# DRI-flexpcb-12s4p.net
KiCad netlist of a schematic drawn in EAGLE
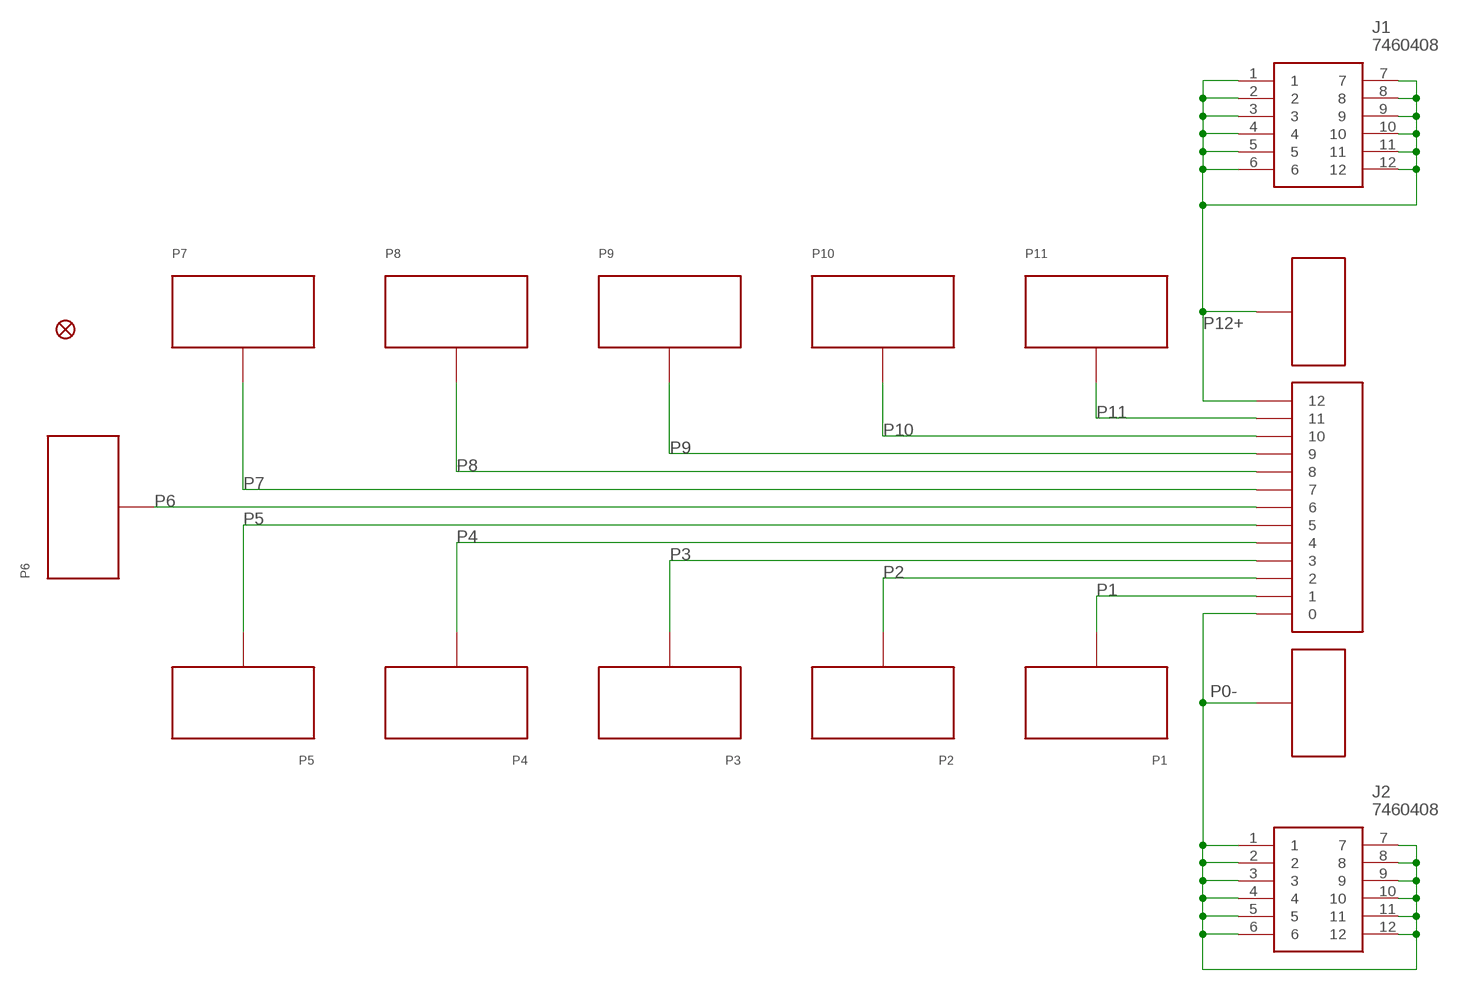
[diagram p0: schematic, sheet 1]

(export (version "E")
  (design (tool "Eeschema 10.0.6"))
  (components
    (comp (ref "FD2")
      (value "FIDUCIAL1X2")
      (footprint "eagle-import:FIDUCIAL-1X2")
      (libsource (lib "eagle-import") (part "FIDUCIAL1X2"))
    )
    (comp (ref "J1")
      (value "7460408")
      (footprint "eagle-import:7460408")
      (fields (field (name "MOUSER_PART_NUMBER") "710-7460408"))
      (libsource (lib "eagle-import") (part "7460408"))
    )
    (comp (ref "J2")
      (value "7460408")
      (footprint "eagle-import:7460408")
      (fields (field (name "MOUSER_PART_NUMBER") "710-7460408"))
      (libsource (lib "eagle-import") (part "7460408"))
    )
    (comp (ref "JP1")
      (value "13P-JST-2MM")
      (footprint "eagle-import:13P-JST-2MM")
      (libsource (lib "eagle-import") (part "13P-JST-2MM"))
    )
    (comp (ref "P0")
      (value "BUS-TERM-PAD-")
      (footprint "eagle-import:TERM-PAD-")
      (libsource (lib "eagle-import") (part "BUS-TERM-PAD-"))
    )
    (comp (ref "P1")
      (value "BAT-TERM-L")
      (footprint "eagle-import:BAT-TERM-L")
      (libsource (lib "eagle-import") (part "BAT-TERM-L"))
    )
    (comp (ref "P2")
      (value "BAT-TERM-M")
      (footprint "eagle-import:BAT-TERM-M")
      (libsource (lib "eagle-import") (part "BAT-TERM-M"))
    )
    (comp (ref "P3")
      (value "BAT-TERM-L")
      (footprint "eagle-import:BAT-TERM-L")
      (libsource (lib "eagle-import") (part "BAT-TERM-L"))
    )
    (comp (ref "P4")
      (value "BAT-TERM-M")
      (footprint "eagle-import:BAT-TERM-M")
      (libsource (lib "eagle-import") (part "BAT-TERM-M"))
    )
    (comp (ref "P5")
      (value "BAT-TERM-L")
      (footprint "eagle-import:BAT-TERM-L")
      (libsource (lib "eagle-import") (part "BAT-TERM-L"))
    )
    (comp (ref "P6")
      (value "BAT-TERM-END")
      (footprint "eagle-import:BAT-TERM-END")
      (libsource (lib "eagle-import") (part "BAT-TERM-END"))
    )
    (comp (ref "P7")
      (value "BAT-TERM-L")
      (footprint "eagle-import:BAT-TERM-L")
      (libsource (lib "eagle-import") (part "BAT-TERM-L"))
    )
    (comp (ref "P8")
      (value "BAT-TERM-M")
      (footprint "eagle-import:BAT-TERM-M")
      (libsource (lib "eagle-import") (part "BAT-TERM-M"))
    )
    (comp (ref "P9")
      (value "BAT-TERM-L")
      (footprint "eagle-import:BAT-TERM-L")
      (libsource (lib "eagle-import") (part "BAT-TERM-L"))
    )
    (comp (ref "P10")
      (value "BAT-TERM-M")
      (footprint "eagle-import:BAT-TERM-M")
      (libsource (lib "eagle-import") (part "BAT-TERM-M"))
    )
    (comp (ref "P11")
      (value "BAT-TERM-L")
      (footprint "eagle-import:BAT-TERM-L")
      (libsource (lib "eagle-import") (part "BAT-TERM-L"))
    )
    (comp (ref "P12")
      (value "BUS-TERM-PAD+")
      (footprint "eagle-import:TERM-PAD-")
      (libsource (lib "eagle-import") (part "BUS-TERM-PAD+"))
    )
  )
  (nets
    (net (code "1") (name "/P0-") (class "Default")
      (node (ref "J2") (pin "1") (pinfunction "1_1") (pintype "bidirectional"))
      (node (ref "J2") (pin "10") (pinfunction "10_10") (pintype "bidirectional"))
      (node (ref "J2") (pin "11") (pinfunction "11_11") (pintype "bidirectional"))
      (node (ref "J2") (pin "12") (pinfunction "12_12") (pintype "bidirectional"))
      (node (ref "J2") (pin "2") (pinfunction "2_2") (pintype "bidirectional"))
      (node (ref "J2") (pin "3") (pinfunction "3_3") (pintype "bidirectional"))
      (node (ref "J2") (pin "4") (pinfunction "4_4") (pintype "bidirectional"))
      (node (ref "J2") (pin "5") (pinfunction "5_5") (pintype "bidirectional"))
      (node (ref "J2") (pin "6") (pinfunction "6_6") (pintype "bidirectional"))
      (node (ref "J2") (pin "7") (pinfunction "7_7") (pintype "bidirectional"))
      (node (ref "J2") (pin "8") (pinfunction "8_8") (pintype "bidirectional"))
      (node (ref "J2") (pin "9") (pinfunction "9_9") (pintype "bidirectional"))
      (node (ref "JP1") (pin "P$1") (pinfunction "0_P$1") (pintype "bidirectional"))
      (node (ref "P0") (pin "P$10") (pinfunction "P$0_P$10") (pintype "power_in"))
      (node (ref "P0") (pin "P$100") (pinfunction "P$0_P$100") (pintype "power_in"))
      (node (ref "P0") (pin "P$101") (pinfunction "P$0_P$101") (pintype "power_in"))
      (node (ref "P0") (pin "P$102") (pinfunction "P$0_P$102") (pintype "power_in"))
      (node (ref "P0") (pin "P$103") (pinfunction "P$0_P$103") (pintype "power_in"))
      (node (ref "P0") (pin "P$104") (pinfunction "P$0_P$104") (pintype "power_in"))
      (node (ref "P0") (pin "P$105") (pinfunction "P$0_P$105") (pintype "power_in"))
      (node (ref "P0") (pin "P$106") (pinfunction "P$0_P$106") (pintype "power_in"))
      (node (ref "P0") (pin "P$107") (pinfunction "P$0_P$107") (pintype "power_in"))
      (node (ref "P0") (pin "P$108") (pinfunction "P$0_P$108") (pintype "power_in"))
      (node (ref "P0") (pin "P$109") (pinfunction "P$0_P$109") (pintype "power_in"))
      (node (ref "P0") (pin "P$11") (pinfunction "P$0_P$11") (pintype "power_in"))
      (node (ref "P0") (pin "P$110") (pinfunction "P$0_P$110") (pintype "power_in"))
      (node (ref "P0") (pin "P$12") (pinfunction "P$0_P$12") (pintype "power_in"))
      (node (ref "P0") (pin "P$13") (pinfunction "P$0_P$13") (pintype "power_in"))
      (node (ref "P0") (pin "P$14") (pinfunction "P$0_P$14") (pintype "power_in"))
      (node (ref "P0") (pin "P$15") (pinfunction "P$0_P$15") (pintype "power_in"))
      (node (ref "P0") (pin "P$16") (pinfunction "P$0_P$16") (pintype "power_in"))
      (node (ref "P0") (pin "P$17") (pinfunction "P$0_P$17") (pintype "power_in"))
      (node (ref "P0") (pin "P$18") (pinfunction "P$0_P$18") (pintype "power_in"))
      (node (ref "P0") (pin "P$181") (pinfunction "P$0_P$181") (pintype "power_in"))
      (node (ref "P0") (pin "P$182") (pinfunction "P$0_P$182") (pintype "power_in"))
      (node (ref "P0") (pin "P$183") (pinfunction "P$0_P$183") (pintype "power_in"))
      (node (ref "P0") (pin "P$184") (pinfunction "P$0_P$184") (pintype "power_in"))
      (node (ref "P0") (pin "P$185") (pinfunction "P$0_P$185") (pintype "power_in"))
      (node (ref "P0") (pin "P$186") (pinfunction "P$0_P$186") (pintype "power_in"))
      (node (ref "P0") (pin "P$187") (pinfunction "P$0_P$187") (pintype "power_in"))
      (node (ref "P0") (pin "P$188") (pinfunction "P$0_P$188") (pintype "power_in"))
      (node (ref "P0") (pin "P$189") (pinfunction "P$0_P$189") (pintype "power_in"))
      (node (ref "P0") (pin "P$19") (pinfunction "P$0_P$19") (pintype "power_in"))
      (node (ref "P0") (pin "P$190") (pinfunction "P$0_P$190") (pintype "power_in"))
      (node (ref "P0") (pin "P$191") (pinfunction "P$0_P$191") (pintype "power_in"))
      (node (ref "P0") (pin "P$192") (pinfunction "P$0_P$192") (pintype "power_in"))
      (node (ref "P0") (pin "P$193") (pinfunction "P$0_P$193") (pintype "power_in"))
      (node (ref "P0") (pin "P$194") (pinfunction "P$0_P$194") (pintype "power_in"))
      (node (ref "P0") (pin "P$195") (pinfunction "P$0_P$195") (pintype "power_in"))
      (node (ref "P0") (pin "P$196") (pinfunction "P$0_P$196") (pintype "power_in"))
      (node (ref "P0") (pin "P$197") (pinfunction "P$0_P$197") (pintype "power_in"))
      (node (ref "P0") (pin "P$198") (pinfunction "P$0_P$198") (pintype "power_in"))
      (node (ref "P0") (pin "P$199") (pinfunction "P$0_P$199") (pintype "power_in"))
      (node (ref "P0") (pin "P$20") (pinfunction "P$0_P$20") (pintype "power_in"))
      (node (ref "P0") (pin "P$200") (pinfunction "P$0_P$200") (pintype "power_in"))
      (node (ref "P0") (pin "P$201") (pinfunction "P$0_P$201") (pintype "power_in"))
      (node (ref "P0") (pin "P$202") (pinfunction "P$0_P$202") (pintype "power_in"))
      (node (ref "P0") (pin "P$203") (pinfunction "P$0_P$203") (pintype "power_in"))
      (node (ref "P0") (pin "P$204") (pinfunction "P$0_P$204") (pintype "power_in"))
      (node (ref "P0") (pin "P$205") (pinfunction "P$0_P$205") (pintype "power_in"))
      (node (ref "P0") (pin "P$206") (pinfunction "P$0_P$206") (pintype "power_in"))
      (node (ref "P0") (pin "P$207") (pinfunction "P$0_P$207") (pintype "power_in"))
      (node (ref "P0") (pin "P$208") (pinfunction "P$0_P$208") (pintype "power_in"))
      (node (ref "P0") (pin "P$209") (pinfunction "P$0_P$209") (pintype "power_in"))
      (node (ref "P0") (pin "P$21") (pinfunction "P$0_P$21") (pintype "power_in"))
      (node (ref "P0") (pin "P$210") (pinfunction "P$0_P$210") (pintype "power_in"))
      (node (ref "P0") (pin "P$211") (pinfunction "P$0_P$211") (pintype "power_in"))
      (node (ref "P0") (pin "P$212") (pinfunction "P$0_P$212") (pintype "power_in"))
      (node (ref "P0") (pin "P$213") (pinfunction "P$0_P$213") (pintype "power_in"))
      (node (ref "P0") (pin "P$214") (pinfunction "P$0_P$214") (pintype "power_in"))
      (node (ref "P0") (pin "P$215") (pinfunction "P$0_P$215") (pintype "power_in"))
      (node (ref "P0") (pin "P$216") (pinfunction "P$0_P$216") (pintype "power_in"))
      (node (ref "P0") (pin "P$217") (pinfunction "P$0_P$217") (pintype "power_in"))
      (node (ref "P0") (pin "P$218") (pinfunction "P$0_P$218") (pintype "power_in"))
      (node (ref "P0") (pin "P$219") (pinfunction "P$0_P$219") (pintype "power_in"))
      (node (ref "P0") (pin "P$22") (pinfunction "P$0_P$22") (pintype "power_in"))
      (node (ref "P0") (pin "P$220") (pinfunction "P$0_P$220") (pintype "power_in"))
      (node (ref "P0") (pin "P$221") (pinfunction "P$0_P$221") (pintype "power_in"))
      (node (ref "P0") (pin "P$222") (pinfunction "P$0_P$222") (pintype "power_in"))
      (node (ref "P0") (pin "P$223") (pinfunction "P$0_P$223") (pintype "power_in"))
      (node (ref "P0") (pin "P$224") (pinfunction "P$0_P$224") (pintype "power_in"))
      (node (ref "P0") (pin "P$225") (pinfunction "P$0_P$225") (pintype "power_in"))
      (node (ref "P0") (pin "P$226") (pinfunction "P$0_P$226") (pintype "power_in"))
      (node (ref "P0") (pin "P$227") (pinfunction "P$0_P$227") (pintype "power_in"))
      (node (ref "P0") (pin "P$228") (pinfunction "P$0_P$228") (pintype "power_in"))
      (node (ref "P0") (pin "P$229") (pinfunction "P$0_P$229") (pintype "power_in"))
      (node (ref "P0") (pin "P$23") (pinfunction "P$0_P$23") (pintype "power_in"))
      (node (ref "P0") (pin "P$230") (pinfunction "P$0_P$230") (pintype "power_in"))
      (node (ref "P0") (pin "P$231") (pinfunction "P$0_P$231") (pintype "power_in"))
      (node (ref "P0") (pin "P$232") (pinfunction "P$0_P$232") (pintype "power_in"))
      (node (ref "P0") (pin "P$233") (pinfunction "P$0_P$233") (pintype "power_in"))
      (node (ref "P0") (pin "P$234") (pinfunction "P$0_P$234") (pintype "power_in"))
      (node (ref "P0") (pin "P$235") (pinfunction "P$0_P$235") (pintype "power_in"))
      (node (ref "P0") (pin "P$236") (pinfunction "P$0_P$236") (pintype "power_in"))
      (node (ref "P0") (pin "P$237") (pinfunction "P$0_P$237") (pintype "power_in"))
      (node (ref "P0") (pin "P$238") (pinfunction "P$0_P$238") (pintype "power_in"))
      (node (ref "P0") (pin "P$239") (pinfunction "P$0_P$239") (pintype "power_in"))
      (node (ref "P0") (pin "P$24") (pinfunction "P$0_P$24") (pintype "power_in"))
      (node (ref "P0") (pin "P$240") (pinfunction "P$0_P$240") (pintype "power_in"))
      (node (ref "P0") (pin "P$241") (pinfunction "P$0_P$241") (pintype "power_in"))
      (node (ref "P0") (pin "P$242") (pinfunction "P$0_P$242") (pintype "power_in"))
      (node (ref "P0") (pin "P$243") (pinfunction "P$0_P$243") (pintype "power_in"))
      (node (ref "P0") (pin "P$244") (pinfunction "P$0_P$244") (pintype "power_in"))
      (node (ref "P0") (pin "P$245") (pinfunction "P$0_P$245") (pintype "power_in"))
      (node (ref "P0") (pin "P$246") (pinfunction "P$0_P$246") (pintype "power_in"))
      (node (ref "P0") (pin "P$247") (pinfunction "P$0_P$247") (pintype "power_in"))
      (node (ref "P0") (pin "P$248") (pinfunction "P$0_P$248") (pintype "power_in"))
      (node (ref "P0") (pin "P$249") (pinfunction "P$0_P$249") (pintype "power_in"))
      (node (ref "P0") (pin "P$25") (pinfunction "P$0_P$25") (pintype "power_in"))
      (node (ref "P0") (pin "P$250") (pinfunction "P$0_P$250") (pintype "power_in"))
      (node (ref "P0") (pin "P$251") (pinfunction "P$0_P$251") (pintype "power_in"))
      (node (ref "P0") (pin "P$252") (pinfunction "P$0_P$252") (pintype "power_in"))
      (node (ref "P0") (pin "P$253") (pinfunction "P$0_P$253") (pintype "power_in"))
      (node (ref "P0") (pin "P$254") (pinfunction "P$0_P$254") (pintype "power_in"))
      (node (ref "P0") (pin "P$255") (pinfunction "P$0_P$255") (pintype "power_in"))
      (node (ref "P0") (pin "P$256") (pinfunction "P$0_P$256") (pintype "power_in"))
      (node (ref "P0") (pin "P$257") (pinfunction "P$0_P$257") (pintype "power_in"))
      (node (ref "P0") (pin "P$258") (pinfunction "P$0_P$258") (pintype "power_in"))
      (node (ref "P0") (pin "P$259") (pinfunction "P$0_P$259") (pintype "power_in"))
      (node (ref "P0") (pin "P$26") (pinfunction "P$0_P$26") (pintype "power_in"))
      (node (ref "P0") (pin "P$260") (pinfunction "P$0_P$260") (pintype "power_in"))
      (node (ref "P0") (pin "P$261") (pinfunction "P$0_P$261") (pintype "power_in"))
      (node (ref "P0") (pin "P$262") (pinfunction "P$0_P$262") (pintype "power_in"))
      (node (ref "P0") (pin "P$263") (pinfunction "P$0_P$263") (pintype "power_in"))
      (node (ref "P0") (pin "P$264") (pinfunction "P$0_P$264") (pintype "power_in"))
      (node (ref "P0") (pin "P$265") (pinfunction "P$0_P$265") (pintype "power_in"))
      (node (ref "P0") (pin "P$266") (pinfunction "P$0_P$266") (pintype "power_in"))
      (node (ref "P0") (pin "P$267") (pinfunction "P$0_P$267") (pintype "power_in"))
      (node (ref "P0") (pin "P$268") (pinfunction "P$0_P$268") (pintype "power_in"))
      (node (ref "P0") (pin "P$269") (pinfunction "P$0_P$269") (pintype "power_in"))
      (node (ref "P0") (pin "P$27") (pinfunction "P$0_P$27") (pintype "power_in"))
      (node (ref "P0") (pin "P$270") (pinfunction "P$0_P$270") (pintype "power_in"))
      (node (ref "P0") (pin "P$271") (pinfunction "P$0_P$271") (pintype "power_in"))
      (node (ref "P0") (pin "P$272") (pinfunction "P$0_P$272") (pintype "power_in"))
      (node (ref "P0") (pin "P$273") (pinfunction "P$0_P$273") (pintype "power_in"))
      (node (ref "P0") (pin "P$274") (pinfunction "P$0_P$274") (pintype "power_in"))
      (node (ref "P0") (pin "P$275") (pinfunction "P$0_P$275") (pintype "power_in"))
      (node (ref "P0") (pin "P$276") (pinfunction "P$0_P$276") (pintype "power_in"))
      (node (ref "P0") (pin "P$277") (pinfunction "P$0_P$277") (pintype "power_in"))
      (node (ref "P0") (pin "P$278") (pinfunction "P$0_P$278") (pintype "power_in"))
      (node (ref "P0") (pin "P$279") (pinfunction "P$0_P$279") (pintype "power_in"))
      (node (ref "P0") (pin "P$28") (pinfunction "P$0_P$28") (pintype "power_in"))
      (node (ref "P0") (pin "P$280") (pinfunction "P$0_P$280") (pintype "power_in"))
      (node (ref "P0") (pin "P$281") (pinfunction "P$0_P$281") (pintype "power_in"))
      (node (ref "P0") (pin "P$282") (pinfunction "P$0_P$282") (pintype "power_in"))
      (node (ref "P0") (pin "P$283") (pinfunction "P$0_P$283") (pintype "power_in"))
      (node (ref "P0") (pin "P$284") (pinfunction "P$0_P$284") (pintype "power_in"))
      (node (ref "P0") (pin "P$285") (pinfunction "P$0_P$285") (pintype "power_in"))
      (node (ref "P0") (pin "P$286") (pinfunction "P$0_P$286") (pintype "power_in"))
      (node (ref "P0") (pin "P$287") (pinfunction "P$0_P$287") (pintype "power_in"))
      (node (ref "P0") (pin "P$288") (pinfunction "P$0_P$288") (pintype "power_in"))
      (node (ref "P0") (pin "P$289") (pinfunction "P$0_P$289") (pintype "power_in"))
      (node (ref "P0") (pin "P$29") (pinfunction "P$0_P$29") (pintype "power_in"))
      (node (ref "P0") (pin "P$290") (pinfunction "P$0_P$290") (pintype "power_in"))
      (node (ref "P0") (pin "P$291") (pinfunction "P$0_P$291") (pintype "power_in"))
      (node (ref "P0") (pin "P$292") (pinfunction "P$0_P$292") (pintype "power_in"))
      (node (ref "P0") (pin "P$293") (pinfunction "P$0_P$293") (pintype "power_in"))
      (node (ref "P0") (pin "P$294") (pinfunction "P$0_P$294") (pintype "power_in"))
      (node (ref "P0") (pin "P$295") (pinfunction "P$0_P$295") (pintype "power_in"))
      (node (ref "P0") (pin "P$296") (pinfunction "P$0_P$296") (pintype "power_in"))
      (node (ref "P0") (pin "P$297") (pinfunction "P$0_P$297") (pintype "power_in"))
      (node (ref "P0") (pin "P$298") (pinfunction "P$0_P$298") (pintype "power_in"))
      (node (ref "P0") (pin "P$299") (pinfunction "P$0_P$299") (pintype "power_in"))
      (node (ref "P0") (pin "P$3") (pinfunction "P$0_P$3") (pintype "power_in"))
      (node (ref "P0") (pin "P$30") (pinfunction "P$0_P$30") (pintype "power_in"))
      (node (ref "P0") (pin "P$300") (pinfunction "P$0_P$300") (pintype "power_in"))
      (node (ref "P0") (pin "P$301") (pinfunction "P$0_P$301") (pintype "power_in"))
      (node (ref "P0") (pin "P$302") (pinfunction "P$0_P$302") (pintype "power_in"))
      (node (ref "P0") (pin "P$303") (pinfunction "P$0_P$303") (pintype "power_in"))
      (node (ref "P0") (pin "P$304") (pinfunction "P$0_P$304") (pintype "power_in"))
      (node (ref "P0") (pin "P$305") (pinfunction "P$0_P$305") (pintype "power_in"))
      (node (ref "P0") (pin "P$306") (pinfunction "P$0_P$306") (pintype "power_in"))
      (node (ref "P0") (pin "P$307") (pinfunction "P$0_P$307") (pintype "power_in"))
      (node (ref "P0") (pin "P$308") (pinfunction "P$0_P$308") (pintype "power_in"))
      (node (ref "P0") (pin "P$309") (pinfunction "P$0_P$309") (pintype "power_in"))
      (node (ref "P0") (pin "P$31") (pinfunction "P$0_P$31") (pintype "power_in"))
      (node (ref "P0") (pin "P$310") (pinfunction "P$0_P$310") (pintype "power_in"))
      (node (ref "P0") (pin "P$311") (pinfunction "P$0_P$311") (pintype "power_in"))
      (node (ref "P0") (pin "P$312") (pinfunction "P$0_P$312") (pintype "power_in"))
      (node (ref "P0") (pin "P$313") (pinfunction "P$0_P$313") (pintype "power_in"))
      (node (ref "P0") (pin "P$314") (pinfunction "P$0_P$314") (pintype "power_in"))
      (node (ref "P0") (pin "P$315") (pinfunction "P$0_P$315") (pintype "power_in"))
      (node (ref "P0") (pin "P$316") (pinfunction "P$0_P$316") (pintype "power_in"))
      (node (ref "P0") (pin "P$317") (pinfunction "P$0_P$317") (pintype "power_in"))
      (node (ref "P0") (pin "P$318") (pinfunction "P$0_P$318") (pintype "power_in"))
      (node (ref "P0") (pin "P$319") (pinfunction "P$0_P$319") (pintype "power_in"))
      (node (ref "P0") (pin "P$32") (pinfunction "P$0_P$32") (pintype "power_in"))
      (node (ref "P0") (pin "P$320") (pinfunction "P$0_P$320") (pintype "power_in"))
      (node (ref "P0") (pin "P$321") (pinfunction "P$0_P$321") (pintype "power_in"))
      (node (ref "P0") (pin "P$322") (pinfunction "P$0_P$322") (pintype "power_in"))
      (node (ref "P0") (pin "P$323") (pinfunction "P$0_P$323") (pintype "power_in"))
      (node (ref "P0") (pin "P$324") (pinfunction "P$0_P$324") (pintype "power_in"))
      (node (ref "P0") (pin "P$325") (pinfunction "P$0_P$325") (pintype "power_in"))
      (node (ref "P0") (pin "P$326") (pinfunction "P$0_P$326") (pintype "power_in"))
      (node (ref "P0") (pin "P$327") (pinfunction "P$0_P$327") (pintype "power_in"))
      (node (ref "P0") (pin "P$328") (pinfunction "P$0_P$328") (pintype "power_in"))
      (node (ref "P0") (pin "P$329") (pinfunction "P$0_P$329") (pintype "power_in"))
      (node (ref "P0") (pin "P$33") (pinfunction "P$0_P$33") (pintype "power_in"))
      (node (ref "P0") (pin "P$330") (pinfunction "P$0_P$330") (pintype "power_in"))
      (node (ref "P0") (pin "P$331") (pinfunction "P$0_P$331") (pintype "power_in"))
      (node (ref "P0") (pin "P$332") (pinfunction "P$0_P$332") (pintype "power_in"))
      (node (ref "P0") (pin "P$333") (pinfunction "P$0_P$333") (pintype "power_in"))
      (node (ref "P0") (pin "P$334") (pinfunction "P$0_P$334") (pintype "power_in"))
      (node (ref "P0") (pin "P$335") (pinfunction "P$0_P$335") (pintype "power_in"))
      (node (ref "P0") (pin "P$336") (pinfunction "P$0_P$336") (pintype "power_in"))
      (node (ref "P0") (pin "P$337") (pinfunction "P$0_P$337") (pintype "power_in"))
      (node (ref "P0") (pin "P$338") (pinfunction "P$0_P$338") (pintype "power_in"))
      (node (ref "P0") (pin "P$339") (pinfunction "P$0_P$339") (pintype "power_in"))
      (node (ref "P0") (pin "P$34") (pinfunction "P$0_P$34") (pintype "power_in"))
      (node (ref "P0") (pin "P$340") (pinfunction "P$0_P$340") (pintype "power_in"))
      (node (ref "P0") (pin "P$341") (pinfunction "P$0_P$341") (pintype "power_in"))
      (node (ref "P0") (pin "P$342") (pinfunction "P$0_P$342") (pintype "power_in"))
      (node (ref "P0") (pin "P$343") (pinfunction "P$0_P$343") (pintype "power_in"))
      (node (ref "P0") (pin "P$344") (pinfunction "P$0_P$344") (pintype "power_in"))
      (node (ref "P0") (pin "P$345") (pinfunction "P$0_P$345") (pintype "power_in"))
      (node (ref "P0") (pin "P$346") (pinfunction "P$0_P$346") (pintype "power_in"))
      (node (ref "P0") (pin "P$347") (pinfunction "P$0_P$347") (pintype "power_in"))
      (node (ref "P0") (pin "P$348") (pinfunction "P$0_P$348") (pintype "power_in"))
      (node (ref "P0") (pin "P$349") (pinfunction "P$0_P$349") (pintype "power_in"))
      (node (ref "P0") (pin "P$35") (pinfunction "P$0_P$35") (pintype "power_in"))
      (node (ref "P0") (pin "P$350") (pinfunction "P$0_P$350") (pintype "power_in"))
      (node (ref "P0") (pin "P$351") (pinfunction "P$0_P$351") (pintype "power_in"))
      (node (ref "P0") (pin "P$352") (pinfunction "P$0_P$352") (pintype "power_in"))
      (node (ref "P0") (pin "P$353") (pinfunction "P$0_P$353") (pintype "power_in"))
      (node (ref "P0") (pin "P$354") (pinfunction "P$0_P$354") (pintype "power_in"))
      (node (ref "P0") (pin "P$355") (pinfunction "P$0_P$355") (pintype "power_in"))
      (node (ref "P0") (pin "P$356") (pinfunction "P$0_P$356") (pintype "power_in"))
      (node (ref "P0") (pin "P$357") (pinfunction "P$0_P$357") (pintype "power_in"))
      (node (ref "P0") (pin "P$358") (pinfunction "P$0_P$358") (pintype "power_in"))
      (node (ref "P0") (pin "P$359") (pinfunction "P$0_P$359") (pintype "power_in"))
      (node (ref "P0") (pin "P$36") (pinfunction "P$0_P$36") (pintype "power_in"))
      (node (ref "P0") (pin "P$360") (pinfunction "P$0_P$360") (pintype "power_in"))
      (node (ref "P0") (pin "P$37") (pinfunction "P$0_P$37") (pintype "power_in"))
      (node (ref "P0") (pin "P$38") (pinfunction "P$0_P$38") (pintype "power_in"))
      (node (ref "P0") (pin "P$39") (pinfunction "P$0_P$39") (pintype "power_in"))
      (node (ref "P0") (pin "P$4") (pinfunction "P$0_P$4") (pintype "power_in"))
      (node (ref "P0") (pin "P$40") (pinfunction "P$0_P$40") (pintype "power_in"))
      (node (ref "P0") (pin "P$41") (pinfunction "P$0_P$41") (pintype "power_in"))
      (node (ref "P0") (pin "P$42") (pinfunction "P$0_P$42") (pintype "power_in"))
      (node (ref "P0") (pin "P$43") (pinfunction "P$0_P$43") (pintype "power_in"))
      (node (ref "P0") (pin "P$44") (pinfunction "P$0_P$44") (pintype "power_in"))
      (node (ref "P0") (pin "P$45") (pinfunction "P$0_P$45") (pintype "power_in"))
      (node (ref "P0") (pin "P$46") (pinfunction "P$0_P$46") (pintype "power_in"))
      (node (ref "P0") (pin "P$47") (pinfunction "P$0_P$47") (pintype "power_in"))
      (node (ref "P0") (pin "P$48") (pinfunction "P$0_P$48") (pintype "power_in"))
      (node (ref "P0") (pin "P$49") (pinfunction "P$0_P$49") (pintype "power_in"))
      (node (ref "P0") (pin "P$5") (pinfunction "P$0_P$5") (pintype "power_in"))
      (node (ref "P0") (pin "P$50") (pinfunction "P$0_P$50") (pintype "power_in"))
      (node (ref "P0") (pin "P$51") (pinfunction "P$0_P$51") (pintype "power_in"))
      (node (ref "P0") (pin "P$52") (pinfunction "P$0_P$52") (pintype "power_in"))
      (node (ref "P0") (pin "P$53") (pinfunction "P$0_P$53") (pintype "power_in"))
      (node (ref "P0") (pin "P$54") (pinfunction "P$0_P$54") (pintype "power_in"))
      (node (ref "P0") (pin "P$55") (pinfunction "P$0_P$55") (pintype "power_in"))
      (node (ref "P0") (pin "P$56") (pinfunction "P$0_P$56") (pintype "power_in"))
      (node (ref "P0") (pin "P$57") (pinfunction "P$0_P$57") (pintype "power_in"))
      (node (ref "P0") (pin "P$58") (pinfunction "P$0_P$58") (pintype "power_in"))
      (node (ref "P0") (pin "P$59") (pinfunction "P$0_P$59") (pintype "power_in"))
      (node (ref "P0") (pin "P$6") (pinfunction "P$0_P$6") (pintype "power_in"))
      (node (ref "P0") (pin "P$60") (pinfunction "P$0_P$60") (pintype "power_in"))
      (node (ref "P0") (pin "P$61") (pinfunction "P$0_P$61") (pintype "power_in"))
      (node (ref "P0") (pin "P$62") (pinfunction "P$0_P$62") (pintype "power_in"))
      (node (ref "P0") (pin "P$63") (pinfunction "P$0_P$63") (pintype "power_in"))
      (node (ref "P0") (pin "P$64") (pinfunction "P$0_P$64") (pintype "power_in"))
      (node (ref "P0") (pin "P$65") (pinfunction "P$0_P$65") (pintype "power_in"))
      (node (ref "P0") (pin "P$66") (pinfunction "P$0_P$66") (pintype "power_in"))
      (node (ref "P0") (pin "P$67") (pinfunction "P$0_P$67") (pintype "power_in"))
      (node (ref "P0") (pin "P$68") (pinfunction "P$0_P$68") (pintype "power_in"))
      (node (ref "P0") (pin "P$69") (pinfunction "P$0_P$69") (pintype "power_in"))
      (node (ref "P0") (pin "P$7") (pinfunction "P$0_P$7") (pintype "power_in"))
      (node (ref "P0") (pin "P$70") (pinfunction "P$0_P$70") (pintype "power_in"))
      (node (ref "P0") (pin "P$71") (pinfunction "P$0_P$71") (pintype "power_in"))
      (node (ref "P0") (pin "P$72") (pinfunction "P$0_P$72") (pintype "power_in"))
      (node (ref "P0") (pin "P$73") (pinfunction "P$0_P$73") (pintype "power_in"))
      (node (ref "P0") (pin "P$74") (pinfunction "P$0_P$74") (pintype "power_in"))
      (node (ref "P0") (pin "P$75") (pinfunction "P$0_P$75") (pintype "power_in"))
      (node (ref "P0") (pin "P$76") (pinfunction "P$0_P$76") (pintype "power_in"))
      (node (ref "P0") (pin "P$77") (pinfunction "P$0_P$77") (pintype "power_in"))
      (node (ref "P0") (pin "P$78") (pinfunction "P$0_P$78") (pintype "power_in"))
      (node (ref "P0") (pin "P$79") (pinfunction "P$0_P$79") (pintype "power_in"))
      (node (ref "P0") (pin "P$8") (pinfunction "P$0_P$8") (pintype "power_in"))
      (node (ref "P0") (pin "P$80") (pinfunction "P$0_P$80") (pintype "power_in"))
      (node (ref "P0") (pin "P$81") (pinfunction "P$0_P$81") (pintype "power_in"))
      (node (ref "P0") (pin "P$82") (pinfunction "P$0_P$82") (pintype "power_in"))
      (node (ref "P0") (pin "P$83") (pinfunction "P$0_P$83") (pintype "power_in"))
      (node (ref "P0") (pin "P$84") (pinfunction "P$0_P$84") (pintype "power_in"))
      (node (ref "P0") (pin "P$85") (pinfunction "P$0_P$85") (pintype "power_in"))
      (node (ref "P0") (pin "P$86") (pinfunction "P$0_P$86") (pintype "power_in"))
      (node (ref "P0") (pin "P$87") (pinfunction "P$0_P$87") (pintype "power_in"))
      (node (ref "P0") (pin "P$88") (pinfunction "P$0_P$88") (pintype "power_in"))
      (node (ref "P0") (pin "P$89") (pinfunction "P$0_P$89") (pintype "power_in"))
      (node (ref "P0") (pin "P$9") (pinfunction "P$0_P$9") (pintype "power_in"))
      (node (ref "P0") (pin "P$90") (pinfunction "P$0_P$90") (pintype "power_in"))
      (node (ref "P0") (pin "P$91") (pinfunction "P$0_P$91") (pintype "power_in"))
      (node (ref "P0") (pin "P$92") (pinfunction "P$0_P$92") (pintype "power_in"))
      (node (ref "P0") (pin "P$93") (pinfunction "P$0_P$93") (pintype "power_in"))
      (node (ref "P0") (pin "P$94") (pinfunction "P$0_P$94") (pintype "power_in"))
      (node (ref "P0") (pin "P$95") (pinfunction "P$0_P$95") (pintype "power_in"))
      (node (ref "P0") (pin "P$96") (pinfunction "P$0_P$96") (pintype "power_in"))
      (node (ref "P0") (pin "P$97") (pinfunction "P$0_P$97") (pintype "power_in"))
      (node (ref "P0") (pin "P$98") (pinfunction "P$0_P$98") (pintype "power_in"))
      (node (ref "P0") (pin "P$99") (pinfunction "P$0_P$99") (pintype "power_in"))
    )
    (net (code "2") (name "/P1") (class "Default")
      (node (ref "JP1") (pin "P$2") (pinfunction "1_P$2") (pintype "bidirectional"))
      (node (ref "P1") (pin "P$1") (pinfunction "P$1_P$1") (pintype "power_in"))
      (node (ref "P1") (pin "P$10") (pinfunction "P$1_P$10") (pintype "power_in"))
      (node (ref "P1") (pin "P$100") (pinfunction "P$1_P$100") (pintype "power_in"))
      (node (ref "P1") (pin "P$101") (pinfunction "P$1_P$101") (pintype "power_in"))
      (node (ref "P1") (pin "P$102") (pinfunction "P$1_P$102") (pintype "power_in"))
      (node (ref "P1") (pin "P$103") (pinfunction "P$1_P$103") (pintype "power_in"))
      (node (ref "P1") (pin "P$104") (pinfunction "P$1_P$104") (pintype "power_in"))
      (node (ref "P1") (pin "P$105") (pinfunction "P$1_P$105") (pintype "power_in"))
      (node (ref "P1") (pin "P$106") (pinfunction "P$1_P$106") (pintype "power_in"))
      (node (ref "P1") (pin "P$107") (pinfunction "P$1_P$107") (pintype "power_in"))
      (node (ref "P1") (pin "P$108") (pinfunction "P$1_P$108") (pintype "power_in"))
      (node (ref "P1") (pin "P$109") (pinfunction "P$1_P$109") (pintype "power_in"))
      (node (ref "P1") (pin "P$11") (pinfunction "P$1_P$11") (pintype "power_in"))
      (node (ref "P1") (pin "P$110") (pinfunction "P$1_P$110") (pintype "power_in"))
      (node (ref "P1") (pin "P$111") (pinfunction "P$1_P$111") (pintype "power_in"))
      (node (ref "P1") (pin "P$112") (pinfunction "P$1_P$112") (pintype "power_in"))
      (node (ref "P1") (pin "P$113") (pinfunction "P$1_P$113") (pintype "power_in"))
      (node (ref "P1") (pin "P$114") (pinfunction "P$1_P$114") (pintype "power_in"))
      (node (ref "P1") (pin "P$115") (pinfunction "P$1_P$115") (pintype "power_in"))
      (node (ref "P1") (pin "P$116") (pinfunction "P$1_P$116") (pintype "power_in"))
      (node (ref "P1") (pin "P$117") (pinfunction "P$1_P$117") (pintype "power_in"))
      (node (ref "P1") (pin "P$118") (pinfunction "P$1_P$118") (pintype "power_in"))
      (node (ref "P1") (pin "P$119") (pinfunction "P$1_P$119") (pintype "power_in"))
      (node (ref "P1") (pin "P$12") (pinfunction "P$1_P$12") (pintype "power_in"))
      (node (ref "P1") (pin "P$120") (pinfunction "P$1_P$120") (pintype "power_in"))
      (node (ref "P1") (pin "P$121") (pinfunction "P$1_P$121") (pintype "power_in"))
      (node (ref "P1") (pin "P$122") (pinfunction "P$1_P$122") (pintype "power_in"))
      (node (ref "P1") (pin "P$123") (pinfunction "P$1_P$123") (pintype "power_in"))
      (node (ref "P1") (pin "P$124") (pinfunction "P$1_P$124") (pintype "power_in"))
      (node (ref "P1") (pin "P$125") (pinfunction "P$1_P$125") (pintype "power_in"))
      (node (ref "P1") (pin "P$126") (pinfunction "P$1_P$126") (pintype "power_in"))
      (node (ref "P1") (pin "P$127") (pinfunction "P$1_P$127") (pintype "power_in"))
      (node (ref "P1") (pin "P$128") (pinfunction "P$1_P$128") (pintype "power_in"))
      (node (ref "P1") (pin "P$129") (pinfunction "P$1_P$129") (pintype "power_in"))
      (node (ref "P1") (pin "P$13") (pinfunction "P$1_P$13") (pintype "power_in"))
      (node (ref "P1") (pin "P$130") (pinfunction "P$1_P$130") (pintype "power_in"))
      (node (ref "P1") (pin "P$131") (pinfunction "P$1_P$131") (pintype "power_in"))
      (node (ref "P1") (pin "P$132") (pinfunction "P$1_P$132") (pintype "power_in"))
      (node (ref "P1") (pin "P$133") (pinfunction "P$1_P$133") (pintype "power_in"))
      (node (ref "P1") (pin "P$134") (pinfunction "P$1_P$134") (pintype "power_in"))
      (node (ref "P1") (pin "P$135") (pinfunction "P$1_P$135") (pintype "power_in"))
      (node (ref "P1") (pin "P$136") (pinfunction "P$1_P$136") (pintype "power_in"))
      (node (ref "P1") (pin "P$137") (pinfunction "P$1_P$137") (pintype "power_in"))
      (node (ref "P1") (pin "P$138") (pinfunction "P$1_P$138") (pintype "power_in"))
      (node (ref "P1") (pin "P$139") (pinfunction "P$1_P$139") (pintype "power_in"))
      (node (ref "P1") (pin "P$14") (pinfunction "P$1_P$14") (pintype "power_in"))
      (node (ref "P1") (pin "P$140") (pinfunction "P$1_P$140") (pintype "power_in"))
      (node (ref "P1") (pin "P$141") (pinfunction "P$1_P$141") (pintype "power_in"))
      (node (ref "P1") (pin "P$142") (pinfunction "P$1_P$142") (pintype "power_in"))
      (node (ref "P1") (pin "P$143") (pinfunction "P$1_P$143") (pintype "power_in"))
      (node (ref "P1") (pin "P$144") (pinfunction "P$1_P$144") (pintype "power_in"))
      (node (ref "P1") (pin "P$145") (pinfunction "P$1_P$145") (pintype "power_in"))
      (node (ref "P1") (pin "P$146") (pinfunction "P$1_P$146") (pintype "power_in"))
      (node (ref "P1") (pin "P$147") (pinfunction "P$1_P$147") (pintype "power_in"))
      (node (ref "P1") (pin "P$148") (pinfunction "P$1_P$148") (pintype "power_in"))
      (node (ref "P1") (pin "P$149") (pinfunction "P$1_P$149") (pintype "power_in"))
      (node (ref "P1") (pin "P$15") (pinfunction "P$1_P$15") (pintype "power_in"))
      (node (ref "P1") (pin "P$150") (pinfunction "P$1_P$150") (pintype "power_in"))
      (node (ref "P1") (pin "P$151") (pinfunction "P$1_P$151") (pintype "power_in"))
      (node (ref "P1") (pin "P$152") (pinfunction "P$1_P$152") (pintype "power_in"))
      (node (ref "P1") (pin "P$153") (pinfunction "P$1_P$153") (pintype "power_in"))
      (node (ref "P1") (pin "P$154") (pinfunction "P$1_P$154") (pintype "power_in"))
      (node (ref "P1") (pin "P$155") (pinfunction "P$1_P$155") (pintype "power_in"))
      (node (ref "P1") (pin "P$156") (pinfunction "P$1_P$156") (pintype "power_in"))
      (node (ref "P1") (pin "P$157") (pinfunction "P$1_P$157") (pintype "power_in"))
      (node (ref "P1") (pin "P$158") (pinfunction "P$1_P$158") (pintype "power_in"))
      (node (ref "P1") (pin "P$159") (pinfunction "P$1_P$159") (pintype "power_in"))
      (node (ref "P1") (pin "P$16") (pinfunction "P$1_P$16") (pintype "power_in"))
      (node (ref "P1") (pin "P$160") (pinfunction "P$1_P$160") (pintype "power_in"))
      (node (ref "P1") (pin "P$161") (pinfunction "P$1_P$161") (pintype "power_in"))
      (node (ref "P1") (pin "P$162") (pinfunction "P$1_P$162") (pintype "power_in"))
      (node (ref "P1") (pin "P$163") (pinfunction "P$1_P$163") (pintype "power_in"))
      (node (ref "P1") (pin "P$164") (pinfunction "P$1_P$164") (pintype "power_in"))
      (node (ref "P1") (pin "P$165") (pinfunction "P$1_P$165") (pintype "power_in"))
      (node (ref "P1") (pin "P$166") (pinfunction "P$1_P$166") (pintype "power_in"))
      (node (ref "P1") (pin "P$167") (pinfunction "P$1_P$167") (pintype "power_in"))
      (node (ref "P1") (pin "P$168") (pinfunction "P$1_P$168") (pintype "power_in"))
      (node (ref "P1") (pin "P$169") (pinfunction "P$1_P$169") (pintype "power_in"))
      (node (ref "P1") (pin "P$17") (pinfunction "P$1_P$17") (pintype "power_in"))
      (node (ref "P1") (pin "P$170") (pinfunction "P$1_P$170") (pintype "power_in"))
      (node (ref "P1") (pin "P$171") (pinfunction "P$1_P$171") (pintype "power_in"))
      (node (ref "P1") (pin "P$172") (pinfunction "P$1_P$172") (pintype "power_in"))
      (node (ref "P1") (pin "P$173") (pinfunction "P$1_P$173") (pintype "power_in"))
      (node (ref "P1") (pin "P$174") (pinfunction "P$1_P$174") (pintype "power_in"))
      (node (ref "P1") (pin "P$175") (pinfunction "P$1_P$175") (pintype "power_in"))
      (node (ref "P1") (pin "P$176") (pinfunction "P$1_P$176") (pintype "power_in"))
      (node (ref "P1") (pin "P$177") (pinfunction "P$1_P$177") (pintype "power_in"))
      (node (ref "P1") (pin "P$178") (pinfunction "P$1_P$178") (pintype "power_in"))
      (node (ref "P1") (pin "P$179") (pinfunction "P$1_P$179") (pintype "power_in"))
      (node (ref "P1") (pin "P$18") (pinfunction "P$1_P$18") (pintype "power_in"))
      (node (ref "P1") (pin "P$180") (pinfunction "P$1_P$180") (pintype "power_in"))
      (node (ref "P1") (pin "P$181") (pinfunction "P$1_P$181") (pintype "power_in"))
      (node (ref "P1") (pin "P$182") (pinfunction "P$1_P$182") (pintype "power_in"))
      (node (ref "P1") (pin "P$183") (pinfunction "P$1_P$183") (pintype "power_in"))
      (node (ref "P1") (pin "P$184") (pinfunction "P$1_P$184") (pintype "power_in"))
      (node (ref "P1") (pin "P$185") (pinfunction "P$1_P$185") (pintype "power_in"))
      (node (ref "P1") (pin "P$186") (pinfunction "P$1_P$186") (pintype "power_in"))
      (node (ref "P1") (pin "P$187") (pinfunction "P$1_P$187") (pintype "power_in"))
      (node (ref "P1") (pin "P$188") (pinfunction "P$1_P$188") (pintype "power_in"))
      (node (ref "P1") (pin "P$189") (pinfunction "P$1_P$189") (pintype "power_in"))
      (node (ref "P1") (pin "P$19") (pinfunction "P$1_P$19") (pintype "power_in"))
      (node (ref "P1") (pin "P$190") (pinfunction "P$1_P$190") (pintype "power_in"))
      (node (ref "P1") (pin "P$191") (pinfunction "P$1_P$191") (pintype "power_in"))
      (node (ref "P1") (pin "P$192") (pinfunction "P$1_P$192") (pintype "power_in"))
      (node (ref "P1") (pin "P$193") (pinfunction "P$1_P$193") (pintype "power_in"))
      (node (ref "P1") (pin "P$194") (pinfunction "P$1_P$194") (pintype "power_in"))
      (node (ref "P1") (pin "P$195") (pinfunction "P$1_P$195") (pintype "power_in"))
      (node (ref "P1") (pin "P$196") (pinfunction "P$1_P$196") (pintype "power_in"))
      (node (ref "P1") (pin "P$197") (pinfunction "P$1_P$197") (pintype "power_in"))
      (node (ref "P1") (pin "P$198") (pinfunction "P$1_P$198") (pintype "power_in"))
      (node (ref "P1") (pin "P$199") (pinfunction "P$1_P$199") (pintype "power_in"))
      (node (ref "P1") (pin "P$2") (pinfunction "P$1_P$2") (pintype "power_in"))
      (node (ref "P1") (pin "P$20") (pinfunction "P$1_P$20") (pintype "power_in"))
      (node (ref "P1") (pin "P$200") (pinfunction "P$1_P$200") (pintype "power_in"))
      (node (ref "P1") (pin "P$201") (pinfunction "P$1_P$201") (pintype "power_in"))
      (node (ref "P1") (pin "P$202") (pinfunction "P$1_P$202") (pintype "power_in"))
      (node (ref "P1") (pin "P$203") (pinfunction "P$1_P$203") (pintype "power_in"))
      (node (ref "P1") (pin "P$204") (pinfunction "P$1_P$204") (pintype "power_in"))
      (node (ref "P1") (pin "P$205") (pinfunction "P$1_P$205") (pintype "power_in"))
      (node (ref "P1") (pin "P$206") (pinfunction "P$1_P$206") (pintype "power_in"))
      (node (ref "P1") (pin "P$207") (pinfunction "P$1_P$207") (pintype "power_in"))
      (node (ref "P1") (pin "P$208") (pinfunction "P$1_P$208") (pintype "power_in"))
      (node (ref "P1") (pin "P$209") (pinfunction "P$1_P$209") (pintype "power_in"))
      (node (ref "P1") (pin "P$21") (pinfunction "P$1_P$21") (pintype "power_in"))
      (node (ref "P1") (pin "P$210") (pinfunction "P$1_P$210") (pintype "power_in"))
      (node (ref "P1") (pin "P$211") (pinfunction "P$1_P$211") (pintype "power_in"))
      (node (ref "P1") (pin "P$212") (pinfunction "P$1_P$212") (pintype "power_in"))
      (node (ref "P1") (pin "P$213") (pinfunction "P$1_P$213") (pintype "power_in"))
      (node (ref "P1") (pin "P$214") (pinfunction "P$1_P$214") (pintype "power_in"))
      (node (ref "P1") (pin "P$215") (pinfunction "P$1_P$215") (pintype "power_in"))
      (node (ref "P1") (pin "P$216") (pinfunction "P$1_P$216") (pintype "power_in"))
      (node (ref "P1") (pin "P$217") (pinfunction "P$1_P$217") (pintype "power_in"))
      (node (ref "P1") (pin "P$218") (pinfunction "P$1_P$218") (pintype "power_in"))
      (node (ref "P1") (pin "P$219") (pinfunction "P$1_P$219") (pintype "power_in"))
      (node (ref "P1") (pin "P$22") (pinfunction "P$1_P$22") (pintype "power_in"))
      (node (ref "P1") (pin "P$220") (pinfunction "P$1_P$220") (pintype "power_in"))
      (node (ref "P1") (pin "P$221") (pinfunction "P$1_P$221") (pintype "power_in"))
      (node (ref "P1") (pin "P$222") (pinfunction "P$1_P$222") (pintype "power_in"))
      (node (ref "P1") (pin "P$223") (pinfunction "P$1_P$223") (pintype "power_in"))
      (node (ref "P1") (pin "P$224") (pinfunction "P$1_P$224") (pintype "power_in"))
      (node (ref "P1") (pin "P$225") (pinfunction "P$1_P$225") (pintype "power_in"))
      (node (ref "P1") (pin "P$226") (pinfunction "P$1_P$226") (pintype "power_in"))
      (node (ref "P1") (pin "P$227") (pinfunction "P$1_P$227") (pintype "power_in"))
      (node (ref "P1") (pin "P$228") (pinfunction "P$1_P$228") (pintype "power_in"))
      (node (ref "P1") (pin "P$229") (pinfunction "P$1_P$229") (pintype "power_in"))
      (node (ref "P1") (pin "P$23") (pinfunction "P$1_P$23") (pintype "power_in"))
      (node (ref "P1") (pin "P$230") (pinfunction "P$1_P$230") (pintype "power_in"))
      (node (ref "P1") (pin "P$231") (pinfunction "P$1_P$231") (pintype "power_in"))
      (node (ref "P1") (pin "P$232") (pinfunction "P$1_P$232") (pintype "power_in"))
      (node (ref "P1") (pin "P$233") (pinfunction "P$1_P$233") (pintype "power_in"))
      (node (ref "P1") (pin "P$234") (pinfunction "P$1_P$234") (pintype "power_in"))
      (node (ref "P1") (pin "P$235") (pinfunction "P$1_P$235") (pintype "power_in"))
      (node (ref "P1") (pin "P$236") (pinfunction "P$1_P$236") (pintype "power_in"))
      (node (ref "P1") (pin "P$237") (pinfunction "P$1_P$237") (pintype "power_in"))
      (node (ref "P1") (pin "P$238") (pinfunction "P$1_P$238") (pintype "power_in"))
      (node (ref "P1") (pin "P$239") (pinfunction "P$1_P$239") (pintype "power_in"))
      (node (ref "P1") (pin "P$24") (pinfunction "P$1_P$24") (pintype "power_in"))
      (node (ref "P1") (pin "P$240") (pinfunction "P$1_P$240") (pintype "power_in"))
      (node (ref "P1") (pin "P$241") (pinfunction "P$1_P$241") (pintype "power_in"))
      (node (ref "P1") (pin "P$242") (pinfunction "P$1_P$242") (pintype "power_in"))
      (node (ref "P1") (pin "P$243") (pinfunction "P$1_P$243") (pintype "power_in"))
      (node (ref "P1") (pin "P$244") (pinfunction "P$1_P$244") (pintype "power_in"))
      (node (ref "P1") (pin "P$245") (pinfunction "P$1_P$245") (pintype "power_in"))
      (node (ref "P1") (pin "P$246") (pinfunction "P$1_P$246") (pintype "power_in"))
      (node (ref "P1") (pin "P$247") (pinfunction "P$1_P$247") (pintype "power_in"))
      (node (ref "P1") (pin "P$248") (pinfunction "P$1_P$248") (pintype "power_in"))
      (node (ref "P1") (pin "P$249") (pinfunction "P$1_P$249") (pintype "power_in"))
      (node (ref "P1") (pin "P$25") (pinfunction "P$1_P$25") (pintype "power_in"))
      (node (ref "P1") (pin "P$250") (pinfunction "P$1_P$250") (pintype "power_in"))
      (node (ref "P1") (pin "P$251") (pinfunction "P$1_P$251") (pintype "power_in"))
      (node (ref "P1") (pin "P$252") (pinfunction "P$1_P$252") (pintype "power_in"))
      (node (ref "P1") (pin "P$253") (pinfunction "P$1_P$253") (pintype "power_in"))
      (node (ref "P1") (pin "P$254") (pinfunction "P$1_P$254") (pintype "power_in"))
      (node (ref "P1") (pin "P$255") (pinfunction "P$1_P$255") (pintype "power_in"))
      (node (ref "P1") (pin "P$256") (pinfunction "P$1_P$256") (pintype "power_in"))
      (node (ref "P1") (pin "P$257") (pinfunction "P$1_P$257") (pintype "power_in"))
      (node (ref "P1") (pin "P$258") (pinfunction "P$1_P$258") (pintype "power_in"))
      (node (ref "P1") (pin "P$259") (pinfunction "P$1_P$259") (pintype "power_in"))
      (node (ref "P1") (pin "P$26") (pinfunction "P$1_P$26") (pintype "power_in"))
      (node (ref "P1") (pin "P$260") (pinfunction "P$1_P$260") (pintype "power_in"))
      (node (ref "P1") (pin "P$261") (pinfunction "P$1_P$261") (pintype "power_in"))
      (node (ref "P1") (pin "P$262") (pinfunction "P$1_P$262") (pintype "power_in"))
      (node (ref "P1") (pin "P$263") (pinfunction "P$1_P$263") (pintype "power_in"))
      (node (ref "P1") (pin "P$264") (pinfunction "P$1_P$264") (pintype "power_in"))
      (node (ref "P1") (pin "P$265") (pinfunction "P$1_P$265") (pintype "power_in"))
      (node (ref "P1") (pin "P$266") (pinfunction "P$1_P$266") (pintype "power_in"))
      (node (ref "P1") (pin "P$267") (pinfunction "P$1_P$267") (pintype "power_in"))
      (node (ref "P1") (pin "P$268") (pinfunction "P$1_P$268") (pintype "power_in"))
      (node (ref "P1") (pin "P$269") (pinfunction "P$1_P$269") (pintype "power_in"))
      (node (ref "P1") (pin "P$27") (pinfunction "P$1_P$27") (pintype "power_in"))
      (node (ref "P1") (pin "P$270") (pinfunction "P$1_P$270") (pintype "power_in"))
      (node (ref "P1") (pin "P$271") (pinfunction "P$1_P$271") (pintype "power_in"))
      (node (ref "P1") (pin "P$272") (pinfunction "P$1_P$272") (pintype "power_in"))
      (node (ref "P1") (pin "P$273") (pinfunction "P$1_P$273") (pintype "power_in"))
      (node (ref "P1") (pin "P$274") (pinfunction "P$1_P$274") (pintype "power_in"))
      (node (ref "P1") (pin "P$275") (pinfunction "P$1_P$275") (pintype "power_in"))
      (node (ref "P1") (pin "P$276") (pinfunction "P$1_P$276") (pintype "power_in"))
      (node (ref "P1") (pin "P$277") (pinfunction "P$1_P$277") (pintype "power_in"))
      (node (ref "P1") (pin "P$278") (pinfunction "P$1_P$278") (pintype "power_in"))
      (node (ref "P1") (pin "P$279") (pinfunction "P$1_P$279") (pintype "power_in"))
      (node (ref "P1") (pin "P$28") (pinfunction "P$1_P$28") (pintype "power_in"))
      (node (ref "P1") (pin "P$280") (pinfunction "P$1_P$280") (pintype "power_in"))
      (node (ref "P1") (pin "P$281") (pinfunction "P$1_P$281") (pintype "power_in"))
      (node (ref "P1") (pin "P$282") (pinfunction "P$1_P$282") (pintype "power_in"))
      (node (ref "P1") (pin "P$283") (pinfunction "P$1_P$283") (pintype "power_in"))
      (node (ref "P1") (pin "P$284") (pinfunction "P$1_P$284") (pintype "power_in"))
      (node (ref "P1") (pin "P$285") (pinfunction "P$1_P$285") (pintype "power_in"))
      (node (ref "P1") (pin "P$286") (pinfunction "P$1_P$286") (pintype "power_in"))
      (node (ref "P1") (pin "P$287") (pinfunction "P$1_P$287") (pintype "power_in"))
      (node (ref "P1") (pin "P$288") (pinfunction "P$1_P$288") (pintype "power_in"))
      (node (ref "P1") (pin "P$29") (pinfunction "P$1_P$29") (pintype "power_in"))
      (node (ref "P1") (pin "P$3") (pinfunction "P$1_P$3") (pintype "power_in"))
      (node (ref "P1") (pin "P$30") (pinfunction "P$1_P$30") (pintype "power_in"))
      (node (ref "P1") (pin "P$31") (pinfunction "P$1_P$31") (pintype "power_in"))
      (node (ref "P1") (pin "P$32") (pinfunction "P$1_P$32") (pintype "power_in"))
      (node (ref "P1") (pin "P$33") (pinfunction "P$1_P$33") (pintype "power_in"))
      (node (ref "P1") (pin "P$34") (pinfunction "P$1_P$34") (pintype "power_in"))
      (node (ref "P1") (pin "P$35") (pinfunction "P$1_P$35") (pintype "power_in"))
      (node (ref "P1") (pin "P$36") (pinfunction "P$1_P$36") (pintype "power_in"))
      (node (ref "P1") (pin "P$37") (pinfunction "P$1_P$37") (pintype "power_in"))
      (node (ref "P1") (pin "P$38") (pinfunction "P$1_P$38") (pintype "power_in"))
      (node (ref "P1") (pin "P$39") (pinfunction "P$1_P$39") (pintype "power_in"))
      (node (ref "P1") (pin "P$4") (pinfunction "P$1_P$4") (pintype "power_in"))
      (node (ref "P1") (pin "P$40") (pinfunction "P$1_P$40") (pintype "power_in"))
      (node (ref "P1") (pin "P$41") (pinfunction "P$1_P$41") (pintype "power_in"))
      (node (ref "P1") (pin "P$42") (pinfunction "P$1_P$42") (pintype "power_in"))
      (node (ref "P1") (pin "P$43") (pinfunction "P$1_P$43") (pintype "power_in"))
      (node (ref "P1") (pin "P$44") (pinfunction "P$1_P$44") (pintype "power_in"))
      (node (ref "P1") (pin "P$45") (pinfunction "P$1_P$45") (pintype "power_in"))
      (node (ref "P1") (pin "P$46") (pinfunction "P$1_P$46") (pintype "power_in"))
      (node (ref "P1") (pin "P$47") (pinfunction "P$1_P$47") (pintype "power_in"))
      (node (ref "P1") (pin "P$48") (pinfunction "P$1_P$48") (pintype "power_in"))
      (node (ref "P1") (pin "P$49") (pinfunction "P$1_P$49") (pintype "power_in"))
      (node (ref "P1") (pin "P$5") (pinfunction "P$1_P$5") (pintype "power_in"))
      (node (ref "P1") (pin "P$50") (pinfunction "P$1_P$50") (pintype "power_in"))
      (node (ref "P1") (pin "P$51") (pinfunction "P$1_P$51") (pintype "power_in"))
      (node (ref "P1") (pin "P$52") (pinfunction "P$1_P$52") (pintype "power_in"))
      (node (ref "P1") (pin "P$53") (pinfunction "P$1_P$53") (pintype "power_in"))
      (node (ref "P1") (pin "P$54") (pinfunction "P$1_P$54") (pintype "power_in"))
      (node (ref "P1") (pin "P$55") (pinfunction "P$1_P$55") (pintype "power_in"))
      (node (ref "P1") (pin "P$56") (pinfunction "P$1_P$56") (pintype "power_in"))
      (node (ref "P1") (pin "P$57") (pinfunction "P$1_P$57") (pintype "power_in"))
      (node (ref "P1") (pin "P$58") (pinfunction "P$1_P$58") (pintype "power_in"))
      (node (ref "P1") (pin "P$59") (pinfunction "P$1_P$59") (pintype "power_in"))
      (node (ref "P1") (pin "P$6") (pinfunction "P$1_P$6") (pintype "power_in"))
      (node (ref "P1") (pin "P$60") (pinfunction "P$1_P$60") (pintype "power_in"))
      (node (ref "P1") (pin "P$61") (pinfunction "P$1_P$61") (pintype "power_in"))
      (node (ref "P1") (pin "P$62") (pinfunction "P$1_P$62") (pintype "power_in"))
      (node (ref "P1") (pin "P$63") (pinfunction "P$1_P$63") (pintype "power_in"))
      (node (ref "P1") (pin "P$64") (pinfunction "P$1_P$64") (pintype "power_in"))
      (node (ref "P1") (pin "P$65") (pinfunction "P$1_P$65") (pintype "power_in"))
      (node (ref "P1") (pin "P$66") (pinfunction "P$1_P$66") (pintype "power_in"))
      (node (ref "P1") (pin "P$67") (pinfunction "P$1_P$67") (pintype "power_in"))
      (node (ref "P1") (pin "P$68") (pinfunction "P$1_P$68") (pintype "power_in"))
      (node (ref "P1") (pin "P$69") (pinfunction "P$1_P$69") (pintype "power_in"))
      (node (ref "P1") (pin "P$7") (pinfunction "P$1_P$7") (pintype "power_in"))
      (node (ref "P1") (pin "P$70") (pinfunction "P$1_P$70") (pintype "power_in"))
      (node (ref "P1") (pin "P$71") (pinfunction "P$1_P$71") (pintype "power_in"))
      (node (ref "P1") (pin "P$72") (pinfunction "P$1_P$72") (pintype "power_in"))
      (node (ref "P1") (pin "P$73") (pinfunction "P$1_P$73") (pintype "power_in"))
      (node (ref "P1") (pin "P$74") (pinfunction "P$1_P$74") (pintype "power_in"))
      (node (ref "P1") (pin "P$75") (pinfunction "P$1_P$75") (pintype "power_in"))
      (node (ref "P1") (pin "P$76") (pinfunction "P$1_P$76") (pintype "power_in"))
      (node (ref "P1") (pin "P$77") (pinfunction "P$1_P$77") (pintype "power_in"))
      (node (ref "P1") (pin "P$78") (pinfunction "P$1_P$78") (pintype "power_in"))
      (node (ref "P1") (pin "P$79") (pinfunction "P$1_P$79") (pintype "power_in"))
      (node (ref "P1") (pin "P$8") (pinfunction "P$1_P$8") (pintype "power_in"))
      (node (ref "P1") (pin "P$80") (pinfunction "P$1_P$80") (pintype "power_in"))
      (node (ref "P1") (pin "P$81") (pinfunction "P$1_P$81") (pintype "power_in"))
      (node (ref "P1") (pin "P$82") (pinfunction "P$1_P$82") (pintype "power_in"))
      (node (ref "P1") (pin "P$83") (pinfunction "P$1_P$83") (pintype "power_in"))
      (node (ref "P1") (pin "P$84") (pinfunction "P$1_P$84") (pintype "power_in"))
      (node (ref "P1") (pin "P$85") (pinfunction "P$1_P$85") (pintype "power_in"))
      (node (ref "P1") (pin "P$86") (pinfunction "P$1_P$86") (pintype "power_in"))
      (node (ref "P1") (pin "P$87") (pinfunction "P$1_P$87") (pintype "power_in"))
      (node (ref "P1") (pin "P$88") (pinfunction "P$1_P$88") (pintype "power_in"))
      (node (ref "P1") (pin "P$89") (pinfunction "P$1_P$89") (pintype "power_in"))
      (node (ref "P1") (pin "P$9") (pinfunction "P$1_P$9") (pintype "power_in"))
      (node (ref "P1") (pin "P$90") (pinfunction "P$1_P$90") (pintype "power_in"))
      (node (ref "P1") (pin "P$91") (pinfunction "P$1_P$91") (pintype "power_in"))
      (node (ref "P1") (pin "P$92") (pinfunction "P$1_P$92") (pintype "power_in"))
      (node (ref "P1") (pin "P$93") (pinfunction "P$1_P$93") (pintype "power_in"))
      (node (ref "P1") (pin "P$94") (pinfunction "P$1_P$94") (pintype "power_in"))
      (node (ref "P1") (pin "P$95") (pinfunction "P$1_P$95") (pintype "power_in"))
      (node (ref "P1") (pin "P$96") (pinfunction "P$1_P$96") (pintype "power_in"))
      (node (ref "P1") (pin "P$97") (pinfunction "P$1_P$97") (pintype "power_in"))
      (node (ref "P1") (pin "P$98") (pinfunction "P$1_P$98") (pintype "power_in"))
      (node (ref "P1") (pin "P$99") (pinfunction "P$1_P$99") (pintype "power_in"))
    )
    (net (code "3") (name "/P2") (class "Default")
      (node (ref "JP1") (pin "P$3") (pinfunction "2_P$3") (pintype "bidirectional"))
      (node (ref "P2") (pin "P$1") (pinfunction "P$1_P$1") (pintype "power_in"))
      (node (ref "P2") (pin "P$10") (pinfunction "P$1_P$10") (pintype "power_in"))
      (node (ref "P2") (pin "P$100") (pinfunction "P$1_P$100") (pintype "power_in"))
      (node (ref "P2") (pin "P$101") (pinfunction "P$1_P$101") (pintype "power_in"))
      (node (ref "P2") (pin "P$102") (pinfunction "P$1_P$102") (pintype "power_in"))
      (node (ref "P2") (pin "P$103") (pinfunction "P$1_P$103") (pintype "power_in"))
      (node (ref "P2") (pin "P$104") (pinfunction "P$1_P$104") (pintype "power_in"))
      (node (ref "P2") (pin "P$105") (pinfunction "P$1_P$105") (pintype "power_in"))
      (node (ref "P2") (pin "P$106") (pinfunction "P$1_P$106") (pintype "power_in"))
      (node (ref "P2") (pin "P$107") (pinfunction "P$1_P$107") (pintype "power_in"))
      (node (ref "P2") (pin "P$108") (pinfunction "P$1_P$108") (pintype "power_in"))
      (node (ref "P2") (pin "P$109") (pinfunction "P$1_P$109") (pintype "power_in"))
      (node (ref "P2") (pin "P$11") (pinfunction "P$1_P$11") (pintype "power_in"))
      (node (ref "P2") (pin "P$110") (pinfunction "P$1_P$110") (pintype "power_in"))
      (node (ref "P2") (pin "P$111") (pinfunction "P$1_P$111") (pintype "power_in"))
      (node (ref "P2") (pin "P$112") (pinfunction "P$1_P$112") (pintype "power_in"))
      (node (ref "P2") (pin "P$113") (pinfunction "P$1_P$113") (pintype "power_in"))
      (node (ref "P2") (pin "P$114") (pinfunction "P$1_P$114") (pintype "power_in"))
      (node (ref "P2") (pin "P$115") (pinfunction "P$1_P$115") (pintype "power_in"))
      (node (ref "P2") (pin "P$116") (pinfunction "P$1_P$116") (pintype "power_in"))
      (node (ref "P2") (pin "P$117") (pinfunction "P$1_P$117") (pintype "power_in"))
      (node (ref "P2") (pin "P$118") (pinfunction "P$1_P$118") (pintype "power_in"))
      (node (ref "P2") (pin "P$119") (pinfunction "P$1_P$119") (pintype "power_in"))
      (node (ref "P2") (pin "P$12") (pinfunction "P$1_P$12") (pintype "power_in"))
      (node (ref "P2") (pin "P$120") (pinfunction "P$1_P$120") (pintype "power_in"))
      (node (ref "P2") (pin "P$121") (pinfunction "P$1_P$121") (pintype "power_in"))
      (node (ref "P2") (pin "P$122") (pinfunction "P$1_P$122") (pintype "power_in"))
      (node (ref "P2") (pin "P$123") (pinfunction "P$1_P$123") (pintype "power_in"))
      (node (ref "P2") (pin "P$124") (pinfunction "P$1_P$124") (pintype "power_in"))
      (node (ref "P2") (pin "P$125") (pinfunction "P$1_P$125") (pintype "power_in"))
      (node (ref "P2") (pin "P$126") (pinfunction "P$1_P$126") (pintype "power_in"))
      (node (ref "P2") (pin "P$127") (pinfunction "P$1_P$127") (pintype "power_in"))
      (node (ref "P2") (pin "P$128") (pinfunction "P$1_P$128") (pintype "power_in"))
      (node (ref "P2") (pin "P$129") (pinfunction "P$1_P$129") (pintype "power_in"))
      (node (ref "P2") (pin "P$13") (pinfunction "P$1_P$13") (pintype "power_in"))
      (node (ref "P2") (pin "P$130") (pinfunction "P$1_P$130") (pintype "power_in"))
      (node (ref "P2") (pin "P$131") (pinfunction "P$1_P$131") (pintype "power_in"))
      (node (ref "P2") (pin "P$132") (pinfunction "P$1_P$132") (pintype "power_in"))
      (node (ref "P2") (pin "P$133") (pinfunction "P$1_P$133") (pintype "power_in"))
      (node (ref "P2") (pin "P$134") (pinfunction "P$1_P$134") (pintype "power_in"))
      (node (ref "P2") (pin "P$135") (pinfunction "P$1_P$135") (pintype "power_in"))
      (node (ref "P2") (pin "P$136") (pinfunction "P$1_P$136") (pintype "power_in"))
      (node (ref "P2") (pin "P$137") (pinfunction "P$1_P$137") (pintype "power_in"))
      (node (ref "P2") (pin "P$138") (pinfunction "P$1_P$138") (pintype "power_in"))
      (node (ref "P2") (pin "P$139") (pinfunction "P$1_P$139") (pintype "power_in"))
      (node (ref "P2") (pin "P$14") (pinfunction "P$1_P$14") (pintype "power_in"))
      (node (ref "P2") (pin "P$140") (pinfunction "P$1_P$140") (pintype "power_in"))
      (node (ref "P2") (pin "P$141") (pinfunction "P$1_P$141") (pintype "power_in"))
      (node (ref "P2") (pin "P$142") (pinfunction "P$1_P$142") (pintype "power_in"))
      (node (ref "P2") (pin "P$143") (pinfunction "P$1_P$143") (pintype "power_in"))
      (node (ref "P2") (pin "P$144") (pinfunction "P$1_P$144") (pintype "power_in"))
      (node (ref "P2") (pin "P$145") (pinfunction "P$1_P$145") (pintype "power_in"))
      (node (ref "P2") (pin "P$146") (pinfunction "P$1_P$146") (pintype "power_in"))
      (node (ref "P2") (pin "P$147") (pinfunction "P$1_P$147") (pintype "power_in"))
      (node (ref "P2") (pin "P$148") (pinfunction "P$1_P$148") (pintype "power_in"))
      (node (ref "P2") (pin "P$149") (pinfunction "P$1_P$149") (pintype "power_in"))
      (node (ref "P2") (pin "P$15") (pinfunction "P$1_P$15") (pintype "power_in"))
      (node (ref "P2") (pin "P$150") (pinfunction "P$1_P$150") (pintype "power_in"))
      (node (ref "P2") (pin "P$151") (pinfunction "P$1_P$151") (pintype "power_in"))
      (node (ref "P2") (pin "P$152") (pinfunction "P$1_P$152") (pintype "power_in"))
      (node (ref "P2") (pin "P$153") (pinfunction "P$1_P$153") (pintype "power_in"))
      (node (ref "P2") (pin "P$154") (pinfunction "P$1_P$154") (pintype "power_in"))
      (node (ref "P2") (pin "P$155") (pinfunction "P$1_P$155") (pintype "power_in"))
      (node (ref "P2") (pin "P$156") (pinfunction "P$1_P$156") (pintype "power_in"))
      (node (ref "P2") (pin "P$157") (pinfunction "P$1_P$157") (pintype "power_in"))
      (node (ref "P2") (pin "P$158") (pinfunction "P$1_P$158") (pintype "power_in"))
      (node (ref "P2") (pin "P$159") (pinfunction "P$1_P$159") (pintype "power_in"))
      (node (ref "P2") (pin "P$16") (pinfunction "P$1_P$16") (pintype "power_in"))
      (node (ref "P2") (pin "P$160") (pinfunction "P$1_P$160") (pintype "power_in"))
      (node (ref "P2") (pin "P$161") (pinfunction "P$1_P$161") (pintype "power_in"))
      (node (ref "P2") (pin "P$162") (pinfunction "P$1_P$162") (pintype "power_in"))
      (node (ref "P2") (pin "P$163") (pinfunction "P$1_P$163") (pintype "power_in"))
      (node (ref "P2") (pin "P$164") (pinfunction "P$1_P$164") (pintype "power_in"))
      (node (ref "P2") (pin "P$165") (pinfunction "P$1_P$165") (pintype "power_in"))
      (node (ref "P2") (pin "P$166") (pinfunction "P$1_P$166") (pintype "power_in"))
      (node (ref "P2") (pin "P$167") (pinfunction "P$1_P$167") (pintype "power_in"))
      (node (ref "P2") (pin "P$168") (pinfunction "P$1_P$168") (pintype "power_in"))
      (node (ref "P2") (pin "P$169") (pinfunction "P$1_P$169") (pintype "power_in"))
      (node (ref "P2") (pin "P$17") (pinfunction "P$1_P$17") (pintype "power_in"))
      (node (ref "P2") (pin "P$170") (pinfunction "P$1_P$170") (pintype "power_in"))
      (node (ref "P2") (pin "P$171") (pinfunction "P$1_P$171") (pintype "power_in"))
      (node (ref "P2") (pin "P$172") (pinfunction "P$1_P$172") (pintype "power_in"))
      (node (ref "P2") (pin "P$173") (pinfunction "P$1_P$173") (pintype "power_in"))
      (node (ref "P2") (pin "P$174") (pinfunction "P$1_P$174") (pintype "power_in"))
      (node (ref "P2") (pin "P$175") (pinfunction "P$1_P$175") (pintype "power_in"))
      (node (ref "P2") (pin "P$176") (pinfunction "P$1_P$176") (pintype "power_in"))
      (node (ref "P2") (pin "P$177") (pinfunction "P$1_P$177") (pintype "power_in"))
      (node (ref "P2") (pin "P$178") (pinfunction "P$1_P$178") (pintype "power_in"))
      (node (ref "P2") (pin "P$179") (pinfunction "P$1_P$179") (pintype "power_in"))
      (node (ref "P2") (pin "P$18") (pinfunction "P$1_P$18") (pintype "power_in"))
      (node (ref "P2") (pin "P$180") (pinfunction "P$1_P$180") (pintype "power_in"))
      (node (ref "P2") (pin "P$181") (pinfunction "P$1_P$181") (pintype "power_in"))
      (node (ref "P2") (pin "P$182") (pinfunction "P$1_P$182") (pintype "power_in"))
      (node (ref "P2") (pin "P$183") (pinfunction "P$1_P$183") (pintype "power_in"))
      (node (ref "P2") (pin "P$184") (pinfunction "P$1_P$184") (pintype "power_in"))
      (node (ref "P2") (pin "P$185") (pinfunction "P$1_P$185") (pintype "power_in"))
      (node (ref "P2") (pin "P$186") (pinfunction "P$1_P$186") (pintype "power_in"))
      (node (ref "P2") (pin "P$187") (pinfunction "P$1_P$187") (pintype "power_in"))
      (node (ref "P2") (pin "P$188") (pinfunction "P$1_P$188") (pintype "power_in"))
      (node (ref "P2") (pin "P$189") (pinfunction "P$1_P$189") (pintype "power_in"))
      (node (ref "P2") (pin "P$19") (pinfunction "P$1_P$19") (pintype "power_in"))
      (node (ref "P2") (pin "P$190") (pinfunction "P$1_P$190") (pintype "power_in"))
      (node (ref "P2") (pin "P$191") (pinfunction "P$1_P$191") (pintype "power_in"))
      (node (ref "P2") (pin "P$192") (pinfunction "P$1_P$192") (pintype "power_in"))
      (node (ref "P2") (pin "P$193") (pinfunction "P$1_P$193") (pintype "power_in"))
      (node (ref "P2") (pin "P$194") (pinfunction "P$1_P$194") (pintype "power_in"))
      (node (ref "P2") (pin "P$195") (pinfunction "P$1_P$195") (pintype "power_in"))
      (node (ref "P2") (pin "P$196") (pinfunction "P$1_P$196") (pintype "power_in"))
      (node (ref "P2") (pin "P$197") (pinfunction "P$1_P$197") (pintype "power_in"))
      (node (ref "P2") (pin "P$198") (pinfunction "P$1_P$198") (pintype "power_in"))
      (node (ref "P2") (pin "P$199") (pinfunction "P$1_P$199") (pintype "power_in"))
      (node (ref "P2") (pin "P$2") (pinfunction "P$1_P$2") (pintype "power_in"))
      (node (ref "P2") (pin "P$20") (pinfunction "P$1_P$20") (pintype "power_in"))
      (node (ref "P2") (pin "P$200") (pinfunction "P$1_P$200") (pintype "power_in"))
      (node (ref "P2") (pin "P$201") (pinfunction "P$1_P$201") (pintype "power_in"))
      (node (ref "P2") (pin "P$202") (pinfunction "P$1_P$202") (pintype "power_in"))
      (node (ref "P2") (pin "P$203") (pinfunction "P$1_P$203") (pintype "power_in"))
      (node (ref "P2") (pin "P$204") (pinfunction "P$1_P$204") (pintype "power_in"))
      (node (ref "P2") (pin "P$205") (pinfunction "P$1_P$205") (pintype "power_in"))
      (node (ref "P2") (pin "P$206") (pinfunction "P$1_P$206") (pintype "power_in"))
      (node (ref "P2") (pin "P$207") (pinfunction "P$1_P$207") (pintype "power_in"))
      (node (ref "P2") (pin "P$208") (pinfunction "P$1_P$208") (pintype "power_in"))
      (node (ref "P2") (pin "P$209") (pinfunction "P$1_P$209") (pintype "power_in"))
      (node (ref "P2") (pin "P$21") (pinfunction "P$1_P$21") (pintype "power_in"))
      (node (ref "P2") (pin "P$210") (pinfunction "P$1_P$210") (pintype "power_in"))
      (node (ref "P2") (pin "P$211") (pinfunction "P$1_P$211") (pintype "power_in"))
      (node (ref "P2") (pin "P$212") (pinfunction "P$1_P$212") (pintype "power_in"))
      (node (ref "P2") (pin "P$213") (pinfunction "P$1_P$213") (pintype "power_in"))
      (node (ref "P2") (pin "P$214") (pinfunction "P$1_P$214") (pintype "power_in"))
      (node (ref "P2") (pin "P$215") (pinfunction "P$1_P$215") (pintype "power_in"))
      (node (ref "P2") (pin "P$216") (pinfunction "P$1_P$216") (pintype "power_in"))
      (node (ref "P2") (pin "P$217") (pinfunction "P$1_P$217") (pintype "power_in"))
      (node (ref "P2") (pin "P$218") (pinfunction "P$1_P$218") (pintype "power_in"))
      (node (ref "P2") (pin "P$219") (pinfunction "P$1_P$219") (pintype "power_in"))
      (node (ref "P2") (pin "P$22") (pinfunction "P$1_P$22") (pintype "power_in"))
      (node (ref "P2") (pin "P$220") (pinfunction "P$1_P$220") (pintype "power_in"))
      (node (ref "P2") (pin "P$221") (pinfunction "P$1_P$221") (pintype "power_in"))
      (node (ref "P2") (pin "P$222") (pinfunction "P$1_P$222") (pintype "power_in"))
      (node (ref "P2") (pin "P$223") (pinfunction "P$1_P$223") (pintype "power_in"))
      (node (ref "P2") (pin "P$224") (pinfunction "P$1_P$224") (pintype "power_in"))
      (node (ref "P2") (pin "P$225") (pinfunction "P$1_P$225") (pintype "power_in"))
      (node (ref "P2") (pin "P$226") (pinfunction "P$1_P$226") (pintype "power_in"))
      (node (ref "P2") (pin "P$227") (pinfunction "P$1_P$227") (pintype "power_in"))
      (node (ref "P2") (pin "P$228") (pinfunction "P$1_P$228") (pintype "power_in"))
      (node (ref "P2") (pin "P$229") (pinfunction "P$1_P$229") (pintype "power_in"))
      (node (ref "P2") (pin "P$23") (pinfunction "P$1_P$23") (pintype "power_in"))
      (node (ref "P2") (pin "P$230") (pinfunction "P$1_P$230") (pintype "power_in"))
      (node (ref "P2") (pin "P$231") (pinfunction "P$1_P$231") (pintype "power_in"))
      (node (ref "P2") (pin "P$232") (pinfunction "P$1_P$232") (pintype "power_in"))
      (node (ref "P2") (pin "P$233") (pinfunction "P$1_P$233") (pintype "power_in"))
      (node (ref "P2") (pin "P$234") (pinfunction "P$1_P$234") (pintype "power_in"))
      (node (ref "P2") (pin "P$235") (pinfunction "P$1_P$235") (pintype "power_in"))
      (node (ref "P2") (pin "P$236") (pinfunction "P$1_P$236") (pintype "power_in"))
      (node (ref "P2") (pin "P$237") (pinfunction "P$1_P$237") (pintype "power_in"))
      (node (ref "P2") (pin "P$238") (pinfunction "P$1_P$238") (pintype "power_in"))
      (node (ref "P2") (pin "P$239") (pinfunction "P$1_P$239") (pintype "power_in"))
      (node (ref "P2") (pin "P$24") (pinfunction "P$1_P$24") (pintype "power_in"))
      (node (ref "P2") (pin "P$240") (pinfunction "P$1_P$240") (pintype "power_in"))
      (node (ref "P2") (pin "P$241") (pinfunction "P$1_P$241") (pintype "power_in"))
      (node (ref "P2") (pin "P$242") (pinfunction "P$1_P$242") (pintype "power_in"))
      (node (ref "P2") (pin "P$243") (pinfunction "P$1_P$243") (pintype "power_in"))
      (node (ref "P2") (pin "P$244") (pinfunction "P$1_P$244") (pintype "power_in"))
      (node (ref "P2") (pin "P$245") (pinfunction "P$1_P$245") (pintype "power_in"))
      (node (ref "P2") (pin "P$246") (pinfunction "P$1_P$246") (pintype "power_in"))
      (node (ref "P2") (pin "P$247") (pinfunction "P$1_P$247") (pintype "power_in"))
      (node (ref "P2") (pin "P$248") (pinfunction "P$1_P$248") (pintype "power_in"))
      (node (ref "P2") (pin "P$249") (pinfunction "P$1_P$249") (pintype "power_in"))
      (node (ref "P2") (pin "P$25") (pinfunction "P$1_P$25") (pintype "power_in"))
      (node (ref "P2") (pin "P$250") (pinfunction "P$1_P$250") (pintype "power_in"))
      (node (ref "P2") (pin "P$251") (pinfunction "P$1_P$251") (pintype "power_in"))
      (node (ref "P2") (pin "P$252") (pinfunction "P$1_P$252") (pintype "power_in"))
      (node (ref "P2") (pin "P$253") (pinfunction "P$1_P$253") (pintype "power_in"))
      (node (ref "P2") (pin "P$254") (pinfunction "P$1_P$254") (pintype "power_in"))
      (node (ref "P2") (pin "P$255") (pinfunction "P$1_P$255") (pintype "power_in"))
      (node (ref "P2") (pin "P$256") (pinfunction "P$1_P$256") (pintype "power_in"))
      (node (ref "P2") (pin "P$257") (pinfunction "P$1_P$257") (pintype "power_in"))
      (node (ref "P2") (pin "P$258") (pinfunction "P$1_P$258") (pintype "power_in"))
      (node (ref "P2") (pin "P$259") (pinfunction "P$1_P$259") (pintype "power_in"))
      (node (ref "P2") (pin "P$26") (pinfunction "P$1_P$26") (pintype "power_in"))
      (node (ref "P2") (pin "P$260") (pinfunction "P$1_P$260") (pintype "power_in"))
      (node (ref "P2") (pin "P$261") (pinfunction "P$1_P$261") (pintype "power_in"))
      (node (ref "P2") (pin "P$262") (pinfunction "P$1_P$262") (pintype "power_in"))
      (node (ref "P2") (pin "P$263") (pinfunction "P$1_P$263") (pintype "power_in"))
      (node (ref "P2") (pin "P$264") (pinfunction "P$1_P$264") (pintype "power_in"))
      (node (ref "P2") (pin "P$265") (pinfunction "P$1_P$265") (pintype "power_in"))
      (node (ref "P2") (pin "P$266") (pinfunction "P$1_P$266") (pintype "power_in"))
      (node (ref "P2") (pin "P$267") (pinfunction "P$1_P$267") (pintype "power_in"))
      (node (ref "P2") (pin "P$268") (pinfunction "P$1_P$268") (pintype "power_in"))
      (node (ref "P2") (pin "P$269") (pinfunction "P$1_P$269") (pintype "power_in"))
      (node (ref "P2") (pin "P$27") (pinfunction "P$1_P$27") (pintype "power_in"))
      (node (ref "P2") (pin "P$270") (pinfunction "P$1_P$270") (pintype "power_in"))
      (node (ref "P2") (pin "P$271") (pinfunction "P$1_P$271") (pintype "power_in"))
      (node (ref "P2") (pin "P$272") (pinfunction "P$1_P$272") (pintype "power_in"))
      (node (ref "P2") (pin "P$273") (pinfunction "P$1_P$273") (pintype "power_in"))
      (node (ref "P2") (pin "P$274") (pinfunction "P$1_P$274") (pintype "power_in"))
      (node (ref "P2") (pin "P$275") (pinfunction "P$1_P$275") (pintype "power_in"))
      (node (ref "P2") (pin "P$276") (pinfunction "P$1_P$276") (pintype "power_in"))
      (node (ref "P2") (pin "P$277") (pinfunction "P$1_P$277") (pintype "power_in"))
      (node (ref "P2") (pin "P$278") (pinfunction "P$1_P$278") (pintype "power_in"))
      (node (ref "P2") (pin "P$279") (pinfunction "P$1_P$279") (pintype "power_in"))
      (node (ref "P2") (pin "P$28") (pinfunction "P$1_P$28") (pintype "power_in"))
      (node (ref "P2") (pin "P$280") (pinfunction "P$1_P$280") (pintype "power_in"))
      (node (ref "P2") (pin "P$281") (pinfunction "P$1_P$281") (pintype "power_in"))
      (node (ref "P2") (pin "P$282") (pinfunction "P$1_P$282") (pintype "power_in"))
      (node (ref "P2") (pin "P$283") (pinfunction "P$1_P$283") (pintype "power_in"))
      (node (ref "P2") (pin "P$284") (pinfunction "P$1_P$284") (pintype "power_in"))
      (node (ref "P2") (pin "P$285") (pinfunction "P$1_P$285") (pintype "power_in"))
      (node (ref "P2") (pin "P$286") (pinfunction "P$1_P$286") (pintype "power_in"))
      (node (ref "P2") (pin "P$287") (pinfunction "P$1_P$287") (pintype "power_in"))
      (node (ref "P2") (pin "P$288") (pinfunction "P$1_P$288") (pintype "power_in"))
      (node (ref "P2") (pin "P$289") (pinfunction "P$1_P$289") (pintype "power_in"))
      (node (ref "P2") (pin "P$29") (pinfunction "P$1_P$29") (pintype "power_in"))
      (node (ref "P2") (pin "P$290") (pinfunction "P$1_P$290") (pintype "power_in"))
      (node (ref "P2") (pin "P$291") (pinfunction "P$1_P$291") (pintype "power_in"))
      (node (ref "P2") (pin "P$292") (pinfunction "P$1_P$292") (pintype "power_in"))
      (node (ref "P2") (pin "P$293") (pinfunction "P$1_P$293") (pintype "power_in"))
      (node (ref "P2") (pin "P$294") (pinfunction "P$1_P$294") (pintype "power_in"))
      (node (ref "P2") (pin "P$295") (pinfunction "P$1_P$295") (pintype "power_in"))
      (node (ref "P2") (pin "P$296") (pinfunction "P$1_P$296") (pintype "power_in"))
      (node (ref "P2") (pin "P$297") (pinfunction "P$1_P$297") (pintype "power_in"))
      (node (ref "P2") (pin "P$298") (pinfunction "P$1_P$298") (pintype "power_in"))
      (node (ref "P2") (pin "P$299") (pinfunction "P$1_P$299") (pintype "power_in"))
      (node (ref "P2") (pin "P$3") (pinfunction "P$1_P$3") (pintype "power_in"))
      (node (ref "P2") (pin "P$30") (pinfunction "P$1_P$30") (pintype "power_in"))
      (node (ref "P2") (pin "P$300") (pinfunction "P$1_P$300") (pintype "power_in"))
      (node (ref "P2") (pin "P$301") (pinfunction "P$1_P$301") (pintype "power_in"))
      (node (ref "P2") (pin "P$302") (pinfunction "P$1_P$302") (pintype "power_in"))
      (node (ref "P2") (pin "P$303") (pinfunction "P$1_P$303") (pintype "power_in"))
      (node (ref "P2") (pin "P$304") (pinfunction "P$1_P$304") (pintype "power_in"))
      (node (ref "P2") (pin "P$305") (pinfunction "P$1_P$305") (pintype "power_in"))
      (node (ref "P2") (pin "P$306") (pinfunction "P$1_P$306") (pintype "power_in"))
      (node (ref "P2") (pin "P$307") (pinfunction "P$1_P$307") (pintype "power_in"))
      (node (ref "P2") (pin "P$308") (pinfunction "P$1_P$308") (pintype "power_in"))
      (node (ref "P2") (pin "P$309") (pinfunction "P$1_P$309") (pintype "power_in"))
      (node (ref "P2") (pin "P$31") (pinfunction "P$1_P$31") (pintype "power_in"))
      (node (ref "P2") (pin "P$310") (pinfunction "P$1_P$310") (pintype "power_in"))
      (node (ref "P2") (pin "P$311") (pinfunction "P$1_P$311") (pintype "power_in"))
      (node (ref "P2") (pin "P$312") (pinfunction "P$1_P$312") (pintype "power_in"))
      (node (ref "P2") (pin "P$313") (pinfunction "P$1_P$313") (pintype "power_in"))
      (node (ref "P2") (pin "P$314") (pinfunction "P$1_P$314") (pintype "power_in"))
      (node (ref "P2") (pin "P$315") (pinfunction "P$1_P$315") (pintype "power_in"))
      (node (ref "P2") (pin "P$316") (pinfunction "P$1_P$316") (pintype "power_in"))
      (node (ref "P2") (pin "P$317") (pinfunction "P$1_P$317") (pintype "power_in"))
      (node (ref "P2") (pin "P$318") (pinfunction "P$1_P$318") (pintype "power_in"))
      (node (ref "P2") (pin "P$319") (pinfunction "P$1_P$319") (pintype "power_in"))
      (node (ref "P2") (pin "P$32") (pinfunction "P$1_P$32") (pintype "power_in"))
      (node (ref "P2") (pin "P$320") (pinfunction "P$1_P$320") (pintype "power_in"))
      (node (ref "P2") (pin "P$321") (pinfunction "P$1_P$321") (pintype "power_in"))
      (node (ref "P2") (pin "P$322") (pinfunction "P$1_P$322") (pintype "power_in"))
      (node (ref "P2") (pin "P$323") (pinfunction "P$1_P$323") (pintype "power_in"))
      (node (ref "P2") (pin "P$324") (pinfunction "P$1_P$324") (pintype "power_in"))
      (node (ref "P2") (pin "P$325") (pinfunction "P$1_P$325") (pintype "power_in"))
      (node (ref "P2") (pin "P$326") (pinfunction "P$1_P$326") (pintype "power_in"))
      (node (ref "P2") (pin "P$327") (pinfunction "P$1_P$327") (pintype "power_in"))
      (node (ref "P2") (pin "P$328") (pinfunction "P$1_P$328") (pintype "power_in"))
      (node (ref "P2") (pin "P$329") (pinfunction "P$1_P$329") (pintype "power_in"))
      (node (ref "P2") (pin "P$33") (pinfunction "P$1_P$33") (pintype "power_in"))
      (node (ref "P2") (pin "P$330") (pinfunction "P$1_P$330") (pintype "power_in"))
      (node (ref "P2") (pin "P$331") (pinfunction "P$1_P$331") (pintype "power_in"))
      (node (ref "P2") (pin "P$332") (pinfunction "P$1_P$332") (pintype "power_in"))
      (node (ref "P2") (pin "P$333") (pinfunction "P$1_P$333") (pintype "power_in"))
      (node (ref "P2") (pin "P$334") (pinfunction "P$1_P$334") (pintype "power_in"))
      (node (ref "P2") (pin "P$335") (pinfunction "P$1_P$335") (pintype "power_in"))
      (node (ref "P2") (pin "P$336") (pinfunction "P$1_P$336") (pintype "power_in"))
      (node (ref "P2") (pin "P$337") (pinfunction "P$1_P$337") (pintype "power_in"))
      (node (ref "P2") (pin "P$338") (pinfunction "P$1_P$338") (pintype "power_in"))
      (node (ref "P2") (pin "P$339") (pinfunction "P$1_P$339") (pintype "power_in"))
      (node (ref "P2") (pin "P$34") (pinfunction "P$1_P$34") (pintype "power_in"))
      (node (ref "P2") (pin "P$340") (pinfunction "P$1_P$340") (pintype "power_in"))
      (node (ref "P2") (pin "P$341") (pinfunction "P$1_P$341") (pintype "power_in"))
      (node (ref "P2") (pin "P$342") (pinfunction "P$1_P$342") (pintype "power_in"))
      (node (ref "P2") (pin "P$343") (pinfunction "P$1_P$343") (pintype "power_in"))
      (node (ref "P2") (pin "P$344") (pinfunction "P$1_P$344") (pintype "power_in"))
      (node (ref "P2") (pin "P$345") (pinfunction "P$1_P$345") (pintype "power_in"))
      (node (ref "P2") (pin "P$346") (pinfunction "P$1_P$346") (pintype "power_in"))
      (node (ref "P2") (pin "P$347") (pinfunction "P$1_P$347") (pintype "power_in"))
      (node (ref "P2") (pin "P$348") (pinfunction "P$1_P$348") (pintype "power_in"))
      (node (ref "P2") (pin "P$349") (pinfunction "P$1_P$349") (pintype "power_in"))
      (node (ref "P2") (pin "P$35") (pinfunction "P$1_P$35") (pintype "power_in"))
      (node (ref "P2") (pin "P$350") (pinfunction "P$1_P$350") (pintype "power_in"))
      (node (ref "P2") (pin "P$351") (pinfunction "P$1_P$351") (pintype "power_in"))
      (node (ref "P2") (pin "P$352") (pinfunction "P$1_P$352") (pintype "power_in"))
      (node (ref "P2") (pin "P$353") (pinfunction "P$1_P$353") (pintype "power_in"))
      (node (ref "P2") (pin "P$354") (pinfunction "P$1_P$354") (pintype "power_in"))
      (node (ref "P2") (pin "P$355") (pinfunction "P$1_P$355") (pintype "power_in"))
      (node (ref "P2") (pin "P$356") (pinfunction "P$1_P$356") (pintype "power_in"))
      (node (ref "P2") (pin "P$357") (pinfunction "P$1_P$357") (pintype "power_in"))
      (node (ref "P2") (pin "P$358") (pinfunction "P$1_P$358") (pintype "power_in"))
      (node (ref "P2") (pin "P$359") (pinfunction "P$1_P$359") (pintype "power_in"))
      (node (ref "P2") (pin "P$36") (pinfunction "P$1_P$36") (pintype "power_in"))
      (node (ref "P2") (pin "P$360") (pinfunction "P$1_P$360") (pintype "power_in"))
      (node (ref "P2") (pin "P$361") (pinfunction "P$1_P$361") (pintype "power_in"))
      (node (ref "P2") (pin "P$362") (pinfunction "P$1_P$362") (pintype "power_in"))
      (node (ref "P2") (pin "P$363") (pinfunction "P$1_P$363") (pintype "power_in"))
      (node (ref "P2") (pin "P$364") (pinfunction "P$1_P$364") (pintype "power_in"))
      (node (ref "P2") (pin "P$365") (pinfunction "P$1_P$365") (pintype "power_in"))
      (node (ref "P2") (pin "P$366") (pinfunction "P$1_P$366") (pintype "power_in"))
      (node (ref "P2") (pin "P$367") (pinfunction "P$1_P$367") (pintype "power_in"))
      (node (ref "P2") (pin "P$368") (pinfunction "P$1_P$368") (pintype "power_in"))
      (node (ref "P2") (pin "P$369") (pinfunction "P$1_P$369") (pintype "power_in"))
      (node (ref "P2") (pin "P$37") (pinfunction "P$1_P$37") (pintype "power_in"))
      (node (ref "P2") (pin "P$370") (pinfunction "P$1_P$370") (pintype "power_in"))
      (node (ref "P2") (pin "P$371") (pinfunction "P$1_P$371") (pintype "power_in"))
      (node (ref "P2") (pin "P$372") (pinfunction "P$1_P$372") (pintype "power_in"))
      (node (ref "P2") (pin "P$373") (pinfunction "P$1_P$373") (pintype "power_in"))
      (node (ref "P2") (pin "P$374") (pinfunction "P$1_P$374") (pintype "power_in"))
      (node (ref "P2") (pin "P$375") (pinfunction "P$1_P$375") (pintype "power_in"))
      (node (ref "P2") (pin "P$376") (pinfunction "P$1_P$376") (pintype "power_in"))
      (node (ref "P2") (pin "P$377") (pinfunction "P$1_P$377") (pintype "power_in"))
      (node (ref "P2") (pin "P$378") (pinfunction "P$1_P$378") (pintype "power_in"))
      (node (ref "P2") (pin "P$379") (pinfunction "P$1_P$379") (pintype "power_in"))
      (node (ref "P2") (pin "P$38") (pinfunction "P$1_P$38") (pintype "power_in"))
      (node (ref "P2") (pin "P$380") (pinfunction "P$1_P$380") (pintype "power_in"))
      (node (ref "P2") (pin "P$381") (pinfunction "P$1_P$381") (pintype "power_in"))
      (node (ref "P2") (pin "P$382") (pinfunction "P$1_P$382") (pintype "power_in"))
      (node (ref "P2") (pin "P$383") (pinfunction "P$1_P$383") (pintype "power_in"))
      (node (ref "P2") (pin "P$384") (pinfunction "P$1_P$384") (pintype "power_in"))
      (node (ref "P2") (pin "P$385") (pinfunction "P$1_P$385") (pintype "power_in"))
      (node (ref "P2") (pin "P$386") (pinfunction "P$1_P$386") (pintype "power_in"))
      (node (ref "P2") (pin "P$387") (pinfunction "P$1_P$387") (pintype "power_in"))
      (node (ref "P2") (pin "P$388") (pinfunction "P$1_P$388") (pintype "power_in"))
      (node (ref "P2") (pin "P$389") (pinfunction "P$1_P$389") (pintype "power_in"))
      (node (ref "P2") (pin "P$39") (pinfunction "P$1_P$39") (pintype "power_in"))
      (node (ref "P2") (pin "P$390") (pinfunction "P$1_P$390") (pintype "power_in"))
      (node (ref "P2") (pin "P$391") (pinfunction "P$1_P$391") (pintype "power_in"))
      (node (ref "P2") (pin "P$392") (pinfunction "P$1_P$392") (pintype "power_in"))
      (node (ref "P2") (pin "P$393") (pinfunction "P$1_P$393") (pintype "power_in"))
      (node (ref "P2") (pin "P$394") (pinfunction "P$1_P$394") (pintype "power_in"))
      (node (ref "P2") (pin "P$395") (pinfunction "P$1_P$395") (pintype "power_in"))
      (node (ref "P2") (pin "P$396") (pinfunction "P$1_P$396") (pintype "power_in"))
      (node (ref "P2") (pin "P$397") (pinfunction "P$1_P$397") (pintype "power_in"))
      (node (ref "P2") (pin "P$398") (pinfunction "P$1_P$398") (pintype "power_in"))
      (node (ref "P2") (pin "P$399") (pinfunction "P$1_P$399") (pintype "power_in"))
      (node (ref "P2") (pin "P$4") (pinfunction "P$1_P$4") (pintype "power_in"))
      (node (ref "P2") (pin "P$40") (pinfunction "P$1_P$40") (pintype "power_in"))
      (node (ref "P2") (pin "P$400") (pinfunction "P$1_P$400") (pintype "power_in"))
      (node (ref "P2") (pin "P$401") (pinfunction "P$1_P$401") (pintype "power_in"))
      (node (ref "P2") (pin "P$402") (pinfunction "P$1_P$402") (pintype "power_in"))
      (node (ref "P2") (pin "P$403") (pinfunction "P$1_P$403") (pintype "power_in"))
      (node (ref "P2") (pin "P$404") (pinfunction "P$1_P$404") (pintype "power_in"))
      (node (ref "P2") (pin "P$405") (pinfunction "P$1_P$405") (pintype "power_in"))
      (node (ref "P2") (pin "P$406") (pinfunction "P$1_P$406") (pintype "power_in"))
      (node (ref "P2") (pin "P$407") (pinfunction "P$1_P$407") (pintype "power_in"))
      (node (ref "P2") (pin "P$408") (pinfunction "P$1_P$408") (pintype "power_in"))
      (node (ref "P2") (pin "P$409") (pinfunction "P$1_P$409") (pintype "power_in"))
      (node (ref "P2") (pin "P$41") (pinfunction "P$1_P$41") (pintype "power_in"))
      (node (ref "P2") (pin "P$410") (pinfunction "P$1_P$410") (pintype "power_in"))
      (node (ref "P2") (pin "P$411") (pinfunction "P$1_P$411") (pintype "power_in"))
      (node (ref "P2") (pin "P$412") (pinfunction "P$1_P$412") (pintype "power_in"))
      (node (ref "P2") (pin "P$413") (pinfunction "P$1_P$413") (pintype "power_in"))
      (node (ref "P2") (pin "P$414") (pinfunction "P$1_P$414") (pintype "power_in"))
      (node (ref "P2") (pin "P$415") (pinfunction "P$1_P$415") (pintype "power_in"))
      (node (ref "P2") (pin "P$416") (pinfunction "P$1_P$416") (pintype "power_in"))
      (node (ref "P2") (pin "P$417") (pinfunction "P$1_P$417") (pintype "power_in"))
      (node (ref "P2") (pin "P$418") (pinfunction "P$1_P$418") (pintype "power_in"))
      (node (ref "P2") (pin "P$419") (pinfunction "P$1_P$419") (pintype "power_in"))
      (node (ref "P2") (pin "P$42") (pinfunction "P$1_P$42") (pintype "power_in"))
      (node (ref "P2") (pin "P$420") (pinfunction "P$1_P$420") (pintype "power_in"))
      (node (ref "P2") (pin "P$421") (pinfunction "P$1_P$421") (pintype "power_in"))
      (node (ref "P2") (pin "P$422") (pinfunction "P$1_P$422") (pintype "power_in"))
      (node (ref "P2") (pin "P$423") (pinfunction "P$1_P$423") (pintype "power_in"))
      (node (ref "P2") (pin "P$424") (pinfunction "P$1_P$424") (pintype "power_in"))
      (node (ref "P2") (pin "P$425") (pinfunction "P$1_P$425") (pintype "power_in"))
      (node (ref "P2") (pin "P$426") (pinfunction "P$1_P$426") (pintype "power_in"))
      (node (ref "P2") (pin "P$427") (pinfunction "P$1_P$427") (pintype "power_in"))
      (node (ref "P2") (pin "P$428") (pinfunction "P$1_P$428") (pintype "power_in"))
      (node (ref "P2") (pin "P$429") (pinfunction "P$1_P$429") (pintype "power_in"))
      (node (ref "P2") (pin "P$43") (pinfunction "P$1_P$43") (pintype "power_in"))
      (node (ref "P2") (pin "P$430") (pinfunction "P$1_P$430") (pintype "power_in"))
      (node (ref "P2") (pin "P$431") (pinfunction "P$1_P$431") (pintype "power_in"))
      (node (ref "P2") (pin "P$432") (pinfunction "P$1_P$432") (pintype "power_in"))
      (node (ref "P2") (pin "P$433") (pinfunction "P$1_P$433") (pintype "power_in"))
      (node (ref "P2") (pin "P$434") (pinfunction "P$1_P$434") (pintype "power_in"))
      (node (ref "P2") (pin "P$435") (pinfunction "P$1_P$435") (pintype "power_in"))
      (node (ref "P2") (pin "P$436") (pinfunction "P$1_P$436") (pintype "power_in"))
      (node (ref "P2") (pin "P$437") (pinfunction "P$1_P$437") (pintype "power_in"))
      (node (ref "P2") (pin "P$438") (pinfunction "P$1_P$438") (pintype "power_in"))
      (node (ref "P2") (pin "P$439") (pinfunction "P$1_P$439") (pintype "power_in"))
      (node (ref "P2") (pin "P$44") (pinfunction "P$1_P$44") (pintype "power_in"))
      (node (ref "P2") (pin "P$440") (pinfunction "P$1_P$440") (pintype "power_in"))
      (node (ref "P2") (pin "P$441") (pinfunction "P$1_P$441") (pintype "power_in"))
      (node (ref "P2") (pin "P$442") (pinfunction "P$1_P$442") (pintype "power_in"))
      (node (ref "P2") (pin "P$443") (pinfunction "P$1_P$443") (pintype "power_in"))
      (node (ref "P2") (pin "P$444") (pinfunction "P$1_P$444") (pintype "power_in"))
      (node (ref "P2") (pin "P$445") (pinfunction "P$1_P$445") (pintype "power_in"))
      (node (ref "P2") (pin "P$446") (pinfunction "P$1_P$446") (pintype "power_in"))
      (node (ref "P2") (pin "P$447") (pinfunction "P$1_P$447") (pintype "power_in"))
      (node (ref "P2") (pin "P$448") (pinfunction "P$1_P$448") (pintype "power_in"))
      (node (ref "P2") (pin "P$449") (pinfunction "P$1_P$449") (pintype "power_in"))
      (node (ref "P2") (pin "P$45") (pinfunction "P$1_P$45") (pintype "power_in"))
      (node (ref "P2") (pin "P$450") (pinfunction "P$1_P$450") (pintype "power_in"))
      (node (ref "P2") (pin "P$451") (pinfunction "P$1_P$451") (pintype "power_in"))
      (node (ref "P2") (pin "P$452") (pinfunction "P$1_P$452") (pintype "power_in"))
      (node (ref "P2") (pin "P$453") (pinfunction "P$1_P$453") (pintype "power_in"))
      (node (ref "P2") (pin "P$454") (pinfunction "P$1_P$454") (pintype "power_in"))
      (node (ref "P2") (pin "P$455") (pinfunction "P$1_P$455") (pintype "power_in"))
      (node (ref "P2") (pin "P$456") (pinfunction "P$1_P$456") (pintype "power_in"))
      (node (ref "P2") (pin "P$457") (pinfunction "P$1_P$457") (pintype "power_in"))
      (node (ref "P2") (pin "P$458") (pinfunction "P$1_P$458") (pintype "power_in"))
      (node (ref "P2") (pin "P$459") (pinfunction "P$1_P$459") (pintype "power_in"))
      (node (ref "P2") (pin "P$46") (pinfunction "P$1_P$46") (pintype "power_in"))
      (node (ref "P2") (pin "P$460") (pinfunction "P$1_P$460") (pintype "power_in"))
      (node (ref "P2") (pin "P$461") (pinfunction "P$1_P$461") (pintype "power_in"))
      (node (ref "P2") (pin "P$462") (pinfunction "P$1_P$462") (pintype "power_in"))
      (node (ref "P2") (pin "P$463") (pinfunction "P$1_P$463") (pintype "power_in"))
      (node (ref "P2") (pin "P$464") (pinfunction "P$1_P$464") (pintype "power_in"))
      (node (ref "P2") (pin "P$465") (pinfunction "P$1_P$465") (pintype "power_in"))
      (node (ref "P2") (pin "P$466") (pinfunction "P$1_P$466") (pintype "power_in"))
      (node (ref "P2") (pin "P$467") (pinfunction "P$1_P$467") (pintype "power_in"))
      (node (ref "P2") (pin "P$468") (pinfunction "P$1_P$468") (pintype "power_in"))
      (node (ref "P2") (pin "P$469") (pinfunction "P$1_P$469") (pintype "power_in"))
      (node (ref "P2") (pin "P$47") (pinfunction "P$1_P$47") (pintype "power_in"))
      (node (ref "P2") (pin "P$470") (pinfunction "P$1_P$470") (pintype "power_in"))
      (node (ref "P2") (pin "P$471") (pinfunction "P$1_P$471") (pintype "power_in"))
      (node (ref "P2") (pin "P$472") (pinfunction "P$1_P$472") (pintype "power_in"))
      (node (ref "P2") (pin "P$473") (pinfunction "P$1_P$473") (pintype "power_in"))
      (node (ref "P2") (pin "P$474") (pinfunction "P$1_P$474") (pintype "power_in"))
      (node (ref "P2") (pin "P$475") (pinfunction "P$1_P$475") (pintype "power_in"))
      (node (ref "P2") (pin "P$476") (pinfunction "P$1_P$476") (pintype "power_in"))
      (node (ref "P2") (pin "P$477") (pinfunction "P$1_P$477") (pintype "power_in"))
      (node (ref "P2") (pin "P$478") (pinfunction "P$1_P$478") (pintype "power_in"))
      (node (ref "P2") (pin "P$479") (pinfunction "P$1_P$479") (pintype "power_in"))
      (node (ref "P2") (pin "P$48") (pinfunction "P$1_P$48") (pintype "power_in"))
      (node (ref "P2") (pin "P$480") (pinfunction "P$1_P$480") (pintype "power_in"))
      (node (ref "P2") (pin "P$481") (pinfunction "P$1_P$481") (pintype "power_in"))
      (node (ref "P2") (pin "P$482") (pinfunction "P$1_P$482") (pintype "power_in"))
      (node (ref "P2") (pin "P$483") (pinfunction "P$1_P$483") (pintype "power_in"))
      (node (ref "P2") (pin "P$484") (pinfunction "P$1_P$484") (pintype "power_in"))
      (node (ref "P2") (pin "P$485") (pinfunction "P$1_P$485") (pintype "power_in"))
      (node (ref "P2") (pin "P$486") (pinfunction "P$1_P$486") (pintype "power_in"))
      (node (ref "P2") (pin "P$487") (pinfunction "P$1_P$487") (pintype "power_in"))
      (node (ref "P2") (pin "P$488") (pinfunction "P$1_P$488") (pintype "power_in"))
      (node (ref "P2") (pin "P$489") (pinfunction "P$1_P$489") (pintype "power_in"))
      (node (ref "P2") (pin "P$49") (pinfunction "P$1_P$49") (pintype "power_in"))
      (node (ref "P2") (pin "P$490") (pinfunction "P$1_P$490") (pintype "power_in"))
      (node (ref "P2") (pin "P$491") (pinfunction "P$1_P$491") (pintype "power_in"))
      (node (ref "P2") (pin "P$492") (pinfunction "P$1_P$492") (pintype "power_in"))
      (node (ref "P2") (pin "P$493") (pinfunction "P$1_P$493") (pintype "power_in"))
      (node (ref "P2") (pin "P$494") (pinfunction "P$1_P$494") (pintype "power_in"))
      (node (ref "P2") (pin "P$495") (pinfunction "P$1_P$495") (pintype "power_in"))
      (node (ref "P2") (pin "P$496") (pinfunction "P$1_P$496") (pintype "power_in"))
      (node (ref "P2") (pin "P$497") (pinfunction "P$1_P$497") (pintype "power_in"))
      (node (ref "P2") (pin "P$498") (pinfunction "P$1_P$498") (pintype "power_in"))
      (node (ref "P2") (pin "P$499") (pinfunction "P$1_P$499") (pintype "power_in"))
      (node (ref "P2") (pin "P$5") (pinfunction "P$1_P$5") (pintype "power_in"))
      (node (ref "P2") (pin "P$50") (pinfunction "P$1_P$50") (pintype "power_in"))
      (node (ref "P2") (pin "P$500") (pinfunction "P$1_P$500") (pintype "power_in"))
      (node (ref "P2") (pin "P$501") (pinfunction "P$1_P$501") (pintype "power_in"))
      (node (ref "P2") (pin "P$502") (pinfunction "P$1_P$502") (pintype "power_in"))
      (node (ref "P2") (pin "P$503") (pinfunction "P$1_P$503") (pintype "power_in"))
      (node (ref "P2") (pin "P$504") (pinfunction "P$1_P$504") (pintype "power_in"))
      (node (ref "P2") (pin "P$505") (pinfunction "P$1_P$505") (pintype "power_in"))
      (node (ref "P2") (pin "P$506") (pinfunction "P$1_P$506") (pintype "power_in"))
      (node (ref "P2") (pin "P$507") (pinfunction "P$1_P$507") (pintype "power_in"))
      (node (ref "P2") (pin "P$508") (pinfunction "P$1_P$508") (pintype "power_in"))
      (node (ref "P2") (pin "P$509") (pinfunction "P$1_P$509") (pintype "power_in"))
      (node (ref "P2") (pin "P$51") (pinfunction "P$1_P$51") (pintype "power_in"))
      (node (ref "P2") (pin "P$510") (pinfunction "P$1_P$510") (pintype "power_in"))
      (node (ref "P2") (pin "P$511") (pinfunction "P$1_P$511") (pintype "power_in"))
      (node (ref "P2") (pin "P$512") (pinfunction "P$1_P$512") (pintype "power_in"))
      (node (ref "P2") (pin "P$513") (pinfunction "P$1_P$513") (pintype "power_in"))
      (node (ref "P2") (pin "P$514") (pinfunction "P$1_P$514") (pintype "power_in"))
      (node (ref "P2") (pin "P$515") (pinfunction "P$1_P$515") (pintype "power_in"))
      (node (ref "P2") (pin "P$516") (pinfunction "P$1_P$516") (pintype "power_in"))
      (node (ref "P2") (pin "P$517") (pinfunction "P$1_P$517") (pintype "power_in"))
      (node (ref "P2") (pin "P$518") (pinfunction "P$1_P$518") (pintype "power_in"))
      (node (ref "P2") (pin "P$519") (pinfunction "P$1_P$519") (pintype "power_in"))
      (node (ref "P2") (pin "P$52") (pinfunction "P$1_P$52") (pintype "power_in"))
      (node (ref "P2") (pin "P$520") (pinfunction "P$1_P$520") (pintype "power_in"))
      (node (ref "P2") (pin "P$521") (pinfunction "P$1_P$521") (pintype "power_in"))
      (node (ref "P2") (pin "P$522") (pinfunction "P$1_P$522") (pintype "power_in"))
      (node (ref "P2") (pin "P$523") (pinfunction "P$1_P$523") (pintype "power_in"))
      (node (ref "P2") (pin "P$524") (pinfunction "P$1_P$524") (pintype "power_in"))
      (node (ref "P2") (pin "P$525") (pinfunction "P$1_P$525") (pintype "power_in"))
      (node (ref "P2") (pin "P$526") (pinfunction "P$1_P$526") (pintype "power_in"))
      (node (ref "P2") (pin "P$527") (pinfunction "P$1_P$527") (pintype "power_in"))
      (node (ref "P2") (pin "P$528") (pinfunction "P$1_P$528") (pintype "power_in"))
      (node (ref "P2") (pin "P$529") (pinfunction "P$1_P$529") (pintype "power_in"))
      (node (ref "P2") (pin "P$53") (pinfunction "P$1_P$53") (pintype "power_in"))
      (node (ref "P2") (pin "P$530") (pinfunction "P$1_P$530") (pintype "power_in"))
      (node (ref "P2") (pin "P$531") (pinfunction "P$1_P$531") (pintype "power_in"))
      (node (ref "P2") (pin "P$532") (pinfunction "P$1_P$532") (pintype "power_in"))
      (node (ref "P2") (pin "P$533") (pinfunction "P$1_P$533") (pintype "power_in"))
      (node (ref "P2") (pin "P$534") (pinfunction "P$1_P$534") (pintype "power_in"))
      (node (ref "P2") (pin "P$535") (pinfunction "P$1_P$535") (pintype "power_in"))
      (node (ref "P2") (pin "P$536") (pinfunction "P$1_P$536") (pintype "power_in"))
      (node (ref "P2") (pin "P$537") (pinfunction "P$1_P$537") (pintype "power_in"))
      (node (ref "P2") (pin "P$538") (pinfunction "P$1_P$538") (pintype "power_in"))
      (node (ref "P2") (pin "P$539") (pinfunction "P$1_P$539") (pintype "power_in"))
      (node (ref "P2") (pin "P$54") (pinfunction "P$1_P$54") (pintype "power_in"))
      (node (ref "P2") (pin "P$540") (pinfunction "P$1_P$540") (pintype "power_in"))
      (node (ref "P2") (pin "P$55") (pinfunction "P$1_P$55") (pintype "power_in"))
      (node (ref "P2") (pin "P$56") (pinfunction "P$1_P$56") (pintype "power_in"))
      (node (ref "P2") (pin "P$57") (pinfunction "P$1_P$57") (pintype "power_in"))
      (node (ref "P2") (pin "P$58") (pinfunction "P$1_P$58") (pintype "power_in"))
      (node (ref "P2") (pin "P$59") (pinfunction "P$1_P$59") (pintype "power_in"))
      (node (ref "P2") (pin "P$6") (pinfunction "P$1_P$6") (pintype "power_in"))
      (node (ref "P2") (pin "P$60") (pinfunction "P$1_P$60") (pintype "power_in"))
      (node (ref "P2") (pin "P$61") (pinfunction "P$1_P$61") (pintype "power_in"))
      (node (ref "P2") (pin "P$62") (pinfunction "P$1_P$62") (pintype "power_in"))
      (node (ref "P2") (pin "P$63") (pinfunction "P$1_P$63") (pintype "power_in"))
      (node (ref "P2") (pin "P$64") (pinfunction "P$1_P$64") (pintype "power_in"))
      (node (ref "P2") (pin "P$65") (pinfunction "P$1_P$65") (pintype "power_in"))
      (node (ref "P2") (pin "P$66") (pinfunction "P$1_P$66") (pintype "power_in"))
      (node (ref "P2") (pin "P$67") (pinfunction "P$1_P$67") (pintype "power_in"))
      (node (ref "P2") (pin "P$68") (pinfunction "P$1_P$68") (pintype "power_in"))
      (node (ref "P2") (pin "P$69") (pinfunction "P$1_P$69") (pintype "power_in"))
      (node (ref "P2") (pin "P$7") (pinfunction "P$1_P$7") (pintype "power_in"))
      (node (ref "P2") (pin "P$70") (pinfunction "P$1_P$70") (pintype "power_in"))
      (node (ref "P2") (pin "P$71") (pinfunction "P$1_P$71") (pintype "power_in"))
      (node (ref "P2") (pin "P$72") (pinfunction "P$1_P$72") (pintype "power_in"))
      (node (ref "P2") (pin "P$73") (pinfunction "P$1_P$73") (pintype "power_in"))
      (node (ref "P2") (pin "P$74") (pinfunction "P$1_P$74") (pintype "power_in"))
      (node (ref "P2") (pin "P$75") (pinfunction "P$1_P$75") (pintype "power_in"))
      (node (ref "P2") (pin "P$76") (pinfunction "P$1_P$76") (pintype "power_in"))
      (node (ref "P2") (pin "P$77") (pinfunction "P$1_P$77") (pintype "power_in"))
      (node (ref "P2") (pin "P$78") (pinfunction "P$1_P$78") (pintype "power_in"))
      (node (ref "P2") (pin "P$79") (pinfunction "P$1_P$79") (pintype "power_in"))
      (node (ref "P2") (pin "P$8") (pinfunction "P$1_P$8") (pintype "power_in"))
      (node (ref "P2") (pin "P$80") (pinfunction "P$1_P$80") (pintype "power_in"))
      (node (ref "P2") (pin "P$81") (pinfunction "P$1_P$81") (pintype "power_in"))
      (node (ref "P2") (pin "P$82") (pinfunction "P$1_P$82") (pintype "power_in"))
      (node (ref "P2") (pin "P$83") (pinfunction "P$1_P$83") (pintype "power_in"))
      (node (ref "P2") (pin "P$84") (pinfunction "P$1_P$84") (pintype "power_in"))
      (node (ref "P2") (pin "P$85") (pinfunction "P$1_P$85") (pintype "power_in"))
      (node (ref "P2") (pin "P$86") (pinfunction "P$1_P$86") (pintype "power_in"))
      (node (ref "P2") (pin "P$87") (pinfunction "P$1_P$87") (pintype "power_in"))
      (node (ref "P2") (pin "P$88") (pinfunction "P$1_P$88") (pintype "power_in"))
      (node (ref "P2") (pin "P$89") (pinfunction "P$1_P$89") (pintype "power_in"))
      (node (ref "P2") (pin "P$9") (pinfunction "P$1_P$9") (pintype "power_in"))
      (node (ref "P2") (pin "P$90") (pinfunction "P$1_P$90") (pintype "power_in"))
      (node (ref "P2") (pin "P$91") (pinfunction "P$1_P$91") (pintype "power_in"))
      (node (ref "P2") (pin "P$92") (pinfunction "P$1_P$92") (pintype "power_in"))
      (node (ref "P2") (pin "P$93") (pinfunction "P$1_P$93") (pintype "power_in"))
      (node (ref "P2") (pin "P$94") (pinfunction "P$1_P$94") (pintype "power_in"))
      (node (ref "P2") (pin "P$95") (pinfunction "P$1_P$95") (pintype "power_in"))
      (node (ref "P2") (pin "P$96") (pinfunction "P$1_P$96") (pintype "power_in"))
      (node (ref "P2") (pin "P$97") (pinfunction "P$1_P$97") (pintype "power_in"))
      (node (ref "P2") (pin "P$98") (pinfunction "P$1_P$98") (pintype "power_in"))
      (node (ref "P2") (pin "P$99") (pinfunction "P$1_P$99") (pintype "power_in"))
    )
    (net (code "4") (name "/P3") (class "Default")
      (node (ref "JP1") (pin "P$4") (pinfunction "3_P$4") (pintype "bidirectional"))
      (node (ref "P3") (pin "P$1") (pinfunction "P$1_P$1") (pintype "power_in"))
      (node (ref "P3") (pin "P$10") (pinfunction "P$1_P$10") (pintype "power_in"))
      (node (ref "P3") (pin "P$100") (pinfunction "P$1_P$100") (pintype "power_in"))
      (node (ref "P3") (pin "P$101") (pinfunction "P$1_P$101") (pintype "power_in"))
      (node (ref "P3") (pin "P$102") (pinfunction "P$1_P$102") (pintype "power_in"))
      (node (ref "P3") (pin "P$103") (pinfunction "P$1_P$103") (pintype "power_in"))
      (node (ref "P3") (pin "P$104") (pinfunction "P$1_P$104") (pintype "power_in"))
      (node (ref "P3") (pin "P$105") (pinfunction "P$1_P$105") (pintype "power_in"))
      (node (ref "P3") (pin "P$106") (pinfunction "P$1_P$106") (pintype "power_in"))
      (node (ref "P3") (pin "P$107") (pinfunction "P$1_P$107") (pintype "power_in"))
      (node (ref "P3") (pin "P$108") (pinfunction "P$1_P$108") (pintype "power_in"))
      (node (ref "P3") (pin "P$109") (pinfunction "P$1_P$109") (pintype "power_in"))
      (node (ref "P3") (pin "P$11") (pinfunction "P$1_P$11") (pintype "power_in"))
      (node (ref "P3") (pin "P$110") (pinfunction "P$1_P$110") (pintype "power_in"))
      (node (ref "P3") (pin "P$111") (pinfunction "P$1_P$111") (pintype "power_in"))
      (node (ref "P3") (pin "P$112") (pinfunction "P$1_P$112") (pintype "power_in"))
      (node (ref "P3") (pin "P$113") (pinfunction "P$1_P$113") (pintype "power_in"))
      (node (ref "P3") (pin "P$114") (pinfunction "P$1_P$114") (pintype "power_in"))
      (node (ref "P3") (pin "P$115") (pinfunction "P$1_P$115") (pintype "power_in"))
      (node (ref "P3") (pin "P$116") (pinfunction "P$1_P$116") (pintype "power_in"))
      (node (ref "P3") (pin "P$117") (pinfunction "P$1_P$117") (pintype "power_in"))
      (node (ref "P3") (pin "P$118") (pinfunction "P$1_P$118") (pintype "power_in"))
      (node (ref "P3") (pin "P$119") (pinfunction "P$1_P$119") (pintype "power_in"))
      (node (ref "P3") (pin "P$12") (pinfunction "P$1_P$12") (pintype "power_in"))
      (node (ref "P3") (pin "P$120") (pinfunction "P$1_P$120") (pintype "power_in"))
      (node (ref "P3") (pin "P$121") (pinfunction "P$1_P$121") (pintype "power_in"))
      (node (ref "P3") (pin "P$122") (pinfunction "P$1_P$122") (pintype "power_in"))
      (node (ref "P3") (pin "P$123") (pinfunction "P$1_P$123") (pintype "power_in"))
      (node (ref "P3") (pin "P$124") (pinfunction "P$1_P$124") (pintype "power_in"))
      (node (ref "P3") (pin "P$125") (pinfunction "P$1_P$125") (pintype "power_in"))
      (node (ref "P3") (pin "P$126") (pinfunction "P$1_P$126") (pintype "power_in"))
      (node (ref "P3") (pin "P$127") (pinfunction "P$1_P$127") (pintype "power_in"))
      (node (ref "P3") (pin "P$128") (pinfunction "P$1_P$128") (pintype "power_in"))
      (node (ref "P3") (pin "P$129") (pinfunction "P$1_P$129") (pintype "power_in"))
      (node (ref "P3") (pin "P$13") (pinfunction "P$1_P$13") (pintype "power_in"))
      (node (ref "P3") (pin "P$130") (pinfunction "P$1_P$130") (pintype "power_in"))
      (node (ref "P3") (pin "P$131") (pinfunction "P$1_P$131") (pintype "power_in"))
      (node (ref "P3") (pin "P$132") (pinfunction "P$1_P$132") (pintype "power_in"))
      (node (ref "P3") (pin "P$133") (pinfunction "P$1_P$133") (pintype "power_in"))
      (node (ref "P3") (pin "P$134") (pinfunction "P$1_P$134") (pintype "power_in"))
      (node (ref "P3") (pin "P$135") (pinfunction "P$1_P$135") (pintype "power_in"))
      (node (ref "P3") (pin "P$136") (pinfunction "P$1_P$136") (pintype "power_in"))
      (node (ref "P3") (pin "P$137") (pinfunction "P$1_P$137") (pintype "power_in"))
      (node (ref "P3") (pin "P$138") (pinfunction "P$1_P$138") (pintype "power_in"))
      (node (ref "P3") (pin "P$139") (pinfunction "P$1_P$139") (pintype "power_in"))
      (node (ref "P3") (pin "P$14") (pinfunction "P$1_P$14") (pintype "power_in"))
      (node (ref "P3") (pin "P$140") (pinfunction "P$1_P$140") (pintype "power_in"))
      (node (ref "P3") (pin "P$141") (pinfunction "P$1_P$141") (pintype "power_in"))
      (node (ref "P3") (pin "P$142") (pinfunction "P$1_P$142") (pintype "power_in"))
      (node (ref "P3") (pin "P$143") (pinfunction "P$1_P$143") (pintype "power_in"))
      (node (ref "P3") (pin "P$144") (pinfunction "P$1_P$144") (pintype "power_in"))
      (node (ref "P3") (pin "P$145") (pinfunction "P$1_P$145") (pintype "power_in"))
      (node (ref "P3") (pin "P$146") (pinfunction "P$1_P$146") (pintype "power_in"))
      (node (ref "P3") (pin "P$147") (pinfunction "P$1_P$147") (pintype "power_in"))
      (node (ref "P3") (pin "P$148") (pinfunction "P$1_P$148") (pintype "power_in"))
      (node (ref "P3") (pin "P$149") (pinfunction "P$1_P$149") (pintype "power_in"))
      (node (ref "P3") (pin "P$15") (pinfunction "P$1_P$15") (pintype "power_in"))
      (node (ref "P3") (pin "P$150") (pinfunction "P$1_P$150") (pintype "power_in"))
      (node (ref "P3") (pin "P$151") (pinfunction "P$1_P$151") (pintype "power_in"))
      (node (ref "P3") (pin "P$152") (pinfunction "P$1_P$152") (pintype "power_in"))
      (node (ref "P3") (pin "P$153") (pinfunction "P$1_P$153") (pintype "power_in"))
      (node (ref "P3") (pin "P$154") (pinfunction "P$1_P$154") (pintype "power_in"))
      (node (ref "P3") (pin "P$155") (pinfunction "P$1_P$155") (pintype "power_in"))
      (node (ref "P3") (pin "P$156") (pinfunction "P$1_P$156") (pintype "power_in"))
      (node (ref "P3") (pin "P$157") (pinfunction "P$1_P$157") (pintype "power_in"))
      (node (ref "P3") (pin "P$158") (pinfunction "P$1_P$158") (pintype "power_in"))
      (node (ref "P3") (pin "P$159") (pinfunction "P$1_P$159") (pintype "power_in"))
      (node (ref "P3") (pin "P$16") (pinfunction "P$1_P$16") (pintype "power_in"))
      (node (ref "P3") (pin "P$160") (pinfunction "P$1_P$160") (pintype "power_in"))
      (node (ref "P3") (pin "P$161") (pinfunction "P$1_P$161") (pintype "power_in"))
      (node (ref "P3") (pin "P$162") (pinfunction "P$1_P$162") (pintype "power_in"))
      (node (ref "P3") (pin "P$163") (pinfunction "P$1_P$163") (pintype "power_in"))
      (node (ref "P3") (pin "P$164") (pinfunction "P$1_P$164") (pintype "power_in"))
      (node (ref "P3") (pin "P$165") (pinfunction "P$1_P$165") (pintype "power_in"))
      (node (ref "P3") (pin "P$166") (pinfunction "P$1_P$166") (pintype "power_in"))
      (node (ref "P3") (pin "P$167") (pinfunction "P$1_P$167") (pintype "power_in"))
      (node (ref "P3") (pin "P$168") (pinfunction "P$1_P$168") (pintype "power_in"))
      (node (ref "P3") (pin "P$169") (pinfunction "P$1_P$169") (pintype "power_in"))
      (node (ref "P3") (pin "P$17") (pinfunction "P$1_P$17") (pintype "power_in"))
      (node (ref "P3") (pin "P$170") (pinfunction "P$1_P$170") (pintype "power_in"))
      (node (ref "P3") (pin "P$171") (pinfunction "P$1_P$171") (pintype "power_in"))
      (node (ref "P3") (pin "P$172") (pinfunction "P$1_P$172") (pintype "power_in"))
      (node (ref "P3") (pin "P$173") (pinfunction "P$1_P$173") (pintype "power_in"))
      (node (ref "P3") (pin "P$174") (pinfunction "P$1_P$174") (pintype "power_in"))
      (node (ref "P3") (pin "P$175") (pinfunction "P$1_P$175") (pintype "power_in"))
      (node (ref "P3") (pin "P$176") (pinfunction "P$1_P$176") (pintype "power_in"))
      (node (ref "P3") (pin "P$177") (pinfunction "P$1_P$177") (pintype "power_in"))
      (node (ref "P3") (pin "P$178") (pinfunction "P$1_P$178") (pintype "power_in"))
      (node (ref "P3") (pin "P$179") (pinfunction "P$1_P$179") (pintype "power_in"))
      (node (ref "P3") (pin "P$18") (pinfunction "P$1_P$18") (pintype "power_in"))
      (node (ref "P3") (pin "P$180") (pinfunction "P$1_P$180") (pintype "power_in"))
      (node (ref "P3") (pin "P$181") (pinfunction "P$1_P$181") (pintype "power_in"))
      (node (ref "P3") (pin "P$182") (pinfunction "P$1_P$182") (pintype "power_in"))
      (node (ref "P3") (pin "P$183") (pinfunction "P$1_P$183") (pintype "power_in"))
      (node (ref "P3") (pin "P$184") (pinfunction "P$1_P$184") (pintype "power_in"))
      (node (ref "P3") (pin "P$185") (pinfunction "P$1_P$185") (pintype "power_in"))
      (node (ref "P3") (pin "P$186") (pinfunction "P$1_P$186") (pintype "power_in"))
      (node (ref "P3") (pin "P$187") (pinfunction "P$1_P$187") (pintype "power_in"))
      (node (ref "P3") (pin "P$188") (pinfunction "P$1_P$188") (pintype "power_in"))
      (node (ref "P3") (pin "P$189") (pinfunction "P$1_P$189") (pintype "power_in"))
      (node (ref "P3") (pin "P$19") (pinfunction "P$1_P$19") (pintype "power_in"))
      (node (ref "P3") (pin "P$190") (pinfunction "P$1_P$190") (pintype "power_in"))
      (node (ref "P3") (pin "P$191") (pinfunction "P$1_P$191") (pintype "power_in"))
      (node (ref "P3") (pin "P$192") (pinfunction "P$1_P$192") (pintype "power_in"))
      (node (ref "P3") (pin "P$193") (pinfunction "P$1_P$193") (pintype "power_in"))
      (node (ref "P3") (pin "P$194") (pinfunction "P$1_P$194") (pintype "power_in"))
      (node (ref "P3") (pin "P$195") (pinfunction "P$1_P$195") (pintype "power_in"))
      (node (ref "P3") (pin "P$196") (pinfunction "P$1_P$196") (pintype "power_in"))
      (node (ref "P3") (pin "P$197") (pinfunction "P$1_P$197") (pintype "power_in"))
      (node (ref "P3") (pin "P$198") (pinfunction "P$1_P$198") (pintype "power_in"))
      (node (ref "P3") (pin "P$199") (pinfunction "P$1_P$199") (pintype "power_in"))
      (node (ref "P3") (pin "P$2") (pinfunction "P$1_P$2") (pintype "power_in"))
      (node (ref "P3") (pin "P$20") (pinfunction "P$1_P$20") (pintype "power_in"))
      (node (ref "P3") (pin "P$200") (pinfunction "P$1_P$200") (pintype "power_in"))
      (node (ref "P3") (pin "P$201") (pinfunction "P$1_P$201") (pintype "power_in"))
      (node (ref "P3") (pin "P$202") (pinfunction "P$1_P$202") (pintype "power_in"))
      (node (ref "P3") (pin "P$203") (pinfunction "P$1_P$203") (pintype "power_in"))
      (node (ref "P3") (pin "P$204") (pinfunction "P$1_P$204") (pintype "power_in"))
      (node (ref "P3") (pin "P$205") (pinfunction "P$1_P$205") (pintype "power_in"))
      (node (ref "P3") (pin "P$206") (pinfunction "P$1_P$206") (pintype "power_in"))
      (node (ref "P3") (pin "P$207") (pinfunction "P$1_P$207") (pintype "power_in"))
      (node (ref "P3") (pin "P$208") (pinfunction "P$1_P$208") (pintype "power_in"))
      (node (ref "P3") (pin "P$209") (pinfunction "P$1_P$209") (pintype "power_in"))
      (node (ref "P3") (pin "P$21") (pinfunction "P$1_P$21") (pintype "power_in"))
      (node (ref "P3") (pin "P$210") (pinfunction "P$1_P$210") (pintype "power_in"))
      (node (ref "P3") (pin "P$211") (pinfunction "P$1_P$211") (pintype "power_in"))
      (node (ref "P3") (pin "P$212") (pinfunction "P$1_P$212") (pintype "power_in"))
      (node (ref "P3") (pin "P$213") (pinfunction "P$1_P$213") (pintype "power_in"))
      (node (ref "P3") (pin "P$214") (pinfunction "P$1_P$214") (pintype "power_in"))
      (node (ref "P3") (pin "P$215") (pinfunction "P$1_P$215") (pintype "power_in"))
      (node (ref "P3") (pin "P$216") (pinfunction "P$1_P$216") (pintype "power_in"))
      (node (ref "P3") (pin "P$217") (pinfunction "P$1_P$217") (pintype "power_in"))
      (node (ref "P3") (pin "P$218") (pinfunction "P$1_P$218") (pintype "power_in"))
      (node (ref "P3") (pin "P$219") (pinfunction "P$1_P$219") (pintype "power_in"))
      (node (ref "P3") (pin "P$22") (pinfunction "P$1_P$22") (pintype "power_in"))
      (node (ref "P3") (pin "P$220") (pinfunction "P$1_P$220") (pintype "power_in"))
      (node (ref "P3") (pin "P$221") (pinfunction "P$1_P$221") (pintype "power_in"))
      (node (ref "P3") (pin "P$222") (pinfunction "P$1_P$222") (pintype "power_in"))
      (node (ref "P3") (pin "P$223") (pinfunction "P$1_P$223") (pintype "power_in"))
      (node (ref "P3") (pin "P$224") (pinfunction "P$1_P$224") (pintype "power_in"))
      (node (ref "P3") (pin "P$225") (pinfunction "P$1_P$225") (pintype "power_in"))
      (node (ref "P3") (pin "P$226") (pinfunction "P$1_P$226") (pintype "power_in"))
      (node (ref "P3") (pin "P$227") (pinfunction "P$1_P$227") (pintype "power_in"))
      (node (ref "P3") (pin "P$228") (pinfunction "P$1_P$228") (pintype "power_in"))
      (node (ref "P3") (pin "P$229") (pinfunction "P$1_P$229") (pintype "power_in"))
      (node (ref "P3") (pin "P$23") (pinfunction "P$1_P$23") (pintype "power_in"))
      (node (ref "P3") (pin "P$230") (pinfunction "P$1_P$230") (pintype "power_in"))
      (node (ref "P3") (pin "P$231") (pinfunction "P$1_P$231") (pintype "power_in"))
      (node (ref "P3") (pin "P$232") (pinfunction "P$1_P$232") (pintype "power_in"))
      (node (ref "P3") (pin "P$233") (pinfunction "P$1_P$233") (pintype "power_in"))
      (node (ref "P3") (pin "P$234") (pinfunction "P$1_P$234") (pintype "power_in"))
      (node (ref "P3") (pin "P$235") (pinfunction "P$1_P$235") (pintype "power_in"))
      (node (ref "P3") (pin "P$236") (pinfunction "P$1_P$236") (pintype "power_in"))
      (node (ref "P3") (pin "P$237") (pinfunction "P$1_P$237") (pintype "power_in"))
      (node (ref "P3") (pin "P$238") (pinfunction "P$1_P$238") (pintype "power_in"))
      (node (ref "P3") (pin "P$239") (pinfunction "P$1_P$239") (pintype "power_in"))
      (node (ref "P3") (pin "P$24") (pinfunction "P$1_P$24") (pintype "power_in"))
      (node (ref "P3") (pin "P$240") (pinfunction "P$1_P$240") (pintype "power_in"))
      (node (ref "P3") (pin "P$241") (pinfunction "P$1_P$241") (pintype "power_in"))
      (node (ref "P3") (pin "P$242") (pinfunction "P$1_P$242") (pintype "power_in"))
      (node (ref "P3") (pin "P$243") (pinfunction "P$1_P$243") (pintype "power_in"))
      (node (ref "P3") (pin "P$244") (pinfunction "P$1_P$244") (pintype "power_in"))
      (node (ref "P3") (pin "P$245") (pinfunction "P$1_P$245") (pintype "power_in"))
      (node (ref "P3") (pin "P$246") (pinfunction "P$1_P$246") (pintype "power_in"))
      (node (ref "P3") (pin "P$247") (pinfunction "P$1_P$247") (pintype "power_in"))
      (node (ref "P3") (pin "P$248") (pinfunction "P$1_P$248") (pintype "power_in"))
      (node (ref "P3") (pin "P$249") (pinfunction "P$1_P$249") (pintype "power_in"))
      (node (ref "P3") (pin "P$25") (pinfunction "P$1_P$25") (pintype "power_in"))
      (node (ref "P3") (pin "P$250") (pinfunction "P$1_P$250") (pintype "power_in"))
      (node (ref "P3") (pin "P$251") (pinfunction "P$1_P$251") (pintype "power_in"))
      (node (ref "P3") (pin "P$252") (pinfunction "P$1_P$252") (pintype "power_in"))
      (node (ref "P3") (pin "P$253") (pinfunction "P$1_P$253") (pintype "power_in"))
      (node (ref "P3") (pin "P$254") (pinfunction "P$1_P$254") (pintype "power_in"))
      (node (ref "P3") (pin "P$255") (pinfunction "P$1_P$255") (pintype "power_in"))
      (node (ref "P3") (pin "P$256") (pinfunction "P$1_P$256") (pintype "power_in"))
      (node (ref "P3") (pin "P$257") (pinfunction "P$1_P$257") (pintype "power_in"))
      (node (ref "P3") (pin "P$258") (pinfunction "P$1_P$258") (pintype "power_in"))
      (node (ref "P3") (pin "P$259") (pinfunction "P$1_P$259") (pintype "power_in"))
      (node (ref "P3") (pin "P$26") (pinfunction "P$1_P$26") (pintype "power_in"))
      (node (ref "P3") (pin "P$260") (pinfunction "P$1_P$260") (pintype "power_in"))
      (node (ref "P3") (pin "P$261") (pinfunction "P$1_P$261") (pintype "power_in"))
      (node (ref "P3") (pin "P$262") (pinfunction "P$1_P$262") (pintype "power_in"))
      (node (ref "P3") (pin "P$263") (pinfunction "P$1_P$263") (pintype "power_in"))
      (node (ref "P3") (pin "P$264") (pinfunction "P$1_P$264") (pintype "power_in"))
      (node (ref "P3") (pin "P$265") (pinfunction "P$1_P$265") (pintype "power_in"))
      (node (ref "P3") (pin "P$266") (pinfunction "P$1_P$266") (pintype "power_in"))
      (node (ref "P3") (pin "P$267") (pinfunction "P$1_P$267") (pintype "power_in"))
      (node (ref "P3") (pin "P$268") (pinfunction "P$1_P$268") (pintype "power_in"))
      (node (ref "P3") (pin "P$269") (pinfunction "P$1_P$269") (pintype "power_in"))
      (node (ref "P3") (pin "P$27") (pinfunction "P$1_P$27") (pintype "power_in"))
      (node (ref "P3") (pin "P$270") (pinfunction "P$1_P$270") (pintype "power_in"))
      (node (ref "P3") (pin "P$271") (pinfunction "P$1_P$271") (pintype "power_in"))
      (node (ref "P3") (pin "P$272") (pinfunction "P$1_P$272") (pintype "power_in"))
      (node (ref "P3") (pin "P$273") (pinfunction "P$1_P$273") (pintype "power_in"))
      (node (ref "P3") (pin "P$274") (pinfunction "P$1_P$274") (pintype "power_in"))
      (node (ref "P3") (pin "P$275") (pinfunction "P$1_P$275") (pintype "power_in"))
      (node (ref "P3") (pin "P$276") (pinfunction "P$1_P$276") (pintype "power_in"))
      (node (ref "P3") (pin "P$277") (pinfunction "P$1_P$277") (pintype "power_in"))
      (node (ref "P3") (pin "P$278") (pinfunction "P$1_P$278") (pintype "power_in"))
      (node (ref "P3") (pin "P$279") (pinfunction "P$1_P$279") (pintype "power_in"))
      (node (ref "P3") (pin "P$28") (pinfunction "P$1_P$28") (pintype "power_in"))
      (node (ref "P3") (pin "P$280") (pinfunction "P$1_P$280") (pintype "power_in"))
      (node (ref "P3") (pin "P$281") (pinfunction "P$1_P$281") (pintype "power_in"))
      (node (ref "P3") (pin "P$282") (pinfunction "P$1_P$282") (pintype "power_in"))
      (node (ref "P3") (pin "P$283") (pinfunction "P$1_P$283") (pintype "power_in"))
      (node (ref "P3") (pin "P$284") (pinfunction "P$1_P$284") (pintype "power_in"))
      (node (ref "P3") (pin "P$285") (pinfunction "P$1_P$285") (pintype "power_in"))
      (node (ref "P3") (pin "P$286") (pinfunction "P$1_P$286") (pintype "power_in"))
      (node (ref "P3") (pin "P$287") (pinfunction "P$1_P$287") (pintype "power_in"))
      (node (ref "P3") (pin "P$288") (pinfunction "P$1_P$288") (pintype "power_in"))
      (node (ref "P3") (pin "P$29") (pinfunction "P$1_P$29") (pintype "power_in"))
      (node (ref "P3") (pin "P$3") (pinfunction "P$1_P$3") (pintype "power_in"))
      (node (ref "P3") (pin "P$30") (pinfunction "P$1_P$30") (pintype "power_in"))
      (node (ref "P3") (pin "P$31") (pinfunction "P$1_P$31") (pintype "power_in"))
      (node (ref "P3") (pin "P$32") (pinfunction "P$1_P$32") (pintype "power_in"))
      (node (ref "P3") (pin "P$33") (pinfunction "P$1_P$33") (pintype "power_in"))
      (node (ref "P3") (pin "P$34") (pinfunction "P$1_P$34") (pintype "power_in"))
      (node (ref "P3") (pin "P$35") (pinfunction "P$1_P$35") (pintype "power_in"))
      (node (ref "P3") (pin "P$36") (pinfunction "P$1_P$36") (pintype "power_in"))
      (node (ref "P3") (pin "P$37") (pinfunction "P$1_P$37") (pintype "power_in"))
      (node (ref "P3") (pin "P$38") (pinfunction "P$1_P$38") (pintype "power_in"))
      (node (ref "P3") (pin "P$39") (pinfunction "P$1_P$39") (pintype "power_in"))
      (node (ref "P3") (pin "P$4") (pinfunction "P$1_P$4") (pintype "power_in"))
      (node (ref "P3") (pin "P$40") (pinfunction "P$1_P$40") (pintype "power_in"))
      (node (ref "P3") (pin "P$41") (pinfunction "P$1_P$41") (pintype "power_in"))
      (node (ref "P3") (pin "P$42") (pinfunction "P$1_P$42") (pintype "power_in"))
      (node (ref "P3") (pin "P$43") (pinfunction "P$1_P$43") (pintype "power_in"))
      (node (ref "P3") (pin "P$44") (pinfunction "P$1_P$44") (pintype "power_in"))
      (node (ref "P3") (pin "P$45") (pinfunction "P$1_P$45") (pintype "power_in"))
      (node (ref "P3") (pin "P$46") (pinfunction "P$1_P$46") (pintype "power_in"))
      (node (ref "P3") (pin "P$47") (pinfunction "P$1_P$47") (pintype "power_in"))
      (node (ref "P3") (pin "P$48") (pinfunction "P$1_P$48") (pintype "power_in"))
      (node (ref "P3") (pin "P$49") (pinfunction "P$1_P$49") (pintype "power_in"))
      (node (ref "P3") (pin "P$5") (pinfunction "P$1_P$5") (pintype "power_in"))
      (node (ref "P3") (pin "P$50") (pinfunction "P$1_P$50") (pintype "power_in"))
      (node (ref "P3") (pin "P$51") (pinfunction "P$1_P$51") (pintype "power_in"))
      (node (ref "P3") (pin "P$52") (pinfunction "P$1_P$52") (pintype "power_in"))
      (node (ref "P3") (pin "P$53") (pinfunction "P$1_P$53") (pintype "power_in"))
      (node (ref "P3") (pin "P$54") (pinfunction "P$1_P$54") (pintype "power_in"))
      (node (ref "P3") (pin "P$55") (pinfunction "P$1_P$55") (pintype "power_in"))
      (node (ref "P3") (pin "P$56") (pinfunction "P$1_P$56") (pintype "power_in"))
      (node (ref "P3") (pin "P$57") (pinfunction "P$1_P$57") (pintype "power_in"))
      (node (ref "P3") (pin "P$58") (pinfunction "P$1_P$58") (pintype "power_in"))
      (node (ref "P3") (pin "P$59") (pinfunction "P$1_P$59") (pintype "power_in"))
      (node (ref "P3") (pin "P$6") (pinfunction "P$1_P$6") (pintype "power_in"))
      (node (ref "P3") (pin "P$60") (pinfunction "P$1_P$60") (pintype "power_in"))
      (node (ref "P3") (pin "P$61") (pinfunction "P$1_P$61") (pintype "power_in"))
      (node (ref "P3") (pin "P$62") (pinfunction "P$1_P$62") (pintype "power_in"))
      (node (ref "P3") (pin "P$63") (pinfunction "P$1_P$63") (pintype "power_in"))
      (node (ref "P3") (pin "P$64") (pinfunction "P$1_P$64") (pintype "power_in"))
      (node (ref "P3") (pin "P$65") (pinfunction "P$1_P$65") (pintype "power_in"))
      (node (ref "P3") (pin "P$66") (pinfunction "P$1_P$66") (pintype "power_in"))
      (node (ref "P3") (pin "P$67") (pinfunction "P$1_P$67") (pintype "power_in"))
      (node (ref "P3") (pin "P$68") (pinfunction "P$1_P$68") (pintype "power_in"))
      (node (ref "P3") (pin "P$69") (pinfunction "P$1_P$69") (pintype "power_in"))
      (node (ref "P3") (pin "P$7") (pinfunction "P$1_P$7") (pintype "power_in"))
      (node (ref "P3") (pin "P$70") (pinfunction "P$1_P$70") (pintype "power_in"))
      (node (ref "P3") (pin "P$71") (pinfunction "P$1_P$71") (pintype "power_in"))
      (node (ref "P3") (pin "P$72") (pinfunction "P$1_P$72") (pintype "power_in"))
      (node (ref "P3") (pin "P$73") (pinfunction "P$1_P$73") (pintype "power_in"))
      (node (ref "P3") (pin "P$74") (pinfunction "P$1_P$74") (pintype "power_in"))
      (node (ref "P3") (pin "P$75") (pinfunction "P$1_P$75") (pintype "power_in"))
      (node (ref "P3") (pin "P$76") (pinfunction "P$1_P$76") (pintype "power_in"))
      (node (ref "P3") (pin "P$77") (pinfunction "P$1_P$77") (pintype "power_in"))
      (node (ref "P3") (pin "P$78") (pinfunction "P$1_P$78") (pintype "power_in"))
      (node (ref "P3") (pin "P$79") (pinfunction "P$1_P$79") (pintype "power_in"))
      (node (ref "P3") (pin "P$8") (pinfunction "P$1_P$8") (pintype "power_in"))
      (node (ref "P3") (pin "P$80") (pinfunction "P$1_P$80") (pintype "power_in"))
      (node (ref "P3") (pin "P$81") (pinfunction "P$1_P$81") (pintype "power_in"))
      (node (ref "P3") (pin "P$82") (pinfunction "P$1_P$82") (pintype "power_in"))
      (node (ref "P3") (pin "P$83") (pinfunction "P$1_P$83") (pintype "power_in"))
      (node (ref "P3") (pin "P$84") (pinfunction "P$1_P$84") (pintype "power_in"))
      (node (ref "P3") (pin "P$85") (pinfunction "P$1_P$85") (pintype "power_in"))
      (node (ref "P3") (pin "P$86") (pinfunction "P$1_P$86") (pintype "power_in"))
      (node (ref "P3") (pin "P$87") (pinfunction "P$1_P$87") (pintype "power_in"))
      (node (ref "P3") (pin "P$88") (pinfunction "P$1_P$88") (pintype "power_in"))
      (node (ref "P3") (pin "P$89") (pinfunction "P$1_P$89") (pintype "power_in"))
      (node (ref "P3") (pin "P$9") (pinfunction "P$1_P$9") (pintype "power_in"))
      (node (ref "P3") (pin "P$90") (pinfunction "P$1_P$90") (pintype "power_in"))
      (node (ref "P3") (pin "P$91") (pinfunction "P$1_P$91") (pintype "power_in"))
      (node (ref "P3") (pin "P$92") (pinfunction "P$1_P$92") (pintype "power_in"))
      (node (ref "P3") (pin "P$93") (pinfunction "P$1_P$93") (pintype "power_in"))
      (node (ref "P3") (pin "P$94") (pinfunction "P$1_P$94") (pintype "power_in"))
      (node (ref "P3") (pin "P$95") (pinfunction "P$1_P$95") (pintype "power_in"))
      (node (ref "P3") (pin "P$96") (pinfunction "P$1_P$96") (pintype "power_in"))
      (node (ref "P3") (pin "P$97") (pinfunction "P$1_P$97") (pintype "power_in"))
      (node (ref "P3") (pin "P$98") (pinfunction "P$1_P$98") (pintype "power_in"))
      (node (ref "P3") (pin "P$99") (pinfunction "P$1_P$99") (pintype "power_in"))
    )
    (net (code "5") (name "/P4") (class "Default")
      (node (ref "JP1") (pin "P$5") (pinfunction "4_P$5") (pintype "bidirectional"))
      (node (ref "P4") (pin "P$1") (pinfunction "P$1_P$1") (pintype "power_in"))
      (node (ref "P4") (pin "P$10") (pinfunction "P$1_P$10") (pintype "power_in"))
      (node (ref "P4") (pin "P$100") (pinfunction "P$1_P$100") (pintype "power_in"))
      (node (ref "P4") (pin "P$101") (pinfunction "P$1_P$101") (pintype "power_in"))
      (node (ref "P4") (pin "P$102") (pinfunction "P$1_P$102") (pintype "power_in"))
      (node (ref "P4") (pin "P$103") (pinfunction "P$1_P$103") (pintype "power_in"))
      (node (ref "P4") (pin "P$104") (pinfunction "P$1_P$104") (pintype "power_in"))
      (node (ref "P4") (pin "P$105") (pinfunction "P$1_P$105") (pintype "power_in"))
      (node (ref "P4") (pin "P$106") (pinfunction "P$1_P$106") (pintype "power_in"))
      (node (ref "P4") (pin "P$107") (pinfunction "P$1_P$107") (pintype "power_in"))
      (node (ref "P4") (pin "P$108") (pinfunction "P$1_P$108") (pintype "power_in"))
      (node (ref "P4") (pin "P$109") (pinfunction "P$1_P$109") (pintype "power_in"))
      (node (ref "P4") (pin "P$11") (pinfunction "P$1_P$11") (pintype "power_in"))
      (node (ref "P4") (pin "P$110") (pinfunction "P$1_P$110") (pintype "power_in"))
      (node (ref "P4") (pin "P$111") (pinfunction "P$1_P$111") (pintype "power_in"))
      (node (ref "P4") (pin "P$112") (pinfunction "P$1_P$112") (pintype "power_in"))
      (node (ref "P4") (pin "P$113") (pinfunction "P$1_P$113") (pintype "power_in"))
      (node (ref "P4") (pin "P$114") (pinfunction "P$1_P$114") (pintype "power_in"))
      (node (ref "P4") (pin "P$115") (pinfunction "P$1_P$115") (pintype "power_in"))
      (node (ref "P4") (pin "P$116") (pinfunction "P$1_P$116") (pintype "power_in"))
      (node (ref "P4") (pin "P$117") (pinfunction "P$1_P$117") (pintype "power_in"))
      (node (ref "P4") (pin "P$118") (pinfunction "P$1_P$118") (pintype "power_in"))
      (node (ref "P4") (pin "P$119") (pinfunction "P$1_P$119") (pintype "power_in"))
      (node (ref "P4") (pin "P$12") (pinfunction "P$1_P$12") (pintype "power_in"))
      (node (ref "P4") (pin "P$120") (pinfunction "P$1_P$120") (pintype "power_in"))
      (node (ref "P4") (pin "P$121") (pinfunction "P$1_P$121") (pintype "power_in"))
      (node (ref "P4") (pin "P$122") (pinfunction "P$1_P$122") (pintype "power_in"))
      (node (ref "P4") (pin "P$123") (pinfunction "P$1_P$123") (pintype "power_in"))
      (node (ref "P4") (pin "P$124") (pinfunction "P$1_P$124") (pintype "power_in"))
      (node (ref "P4") (pin "P$125") (pinfunction "P$1_P$125") (pintype "power_in"))
      (node (ref "P4") (pin "P$126") (pinfunction "P$1_P$126") (pintype "power_in"))
      (node (ref "P4") (pin "P$127") (pinfunction "P$1_P$127") (pintype "power_in"))
      (node (ref "P4") (pin "P$128") (pinfunction "P$1_P$128") (pintype "power_in"))
      (node (ref "P4") (pin "P$129") (pinfunction "P$1_P$129") (pintype "power_in"))
      (node (ref "P4") (pin "P$13") (pinfunction "P$1_P$13") (pintype "power_in"))
      (node (ref "P4") (pin "P$130") (pinfunction "P$1_P$130") (pintype "power_in"))
      (node (ref "P4") (pin "P$131") (pinfunction "P$1_P$131") (pintype "power_in"))
      (node (ref "P4") (pin "P$132") (pinfunction "P$1_P$132") (pintype "power_in"))
      (node (ref "P4") (pin "P$133") (pinfunction "P$1_P$133") (pintype "power_in"))
      (node (ref "P4") (pin "P$134") (pinfunction "P$1_P$134") (pintype "power_in"))
      (node (ref "P4") (pin "P$135") (pinfunction "P$1_P$135") (pintype "power_in"))
      (node (ref "P4") (pin "P$136") (pinfunction "P$1_P$136") (pintype "power_in"))
      (node (ref "P4") (pin "P$137") (pinfunction "P$1_P$137") (pintype "power_in"))
      (node (ref "P4") (pin "P$138") (pinfunction "P$1_P$138") (pintype "power_in"))
      (node (ref "P4") (pin "P$139") (pinfunction "P$1_P$139") (pintype "power_in"))
      (node (ref "P4") (pin "P$14") (pinfunction "P$1_P$14") (pintype "power_in"))
      (node (ref "P4") (pin "P$140") (pinfunction "P$1_P$140") (pintype "power_in"))
      (node (ref "P4") (pin "P$141") (pinfunction "P$1_P$141") (pintype "power_in"))
      (node (ref "P4") (pin "P$142") (pinfunction "P$1_P$142") (pintype "power_in"))
      (node (ref "P4") (pin "P$143") (pinfunction "P$1_P$143") (pintype "power_in"))
      (node (ref "P4") (pin "P$144") (pinfunction "P$1_P$144") (pintype "power_in"))
      (node (ref "P4") (pin "P$145") (pinfunction "P$1_P$145") (pintype "power_in"))
      (node (ref "P4") (pin "P$146") (pinfunction "P$1_P$146") (pintype "power_in"))
      (node (ref "P4") (pin "P$147") (pinfunction "P$1_P$147") (pintype "power_in"))
      (node (ref "P4") (pin "P$148") (pinfunction "P$1_P$148") (pintype "power_in"))
      (node (ref "P4") (pin "P$149") (pinfunction "P$1_P$149") (pintype "power_in"))
      (node (ref "P4") (pin "P$15") (pinfunction "P$1_P$15") (pintype "power_in"))
      (node (ref "P4") (pin "P$150") (pinfunction "P$1_P$150") (pintype "power_in"))
      (node (ref "P4") (pin "P$151") (pinfunction "P$1_P$151") (pintype "power_in"))
      (node (ref "P4") (pin "P$152") (pinfunction "P$1_P$152") (pintype "power_in"))
      (node (ref "P4") (pin "P$153") (pinfunction "P$1_P$153") (pintype "power_in"))
      (node (ref "P4") (pin "P$154") (pinfunction "P$1_P$154") (pintype "power_in"))
      (node (ref "P4") (pin "P$155") (pinfunction "P$1_P$155") (pintype "power_in"))
      (node (ref "P4") (pin "P$156") (pinfunction "P$1_P$156") (pintype "power_in"))
      (node (ref "P4") (pin "P$157") (pinfunction "P$1_P$157") (pintype "power_in"))
      (node (ref "P4") (pin "P$158") (pinfunction "P$1_P$158") (pintype "power_in"))
      (node (ref "P4") (pin "P$159") (pinfunction "P$1_P$159") (pintype "power_in"))
      (node (ref "P4") (pin "P$16") (pinfunction "P$1_P$16") (pintype "power_in"))
      (node (ref "P4") (pin "P$160") (pinfunction "P$1_P$160") (pintype "power_in"))
      (node (ref "P4") (pin "P$161") (pinfunction "P$1_P$161") (pintype "power_in"))
      (node (ref "P4") (pin "P$162") (pinfunction "P$1_P$162") (pintype "power_in"))
      (node (ref "P4") (pin "P$163") (pinfunction "P$1_P$163") (pintype "power_in"))
      (node (ref "P4") (pin "P$164") (pinfunction "P$1_P$164") (pintype "power_in"))
      (node (ref "P4") (pin "P$165") (pinfunction "P$1_P$165") (pintype "power_in"))
      (node (ref "P4") (pin "P$166") (pinfunction "P$1_P$166") (pintype "power_in"))
      (node (ref "P4") (pin "P$167") (pinfunction "P$1_P$167") (pintype "power_in"))
      (node (ref "P4") (pin "P$168") (pinfunction "P$1_P$168") (pintype "power_in"))
      (node (ref "P4") (pin "P$169") (pinfunction "P$1_P$169") (pintype "power_in"))
      (node (ref "P4") (pin "P$17") (pinfunction "P$1_P$17") (pintype "power_in"))
      (node (ref "P4") (pin "P$170") (pinfunction "P$1_P$170") (pintype "power_in"))
      (node (ref "P4") (pin "P$171") (pinfunction "P$1_P$171") (pintype "power_in"))
      (node (ref "P4") (pin "P$172") (pinfunction "P$1_P$172") (pintype "power_in"))
      (node (ref "P4") (pin "P$173") (pinfunction "P$1_P$173") (pintype "power_in"))
      (node (ref "P4") (pin "P$174") (pinfunction "P$1_P$174") (pintype "power_in"))
      (node (ref "P4") (pin "P$175") (pinfunction "P$1_P$175") (pintype "power_in"))
      (node (ref "P4") (pin "P$176") (pinfunction "P$1_P$176") (pintype "power_in"))
      (node (ref "P4") (pin "P$177") (pinfunction "P$1_P$177") (pintype "power_in"))
      (node (ref "P4") (pin "P$178") (pinfunction "P$1_P$178") (pintype "power_in"))
      (node (ref "P4") (pin "P$179") (pinfunction "P$1_P$179") (pintype "power_in"))
      (node (ref "P4") (pin "P$18") (pinfunction "P$1_P$18") (pintype "power_in"))
      (node (ref "P4") (pin "P$180") (pinfunction "P$1_P$180") (pintype "power_in"))
      (node (ref "P4") (pin "P$181") (pinfunction "P$1_P$181") (pintype "power_in"))
      (node (ref "P4") (pin "P$182") (pinfunction "P$1_P$182") (pintype "power_in"))
      (node (ref "P4") (pin "P$183") (pinfunction "P$1_P$183") (pintype "power_in"))
      (node (ref "P4") (pin "P$184") (pinfunction "P$1_P$184") (pintype "power_in"))
      (node (ref "P4") (pin "P$185") (pinfunction "P$1_P$185") (pintype "power_in"))
      (node (ref "P4") (pin "P$186") (pinfunction "P$1_P$186") (pintype "power_in"))
      (node (ref "P4") (pin "P$187") (pinfunction "P$1_P$187") (pintype "power_in"))
      (node (ref "P4") (pin "P$188") (pinfunction "P$1_P$188") (pintype "power_in"))
      (node (ref "P4") (pin "P$189") (pinfunction "P$1_P$189") (pintype "power_in"))
      (node (ref "P4") (pin "P$19") (pinfunction "P$1_P$19") (pintype "power_in"))
      (node (ref "P4") (pin "P$190") (pinfunction "P$1_P$190") (pintype "power_in"))
      (node (ref "P4") (pin "P$191") (pinfunction "P$1_P$191") (pintype "power_in"))
      (node (ref "P4") (pin "P$192") (pinfunction "P$1_P$192") (pintype "power_in"))
      (node (ref "P4") (pin "P$193") (pinfunction "P$1_P$193") (pintype "power_in"))
      (node (ref "P4") (pin "P$194") (pinfunction "P$1_P$194") (pintype "power_in"))
      (node (ref "P4") (pin "P$195") (pinfunction "P$1_P$195") (pintype "power_in"))
      (node (ref "P4") (pin "P$196") (pinfunction "P$1_P$196") (pintype "power_in"))
      (node (ref "P4") (pin "P$197") (pinfunction "P$1_P$197") (pintype "power_in"))
      (node (ref "P4") (pin "P$198") (pinfunction "P$1_P$198") (pintype "power_in"))
      (node (ref "P4") (pin "P$199") (pinfunction "P$1_P$199") (pintype "power_in"))
      (node (ref "P4") (pin "P$2") (pinfunction "P$1_P$2") (pintype "power_in"))
      (node (ref "P4") (pin "P$20") (pinfunction "P$1_P$20") (pintype "power_in"))
      (node (ref "P4") (pin "P$200") (pinfunction "P$1_P$200") (pintype "power_in"))
      (node (ref "P4") (pin "P$201") (pinfunction "P$1_P$201") (pintype "power_in"))
      (node (ref "P4") (pin "P$202") (pinfunction "P$1_P$202") (pintype "power_in"))
      (node (ref "P4") (pin "P$203") (pinfunction "P$1_P$203") (pintype "power_in"))
      (node (ref "P4") (pin "P$204") (pinfunction "P$1_P$204") (pintype "power_in"))
      (node (ref "P4") (pin "P$205") (pinfunction "P$1_P$205") (pintype "power_in"))
      (node (ref "P4") (pin "P$206") (pinfunction "P$1_P$206") (pintype "power_in"))
      (node (ref "P4") (pin "P$207") (pinfunction "P$1_P$207") (pintype "power_in"))
      (node (ref "P4") (pin "P$208") (pinfunction "P$1_P$208") (pintype "power_in"))
      (node (ref "P4") (pin "P$209") (pinfunction "P$1_P$209") (pintype "power_in"))
      (node (ref "P4") (pin "P$21") (pinfunction "P$1_P$21") (pintype "power_in"))
      (node (ref "P4") (pin "P$210") (pinfunction "P$1_P$210") (pintype "power_in"))
      (node (ref "P4") (pin "P$211") (pinfunction "P$1_P$211") (pintype "power_in"))
      (node (ref "P4") (pin "P$212") (pinfunction "P$1_P$212") (pintype "power_in"))
      (node (ref "P4") (pin "P$213") (pinfunction "P$1_P$213") (pintype "power_in"))
      (node (ref "P4") (pin "P$214") (pinfunction "P$1_P$214") (pintype "power_in"))
      (node (ref "P4") (pin "P$215") (pinfunction "P$1_P$215") (pintype "power_in"))
      (node (ref "P4") (pin "P$216") (pinfunction "P$1_P$216") (pintype "power_in"))
      (node (ref "P4") (pin "P$217") (pinfunction "P$1_P$217") (pintype "power_in"))
      (node (ref "P4") (pin "P$218") (pinfunction "P$1_P$218") (pintype "power_in"))
      (node (ref "P4") (pin "P$219") (pinfunction "P$1_P$219") (pintype "power_in"))
      (node (ref "P4") (pin "P$22") (pinfunction "P$1_P$22") (pintype "power_in"))
      (node (ref "P4") (pin "P$220") (pinfunction "P$1_P$220") (pintype "power_in"))
      (node (ref "P4") (pin "P$221") (pinfunction "P$1_P$221") (pintype "power_in"))
      (node (ref "P4") (pin "P$222") (pinfunction "P$1_P$222") (pintype "power_in"))
      (node (ref "P4") (pin "P$223") (pinfunction "P$1_P$223") (pintype "power_in"))
      (node (ref "P4") (pin "P$224") (pinfunction "P$1_P$224") (pintype "power_in"))
      (node (ref "P4") (pin "P$225") (pinfunction "P$1_P$225") (pintype "power_in"))
      (node (ref "P4") (pin "P$226") (pinfunction "P$1_P$226") (pintype "power_in"))
      (node (ref "P4") (pin "P$227") (pinfunction "P$1_P$227") (pintype "power_in"))
      (node (ref "P4") (pin "P$228") (pinfunction "P$1_P$228") (pintype "power_in"))
      (node (ref "P4") (pin "P$229") (pinfunction "P$1_P$229") (pintype "power_in"))
      (node (ref "P4") (pin "P$23") (pinfunction "P$1_P$23") (pintype "power_in"))
      (node (ref "P4") (pin "P$230") (pinfunction "P$1_P$230") (pintype "power_in"))
      (node (ref "P4") (pin "P$231") (pinfunction "P$1_P$231") (pintype "power_in"))
      (node (ref "P4") (pin "P$232") (pinfunction "P$1_P$232") (pintype "power_in"))
      (node (ref "P4") (pin "P$233") (pinfunction "P$1_P$233") (pintype "power_in"))
      (node (ref "P4") (pin "P$234") (pinfunction "P$1_P$234") (pintype "power_in"))
      (node (ref "P4") (pin "P$235") (pinfunction "P$1_P$235") (pintype "power_in"))
      (node (ref "P4") (pin "P$236") (pinfunction "P$1_P$236") (pintype "power_in"))
      (node (ref "P4") (pin "P$237") (pinfunction "P$1_P$237") (pintype "power_in"))
      (node (ref "P4") (pin "P$238") (pinfunction "P$1_P$238") (pintype "power_in"))
      (node (ref "P4") (pin "P$239") (pinfunction "P$1_P$239") (pintype "power_in"))
      (node (ref "P4") (pin "P$24") (pinfunction "P$1_P$24") (pintype "power_in"))
      (node (ref "P4") (pin "P$240") (pinfunction "P$1_P$240") (pintype "power_in"))
      (node (ref "P4") (pin "P$241") (pinfunction "P$1_P$241") (pintype "power_in"))
      (node (ref "P4") (pin "P$242") (pinfunction "P$1_P$242") (pintype "power_in"))
      (node (ref "P4") (pin "P$243") (pinfunction "P$1_P$243") (pintype "power_in"))
      (node (ref "P4") (pin "P$244") (pinfunction "P$1_P$244") (pintype "power_in"))
      (node (ref "P4") (pin "P$245") (pinfunction "P$1_P$245") (pintype "power_in"))
      (node (ref "P4") (pin "P$246") (pinfunction "P$1_P$246") (pintype "power_in"))
      (node (ref "P4") (pin "P$247") (pinfunction "P$1_P$247") (pintype "power_in"))
      (node (ref "P4") (pin "P$248") (pinfunction "P$1_P$248") (pintype "power_in"))
      (node (ref "P4") (pin "P$249") (pinfunction "P$1_P$249") (pintype "power_in"))
      (node (ref "P4") (pin "P$25") (pinfunction "P$1_P$25") (pintype "power_in"))
      (node (ref "P4") (pin "P$250") (pinfunction "P$1_P$250") (pintype "power_in"))
      (node (ref "P4") (pin "P$251") (pinfunction "P$1_P$251") (pintype "power_in"))
      (node (ref "P4") (pin "P$252") (pinfunction "P$1_P$252") (pintype "power_in"))
      (node (ref "P4") (pin "P$253") (pinfunction "P$1_P$253") (pintype "power_in"))
      (node (ref "P4") (pin "P$254") (pinfunction "P$1_P$254") (pintype "power_in"))
      (node (ref "P4") (pin "P$255") (pinfunction "P$1_P$255") (pintype "power_in"))
      (node (ref "P4") (pin "P$256") (pinfunction "P$1_P$256") (pintype "power_in"))
      (node (ref "P4") (pin "P$257") (pinfunction "P$1_P$257") (pintype "power_in"))
      (node (ref "P4") (pin "P$258") (pinfunction "P$1_P$258") (pintype "power_in"))
      (node (ref "P4") (pin "P$259") (pinfunction "P$1_P$259") (pintype "power_in"))
      (node (ref "P4") (pin "P$26") (pinfunction "P$1_P$26") (pintype "power_in"))
      (node (ref "P4") (pin "P$260") (pinfunction "P$1_P$260") (pintype "power_in"))
      (node (ref "P4") (pin "P$261") (pinfunction "P$1_P$261") (pintype "power_in"))
      (node (ref "P4") (pin "P$262") (pinfunction "P$1_P$262") (pintype "power_in"))
      (node (ref "P4") (pin "P$263") (pinfunction "P$1_P$263") (pintype "power_in"))
      (node (ref "P4") (pin "P$264") (pinfunction "P$1_P$264") (pintype "power_in"))
      (node (ref "P4") (pin "P$265") (pinfunction "P$1_P$265") (pintype "power_in"))
      (node (ref "P4") (pin "P$266") (pinfunction "P$1_P$266") (pintype "power_in"))
      (node (ref "P4") (pin "P$267") (pinfunction "P$1_P$267") (pintype "power_in"))
      (node (ref "P4") (pin "P$268") (pinfunction "P$1_P$268") (pintype "power_in"))
      (node (ref "P4") (pin "P$269") (pinfunction "P$1_P$269") (pintype "power_in"))
      (node (ref "P4") (pin "P$27") (pinfunction "P$1_P$27") (pintype "power_in"))
      (node (ref "P4") (pin "P$270") (pinfunction "P$1_P$270") (pintype "power_in"))
      (node (ref "P4") (pin "P$271") (pinfunction "P$1_P$271") (pintype "power_in"))
      (node (ref "P4") (pin "P$272") (pinfunction "P$1_P$272") (pintype "power_in"))
      (node (ref "P4") (pin "P$273") (pinfunction "P$1_P$273") (pintype "power_in"))
      (node (ref "P4") (pin "P$274") (pinfunction "P$1_P$274") (pintype "power_in"))
      (node (ref "P4") (pin "P$275") (pinfunction "P$1_P$275") (pintype "power_in"))
      (node (ref "P4") (pin "P$276") (pinfunction "P$1_P$276") (pintype "power_in"))
      (node (ref "P4") (pin "P$277") (pinfunction "P$1_P$277") (pintype "power_in"))
      (node (ref "P4") (pin "P$278") (pinfunction "P$1_P$278") (pintype "power_in"))
      (node (ref "P4") (pin "P$279") (pinfunction "P$1_P$279") (pintype "power_in"))
      (node (ref "P4") (pin "P$28") (pinfunction "P$1_P$28") (pintype "power_in"))
      (node (ref "P4") (pin "P$280") (pinfunction "P$1_P$280") (pintype "power_in"))
      (node (ref "P4") (pin "P$281") (pinfunction "P$1_P$281") (pintype "power_in"))
      (node (ref "P4") (pin "P$282") (pinfunction "P$1_P$282") (pintype "power_in"))
      (node (ref "P4") (pin "P$283") (pinfunction "P$1_P$283") (pintype "power_in"))
      (node (ref "P4") (pin "P$284") (pinfunction "P$1_P$284") (pintype "power_in"))
      (node (ref "P4") (pin "P$285") (pinfunction "P$1_P$285") (pintype "power_in"))
      (node (ref "P4") (pin "P$286") (pinfunction "P$1_P$286") (pintype "power_in"))
      (node (ref "P4") (pin "P$287") (pinfunction "P$1_P$287") (pintype "power_in"))
      (node (ref "P4") (pin "P$288") (pinfunction "P$1_P$288") (pintype "power_in"))
      (node (ref "P4") (pin "P$289") (pinfunction "P$1_P$289") (pintype "power_in"))
      (node (ref "P4") (pin "P$29") (pinfunction "P$1_P$29") (pintype "power_in"))
      (node (ref "P4") (pin "P$290") (pinfunction "P$1_P$290") (pintype "power_in"))
      (node (ref "P4") (pin "P$291") (pinfunction "P$1_P$291") (pintype "power_in"))
      (node (ref "P4") (pin "P$292") (pinfunction "P$1_P$292") (pintype "power_in"))
      (node (ref "P4") (pin "P$293") (pinfunction "P$1_P$293") (pintype "power_in"))
      (node (ref "P4") (pin "P$294") (pinfunction "P$1_P$294") (pintype "power_in"))
      (node (ref "P4") (pin "P$295") (pinfunction "P$1_P$295") (pintype "power_in"))
      (node (ref "P4") (pin "P$296") (pinfunction "P$1_P$296") (pintype "power_in"))
      (node (ref "P4") (pin "P$297") (pinfunction "P$1_P$297") (pintype "power_in"))
      (node (ref "P4") (pin "P$298") (pinfunction "P$1_P$298") (pintype "power_in"))
      (node (ref "P4") (pin "P$299") (pinfunction "P$1_P$299") (pintype "power_in"))
      (node (ref "P4") (pin "P$3") (pinfunction "P$1_P$3") (pintype "power_in"))
      (node (ref "P4") (pin "P$30") (pinfunction "P$1_P$30") (pintype "power_in"))
      (node (ref "P4") (pin "P$300") (pinfunction "P$1_P$300") (pintype "power_in"))
      (node (ref "P4") (pin "P$301") (pinfunction "P$1_P$301") (pintype "power_in"))
      (node (ref "P4") (pin "P$302") (pinfunction "P$1_P$302") (pintype "power_in"))
      (node (ref "P4") (pin "P$303") (pinfunction "P$1_P$303") (pintype "power_in"))
      (node (ref "P4") (pin "P$304") (pinfunction "P$1_P$304") (pintype "power_in"))
      (node (ref "P4") (pin "P$305") (pinfunction "P$1_P$305") (pintype "power_in"))
      (node (ref "P4") (pin "P$306") (pinfunction "P$1_P$306") (pintype "power_in"))
      (node (ref "P4") (pin "P$307") (pinfunction "P$1_P$307") (pintype "power_in"))
      (node (ref "P4") (pin "P$308") (pinfunction "P$1_P$308") (pintype "power_in"))
      (node (ref "P4") (pin "P$309") (pinfunction "P$1_P$309") (pintype "power_in"))
      (node (ref "P4") (pin "P$31") (pinfunction "P$1_P$31") (pintype "power_in"))
      (node (ref "P4") (pin "P$310") (pinfunction "P$1_P$310") (pintype "power_in"))
      (node (ref "P4") (pin "P$311") (pinfunction "P$1_P$311") (pintype "power_in"))
      (node (ref "P4") (pin "P$312") (pinfunction "P$1_P$312") (pintype "power_in"))
      (node (ref "P4") (pin "P$313") (pinfunction "P$1_P$313") (pintype "power_in"))
      (node (ref "P4") (pin "P$314") (pinfunction "P$1_P$314") (pintype "power_in"))
      (node (ref "P4") (pin "P$315") (pinfunction "P$1_P$315") (pintype "power_in"))
      (node (ref "P4") (pin "P$316") (pinfunction "P$1_P$316") (pintype "power_in"))
      (node (ref "P4") (pin "P$317") (pinfunction "P$1_P$317") (pintype "power_in"))
      (node (ref "P4") (pin "P$318") (pinfunction "P$1_P$318") (pintype "power_in"))
      (node (ref "P4") (pin "P$319") (pinfunction "P$1_P$319") (pintype "power_in"))
      (node (ref "P4") (pin "P$32") (pinfunction "P$1_P$32") (pintype "power_in"))
      (node (ref "P4") (pin "P$320") (pinfunction "P$1_P$320") (pintype "power_in"))
      (node (ref "P4") (pin "P$321") (pinfunction "P$1_P$321") (pintype "power_in"))
      (node (ref "P4") (pin "P$322") (pinfunction "P$1_P$322") (pintype "power_in"))
      (node (ref "P4") (pin "P$323") (pinfunction "P$1_P$323") (pintype "power_in"))
      (node (ref "P4") (pin "P$324") (pinfunction "P$1_P$324") (pintype "power_in"))
      (node (ref "P4") (pin "P$325") (pinfunction "P$1_P$325") (pintype "power_in"))
      (node (ref "P4") (pin "P$326") (pinfunction "P$1_P$326") (pintype "power_in"))
      (node (ref "P4") (pin "P$327") (pinfunction "P$1_P$327") (pintype "power_in"))
      (node (ref "P4") (pin "P$328") (pinfunction "P$1_P$328") (pintype "power_in"))
      (node (ref "P4") (pin "P$329") (pinfunction "P$1_P$329") (pintype "power_in"))
      (node (ref "P4") (pin "P$33") (pinfunction "P$1_P$33") (pintype "power_in"))
      (node (ref "P4") (pin "P$330") (pinfunction "P$1_P$330") (pintype "power_in"))
      (node (ref "P4") (pin "P$331") (pinfunction "P$1_P$331") (pintype "power_in"))
      (node (ref "P4") (pin "P$332") (pinfunction "P$1_P$332") (pintype "power_in"))
      (node (ref "P4") (pin "P$333") (pinfunction "P$1_P$333") (pintype "power_in"))
      (node (ref "P4") (pin "P$334") (pinfunction "P$1_P$334") (pintype "power_in"))
      (node (ref "P4") (pin "P$335") (pinfunction "P$1_P$335") (pintype "power_in"))
      (node (ref "P4") (pin "P$336") (pinfunction "P$1_P$336") (pintype "power_in"))
      (node (ref "P4") (pin "P$337") (pinfunction "P$1_P$337") (pintype "power_in"))
      (node (ref "P4") (pin "P$338") (pinfunction "P$1_P$338") (pintype "power_in"))
      (node (ref "P4") (pin "P$339") (pinfunction "P$1_P$339") (pintype "power_in"))
      (node (ref "P4") (pin "P$34") (pinfunction "P$1_P$34") (pintype "power_in"))
      (node (ref "P4") (pin "P$340") (pinfunction "P$1_P$340") (pintype "power_in"))
      (node (ref "P4") (pin "P$341") (pinfunction "P$1_P$341") (pintype "power_in"))
      (node (ref "P4") (pin "P$342") (pinfunction "P$1_P$342") (pintype "power_in"))
      (node (ref "P4") (pin "P$343") (pinfunction "P$1_P$343") (pintype "power_in"))
      (node (ref "P4") (pin "P$344") (pinfunction "P$1_P$344") (pintype "power_in"))
      (node (ref "P4") (pin "P$345") (pinfunction "P$1_P$345") (pintype "power_in"))
      (node (ref "P4") (pin "P$346") (pinfunction "P$1_P$346") (pintype "power_in"))
      (node (ref "P4") (pin "P$347") (pinfunction "P$1_P$347") (pintype "power_in"))
      (node (ref "P4") (pin "P$348") (pinfunction "P$1_P$348") (pintype "power_in"))
      (node (ref "P4") (pin "P$349") (pinfunction "P$1_P$349") (pintype "power_in"))
      (node (ref "P4") (pin "P$35") (pinfunction "P$1_P$35") (pintype "power_in"))
      (node (ref "P4") (pin "P$350") (pinfunction "P$1_P$350") (pintype "power_in"))
      (node (ref "P4") (pin "P$351") (pinfunction "P$1_P$351") (pintype "power_in"))
      (node (ref "P4") (pin "P$352") (pinfunction "P$1_P$352") (pintype "power_in"))
      (node (ref "P4") (pin "P$353") (pinfunction "P$1_P$353") (pintype "power_in"))
      (node (ref "P4") (pin "P$354") (pinfunction "P$1_P$354") (pintype "power_in"))
      (node (ref "P4") (pin "P$355") (pinfunction "P$1_P$355") (pintype "power_in"))
      (node (ref "P4") (pin "P$356") (pinfunction "P$1_P$356") (pintype "power_in"))
      (node (ref "P4") (pin "P$357") (pinfunction "P$1_P$357") (pintype "power_in"))
      (node (ref "P4") (pin "P$358") (pinfunction "P$1_P$358") (pintype "power_in"))
      (node (ref "P4") (pin "P$359") (pinfunction "P$1_P$359") (pintype "power_in"))
      (node (ref "P4") (pin "P$36") (pinfunction "P$1_P$36") (pintype "power_in"))
      (node (ref "P4") (pin "P$360") (pinfunction "P$1_P$360") (pintype "power_in"))
      (node (ref "P4") (pin "P$361") (pinfunction "P$1_P$361") (pintype "power_in"))
      (node (ref "P4") (pin "P$362") (pinfunction "P$1_P$362") (pintype "power_in"))
      (node (ref "P4") (pin "P$363") (pinfunction "P$1_P$363") (pintype "power_in"))
      (node (ref "P4") (pin "P$364") (pinfunction "P$1_P$364") (pintype "power_in"))
      (node (ref "P4") (pin "P$365") (pinfunction "P$1_P$365") (pintype "power_in"))
      (node (ref "P4") (pin "P$366") (pinfunction "P$1_P$366") (pintype "power_in"))
      (node (ref "P4") (pin "P$367") (pinfunction "P$1_P$367") (pintype "power_in"))
      (node (ref "P4") (pin "P$368") (pinfunction "P$1_P$368") (pintype "power_in"))
      (node (ref "P4") (pin "P$369") (pinfunction "P$1_P$369") (pintype "power_in"))
      (node (ref "P4") (pin "P$37") (pinfunction "P$1_P$37") (pintype "power_in"))
      (node (ref "P4") (pin "P$370") (pinfunction "P$1_P$370") (pintype "power_in"))
      (node (ref "P4") (pin "P$371") (pinfunction "P$1_P$371") (pintype "power_in"))
      (node (ref "P4") (pin "P$372") (pinfunction "P$1_P$372") (pintype "power_in"))
      (node (ref "P4") (pin "P$373") (pinfunction "P$1_P$373") (pintype "power_in"))
      (node (ref "P4") (pin "P$374") (pinfunction "P$1_P$374") (pintype "power_in"))
      (node (ref "P4") (pin "P$375") (pinfunction "P$1_P$375") (pintype "power_in"))
      (node (ref "P4") (pin "P$376") (pinfunction "P$1_P$376") (pintype "power_in"))
      (node (ref "P4") (pin "P$377") (pinfunction "P$1_P$377") (pintype "power_in"))
      (node (ref "P4") (pin "P$378") (pinfunction "P$1_P$378") (pintype "power_in"))
      (node (ref "P4") (pin "P$379") (pinfunction "P$1_P$379") (pintype "power_in"))
      (node (ref "P4") (pin "P$38") (pinfunction "P$1_P$38") (pintype "power_in"))
      (node (ref "P4") (pin "P$380") (pinfunction "P$1_P$380") (pintype "power_in"))
      (node (ref "P4") (pin "P$381") (pinfunction "P$1_P$381") (pintype "power_in"))
      (node (ref "P4") (pin "P$382") (pinfunction "P$1_P$382") (pintype "power_in"))
      (node (ref "P4") (pin "P$383") (pinfunction "P$1_P$383") (pintype "power_in"))
      (node (ref "P4") (pin "P$384") (pinfunction "P$1_P$384") (pintype "power_in"))
      (node (ref "P4") (pin "P$385") (pinfunction "P$1_P$385") (pintype "power_in"))
      (node (ref "P4") (pin "P$386") (pinfunction "P$1_P$386") (pintype "power_in"))
      (node (ref "P4") (pin "P$387") (pinfunction "P$1_P$387") (pintype "power_in"))
      (node (ref "P4") (pin "P$388") (pinfunction "P$1_P$388") (pintype "power_in"))
      (node (ref "P4") (pin "P$389") (pinfunction "P$1_P$389") (pintype "power_in"))
      (node (ref "P4") (pin "P$39") (pinfunction "P$1_P$39") (pintype "power_in"))
      (node (ref "P4") (pin "P$390") (pinfunction "P$1_P$390") (pintype "power_in"))
      (node (ref "P4") (pin "P$391") (pinfunction "P$1_P$391") (pintype "power_in"))
      (node (ref "P4") (pin "P$392") (pinfunction "P$1_P$392") (pintype "power_in"))
      (node (ref "P4") (pin "P$393") (pinfunction "P$1_P$393") (pintype "power_in"))
      (node (ref "P4") (pin "P$394") (pinfunction "P$1_P$394") (pintype "power_in"))
      (node (ref "P4") (pin "P$395") (pinfunction "P$1_P$395") (pintype "power_in"))
      (node (ref "P4") (pin "P$396") (pinfunction "P$1_P$396") (pintype "power_in"))
      (node (ref "P4") (pin "P$397") (pinfunction "P$1_P$397") (pintype "power_in"))
      (node (ref "P4") (pin "P$398") (pinfunction "P$1_P$398") (pintype "power_in"))
      (node (ref "P4") (pin "P$399") (pinfunction "P$1_P$399") (pintype "power_in"))
      (node (ref "P4") (pin "P$4") (pinfunction "P$1_P$4") (pintype "power_in"))
      (node (ref "P4") (pin "P$40") (pinfunction "P$1_P$40") (pintype "power_in"))
      (node (ref "P4") (pin "P$400") (pinfunction "P$1_P$400") (pintype "power_in"))
      (node (ref "P4") (pin "P$401") (pinfunction "P$1_P$401") (pintype "power_in"))
      (node (ref "P4") (pin "P$402") (pinfunction "P$1_P$402") (pintype "power_in"))
      (node (ref "P4") (pin "P$403") (pinfunction "P$1_P$403") (pintype "power_in"))
      (node (ref "P4") (pin "P$404") (pinfunction "P$1_P$404") (pintype "power_in"))
      (node (ref "P4") (pin "P$405") (pinfunction "P$1_P$405") (pintype "power_in"))
      (node (ref "P4") (pin "P$406") (pinfunction "P$1_P$406") (pintype "power_in"))
      (node (ref "P4") (pin "P$407") (pinfunction "P$1_P$407") (pintype "power_in"))
      (node (ref "P4") (pin "P$408") (pinfunction "P$1_P$408") (pintype "power_in"))
      (node (ref "P4") (pin "P$409") (pinfunction "P$1_P$409") (pintype "power_in"))
      (node (ref "P4") (pin "P$41") (pinfunction "P$1_P$41") (pintype "power_in"))
      (node (ref "P4") (pin "P$410") (pinfunction "P$1_P$410") (pintype "power_in"))
      (node (ref "P4") (pin "P$411") (pinfunction "P$1_P$411") (pintype "power_in"))
      (node (ref "P4") (pin "P$412") (pinfunction "P$1_P$412") (pintype "power_in"))
      (node (ref "P4") (pin "P$413") (pinfunction "P$1_P$413") (pintype "power_in"))
      (node (ref "P4") (pin "P$414") (pinfunction "P$1_P$414") (pintype "power_in"))
      (node (ref "P4") (pin "P$415") (pinfunction "P$1_P$415") (pintype "power_in"))
      (node (ref "P4") (pin "P$416") (pinfunction "P$1_P$416") (pintype "power_in"))
      (node (ref "P4") (pin "P$417") (pinfunction "P$1_P$417") (pintype "power_in"))
      (node (ref "P4") (pin "P$418") (pinfunction "P$1_P$418") (pintype "power_in"))
      (node (ref "P4") (pin "P$419") (pinfunction "P$1_P$419") (pintype "power_in"))
      (node (ref "P4") (pin "P$42") (pinfunction "P$1_P$42") (pintype "power_in"))
      (node (ref "P4") (pin "P$420") (pinfunction "P$1_P$420") (pintype "power_in"))
      (node (ref "P4") (pin "P$421") (pinfunction "P$1_P$421") (pintype "power_in"))
      (node (ref "P4") (pin "P$422") (pinfunction "P$1_P$422") (pintype "power_in"))
      (node (ref "P4") (pin "P$423") (pinfunction "P$1_P$423") (pintype "power_in"))
      (node (ref "P4") (pin "P$424") (pinfunction "P$1_P$424") (pintype "power_in"))
      (node (ref "P4") (pin "P$425") (pinfunction "P$1_P$425") (pintype "power_in"))
      (node (ref "P4") (pin "P$426") (pinfunction "P$1_P$426") (pintype "power_in"))
      (node (ref "P4") (pin "P$427") (pinfunction "P$1_P$427") (pintype "power_in"))
      (node (ref "P4") (pin "P$428") (pinfunction "P$1_P$428") (pintype "power_in"))
      (node (ref "P4") (pin "P$429") (pinfunction "P$1_P$429") (pintype "power_in"))
      (node (ref "P4") (pin "P$43") (pinfunction "P$1_P$43") (pintype "power_in"))
      (node (ref "P4") (pin "P$430") (pinfunction "P$1_P$430") (pintype "power_in"))
      (node (ref "P4") (pin "P$431") (pinfunction "P$1_P$431") (pintype "power_in"))
      (node (ref "P4") (pin "P$432") (pinfunction "P$1_P$432") (pintype "power_in"))
      (node (ref "P4") (pin "P$433") (pinfunction "P$1_P$433") (pintype "power_in"))
      (node (ref "P4") (pin "P$434") (pinfunction "P$1_P$434") (pintype "power_in"))
      (node (ref "P4") (pin "P$435") (pinfunction "P$1_P$435") (pintype "power_in"))
      (node (ref "P4") (pin "P$436") (pinfunction "P$1_P$436") (pintype "power_in"))
      (node (ref "P4") (pin "P$437") (pinfunction "P$1_P$437") (pintype "power_in"))
      (node (ref "P4") (pin "P$438") (pinfunction "P$1_P$438") (pintype "power_in"))
      (node (ref "P4") (pin "P$439") (pinfunction "P$1_P$439") (pintype "power_in"))
      (node (ref "P4") (pin "P$44") (pinfunction "P$1_P$44") (pintype "power_in"))
      (node (ref "P4") (pin "P$440") (pinfunction "P$1_P$440") (pintype "power_in"))
      (node (ref "P4") (pin "P$441") (pinfunction "P$1_P$441") (pintype "power_in"))
      (node (ref "P4") (pin "P$442") (pinfunction "P$1_P$442") (pintype "power_in"))
      (node (ref "P4") (pin "P$443") (pinfunction "P$1_P$443") (pintype "power_in"))
      (node (ref "P4") (pin "P$444") (pinfunction "P$1_P$444") (pintype "power_in"))
      (node (ref "P4") (pin "P$445") (pinfunction "P$1_P$445") (pintype "power_in"))
      (node (ref "P4") (pin "P$446") (pinfunction "P$1_P$446") (pintype "power_in"))
      (node (ref "P4") (pin "P$447") (pinfunction "P$1_P$447") (pintype "power_in"))
      (node (ref "P4") (pin "P$448") (pinfunction "P$1_P$448") (pintype "power_in"))
      (node (ref "P4") (pin "P$449") (pinfunction "P$1_P$449") (pintype "power_in"))
      (node (ref "P4") (pin "P$45") (pinfunction "P$1_P$45") (pintype "power_in"))
      (node (ref "P4") (pin "P$450") (pinfunction "P$1_P$450") (pintype "power_in"))
      (node (ref "P4") (pin "P$451") (pinfunction "P$1_P$451") (pintype "power_in"))
      (node (ref "P4") (pin "P$452") (pinfunction "P$1_P$452") (pintype "power_in"))
      (node (ref "P4") (pin "P$453") (pinfunction "P$1_P$453") (pintype "power_in"))
      (node (ref "P4") (pin "P$454") (pinfunction "P$1_P$454") (pintype "power_in"))
      (node (ref "P4") (pin "P$455") (pinfunction "P$1_P$455") (pintype "power_in"))
      (node (ref "P4") (pin "P$456") (pinfunction "P$1_P$456") (pintype "power_in"))
      (node (ref "P4") (pin "P$457") (pinfunction "P$1_P$457") (pintype "power_in"))
      (node (ref "P4") (pin "P$458") (pinfunction "P$1_P$458") (pintype "power_in"))
      (node (ref "P4") (pin "P$459") (pinfunction "P$1_P$459") (pintype "power_in"))
      (node (ref "P4") (pin "P$46") (pinfunction "P$1_P$46") (pintype "power_in"))
      (node (ref "P4") (pin "P$460") (pinfunction "P$1_P$460") (pintype "power_in"))
      (node (ref "P4") (pin "P$461") (pinfunction "P$1_P$461") (pintype "power_in"))
      (node (ref "P4") (pin "P$462") (pinfunction "P$1_P$462") (pintype "power_in"))
      (node (ref "P4") (pin "P$463") (pinfunction "P$1_P$463") (pintype "power_in"))
      (node (ref "P4") (pin "P$464") (pinfunction "P$1_P$464") (pintype "power_in"))
      (node (ref "P4") (pin "P$465") (pinfunction "P$1_P$465") (pintype "power_in"))
      (node (ref "P4") (pin "P$466") (pinfunction "P$1_P$466") (pintype "power_in"))
      (node (ref "P4") (pin "P$467") (pinfunction "P$1_P$467") (pintype "power_in"))
      (node (ref "P4") (pin "P$468") (pinfunction "P$1_P$468") (pintype "power_in"))
      (node (ref "P4") (pin "P$469") (pinfunction "P$1_P$469") (pintype "power_in"))
      (node (ref "P4") (pin "P$47") (pinfunction "P$1_P$47") (pintype "power_in"))
      (node (ref "P4") (pin "P$470") (pinfunction "P$1_P$470") (pintype "power_in"))
      (node (ref "P4") (pin "P$471") (pinfunction "P$1_P$471") (pintype "power_in"))
      (node (ref "P4") (pin "P$472") (pinfunction "P$1_P$472") (pintype "power_in"))
      (node (ref "P4") (pin "P$473") (pinfunction "P$1_P$473") (pintype "power_in"))
      (node (ref "P4") (pin "P$474") (pinfunction "P$1_P$474") (pintype "power_in"))
      (node (ref "P4") (pin "P$475") (pinfunction "P$1_P$475") (pintype "power_in"))
      (node (ref "P4") (pin "P$476") (pinfunction "P$1_P$476") (pintype "power_in"))
      (node (ref "P4") (pin "P$477") (pinfunction "P$1_P$477") (pintype "power_in"))
      (node (ref "P4") (pin "P$478") (pinfunction "P$1_P$478") (pintype "power_in"))
      (node (ref "P4") (pin "P$479") (pinfunction "P$1_P$479") (pintype "power_in"))
      (node (ref "P4") (pin "P$48") (pinfunction "P$1_P$48") (pintype "power_in"))
      (node (ref "P4") (pin "P$480") (pinfunction "P$1_P$480") (pintype "power_in"))
      (node (ref "P4") (pin "P$481") (pinfunction "P$1_P$481") (pintype "power_in"))
      (node (ref "P4") (pin "P$482") (pinfunction "P$1_P$482") (pintype "power_in"))
      (node (ref "P4") (pin "P$483") (pinfunction "P$1_P$483") (pintype "power_in"))
      (node (ref "P4") (pin "P$484") (pinfunction "P$1_P$484") (pintype "power_in"))
      (node (ref "P4") (pin "P$485") (pinfunction "P$1_P$485") (pintype "power_in"))
      (node (ref "P4") (pin "P$486") (pinfunction "P$1_P$486") (pintype "power_in"))
      (node (ref "P4") (pin "P$487") (pinfunction "P$1_P$487") (pintype "power_in"))
      (node (ref "P4") (pin "P$488") (pinfunction "P$1_P$488") (pintype "power_in"))
      (node (ref "P4") (pin "P$489") (pinfunction "P$1_P$489") (pintype "power_in"))
      (node (ref "P4") (pin "P$49") (pinfunction "P$1_P$49") (pintype "power_in"))
      (node (ref "P4") (pin "P$490") (pinfunction "P$1_P$490") (pintype "power_in"))
      (node (ref "P4") (pin "P$491") (pinfunction "P$1_P$491") (pintype "power_in"))
      (node (ref "P4") (pin "P$492") (pinfunction "P$1_P$492") (pintype "power_in"))
      (node (ref "P4") (pin "P$493") (pinfunction "P$1_P$493") (pintype "power_in"))
      (node (ref "P4") (pin "P$494") (pinfunction "P$1_P$494") (pintype "power_in"))
      (node (ref "P4") (pin "P$495") (pinfunction "P$1_P$495") (pintype "power_in"))
      (node (ref "P4") (pin "P$496") (pinfunction "P$1_P$496") (pintype "power_in"))
      (node (ref "P4") (pin "P$497") (pinfunction "P$1_P$497") (pintype "power_in"))
      (node (ref "P4") (pin "P$498") (pinfunction "P$1_P$498") (pintype "power_in"))
      (node (ref "P4") (pin "P$499") (pinfunction "P$1_P$499") (pintype "power_in"))
      (node (ref "P4") (pin "P$5") (pinfunction "P$1_P$5") (pintype "power_in"))
      (node (ref "P4") (pin "P$50") (pinfunction "P$1_P$50") (pintype "power_in"))
      (node (ref "P4") (pin "P$500") (pinfunction "P$1_P$500") (pintype "power_in"))
      (node (ref "P4") (pin "P$501") (pinfunction "P$1_P$501") (pintype "power_in"))
      (node (ref "P4") (pin "P$502") (pinfunction "P$1_P$502") (pintype "power_in"))
      (node (ref "P4") (pin "P$503") (pinfunction "P$1_P$503") (pintype "power_in"))
      (node (ref "P4") (pin "P$504") (pinfunction "P$1_P$504") (pintype "power_in"))
      (node (ref "P4") (pin "P$505") (pinfunction "P$1_P$505") (pintype "power_in"))
      (node (ref "P4") (pin "P$506") (pinfunction "P$1_P$506") (pintype "power_in"))
      (node (ref "P4") (pin "P$507") (pinfunction "P$1_P$507") (pintype "power_in"))
      (node (ref "P4") (pin "P$508") (pinfunction "P$1_P$508") (pintype "power_in"))
      (node (ref "P4") (pin "P$509") (pinfunction "P$1_P$509") (pintype "power_in"))
      (node (ref "P4") (pin "P$51") (pinfunction "P$1_P$51") (pintype "power_in"))
      (node (ref "P4") (pin "P$510") (pinfunction "P$1_P$510") (pintype "power_in"))
      (node (ref "P4") (pin "P$511") (pinfunction "P$1_P$511") (pintype "power_in"))
      (node (ref "P4") (pin "P$512") (pinfunction "P$1_P$512") (pintype "power_in"))
      (node (ref "P4") (pin "P$513") (pinfunction "P$1_P$513") (pintype "power_in"))
      (node (ref "P4") (pin "P$514") (pinfunction "P$1_P$514") (pintype "power_in"))
      (node (ref "P4") (pin "P$515") (pinfunction "P$1_P$515") (pintype "power_in"))
      (node (ref "P4") (pin "P$516") (pinfunction "P$1_P$516") (pintype "power_in"))
      (node (ref "P4") (pin "P$517") (pinfunction "P$1_P$517") (pintype "power_in"))
      (node (ref "P4") (pin "P$518") (pinfunction "P$1_P$518") (pintype "power_in"))
      (node (ref "P4") (pin "P$519") (pinfunction "P$1_P$519") (pintype "power_in"))
      (node (ref "P4") (pin "P$52") (pinfunction "P$1_P$52") (pintype "power_in"))
      (node (ref "P4") (pin "P$520") (pinfunction "P$1_P$520") (pintype "power_in"))
      (node (ref "P4") (pin "P$521") (pinfunction "P$1_P$521") (pintype "power_in"))
      (node (ref "P4") (pin "P$522") (pinfunction "P$1_P$522") (pintype "power_in"))
      (node (ref "P4") (pin "P$523") (pinfunction "P$1_P$523") (pintype "power_in"))
      (node (ref "P4") (pin "P$524") (pinfunction "P$1_P$524") (pintype "power_in"))
      (node (ref "P4") (pin "P$525") (pinfunction "P$1_P$525") (pintype "power_in"))
      (node (ref "P4") (pin "P$526") (pinfunction "P$1_P$526") (pintype "power_in"))
      (node (ref "P4") (pin "P$527") (pinfunction "P$1_P$527") (pintype "power_in"))
      (node (ref "P4") (pin "P$528") (pinfunction "P$1_P$528") (pintype "power_in"))
      (node (ref "P4") (pin "P$529") (pinfunction "P$1_P$529") (pintype "power_in"))
      (node (ref "P4") (pin "P$53") (pinfunction "P$1_P$53") (pintype "power_in"))
      (node (ref "P4") (pin "P$530") (pinfunction "P$1_P$530") (pintype "power_in"))
      (node (ref "P4") (pin "P$531") (pinfunction "P$1_P$531") (pintype "power_in"))
      (node (ref "P4") (pin "P$532") (pinfunction "P$1_P$532") (pintype "power_in"))
      (node (ref "P4") (pin "P$533") (pinfunction "P$1_P$533") (pintype "power_in"))
      (node (ref "P4") (pin "P$534") (pinfunction "P$1_P$534") (pintype "power_in"))
      (node (ref "P4") (pin "P$535") (pinfunction "P$1_P$535") (pintype "power_in"))
      (node (ref "P4") (pin "P$536") (pinfunction "P$1_P$536") (pintype "power_in"))
      (node (ref "P4") (pin "P$537") (pinfunction "P$1_P$537") (pintype "power_in"))
      (node (ref "P4") (pin "P$538") (pinfunction "P$1_P$538") (pintype "power_in"))
      (node (ref "P4") (pin "P$539") (pinfunction "P$1_P$539") (pintype "power_in"))
      (node (ref "P4") (pin "P$54") (pinfunction "P$1_P$54") (pintype "power_in"))
      (node (ref "P4") (pin "P$540") (pinfunction "P$1_P$540") (pintype "power_in"))
      (node (ref "P4") (pin "P$55") (pinfunction "P$1_P$55") (pintype "power_in"))
      (node (ref "P4") (pin "P$56") (pinfunction "P$1_P$56") (pintype "power_in"))
      (node (ref "P4") (pin "P$57") (pinfunction "P$1_P$57") (pintype "power_in"))
      (node (ref "P4") (pin "P$58") (pinfunction "P$1_P$58") (pintype "power_in"))
      (node (ref "P4") (pin "P$59") (pinfunction "P$1_P$59") (pintype "power_in"))
      (node (ref "P4") (pin "P$6") (pinfunction "P$1_P$6") (pintype "power_in"))
      (node (ref "P4") (pin "P$60") (pinfunction "P$1_P$60") (pintype "power_in"))
      (node (ref "P4") (pin "P$61") (pinfunction "P$1_P$61") (pintype "power_in"))
      (node (ref "P4") (pin "P$62") (pinfunction "P$1_P$62") (pintype "power_in"))
      (node (ref "P4") (pin "P$63") (pinfunction "P$1_P$63") (pintype "power_in"))
      (node (ref "P4") (pin "P$64") (pinfunction "P$1_P$64") (pintype "power_in"))
      (node (ref "P4") (pin "P$65") (pinfunction "P$1_P$65") (pintype "power_in"))
      (node (ref "P4") (pin "P$66") (pinfunction "P$1_P$66") (pintype "power_in"))
      (node (ref "P4") (pin "P$67") (pinfunction "P$1_P$67") (pintype "power_in"))
      (node (ref "P4") (pin "P$68") (pinfunction "P$1_P$68") (pintype "power_in"))
      (node (ref "P4") (pin "P$69") (pinfunction "P$1_P$69") (pintype "power_in"))
      (node (ref "P4") (pin "P$7") (pinfunction "P$1_P$7") (pintype "power_in"))
      (node (ref "P4") (pin "P$70") (pinfunction "P$1_P$70") (pintype "power_in"))
      (node (ref "P4") (pin "P$71") (pinfunction "P$1_P$71") (pintype "power_in"))
      (node (ref "P4") (pin "P$72") (pinfunction "P$1_P$72") (pintype "power_in"))
      (node (ref "P4") (pin "P$73") (pinfunction "P$1_P$73") (pintype "power_in"))
      (node (ref "P4") (pin "P$74") (pinfunction "P$1_P$74") (pintype "power_in"))
      (node (ref "P4") (pin "P$75") (pinfunction "P$1_P$75") (pintype "power_in"))
      (node (ref "P4") (pin "P$76") (pinfunction "P$1_P$76") (pintype "power_in"))
      (node (ref "P4") (pin "P$77") (pinfunction "P$1_P$77") (pintype "power_in"))
      (node (ref "P4") (pin "P$78") (pinfunction "P$1_P$78") (pintype "power_in"))
      (node (ref "P4") (pin "P$79") (pinfunction "P$1_P$79") (pintype "power_in"))
      (node (ref "P4") (pin "P$8") (pinfunction "P$1_P$8") (pintype "power_in"))
      (node (ref "P4") (pin "P$80") (pinfunction "P$1_P$80") (pintype "power_in"))
      (node (ref "P4") (pin "P$81") (pinfunction "P$1_P$81") (pintype "power_in"))
      (node (ref "P4") (pin "P$82") (pinfunction "P$1_P$82") (pintype "power_in"))
      (node (ref "P4") (pin "P$83") (pinfunction "P$1_P$83") (pintype "power_in"))
      (node (ref "P4") (pin "P$84") (pinfunction "P$1_P$84") (pintype "power_in"))
      (node (ref "P4") (pin "P$85") (pinfunction "P$1_P$85") (pintype "power_in"))
      (node (ref "P4") (pin "P$86") (pinfunction "P$1_P$86") (pintype "power_in"))
      (node (ref "P4") (pin "P$87") (pinfunction "P$1_P$87") (pintype "power_in"))
      (node (ref "P4") (pin "P$88") (pinfunction "P$1_P$88") (pintype "power_in"))
      (node (ref "P4") (pin "P$89") (pinfunction "P$1_P$89") (pintype "power_in"))
      (node (ref "P4") (pin "P$9") (pinfunction "P$1_P$9") (pintype "power_in"))
      (node (ref "P4") (pin "P$90") (pinfunction "P$1_P$90") (pintype "power_in"))
      (node (ref "P4") (pin "P$91") (pinfunction "P$1_P$91") (pintype "power_in"))
      (node (ref "P4") (pin "P$92") (pinfunction "P$1_P$92") (pintype "power_in"))
      (node (ref "P4") (pin "P$93") (pinfunction "P$1_P$93") (pintype "power_in"))
      (node (ref "P4") (pin "P$94") (pinfunction "P$1_P$94") (pintype "power_in"))
      (node (ref "P4") (pin "P$95") (pinfunction "P$1_P$95") (pintype "power_in"))
      (node (ref "P4") (pin "P$96") (pinfunction "P$1_P$96") (pintype "power_in"))
      (node (ref "P4") (pin "P$97") (pinfunction "P$1_P$97") (pintype "power_in"))
      (node (ref "P4") (pin "P$98") (pinfunction "P$1_P$98") (pintype "power_in"))
      (node (ref "P4") (pin "P$99") (pinfunction "P$1_P$99") (pintype "power_in"))
    )
    (net (code "6") (name "/P5") (class "Default")
      (node (ref "JP1") (pin "P$6") (pinfunction "5_P$6") (pintype "bidirectional"))
      (node (ref "P5") (pin "P$1") (pinfunction "P$1_P$1") (pintype "power_in"))
      (node (ref "P5") (pin "P$10") (pinfunction "P$1_P$10") (pintype "power_in"))
      (node (ref "P5") (pin "P$100") (pinfunction "P$1_P$100") (pintype "power_in"))
      (node (ref "P5") (pin "P$101") (pinfunction "P$1_P$101") (pintype "power_in"))
      (node (ref "P5") (pin "P$102") (pinfunction "P$1_P$102") (pintype "power_in"))
      (node (ref "P5") (pin "P$103") (pinfunction "P$1_P$103") (pintype "power_in"))
      (node (ref "P5") (pin "P$104") (pinfunction "P$1_P$104") (pintype "power_in"))
      (node (ref "P5") (pin "P$105") (pinfunction "P$1_P$105") (pintype "power_in"))
      (node (ref "P5") (pin "P$106") (pinfunction "P$1_P$106") (pintype "power_in"))
      (node (ref "P5") (pin "P$107") (pinfunction "P$1_P$107") (pintype "power_in"))
      (node (ref "P5") (pin "P$108") (pinfunction "P$1_P$108") (pintype "power_in"))
      (node (ref "P5") (pin "P$109") (pinfunction "P$1_P$109") (pintype "power_in"))
      (node (ref "P5") (pin "P$11") (pinfunction "P$1_P$11") (pintype "power_in"))
      (node (ref "P5") (pin "P$110") (pinfunction "P$1_P$110") (pintype "power_in"))
      (node (ref "P5") (pin "P$111") (pinfunction "P$1_P$111") (pintype "power_in"))
      (node (ref "P5") (pin "P$112") (pinfunction "P$1_P$112") (pintype "power_in"))
      (node (ref "P5") (pin "P$113") (pinfunction "P$1_P$113") (pintype "power_in"))
      (node (ref "P5") (pin "P$114") (pinfunction "P$1_P$114") (pintype "power_in"))
      (node (ref "P5") (pin "P$115") (pinfunction "P$1_P$115") (pintype "power_in"))
      (node (ref "P5") (pin "P$116") (pinfunction "P$1_P$116") (pintype "power_in"))
      (node (ref "P5") (pin "P$117") (pinfunction "P$1_P$117") (pintype "power_in"))
      (node (ref "P5") (pin "P$118") (pinfunction "P$1_P$118") (pintype "power_in"))
      (node (ref "P5") (pin "P$119") (pinfunction "P$1_P$119") (pintype "power_in"))
      (node (ref "P5") (pin "P$12") (pinfunction "P$1_P$12") (pintype "power_in"))
      (node (ref "P5") (pin "P$120") (pinfunction "P$1_P$120") (pintype "power_in"))
      (node (ref "P5") (pin "P$121") (pinfunction "P$1_P$121") (pintype "power_in"))
      (node (ref "P5") (pin "P$122") (pinfunction "P$1_P$122") (pintype "power_in"))
      (node (ref "P5") (pin "P$123") (pinfunction "P$1_P$123") (pintype "power_in"))
      (node (ref "P5") (pin "P$124") (pinfunction "P$1_P$124") (pintype "power_in"))
      (node (ref "P5") (pin "P$125") (pinfunction "P$1_P$125") (pintype "power_in"))
      (node (ref "P5") (pin "P$126") (pinfunction "P$1_P$126") (pintype "power_in"))
      (node (ref "P5") (pin "P$127") (pinfunction "P$1_P$127") (pintype "power_in"))
      (node (ref "P5") (pin "P$128") (pinfunction "P$1_P$128") (pintype "power_in"))
      (node (ref "P5") (pin "P$129") (pinfunction "P$1_P$129") (pintype "power_in"))
      (node (ref "P5") (pin "P$13") (pinfunction "P$1_P$13") (pintype "power_in"))
      (node (ref "P5") (pin "P$130") (pinfunction "P$1_P$130") (pintype "power_in"))
      (node (ref "P5") (pin "P$131") (pinfunction "P$1_P$131") (pintype "power_in"))
      (node (ref "P5") (pin "P$132") (pinfunction "P$1_P$132") (pintype "power_in"))
      (node (ref "P5") (pin "P$133") (pinfunction "P$1_P$133") (pintype "power_in"))
      (node (ref "P5") (pin "P$134") (pinfunction "P$1_P$134") (pintype "power_in"))
      (node (ref "P5") (pin "P$135") (pinfunction "P$1_P$135") (pintype "power_in"))
      (node (ref "P5") (pin "P$136") (pinfunction "P$1_P$136") (pintype "power_in"))
      (node (ref "P5") (pin "P$137") (pinfunction "P$1_P$137") (pintype "power_in"))
      (node (ref "P5") (pin "P$138") (pinfunction "P$1_P$138") (pintype "power_in"))
      (node (ref "P5") (pin "P$139") (pinfunction "P$1_P$139") (pintype "power_in"))
      (node (ref "P5") (pin "P$14") (pinfunction "P$1_P$14") (pintype "power_in"))
      (node (ref "P5") (pin "P$140") (pinfunction "P$1_P$140") (pintype "power_in"))
      (node (ref "P5") (pin "P$141") (pinfunction "P$1_P$141") (pintype "power_in"))
      (node (ref "P5") (pin "P$142") (pinfunction "P$1_P$142") (pintype "power_in"))
      (node (ref "P5") (pin "P$143") (pinfunction "P$1_P$143") (pintype "power_in"))
      (node (ref "P5") (pin "P$144") (pinfunction "P$1_P$144") (pintype "power_in"))
      (node (ref "P5") (pin "P$145") (pinfunction "P$1_P$145") (pintype "power_in"))
      (node (ref "P5") (pin "P$146") (pinfunction "P$1_P$146") (pintype "power_in"))
      (node (ref "P5") (pin "P$147") (pinfunction "P$1_P$147") (pintype "power_in"))
      (node (ref "P5") (pin "P$148") (pinfunction "P$1_P$148") (pintype "power_in"))
      (node (ref "P5") (pin "P$149") (pinfunction "P$1_P$149") (pintype "power_in"))
      (node (ref "P5") (pin "P$15") (pinfunction "P$1_P$15") (pintype "power_in"))
      (node (ref "P5") (pin "P$150") (pinfunction "P$1_P$150") (pintype "power_in"))
      (node (ref "P5") (pin "P$151") (pinfunction "P$1_P$151") (pintype "power_in"))
      (node (ref "P5") (pin "P$152") (pinfunction "P$1_P$152") (pintype "power_in"))
      (node (ref "P5") (pin "P$153") (pinfunction "P$1_P$153") (pintype "power_in"))
      (node (ref "P5") (pin "P$154") (pinfunction "P$1_P$154") (pintype "power_in"))
      (node (ref "P5") (pin "P$155") (pinfunction "P$1_P$155") (pintype "power_in"))
      (node (ref "P5") (pin "P$156") (pinfunction "P$1_P$156") (pintype "power_in"))
      (node (ref "P5") (pin "P$157") (pinfunction "P$1_P$157") (pintype "power_in"))
      (node (ref "P5") (pin "P$158") (pinfunction "P$1_P$158") (pintype "power_in"))
      (node (ref "P5") (pin "P$159") (pinfunction "P$1_P$159") (pintype "power_in"))
      (node (ref "P5") (pin "P$16") (pinfunction "P$1_P$16") (pintype "power_in"))
      (node (ref "P5") (pin "P$160") (pinfunction "P$1_P$160") (pintype "power_in"))
      (node (ref "P5") (pin "P$161") (pinfunction "P$1_P$161") (pintype "power_in"))
      (node (ref "P5") (pin "P$162") (pinfunction "P$1_P$162") (pintype "power_in"))
      (node (ref "P5") (pin "P$163") (pinfunction "P$1_P$163") (pintype "power_in"))
      (node (ref "P5") (pin "P$164") (pinfunction "P$1_P$164") (pintype "power_in"))
      (node (ref "P5") (pin "P$165") (pinfunction "P$1_P$165") (pintype "power_in"))
      (node (ref "P5") (pin "P$166") (pinfunction "P$1_P$166") (pintype "power_in"))
      (node (ref "P5") (pin "P$167") (pinfunction "P$1_P$167") (pintype "power_in"))
      (node (ref "P5") (pin "P$168") (pinfunction "P$1_P$168") (pintype "power_in"))
      (node (ref "P5") (pin "P$169") (pinfunction "P$1_P$169") (pintype "power_in"))
      (node (ref "P5") (pin "P$17") (pinfunction "P$1_P$17") (pintype "power_in"))
      (node (ref "P5") (pin "P$170") (pinfunction "P$1_P$170") (pintype "power_in"))
      (node (ref "P5") (pin "P$171") (pinfunction "P$1_P$171") (pintype "power_in"))
      (node (ref "P5") (pin "P$172") (pinfunction "P$1_P$172") (pintype "power_in"))
      (node (ref "P5") (pin "P$173") (pinfunction "P$1_P$173") (pintype "power_in"))
      (node (ref "P5") (pin "P$174") (pinfunction "P$1_P$174") (pintype "power_in"))
      (node (ref "P5") (pin "P$175") (pinfunction "P$1_P$175") (pintype "power_in"))
      (node (ref "P5") (pin "P$176") (pinfunction "P$1_P$176") (pintype "power_in"))
      (node (ref "P5") (pin "P$177") (pinfunction "P$1_P$177") (pintype "power_in"))
      (node (ref "P5") (pin "P$178") (pinfunction "P$1_P$178") (pintype "power_in"))
      (node (ref "P5") (pin "P$179") (pinfunction "P$1_P$179") (pintype "power_in"))
      (node (ref "P5") (pin "P$18") (pinfunction "P$1_P$18") (pintype "power_in"))
      (node (ref "P5") (pin "P$180") (pinfunction "P$1_P$180") (pintype "power_in"))
      (node (ref "P5") (pin "P$181") (pinfunction "P$1_P$181") (pintype "power_in"))
      (node (ref "P5") (pin "P$182") (pinfunction "P$1_P$182") (pintype "power_in"))
      (node (ref "P5") (pin "P$183") (pinfunction "P$1_P$183") (pintype "power_in"))
      (node (ref "P5") (pin "P$184") (pinfunction "P$1_P$184") (pintype "power_in"))
      (node (ref "P5") (pin "P$185") (pinfunction "P$1_P$185") (pintype "power_in"))
      (node (ref "P5") (pin "P$186") (pinfunction "P$1_P$186") (pintype "power_in"))
      (node (ref "P5") (pin "P$187") (pinfunction "P$1_P$187") (pintype "power_in"))
      (node (ref "P5") (pin "P$188") (pinfunction "P$1_P$188") (pintype "power_in"))
      (node (ref "P5") (pin "P$189") (pinfunction "P$1_P$189") (pintype "power_in"))
      (node (ref "P5") (pin "P$19") (pinfunction "P$1_P$19") (pintype "power_in"))
      (node (ref "P5") (pin "P$190") (pinfunction "P$1_P$190") (pintype "power_in"))
      (node (ref "P5") (pin "P$191") (pinfunction "P$1_P$191") (pintype "power_in"))
      (node (ref "P5") (pin "P$192") (pinfunction "P$1_P$192") (pintype "power_in"))
      (node (ref "P5") (pin "P$193") (pinfunction "P$1_P$193") (pintype "power_in"))
      (node (ref "P5") (pin "P$194") (pinfunction "P$1_P$194") (pintype "power_in"))
      (node (ref "P5") (pin "P$195") (pinfunction "P$1_P$195") (pintype "power_in"))
      (node (ref "P5") (pin "P$196") (pinfunction "P$1_P$196") (pintype "power_in"))
      (node (ref "P5") (pin "P$197") (pinfunction "P$1_P$197") (pintype "power_in"))
      (node (ref "P5") (pin "P$198") (pinfunction "P$1_P$198") (pintype "power_in"))
      (node (ref "P5") (pin "P$199") (pinfunction "P$1_P$199") (pintype "power_in"))
      (node (ref "P5") (pin "P$2") (pinfunction "P$1_P$2") (pintype "power_in"))
      (node (ref "P5") (pin "P$20") (pinfunction "P$1_P$20") (pintype "power_in"))
      (node (ref "P5") (pin "P$200") (pinfunction "P$1_P$200") (pintype "power_in"))
      (node (ref "P5") (pin "P$201") (pinfunction "P$1_P$201") (pintype "power_in"))
      (node (ref "P5") (pin "P$202") (pinfunction "P$1_P$202") (pintype "power_in"))
      (node (ref "P5") (pin "P$203") (pinfunction "P$1_P$203") (pintype "power_in"))
      (node (ref "P5") (pin "P$204") (pinfunction "P$1_P$204") (pintype "power_in"))
      (node (ref "P5") (pin "P$205") (pinfunction "P$1_P$205") (pintype "power_in"))
      (node (ref "P5") (pin "P$206") (pinfunction "P$1_P$206") (pintype "power_in"))
      (node (ref "P5") (pin "P$207") (pinfunction "P$1_P$207") (pintype "power_in"))
      (node (ref "P5") (pin "P$208") (pinfunction "P$1_P$208") (pintype "power_in"))
      (node (ref "P5") (pin "P$209") (pinfunction "P$1_P$209") (pintype "power_in"))
      (node (ref "P5") (pin "P$21") (pinfunction "P$1_P$21") (pintype "power_in"))
      (node (ref "P5") (pin "P$210") (pinfunction "P$1_P$210") (pintype "power_in"))
      (node (ref "P5") (pin "P$211") (pinfunction "P$1_P$211") (pintype "power_in"))
      (node (ref "P5") (pin "P$212") (pinfunction "P$1_P$212") (pintype "power_in"))
      (node (ref "P5") (pin "P$213") (pinfunction "P$1_P$213") (pintype "power_in"))
      (node (ref "P5") (pin "P$214") (pinfunction "P$1_P$214") (pintype "power_in"))
      (node (ref "P5") (pin "P$215") (pinfunction "P$1_P$215") (pintype "power_in"))
      (node (ref "P5") (pin "P$216") (pinfunction "P$1_P$216") (pintype "power_in"))
      (node (ref "P5") (pin "P$217") (pinfunction "P$1_P$217") (pintype "power_in"))
      (node (ref "P5") (pin "P$218") (pinfunction "P$1_P$218") (pintype "power_in"))
      (node (ref "P5") (pin "P$219") (pinfunction "P$1_P$219") (pintype "power_in"))
      (node (ref "P5") (pin "P$22") (pinfunction "P$1_P$22") (pintype "power_in"))
      (node (ref "P5") (pin "P$220") (pinfunction "P$1_P$220") (pintype "power_in"))
      (node (ref "P5") (pin "P$221") (pinfunction "P$1_P$221") (pintype "power_in"))
      (node (ref "P5") (pin "P$222") (pinfunction "P$1_P$222") (pintype "power_in"))
      (node (ref "P5") (pin "P$223") (pinfunction "P$1_P$223") (pintype "power_in"))
      (node (ref "P5") (pin "P$224") (pinfunction "P$1_P$224") (pintype "power_in"))
      (node (ref "P5") (pin "P$225") (pinfunction "P$1_P$225") (pintype "power_in"))
      (node (ref "P5") (pin "P$226") (pinfunction "P$1_P$226") (pintype "power_in"))
      (node (ref "P5") (pin "P$227") (pinfunction "P$1_P$227") (pintype "power_in"))
      (node (ref "P5") (pin "P$228") (pinfunction "P$1_P$228") (pintype "power_in"))
      (node (ref "P5") (pin "P$229") (pinfunction "P$1_P$229") (pintype "power_in"))
      (node (ref "P5") (pin "P$23") (pinfunction "P$1_P$23") (pintype "power_in"))
      (node (ref "P5") (pin "P$230") (pinfunction "P$1_P$230") (pintype "power_in"))
      (node (ref "P5") (pin "P$231") (pinfunction "P$1_P$231") (pintype "power_in"))
      (node (ref "P5") (pin "P$232") (pinfunction "P$1_P$232") (pintype "power_in"))
      (node (ref "P5") (pin "P$233") (pinfunction "P$1_P$233") (pintype "power_in"))
      (node (ref "P5") (pin "P$234") (pinfunction "P$1_P$234") (pintype "power_in"))
      (node (ref "P5") (pin "P$235") (pinfunction "P$1_P$235") (pintype "power_in"))
      (node (ref "P5") (pin "P$236") (pinfunction "P$1_P$236") (pintype "power_in"))
      (node (ref "P5") (pin "P$237") (pinfunction "P$1_P$237") (pintype "power_in"))
      (node (ref "P5") (pin "P$238") (pinfunction "P$1_P$238") (pintype "power_in"))
      (node (ref "P5") (pin "P$239") (pinfunction "P$1_P$239") (pintype "power_in"))
      (node (ref "P5") (pin "P$24") (pinfunction "P$1_P$24") (pintype "power_in"))
      (node (ref "P5") (pin "P$240") (pinfunction "P$1_P$240") (pintype "power_in"))
      (node (ref "P5") (pin "P$241") (pinfunction "P$1_P$241") (pintype "power_in"))
      (node (ref "P5") (pin "P$242") (pinfunction "P$1_P$242") (pintype "power_in"))
      (node (ref "P5") (pin "P$243") (pinfunction "P$1_P$243") (pintype "power_in"))
      (node (ref "P5") (pin "P$244") (pinfunction "P$1_P$244") (pintype "power_in"))
      (node (ref "P5") (pin "P$245") (pinfunction "P$1_P$245") (pintype "power_in"))
      (node (ref "P5") (pin "P$246") (pinfunction "P$1_P$246") (pintype "power_in"))
      (node (ref "P5") (pin "P$247") (pinfunction "P$1_P$247") (pintype "power_in"))
      (node (ref "P5") (pin "P$248") (pinfunction "P$1_P$248") (pintype "power_in"))
      (node (ref "P5") (pin "P$249") (pinfunction "P$1_P$249") (pintype "power_in"))
      (node (ref "P5") (pin "P$25") (pinfunction "P$1_P$25") (pintype "power_in"))
      (node (ref "P5") (pin "P$250") (pinfunction "P$1_P$250") (pintype "power_in"))
      (node (ref "P5") (pin "P$251") (pinfunction "P$1_P$251") (pintype "power_in"))
      (node (ref "P5") (pin "P$252") (pinfunction "P$1_P$252") (pintype "power_in"))
      (node (ref "P5") (pin "P$253") (pinfunction "P$1_P$253") (pintype "power_in"))
      (node (ref "P5") (pin "P$254") (pinfunction "P$1_P$254") (pintype "power_in"))
      (node (ref "P5") (pin "P$255") (pinfunction "P$1_P$255") (pintype "power_in"))
      (node (ref "P5") (pin "P$256") (pinfunction "P$1_P$256") (pintype "power_in"))
      (node (ref "P5") (pin "P$257") (pinfunction "P$1_P$257") (pintype "power_in"))
      (node (ref "P5") (pin "P$258") (pinfunction "P$1_P$258") (pintype "power_in"))
      (node (ref "P5") (pin "P$259") (pinfunction "P$1_P$259") (pintype "power_in"))
      (node (ref "P5") (pin "P$26") (pinfunction "P$1_P$26") (pintype "power_in"))
      (node (ref "P5") (pin "P$260") (pinfunction "P$1_P$260") (pintype "power_in"))
      (node (ref "P5") (pin "P$261") (pinfunction "P$1_P$261") (pintype "power_in"))
      (node (ref "P5") (pin "P$262") (pinfunction "P$1_P$262") (pintype "power_in"))
      (node (ref "P5") (pin "P$263") (pinfunction "P$1_P$263") (pintype "power_in"))
      (node (ref "P5") (pin "P$264") (pinfunction "P$1_P$264") (pintype "power_in"))
      (node (ref "P5") (pin "P$265") (pinfunction "P$1_P$265") (pintype "power_in"))
      (node (ref "P5") (pin "P$266") (pinfunction "P$1_P$266") (pintype "power_in"))
      (node (ref "P5") (pin "P$267") (pinfunction "P$1_P$267") (pintype "power_in"))
      (node (ref "P5") (pin "P$268") (pinfunction "P$1_P$268") (pintype "power_in"))
      (node (ref "P5") (pin "P$269") (pinfunction "P$1_P$269") (pintype "power_in"))
      (node (ref "P5") (pin "P$27") (pinfunction "P$1_P$27") (pintype "power_in"))
      (node (ref "P5") (pin "P$270") (pinfunction "P$1_P$270") (pintype "power_in"))
      (node (ref "P5") (pin "P$271") (pinfunction "P$1_P$271") (pintype "power_in"))
      (node (ref "P5") (pin "P$272") (pinfunction "P$1_P$272") (pintype "power_in"))
      (node (ref "P5") (pin "P$273") (pinfunction "P$1_P$273") (pintype "power_in"))
      (node (ref "P5") (pin "P$274") (pinfunction "P$1_P$274") (pintype "power_in"))
      (node (ref "P5") (pin "P$275") (pinfunction "P$1_P$275") (pintype "power_in"))
      (node (ref "P5") (pin "P$276") (pinfunction "P$1_P$276") (pintype "power_in"))
      (node (ref "P5") (pin "P$277") (pinfunction "P$1_P$277") (pintype "power_in"))
      (node (ref "P5") (pin "P$278") (pinfunction "P$1_P$278") (pintype "power_in"))
      (node (ref "P5") (pin "P$279") (pinfunction "P$1_P$279") (pintype "power_in"))
      (node (ref "P5") (pin "P$28") (pinfunction "P$1_P$28") (pintype "power_in"))
      (node (ref "P5") (pin "P$280") (pinfunction "P$1_P$280") (pintype "power_in"))
      (node (ref "P5") (pin "P$281") (pinfunction "P$1_P$281") (pintype "power_in"))
      (node (ref "P5") (pin "P$282") (pinfunction "P$1_P$282") (pintype "power_in"))
      (node (ref "P5") (pin "P$283") (pinfunction "P$1_P$283") (pintype "power_in"))
      (node (ref "P5") (pin "P$284") (pinfunction "P$1_P$284") (pintype "power_in"))
      (node (ref "P5") (pin "P$285") (pinfunction "P$1_P$285") (pintype "power_in"))
      (node (ref "P5") (pin "P$286") (pinfunction "P$1_P$286") (pintype "power_in"))
      (node (ref "P5") (pin "P$287") (pinfunction "P$1_P$287") (pintype "power_in"))
      (node (ref "P5") (pin "P$288") (pinfunction "P$1_P$288") (pintype "power_in"))
      (node (ref "P5") (pin "P$29") (pinfunction "P$1_P$29") (pintype "power_in"))
      (node (ref "P5") (pin "P$3") (pinfunction "P$1_P$3") (pintype "power_in"))
      (node (ref "P5") (pin "P$30") (pinfunction "P$1_P$30") (pintype "power_in"))
      (node (ref "P5") (pin "P$31") (pinfunction "P$1_P$31") (pintype "power_in"))
      (node (ref "P5") (pin "P$32") (pinfunction "P$1_P$32") (pintype "power_in"))
      (node (ref "P5") (pin "P$33") (pinfunction "P$1_P$33") (pintype "power_in"))
      (node (ref "P5") (pin "P$34") (pinfunction "P$1_P$34") (pintype "power_in"))
      (node (ref "P5") (pin "P$35") (pinfunction "P$1_P$35") (pintype "power_in"))
      (node (ref "P5") (pin "P$36") (pinfunction "P$1_P$36") (pintype "power_in"))
      (node (ref "P5") (pin "P$37") (pinfunction "P$1_P$37") (pintype "power_in"))
      (node (ref "P5") (pin "P$38") (pinfunction "P$1_P$38") (pintype "power_in"))
      (node (ref "P5") (pin "P$39") (pinfunction "P$1_P$39") (pintype "power_in"))
      (node (ref "P5") (pin "P$4") (pinfunction "P$1_P$4") (pintype "power_in"))
      (node (ref "P5") (pin "P$40") (pinfunction "P$1_P$40") (pintype "power_in"))
      (node (ref "P5") (pin "P$41") (pinfunction "P$1_P$41") (pintype "power_in"))
      (node (ref "P5") (pin "P$42") (pinfunction "P$1_P$42") (pintype "power_in"))
      (node (ref "P5") (pin "P$43") (pinfunction "P$1_P$43") (pintype "power_in"))
      (node (ref "P5") (pin "P$44") (pinfunction "P$1_P$44") (pintype "power_in"))
      (node (ref "P5") (pin "P$45") (pinfunction "P$1_P$45") (pintype "power_in"))
      (node (ref "P5") (pin "P$46") (pinfunction "P$1_P$46") (pintype "power_in"))
      (node (ref "P5") (pin "P$47") (pinfunction "P$1_P$47") (pintype "power_in"))
      (node (ref "P5") (pin "P$48") (pinfunction "P$1_P$48") (pintype "power_in"))
      (node (ref "P5") (pin "P$49") (pinfunction "P$1_P$49") (pintype "power_in"))
      (node (ref "P5") (pin "P$5") (pinfunction "P$1_P$5") (pintype "power_in"))
      (node (ref "P5") (pin "P$50") (pinfunction "P$1_P$50") (pintype "power_in"))
      (node (ref "P5") (pin "P$51") (pinfunction "P$1_P$51") (pintype "power_in"))
      (node (ref "P5") (pin "P$52") (pinfunction "P$1_P$52") (pintype "power_in"))
      (node (ref "P5") (pin "P$53") (pinfunction "P$1_P$53") (pintype "power_in"))
      (node (ref "P5") (pin "P$54") (pinfunction "P$1_P$54") (pintype "power_in"))
      (node (ref "P5") (pin "P$55") (pinfunction "P$1_P$55") (pintype "power_in"))
      (node (ref "P5") (pin "P$56") (pinfunction "P$1_P$56") (pintype "power_in"))
      (node (ref "P5") (pin "P$57") (pinfunction "P$1_P$57") (pintype "power_in"))
      (node (ref "P5") (pin "P$58") (pinfunction "P$1_P$58") (pintype "power_in"))
      (node (ref "P5") (pin "P$59") (pinfunction "P$1_P$59") (pintype "power_in"))
      (node (ref "P5") (pin "P$6") (pinfunction "P$1_P$6") (pintype "power_in"))
      (node (ref "P5") (pin "P$60") (pinfunction "P$1_P$60") (pintype "power_in"))
      (node (ref "P5") (pin "P$61") (pinfunction "P$1_P$61") (pintype "power_in"))
      (node (ref "P5") (pin "P$62") (pinfunction "P$1_P$62") (pintype "power_in"))
      (node (ref "P5") (pin "P$63") (pinfunction "P$1_P$63") (pintype "power_in"))
      (node (ref "P5") (pin "P$64") (pinfunction "P$1_P$64") (pintype "power_in"))
      (node (ref "P5") (pin "P$65") (pinfunction "P$1_P$65") (pintype "power_in"))
      (node (ref "P5") (pin "P$66") (pinfunction "P$1_P$66") (pintype "power_in"))
      (node (ref "P5") (pin "P$67") (pinfunction "P$1_P$67") (pintype "power_in"))
      (node (ref "P5") (pin "P$68") (pinfunction "P$1_P$68") (pintype "power_in"))
      (node (ref "P5") (pin "P$69") (pinfunction "P$1_P$69") (pintype "power_in"))
      (node (ref "P5") (pin "P$7") (pinfunction "P$1_P$7") (pintype "power_in"))
      (node (ref "P5") (pin "P$70") (pinfunction "P$1_P$70") (pintype "power_in"))
      (node (ref "P5") (pin "P$71") (pinfunction "P$1_P$71") (pintype "power_in"))
      (node (ref "P5") (pin "P$72") (pinfunction "P$1_P$72") (pintype "power_in"))
      (node (ref "P5") (pin "P$73") (pinfunction "P$1_P$73") (pintype "power_in"))
      (node (ref "P5") (pin "P$74") (pinfunction "P$1_P$74") (pintype "power_in"))
      (node (ref "P5") (pin "P$75") (pinfunction "P$1_P$75") (pintype "power_in"))
      (node (ref "P5") (pin "P$76") (pinfunction "P$1_P$76") (pintype "power_in"))
      (node (ref "P5") (pin "P$77") (pinfunction "P$1_P$77") (pintype "power_in"))
      (node (ref "P5") (pin "P$78") (pinfunction "P$1_P$78") (pintype "power_in"))
      (node (ref "P5") (pin "P$79") (pinfunction "P$1_P$79") (pintype "power_in"))
      (node (ref "P5") (pin "P$8") (pinfunction "P$1_P$8") (pintype "power_in"))
      (node (ref "P5") (pin "P$80") (pinfunction "P$1_P$80") (pintype "power_in"))
      (node (ref "P5") (pin "P$81") (pinfunction "P$1_P$81") (pintype "power_in"))
      (node (ref "P5") (pin "P$82") (pinfunction "P$1_P$82") (pintype "power_in"))
      (node (ref "P5") (pin "P$83") (pinfunction "P$1_P$83") (pintype "power_in"))
      (node (ref "P5") (pin "P$84") (pinfunction "P$1_P$84") (pintype "power_in"))
      (node (ref "P5") (pin "P$85") (pinfunction "P$1_P$85") (pintype "power_in"))
      (node (ref "P5") (pin "P$86") (pinfunction "P$1_P$86") (pintype "power_in"))
      (node (ref "P5") (pin "P$87") (pinfunction "P$1_P$87") (pintype "power_in"))
      (node (ref "P5") (pin "P$88") (pinfunction "P$1_P$88") (pintype "power_in"))
      (node (ref "P5") (pin "P$89") (pinfunction "P$1_P$89") (pintype "power_in"))
      (node (ref "P5") (pin "P$9") (pinfunction "P$1_P$9") (pintype "power_in"))
      (node (ref "P5") (pin "P$90") (pinfunction "P$1_P$90") (pintype "power_in"))
      (node (ref "P5") (pin "P$91") (pinfunction "P$1_P$91") (pintype "power_in"))
      (node (ref "P5") (pin "P$92") (pinfunction "P$1_P$92") (pintype "power_in"))
      (node (ref "P5") (pin "P$93") (pinfunction "P$1_P$93") (pintype "power_in"))
      (node (ref "P5") (pin "P$94") (pinfunction "P$1_P$94") (pintype "power_in"))
      (node (ref "P5") (pin "P$95") (pinfunction "P$1_P$95") (pintype "power_in"))
      (node (ref "P5") (pin "P$96") (pinfunction "P$1_P$96") (pintype "power_in"))
      (node (ref "P5") (pin "P$97") (pinfunction "P$1_P$97") (pintype "power_in"))
      (node (ref "P5") (pin "P$98") (pinfunction "P$1_P$98") (pintype "power_in"))
      (node (ref "P5") (pin "P$99") (pinfunction "P$1_P$99") (pintype "power_in"))
    )
    (net (code "7") (name "/P6") (class "Default")
      (node (ref "JP1") (pin "P$7") (pinfunction "6_P$7") (pintype "bidirectional"))
      (node (ref "P6") (pin "P$1") (pinfunction "P$1_P$1") (pintype "power_in"))
      (node (ref "P6") (pin "P$10") (pinfunction "P$1_P$10") (pintype "power_in"))
      (node (ref "P6") (pin "P$100") (pinfunction "P$1_P$100") (pintype "power_in"))
      (node (ref "P6") (pin "P$101") (pinfunction "P$1_P$101") (pintype "power_in"))
      (node (ref "P6") (pin "P$102") (pinfunction "P$1_P$102") (pintype "power_in"))
      (node (ref "P6") (pin "P$103") (pinfunction "P$1_P$103") (pintype "power_in"))
      (node (ref "P6") (pin "P$104") (pinfunction "P$1_P$104") (pintype "power_in"))
      (node (ref "P6") (pin "P$105") (pinfunction "P$1_P$105") (pintype "power_in"))
      (node (ref "P6") (pin "P$106") (pinfunction "P$1_P$106") (pintype "power_in"))
      (node (ref "P6") (pin "P$107") (pinfunction "P$1_P$107") (pintype "power_in"))
      (node (ref "P6") (pin "P$108") (pinfunction "P$1_P$108") (pintype "power_in"))
      (node (ref "P6") (pin "P$109") (pinfunction "P$1_P$109") (pintype "power_in"))
      (node (ref "P6") (pin "P$11") (pinfunction "P$1_P$11") (pintype "power_in"))
      (node (ref "P6") (pin "P$110") (pinfunction "P$1_P$110") (pintype "power_in"))
      (node (ref "P6") (pin "P$111") (pinfunction "P$1_P$111") (pintype "power_in"))
      (node (ref "P6") (pin "P$112") (pinfunction "P$1_P$112") (pintype "power_in"))
      (node (ref "P6") (pin "P$113") (pinfunction "P$1_P$113") (pintype "power_in"))
      (node (ref "P6") (pin "P$114") (pinfunction "P$1_P$114") (pintype "power_in"))
      (node (ref "P6") (pin "P$115") (pinfunction "P$1_P$115") (pintype "power_in"))
      (node (ref "P6") (pin "P$116") (pinfunction "P$1_P$116") (pintype "power_in"))
      (node (ref "P6") (pin "P$117") (pinfunction "P$1_P$117") (pintype "power_in"))
      (node (ref "P6") (pin "P$118") (pinfunction "P$1_P$118") (pintype "power_in"))
      (node (ref "P6") (pin "P$119") (pinfunction "P$1_P$119") (pintype "power_in"))
      (node (ref "P6") (pin "P$12") (pinfunction "P$1_P$12") (pintype "power_in"))
      (node (ref "P6") (pin "P$120") (pinfunction "P$1_P$120") (pintype "power_in"))
      (node (ref "P6") (pin "P$121") (pinfunction "P$1_P$121") (pintype "power_in"))
      (node (ref "P6") (pin "P$122") (pinfunction "P$1_P$122") (pintype "power_in"))
      (node (ref "P6") (pin "P$123") (pinfunction "P$1_P$123") (pintype "power_in"))
      (node (ref "P6") (pin "P$124") (pinfunction "P$1_P$124") (pintype "power_in"))
      (node (ref "P6") (pin "P$125") (pinfunction "P$1_P$125") (pintype "power_in"))
      (node (ref "P6") (pin "P$126") (pinfunction "P$1_P$126") (pintype "power_in"))
      (node (ref "P6") (pin "P$127") (pinfunction "P$1_P$127") (pintype "power_in"))
      (node (ref "P6") (pin "P$128") (pinfunction "P$1_P$128") (pintype "power_in"))
      (node (ref "P6") (pin "P$129") (pinfunction "P$1_P$129") (pintype "power_in"))
      (node (ref "P6") (pin "P$13") (pinfunction "P$1_P$13") (pintype "power_in"))
      (node (ref "P6") (pin "P$130") (pinfunction "P$1_P$130") (pintype "power_in"))
      (node (ref "P6") (pin "P$131") (pinfunction "P$1_P$131") (pintype "power_in"))
      (node (ref "P6") (pin "P$132") (pinfunction "P$1_P$132") (pintype "power_in"))
      (node (ref "P6") (pin "P$133") (pinfunction "P$1_P$133") (pintype "power_in"))
      (node (ref "P6") (pin "P$134") (pinfunction "P$1_P$134") (pintype "power_in"))
      (node (ref "P6") (pin "P$135") (pinfunction "P$1_P$135") (pintype "power_in"))
      (node (ref "P6") (pin "P$136") (pinfunction "P$1_P$136") (pintype "power_in"))
      (node (ref "P6") (pin "P$137") (pinfunction "P$1_P$137") (pintype "power_in"))
      (node (ref "P6") (pin "P$138") (pinfunction "P$1_P$138") (pintype "power_in"))
      (node (ref "P6") (pin "P$139") (pinfunction "P$1_P$139") (pintype "power_in"))
      (node (ref "P6") (pin "P$14") (pinfunction "P$1_P$14") (pintype "power_in"))
      (node (ref "P6") (pin "P$140") (pinfunction "P$1_P$140") (pintype "power_in"))
      (node (ref "P6") (pin "P$141") (pinfunction "P$1_P$141") (pintype "power_in"))
      (node (ref "P6") (pin "P$142") (pinfunction "P$1_P$142") (pintype "power_in"))
      (node (ref "P6") (pin "P$143") (pinfunction "P$1_P$143") (pintype "power_in"))
      (node (ref "P6") (pin "P$144") (pinfunction "P$1_P$144") (pintype "power_in"))
      (node (ref "P6") (pin "P$145") (pinfunction "P$1_P$145") (pintype "power_in"))
      (node (ref "P6") (pin "P$146") (pinfunction "P$1_P$146") (pintype "power_in"))
      (node (ref "P6") (pin "P$147") (pinfunction "P$1_P$147") (pintype "power_in"))
      (node (ref "P6") (pin "P$148") (pinfunction "P$1_P$148") (pintype "power_in"))
      (node (ref "P6") (pin "P$149") (pinfunction "P$1_P$149") (pintype "power_in"))
      (node (ref "P6") (pin "P$15") (pinfunction "P$1_P$15") (pintype "power_in"))
      (node (ref "P6") (pin "P$150") (pinfunction "P$1_P$150") (pintype "power_in"))
      (node (ref "P6") (pin "P$151") (pinfunction "P$1_P$151") (pintype "power_in"))
      (node (ref "P6") (pin "P$152") (pinfunction "P$1_P$152") (pintype "power_in"))
      (node (ref "P6") (pin "P$153") (pinfunction "P$1_P$153") (pintype "power_in"))
      (node (ref "P6") (pin "P$154") (pinfunction "P$1_P$154") (pintype "power_in"))
      (node (ref "P6") (pin "P$155") (pinfunction "P$1_P$155") (pintype "power_in"))
      (node (ref "P6") (pin "P$156") (pinfunction "P$1_P$156") (pintype "power_in"))
      (node (ref "P6") (pin "P$157") (pinfunction "P$1_P$157") (pintype "power_in"))
      (node (ref "P6") (pin "P$158") (pinfunction "P$1_P$158") (pintype "power_in"))
      (node (ref "P6") (pin "P$159") (pinfunction "P$1_P$159") (pintype "power_in"))
      (node (ref "P6") (pin "P$16") (pinfunction "P$1_P$16") (pintype "power_in"))
      (node (ref "P6") (pin "P$160") (pinfunction "P$1_P$160") (pintype "power_in"))
      (node (ref "P6") (pin "P$161") (pinfunction "P$1_P$161") (pintype "power_in"))
      (node (ref "P6") (pin "P$162") (pinfunction "P$1_P$162") (pintype "power_in"))
      (node (ref "P6") (pin "P$163") (pinfunction "P$1_P$163") (pintype "power_in"))
      (node (ref "P6") (pin "P$164") (pinfunction "P$1_P$164") (pintype "power_in"))
      (node (ref "P6") (pin "P$165") (pinfunction "P$1_P$165") (pintype "power_in"))
      (node (ref "P6") (pin "P$166") (pinfunction "P$1_P$166") (pintype "power_in"))
      (node (ref "P6") (pin "P$167") (pinfunction "P$1_P$167") (pintype "power_in"))
      (node (ref "P6") (pin "P$168") (pinfunction "P$1_P$168") (pintype "power_in"))
      (node (ref "P6") (pin "P$169") (pinfunction "P$1_P$169") (pintype "power_in"))
      (node (ref "P6") (pin "P$17") (pinfunction "P$1_P$17") (pintype "power_in"))
      (node (ref "P6") (pin "P$170") (pinfunction "P$1_P$170") (pintype "power_in"))
      (node (ref "P6") (pin "P$171") (pinfunction "P$1_P$171") (pintype "power_in"))
      (node (ref "P6") (pin "P$172") (pinfunction "P$1_P$172") (pintype "power_in"))
      (node (ref "P6") (pin "P$173") (pinfunction "P$1_P$173") (pintype "power_in"))
      (node (ref "P6") (pin "P$174") (pinfunction "P$1_P$174") (pintype "power_in"))
      (node (ref "P6") (pin "P$175") (pinfunction "P$1_P$175") (pintype "power_in"))
      (node (ref "P6") (pin "P$176") (pinfunction "P$1_P$176") (pintype "power_in"))
      (node (ref "P6") (pin "P$177") (pinfunction "P$1_P$177") (pintype "power_in"))
      (node (ref "P6") (pin "P$178") (pinfunction "P$1_P$178") (pintype "power_in"))
      (node (ref "P6") (pin "P$179") (pinfunction "P$1_P$179") (pintype "power_in"))
      (node (ref "P6") (pin "P$18") (pinfunction "P$1_P$18") (pintype "power_in"))
      (node (ref "P6") (pin "P$180") (pinfunction "P$1_P$180") (pintype "power_in"))
      (node (ref "P6") (pin "P$181") (pinfunction "P$1_P$181") (pintype "power_in"))
      (node (ref "P6") (pin "P$182") (pinfunction "P$1_P$182") (pintype "power_in"))
      (node (ref "P6") (pin "P$183") (pinfunction "P$1_P$183") (pintype "power_in"))
      (node (ref "P6") (pin "P$184") (pinfunction "P$1_P$184") (pintype "power_in"))
      (node (ref "P6") (pin "P$185") (pinfunction "P$1_P$185") (pintype "power_in"))
      (node (ref "P6") (pin "P$186") (pinfunction "P$1_P$186") (pintype "power_in"))
      (node (ref "P6") (pin "P$187") (pinfunction "P$1_P$187") (pintype "power_in"))
      (node (ref "P6") (pin "P$188") (pinfunction "P$1_P$188") (pintype "power_in"))
      (node (ref "P6") (pin "P$189") (pinfunction "P$1_P$189") (pintype "power_in"))
      (node (ref "P6") (pin "P$19") (pinfunction "P$1_P$19") (pintype "power_in"))
      (node (ref "P6") (pin "P$190") (pinfunction "P$1_P$190") (pintype "power_in"))
      (node (ref "P6") (pin "P$191") (pinfunction "P$1_P$191") (pintype "power_in"))
      (node (ref "P6") (pin "P$192") (pinfunction "P$1_P$192") (pintype "power_in"))
      (node (ref "P6") (pin "P$193") (pinfunction "P$1_P$193") (pintype "power_in"))
      (node (ref "P6") (pin "P$194") (pinfunction "P$1_P$194") (pintype "power_in"))
      (node (ref "P6") (pin "P$195") (pinfunction "P$1_P$195") (pintype "power_in"))
      (node (ref "P6") (pin "P$196") (pinfunction "P$1_P$196") (pintype "power_in"))
      (node (ref "P6") (pin "P$197") (pinfunction "P$1_P$197") (pintype "power_in"))
      (node (ref "P6") (pin "P$198") (pinfunction "P$1_P$198") (pintype "power_in"))
      (node (ref "P6") (pin "P$199") (pinfunction "P$1_P$199") (pintype "power_in"))
      (node (ref "P6") (pin "P$2") (pinfunction "P$1_P$2") (pintype "power_in"))
      (node (ref "P6") (pin "P$20") (pinfunction "P$1_P$20") (pintype "power_in"))
      (node (ref "P6") (pin "P$200") (pinfunction "P$1_P$200") (pintype "power_in"))
      (node (ref "P6") (pin "P$201") (pinfunction "P$1_P$201") (pintype "power_in"))
      (node (ref "P6") (pin "P$202") (pinfunction "P$1_P$202") (pintype "power_in"))
      (node (ref "P6") (pin "P$203") (pinfunction "P$1_P$203") (pintype "power_in"))
      (node (ref "P6") (pin "P$204") (pinfunction "P$1_P$204") (pintype "power_in"))
      (node (ref "P6") (pin "P$205") (pinfunction "P$1_P$205") (pintype "power_in"))
      (node (ref "P6") (pin "P$206") (pinfunction "P$1_P$206") (pintype "power_in"))
      (node (ref "P6") (pin "P$207") (pinfunction "P$1_P$207") (pintype "power_in"))
      (node (ref "P6") (pin "P$208") (pinfunction "P$1_P$208") (pintype "power_in"))
      (node (ref "P6") (pin "P$209") (pinfunction "P$1_P$209") (pintype "power_in"))
      (node (ref "P6") (pin "P$21") (pinfunction "P$1_P$21") (pintype "power_in"))
      (node (ref "P6") (pin "P$210") (pinfunction "P$1_P$210") (pintype "power_in"))
      (node (ref "P6") (pin "P$211") (pinfunction "P$1_P$211") (pintype "power_in"))
      (node (ref "P6") (pin "P$212") (pinfunction "P$1_P$212") (pintype "power_in"))
      (node (ref "P6") (pin "P$213") (pinfunction "P$1_P$213") (pintype "power_in"))
      (node (ref "P6") (pin "P$214") (pinfunction "P$1_P$214") (pintype "power_in"))
      (node (ref "P6") (pin "P$215") (pinfunction "P$1_P$215") (pintype "power_in"))
      (node (ref "P6") (pin "P$216") (pinfunction "P$1_P$216") (pintype "power_in"))
      (node (ref "P6") (pin "P$217") (pinfunction "P$1_P$217") (pintype "power_in"))
      (node (ref "P6") (pin "P$218") (pinfunction "P$1_P$218") (pintype "power_in"))
      (node (ref "P6") (pin "P$219") (pinfunction "P$1_P$219") (pintype "power_in"))
      (node (ref "P6") (pin "P$22") (pinfunction "P$1_P$22") (pintype "power_in"))
      (node (ref "P6") (pin "P$220") (pinfunction "P$1_P$220") (pintype "power_in"))
      (node (ref "P6") (pin "P$221") (pinfunction "P$1_P$221") (pintype "power_in"))
      (node (ref "P6") (pin "P$222") (pinfunction "P$1_P$222") (pintype "power_in"))
      (node (ref "P6") (pin "P$223") (pinfunction "P$1_P$223") (pintype "power_in"))
      (node (ref "P6") (pin "P$224") (pinfunction "P$1_P$224") (pintype "power_in"))
      (node (ref "P6") (pin "P$225") (pinfunction "P$1_P$225") (pintype "power_in"))
      (node (ref "P6") (pin "P$226") (pinfunction "P$1_P$226") (pintype "power_in"))
      (node (ref "P6") (pin "P$227") (pinfunction "P$1_P$227") (pintype "power_in"))
      (node (ref "P6") (pin "P$228") (pinfunction "P$1_P$228") (pintype "power_in"))
      (node (ref "P6") (pin "P$229") (pinfunction "P$1_P$229") (pintype "power_in"))
      (node (ref "P6") (pin "P$23") (pinfunction "P$1_P$23") (pintype "power_in"))
      (node (ref "P6") (pin "P$230") (pinfunction "P$1_P$230") (pintype "power_in"))
      (node (ref "P6") (pin "P$231") (pinfunction "P$1_P$231") (pintype "power_in"))
      (node (ref "P6") (pin "P$232") (pinfunction "P$1_P$232") (pintype "power_in"))
      (node (ref "P6") (pin "P$233") (pinfunction "P$1_P$233") (pintype "power_in"))
      (node (ref "P6") (pin "P$234") (pinfunction "P$1_P$234") (pintype "power_in"))
      (node (ref "P6") (pin "P$235") (pinfunction "P$1_P$235") (pintype "power_in"))
      (node (ref "P6") (pin "P$236") (pinfunction "P$1_P$236") (pintype "power_in"))
      (node (ref "P6") (pin "P$237") (pinfunction "P$1_P$237") (pintype "power_in"))
      (node (ref "P6") (pin "P$238") (pinfunction "P$1_P$238") (pintype "power_in"))
      (node (ref "P6") (pin "P$239") (pinfunction "P$1_P$239") (pintype "power_in"))
      (node (ref "P6") (pin "P$24") (pinfunction "P$1_P$24") (pintype "power_in"))
      (node (ref "P6") (pin "P$240") (pinfunction "P$1_P$240") (pintype "power_in"))
      (node (ref "P6") (pin "P$241") (pinfunction "P$1_P$241") (pintype "power_in"))
      (node (ref "P6") (pin "P$242") (pinfunction "P$1_P$242") (pintype "power_in"))
      (node (ref "P6") (pin "P$243") (pinfunction "P$1_P$243") (pintype "power_in"))
      (node (ref "P6") (pin "P$244") (pinfunction "P$1_P$244") (pintype "power_in"))
      (node (ref "P6") (pin "P$245") (pinfunction "P$1_P$245") (pintype "power_in"))
      (node (ref "P6") (pin "P$246") (pinfunction "P$1_P$246") (pintype "power_in"))
      (node (ref "P6") (pin "P$247") (pinfunction "P$1_P$247") (pintype "power_in"))
      (node (ref "P6") (pin "P$248") (pinfunction "P$1_P$248") (pintype "power_in"))
      (node (ref "P6") (pin "P$249") (pinfunction "P$1_P$249") (pintype "power_in"))
      (node (ref "P6") (pin "P$25") (pinfunction "P$1_P$25") (pintype "power_in"))
      (node (ref "P6") (pin "P$250") (pinfunction "P$1_P$250") (pintype "power_in"))
      (node (ref "P6") (pin "P$251") (pinfunction "P$1_P$251") (pintype "power_in"))
      (node (ref "P6") (pin "P$252") (pinfunction "P$1_P$252") (pintype "power_in"))
      (node (ref "P6") (pin "P$253") (pinfunction "P$1_P$253") (pintype "power_in"))
      (node (ref "P6") (pin "P$254") (pinfunction "P$1_P$254") (pintype "power_in"))
      (node (ref "P6") (pin "P$255") (pinfunction "P$1_P$255") (pintype "power_in"))
      (node (ref "P6") (pin "P$256") (pinfunction "P$1_P$256") (pintype "power_in"))
      (node (ref "P6") (pin "P$257") (pinfunction "P$1_P$257") (pintype "power_in"))
      (node (ref "P6") (pin "P$258") (pinfunction "P$1_P$258") (pintype "power_in"))
      (node (ref "P6") (pin "P$259") (pinfunction "P$1_P$259") (pintype "power_in"))
      (node (ref "P6") (pin "P$26") (pinfunction "P$1_P$26") (pintype "power_in"))
      (node (ref "P6") (pin "P$260") (pinfunction "P$1_P$260") (pintype "power_in"))
      (node (ref "P6") (pin "P$261") (pinfunction "P$1_P$261") (pintype "power_in"))
      (node (ref "P6") (pin "P$262") (pinfunction "P$1_P$262") (pintype "power_in"))
      (node (ref "P6") (pin "P$263") (pinfunction "P$1_P$263") (pintype "power_in"))
      (node (ref "P6") (pin "P$264") (pinfunction "P$1_P$264") (pintype "power_in"))
      (node (ref "P6") (pin "P$265") (pinfunction "P$1_P$265") (pintype "power_in"))
      (node (ref "P6") (pin "P$266") (pinfunction "P$1_P$266") (pintype "power_in"))
      (node (ref "P6") (pin "P$267") (pinfunction "P$1_P$267") (pintype "power_in"))
      (node (ref "P6") (pin "P$268") (pinfunction "P$1_P$268") (pintype "power_in"))
      (node (ref "P6") (pin "P$269") (pinfunction "P$1_P$269") (pintype "power_in"))
      (node (ref "P6") (pin "P$27") (pinfunction "P$1_P$27") (pintype "power_in"))
      (node (ref "P6") (pin "P$270") (pinfunction "P$1_P$270") (pintype "power_in"))
      (node (ref "P6") (pin "P$271") (pinfunction "P$1_P$271") (pintype "power_in"))
      (node (ref "P6") (pin "P$272") (pinfunction "P$1_P$272") (pintype "power_in"))
      (node (ref "P6") (pin "P$273") (pinfunction "P$1_P$273") (pintype "power_in"))
      (node (ref "P6") (pin "P$274") (pinfunction "P$1_P$274") (pintype "power_in"))
      (node (ref "P6") (pin "P$275") (pinfunction "P$1_P$275") (pintype "power_in"))
      (node (ref "P6") (pin "P$276") (pinfunction "P$1_P$276") (pintype "power_in"))
      (node (ref "P6") (pin "P$277") (pinfunction "P$1_P$277") (pintype "power_in"))
      (node (ref "P6") (pin "P$278") (pinfunction "P$1_P$278") (pintype "power_in"))
      (node (ref "P6") (pin "P$279") (pinfunction "P$1_P$279") (pintype "power_in"))
      (node (ref "P6") (pin "P$28") (pinfunction "P$1_P$28") (pintype "power_in"))
      (node (ref "P6") (pin "P$280") (pinfunction "P$1_P$280") (pintype "power_in"))
      (node (ref "P6") (pin "P$281") (pinfunction "P$1_P$281") (pintype "power_in"))
      (node (ref "P6") (pin "P$282") (pinfunction "P$1_P$282") (pintype "power_in"))
      (node (ref "P6") (pin "P$283") (pinfunction "P$1_P$283") (pintype "power_in"))
      (node (ref "P6") (pin "P$284") (pinfunction "P$1_P$284") (pintype "power_in"))
      (node (ref "P6") (pin "P$285") (pinfunction "P$1_P$285") (pintype "power_in"))
      (node (ref "P6") (pin "P$286") (pinfunction "P$1_P$286") (pintype "power_in"))
      (node (ref "P6") (pin "P$287") (pinfunction "P$1_P$287") (pintype "power_in"))
      (node (ref "P6") (pin "P$288") (pinfunction "P$1_P$288") (pintype "power_in"))
      (node (ref "P6") (pin "P$289") (pinfunction "P$1_P$289") (pintype "power_in"))
      (node (ref "P6") (pin "P$29") (pinfunction "P$1_P$29") (pintype "power_in"))
      (node (ref "P6") (pin "P$290") (pinfunction "P$1_P$290") (pintype "power_in"))
      (node (ref "P6") (pin "P$291") (pinfunction "P$1_P$291") (pintype "power_in"))
      (node (ref "P6") (pin "P$292") (pinfunction "P$1_P$292") (pintype "power_in"))
      (node (ref "P6") (pin "P$293") (pinfunction "P$1_P$293") (pintype "power_in"))
      (node (ref "P6") (pin "P$294") (pinfunction "P$1_P$294") (pintype "power_in"))
      (node (ref "P6") (pin "P$295") (pinfunction "P$1_P$295") (pintype "power_in"))
      (node (ref "P6") (pin "P$296") (pinfunction "P$1_P$296") (pintype "power_in"))
      (node (ref "P6") (pin "P$297") (pinfunction "P$1_P$297") (pintype "power_in"))
      (node (ref "P6") (pin "P$298") (pinfunction "P$1_P$298") (pintype "power_in"))
      (node (ref "P6") (pin "P$299") (pinfunction "P$1_P$299") (pintype "power_in"))
      (node (ref "P6") (pin "P$3") (pinfunction "P$1_P$3") (pintype "power_in"))
      (node (ref "P6") (pin "P$30") (pinfunction "P$1_P$30") (pintype "power_in"))
      (node (ref "P6") (pin "P$300") (pinfunction "P$1_P$300") (pintype "power_in"))
      (node (ref "P6") (pin "P$301") (pinfunction "P$1_P$301") (pintype "power_in"))
      (node (ref "P6") (pin "P$302") (pinfunction "P$1_P$302") (pintype "power_in"))
      (node (ref "P6") (pin "P$303") (pinfunction "P$1_P$303") (pintype "power_in"))
      (node (ref "P6") (pin "P$304") (pinfunction "P$1_P$304") (pintype "power_in"))
      (node (ref "P6") (pin "P$305") (pinfunction "P$1_P$305") (pintype "power_in"))
      (node (ref "P6") (pin "P$306") (pinfunction "P$1_P$306") (pintype "power_in"))
      (node (ref "P6") (pin "P$307") (pinfunction "P$1_P$307") (pintype "power_in"))
      (node (ref "P6") (pin "P$308") (pinfunction "P$1_P$308") (pintype "power_in"))
      (node (ref "P6") (pin "P$309") (pinfunction "P$1_P$309") (pintype "power_in"))
      (node (ref "P6") (pin "P$31") (pinfunction "P$1_P$31") (pintype "power_in"))
      (node (ref "P6") (pin "P$310") (pinfunction "P$1_P$310") (pintype "power_in"))
      (node (ref "P6") (pin "P$311") (pinfunction "P$1_P$311") (pintype "power_in"))
      (node (ref "P6") (pin "P$312") (pinfunction "P$1_P$312") (pintype "power_in"))
      (node (ref "P6") (pin "P$313") (pinfunction "P$1_P$313") (pintype "power_in"))
      (node (ref "P6") (pin "P$314") (pinfunction "P$1_P$314") (pintype "power_in"))
      (node (ref "P6") (pin "P$315") (pinfunction "P$1_P$315") (pintype "power_in"))
      (node (ref "P6") (pin "P$316") (pinfunction "P$1_P$316") (pintype "power_in"))
      (node (ref "P6") (pin "P$317") (pinfunction "P$1_P$317") (pintype "power_in"))
      (node (ref "P6") (pin "P$318") (pinfunction "P$1_P$318") (pintype "power_in"))
      (node (ref "P6") (pin "P$319") (pinfunction "P$1_P$319") (pintype "power_in"))
      (node (ref "P6") (pin "P$32") (pinfunction "P$1_P$32") (pintype "power_in"))
      (node (ref "P6") (pin "P$320") (pinfunction "P$1_P$320") (pintype "power_in"))
      (node (ref "P6") (pin "P$321") (pinfunction "P$1_P$321") (pintype "power_in"))
      (node (ref "P6") (pin "P$322") (pinfunction "P$1_P$322") (pintype "power_in"))
      (node (ref "P6") (pin "P$323") (pinfunction "P$1_P$323") (pintype "power_in"))
      (node (ref "P6") (pin "P$324") (pinfunction "P$1_P$324") (pintype "power_in"))
      (node (ref "P6") (pin "P$325") (pinfunction "P$1_P$325") (pintype "power_in"))
      (node (ref "P6") (pin "P$326") (pinfunction "P$1_P$326") (pintype "power_in"))
      (node (ref "P6") (pin "P$327") (pinfunction "P$1_P$327") (pintype "power_in"))
      (node (ref "P6") (pin "P$328") (pinfunction "P$1_P$328") (pintype "power_in"))
      (node (ref "P6") (pin "P$329") (pinfunction "P$1_P$329") (pintype "power_in"))
      (node (ref "P6") (pin "P$33") (pinfunction "P$1_P$33") (pintype "power_in"))
      (node (ref "P6") (pin "P$330") (pinfunction "P$1_P$330") (pintype "power_in"))
      (node (ref "P6") (pin "P$331") (pinfunction "P$1_P$331") (pintype "power_in"))
      (node (ref "P6") (pin "P$332") (pinfunction "P$1_P$332") (pintype "power_in"))
      (node (ref "P6") (pin "P$333") (pinfunction "P$1_P$333") (pintype "power_in"))
      (node (ref "P6") (pin "P$334") (pinfunction "P$1_P$334") (pintype "power_in"))
      (node (ref "P6") (pin "P$335") (pinfunction "P$1_P$335") (pintype "power_in"))
      (node (ref "P6") (pin "P$336") (pinfunction "P$1_P$336") (pintype "power_in"))
      (node (ref "P6") (pin "P$337") (pinfunction "P$1_P$337") (pintype "power_in"))
      (node (ref "P6") (pin "P$338") (pinfunction "P$1_P$338") (pintype "power_in"))
      (node (ref "P6") (pin "P$339") (pinfunction "P$1_P$339") (pintype "power_in"))
      (node (ref "P6") (pin "P$34") (pinfunction "P$1_P$34") (pintype "power_in"))
      (node (ref "P6") (pin "P$340") (pinfunction "P$1_P$340") (pintype "power_in"))
      (node (ref "P6") (pin "P$341") (pinfunction "P$1_P$341") (pintype "power_in"))
      (node (ref "P6") (pin "P$342") (pinfunction "P$1_P$342") (pintype "power_in"))
      (node (ref "P6") (pin "P$343") (pinfunction "P$1_P$343") (pintype "power_in"))
      (node (ref "P6") (pin "P$344") (pinfunction "P$1_P$344") (pintype "power_in"))
      (node (ref "P6") (pin "P$345") (pinfunction "P$1_P$345") (pintype "power_in"))
      (node (ref "P6") (pin "P$346") (pinfunction "P$1_P$346") (pintype "power_in"))
      (node (ref "P6") (pin "P$347") (pinfunction "P$1_P$347") (pintype "power_in"))
      (node (ref "P6") (pin "P$348") (pinfunction "P$1_P$348") (pintype "power_in"))
      (node (ref "P6") (pin "P$349") (pinfunction "P$1_P$349") (pintype "power_in"))
      (node (ref "P6") (pin "P$35") (pinfunction "P$1_P$35") (pintype "power_in"))
      (node (ref "P6") (pin "P$350") (pinfunction "P$1_P$350") (pintype "power_in"))
      (node (ref "P6") (pin "P$351") (pinfunction "P$1_P$351") (pintype "power_in"))
      (node (ref "P6") (pin "P$352") (pinfunction "P$1_P$352") (pintype "power_in"))
      (node (ref "P6") (pin "P$353") (pinfunction "P$1_P$353") (pintype "power_in"))
      (node (ref "P6") (pin "P$354") (pinfunction "P$1_P$354") (pintype "power_in"))
      (node (ref "P6") (pin "P$355") (pinfunction "P$1_P$355") (pintype "power_in"))
      (node (ref "P6") (pin "P$356") (pinfunction "P$1_P$356") (pintype "power_in"))
      (node (ref "P6") (pin "P$357") (pinfunction "P$1_P$357") (pintype "power_in"))
      (node (ref "P6") (pin "P$358") (pinfunction "P$1_P$358") (pintype "power_in"))
      (node (ref "P6") (pin "P$359") (pinfunction "P$1_P$359") (pintype "power_in"))
      (node (ref "P6") (pin "P$36") (pinfunction "P$1_P$36") (pintype "power_in"))
      (node (ref "P6") (pin "P$360") (pinfunction "P$1_P$360") (pintype "power_in"))
      (node (ref "P6") (pin "P$361") (pinfunction "P$1_P$361") (pintype "power_in"))
      (node (ref "P6") (pin "P$362") (pinfunction "P$1_P$362") (pintype "power_in"))
      (node (ref "P6") (pin "P$363") (pinfunction "P$1_P$363") (pintype "power_in"))
      (node (ref "P6") (pin "P$364") (pinfunction "P$1_P$364") (pintype "power_in"))
      (node (ref "P6") (pin "P$365") (pinfunction "P$1_P$365") (pintype "power_in"))
      (node (ref "P6") (pin "P$366") (pinfunction "P$1_P$366") (pintype "power_in"))
      (node (ref "P6") (pin "P$367") (pinfunction "P$1_P$367") (pintype "power_in"))
      (node (ref "P6") (pin "P$368") (pinfunction "P$1_P$368") (pintype "power_in"))
      (node (ref "P6") (pin "P$369") (pinfunction "P$1_P$369") (pintype "power_in"))
      (node (ref "P6") (pin "P$37") (pinfunction "P$1_P$37") (pintype "power_in"))
      (node (ref "P6") (pin "P$370") (pinfunction "P$1_P$370") (pintype "power_in"))
      (node (ref "P6") (pin "P$371") (pinfunction "P$1_P$371") (pintype "power_in"))
      (node (ref "P6") (pin "P$372") (pinfunction "P$1_P$372") (pintype "power_in"))
      (node (ref "P6") (pin "P$373") (pinfunction "P$1_P$373") (pintype "power_in"))
      (node (ref "P6") (pin "P$374") (pinfunction "P$1_P$374") (pintype "power_in"))
      (node (ref "P6") (pin "P$375") (pinfunction "P$1_P$375") (pintype "power_in"))
      (node (ref "P6") (pin "P$376") (pinfunction "P$1_P$376") (pintype "power_in"))
      (node (ref "P6") (pin "P$377") (pinfunction "P$1_P$377") (pintype "power_in"))
      (node (ref "P6") (pin "P$378") (pinfunction "P$1_P$378") (pintype "power_in"))
      (node (ref "P6") (pin "P$379") (pinfunction "P$1_P$379") (pintype "power_in"))
      (node (ref "P6") (pin "P$38") (pinfunction "P$1_P$38") (pintype "power_in"))
      (node (ref "P6") (pin "P$380") (pinfunction "P$1_P$380") (pintype "power_in"))
      (node (ref "P6") (pin "P$381") (pinfunction "P$1_P$381") (pintype "power_in"))
      (node (ref "P6") (pin "P$382") (pinfunction "P$1_P$382") (pintype "power_in"))
      (node (ref "P6") (pin "P$383") (pinfunction "P$1_P$383") (pintype "power_in"))
      (node (ref "P6") (pin "P$384") (pinfunction "P$1_P$384") (pintype "power_in"))
      (node (ref "P6") (pin "P$385") (pinfunction "P$1_P$385") (pintype "power_in"))
      (node (ref "P6") (pin "P$386") (pinfunction "P$1_P$386") (pintype "power_in"))
      (node (ref "P6") (pin "P$387") (pinfunction "P$1_P$387") (pintype "power_in"))
      (node (ref "P6") (pin "P$388") (pinfunction "P$1_P$388") (pintype "power_in"))
      (node (ref "P6") (pin "P$389") (pinfunction "P$1_P$389") (pintype "power_in"))
      (node (ref "P6") (pin "P$39") (pinfunction "P$1_P$39") (pintype "power_in"))
      (node (ref "P6") (pin "P$390") (pinfunction "P$1_P$390") (pintype "power_in"))
      (node (ref "P6") (pin "P$391") (pinfunction "P$1_P$391") (pintype "power_in"))
      (node (ref "P6") (pin "P$392") (pinfunction "P$1_P$392") (pintype "power_in"))
      (node (ref "P6") (pin "P$393") (pinfunction "P$1_P$393") (pintype "power_in"))
      (node (ref "P6") (pin "P$394") (pinfunction "P$1_P$394") (pintype "power_in"))
      (node (ref "P6") (pin "P$395") (pinfunction "P$1_P$395") (pintype "power_in"))
      (node (ref "P6") (pin "P$396") (pinfunction "P$1_P$396") (pintype "power_in"))
      (node (ref "P6") (pin "P$397") (pinfunction "P$1_P$397") (pintype "power_in"))
      (node (ref "P6") (pin "P$398") (pinfunction "P$1_P$398") (pintype "power_in"))
      (node (ref "P6") (pin "P$399") (pinfunction "P$1_P$399") (pintype "power_in"))
      (node (ref "P6") (pin "P$4") (pinfunction "P$1_P$4") (pintype "power_in"))
      (node (ref "P6") (pin "P$40") (pinfunction "P$1_P$40") (pintype "power_in"))
      (node (ref "P6") (pin "P$400") (pinfunction "P$1_P$400") (pintype "power_in"))
      (node (ref "P6") (pin "P$401") (pinfunction "P$1_P$401") (pintype "power_in"))
      (node (ref "P6") (pin "P$402") (pinfunction "P$1_P$402") (pintype "power_in"))
      (node (ref "P6") (pin "P$403") (pinfunction "P$1_P$403") (pintype "power_in"))
      (node (ref "P6") (pin "P$404") (pinfunction "P$1_P$404") (pintype "power_in"))
      (node (ref "P6") (pin "P$405") (pinfunction "P$1_P$405") (pintype "power_in"))
      (node (ref "P6") (pin "P$406") (pinfunction "P$1_P$406") (pintype "power_in"))
      (node (ref "P6") (pin "P$407") (pinfunction "P$1_P$407") (pintype "power_in"))
      (node (ref "P6") (pin "P$408") (pinfunction "P$1_P$408") (pintype "power_in"))
      (node (ref "P6") (pin "P$409") (pinfunction "P$1_P$409") (pintype "power_in"))
      (node (ref "P6") (pin "P$41") (pinfunction "P$1_P$41") (pintype "power_in"))
      (node (ref "P6") (pin "P$410") (pinfunction "P$1_P$410") (pintype "power_in"))
      (node (ref "P6") (pin "P$411") (pinfunction "P$1_P$411") (pintype "power_in"))
      (node (ref "P6") (pin "P$412") (pinfunction "P$1_P$412") (pintype "power_in"))
      (node (ref "P6") (pin "P$413") (pinfunction "P$1_P$413") (pintype "power_in"))
      (node (ref "P6") (pin "P$414") (pinfunction "P$1_P$414") (pintype "power_in"))
      (node (ref "P6") (pin "P$415") (pinfunction "P$1_P$415") (pintype "power_in"))
      (node (ref "P6") (pin "P$416") (pinfunction "P$1_P$416") (pintype "power_in"))
      (node (ref "P6") (pin "P$417") (pinfunction "P$1_P$417") (pintype "power_in"))
      (node (ref "P6") (pin "P$418") (pinfunction "P$1_P$418") (pintype "power_in"))
      (node (ref "P6") (pin "P$419") (pinfunction "P$1_P$419") (pintype "power_in"))
      (node (ref "P6") (pin "P$42") (pinfunction "P$1_P$42") (pintype "power_in"))
      (node (ref "P6") (pin "P$420") (pinfunction "P$1_P$420") (pintype "power_in"))
      (node (ref "P6") (pin "P$421") (pinfunction "P$1_P$421") (pintype "power_in"))
      (node (ref "P6") (pin "P$422") (pinfunction "P$1_P$422") (pintype "power_in"))
      (node (ref "P6") (pin "P$423") (pinfunction "P$1_P$423") (pintype "power_in"))
      (node (ref "P6") (pin "P$424") (pinfunction "P$1_P$424") (pintype "power_in"))
      (node (ref "P6") (pin "P$425") (pinfunction "P$1_P$425") (pintype "power_in"))
      (node (ref "P6") (pin "P$426") (pinfunction "P$1_P$426") (pintype "power_in"))
      (node (ref "P6") (pin "P$427") (pinfunction "P$1_P$427") (pintype "power_in"))
      (node (ref "P6") (pin "P$428") (pinfunction "P$1_P$428") (pintype "power_in"))
      (node (ref "P6") (pin "P$429") (pinfunction "P$1_P$429") (pintype "power_in"))
      (node (ref "P6") (pin "P$43") (pinfunction "P$1_P$43") (pintype "power_in"))
      (node (ref "P6") (pin "P$430") (pinfunction "P$1_P$430") (pintype "power_in"))
      (node (ref "P6") (pin "P$431") (pinfunction "P$1_P$431") (pintype "power_in"))
      (node (ref "P6") (pin "P$432") (pinfunction "P$1_P$432") (pintype "power_in"))
      (node (ref "P6") (pin "P$433") (pinfunction "P$1_P$433") (pintype "power_in"))
      (node (ref "P6") (pin "P$434") (pinfunction "P$1_P$434") (pintype "power_in"))
      (node (ref "P6") (pin "P$435") (pinfunction "P$1_P$435") (pintype "power_in"))
      (node (ref "P6") (pin "P$436") (pinfunction "P$1_P$436") (pintype "power_in"))
      (node (ref "P6") (pin "P$437") (pinfunction "P$1_P$437") (pintype "power_in"))
      (node (ref "P6") (pin "P$438") (pinfunction "P$1_P$438") (pintype "power_in"))
      (node (ref "P6") (pin "P$439") (pinfunction "P$1_P$439") (pintype "power_in"))
      (node (ref "P6") (pin "P$44") (pinfunction "P$1_P$44") (pintype "power_in"))
      (node (ref "P6") (pin "P$440") (pinfunction "P$1_P$440") (pintype "power_in"))
      (node (ref "P6") (pin "P$441") (pinfunction "P$1_P$441") (pintype "power_in"))
      (node (ref "P6") (pin "P$442") (pinfunction "P$1_P$442") (pintype "power_in"))
      (node (ref "P6") (pin "P$443") (pinfunction "P$1_P$443") (pintype "power_in"))
      (node (ref "P6") (pin "P$444") (pinfunction "P$1_P$444") (pintype "power_in"))
      (node (ref "P6") (pin "P$445") (pinfunction "P$1_P$445") (pintype "power_in"))
      (node (ref "P6") (pin "P$446") (pinfunction "P$1_P$446") (pintype "power_in"))
      (node (ref "P6") (pin "P$447") (pinfunction "P$1_P$447") (pintype "power_in"))
      (node (ref "P6") (pin "P$448") (pinfunction "P$1_P$448") (pintype "power_in"))
      (node (ref "P6") (pin "P$449") (pinfunction "P$1_P$449") (pintype "power_in"))
      (node (ref "P6") (pin "P$45") (pinfunction "P$1_P$45") (pintype "power_in"))
      (node (ref "P6") (pin "P$450") (pinfunction "P$1_P$450") (pintype "power_in"))
      (node (ref "P6") (pin "P$451") (pinfunction "P$1_P$451") (pintype "power_in"))
      (node (ref "P6") (pin "P$452") (pinfunction "P$1_P$452") (pintype "power_in"))
      (node (ref "P6") (pin "P$453") (pinfunction "P$1_P$453") (pintype "power_in"))
      (node (ref "P6") (pin "P$454") (pinfunction "P$1_P$454") (pintype "power_in"))
      (node (ref "P6") (pin "P$455") (pinfunction "P$1_P$455") (pintype "power_in"))
      (node (ref "P6") (pin "P$456") (pinfunction "P$1_P$456") (pintype "power_in"))
      (node (ref "P6") (pin "P$457") (pinfunction "P$1_P$457") (pintype "power_in"))
      (node (ref "P6") (pin "P$458") (pinfunction "P$1_P$458") (pintype "power_in"))
      (node (ref "P6") (pin "P$459") (pinfunction "P$1_P$459") (pintype "power_in"))
      (node (ref "P6") (pin "P$46") (pinfunction "P$1_P$46") (pintype "power_in"))
      (node (ref "P6") (pin "P$460") (pinfunction "P$1_P$460") (pintype "power_in"))
      (node (ref "P6") (pin "P$461") (pinfunction "P$1_P$461") (pintype "power_in"))
      (node (ref "P6") (pin "P$462") (pinfunction "P$1_P$462") (pintype "power_in"))
      (node (ref "P6") (pin "P$463") (pinfunction "P$1_P$463") (pintype "power_in"))
      (node (ref "P6") (pin "P$464") (pinfunction "P$1_P$464") (pintype "power_in"))
      (node (ref "P6") (pin "P$465") (pinfunction "P$1_P$465") (pintype "power_in"))
      (node (ref "P6") (pin "P$466") (pinfunction "P$1_P$466") (pintype "power_in"))
      (node (ref "P6") (pin "P$467") (pinfunction "P$1_P$467") (pintype "power_in"))
      (node (ref "P6") (pin "P$468") (pinfunction "P$1_P$468") (pintype "power_in"))
      (node (ref "P6") (pin "P$469") (pinfunction "P$1_P$469") (pintype "power_in"))
      (node (ref "P6") (pin "P$47") (pinfunction "P$1_P$47") (pintype "power_in"))
      (node (ref "P6") (pin "P$470") (pinfunction "P$1_P$470") (pintype "power_in"))
      (node (ref "P6") (pin "P$471") (pinfunction "P$1_P$471") (pintype "power_in"))
      (node (ref "P6") (pin "P$472") (pinfunction "P$1_P$472") (pintype "power_in"))
      (node (ref "P6") (pin "P$473") (pinfunction "P$1_P$473") (pintype "power_in"))
      (node (ref "P6") (pin "P$474") (pinfunction "P$1_P$474") (pintype "power_in"))
      (node (ref "P6") (pin "P$475") (pinfunction "P$1_P$475") (pintype "power_in"))
      (node (ref "P6") (pin "P$476") (pinfunction "P$1_P$476") (pintype "power_in"))
      (node (ref "P6") (pin "P$477") (pinfunction "P$1_P$477") (pintype "power_in"))
      (node (ref "P6") (pin "P$478") (pinfunction "P$1_P$478") (pintype "power_in"))
      (node (ref "P6") (pin "P$479") (pinfunction "P$1_P$479") (pintype "power_in"))
      (node (ref "P6") (pin "P$48") (pinfunction "P$1_P$48") (pintype "power_in"))
      (node (ref "P6") (pin "P$480") (pinfunction "P$1_P$480") (pintype "power_in"))
      (node (ref "P6") (pin "P$481") (pinfunction "P$1_P$481") (pintype "power_in"))
      (node (ref "P6") (pin "P$482") (pinfunction "P$1_P$482") (pintype "power_in"))
      (node (ref "P6") (pin "P$483") (pinfunction "P$1_P$483") (pintype "power_in"))
      (node (ref "P6") (pin "P$484") (pinfunction "P$1_P$484") (pintype "power_in"))
      (node (ref "P6") (pin "P$485") (pinfunction "P$1_P$485") (pintype "power_in"))
      (node (ref "P6") (pin "P$486") (pinfunction "P$1_P$486") (pintype "power_in"))
      (node (ref "P6") (pin "P$487") (pinfunction "P$1_P$487") (pintype "power_in"))
      (node (ref "P6") (pin "P$488") (pinfunction "P$1_P$488") (pintype "power_in"))
      (node (ref "P6") (pin "P$489") (pinfunction "P$1_P$489") (pintype "power_in"))
      (node (ref "P6") (pin "P$49") (pinfunction "P$1_P$49") (pintype "power_in"))
      (node (ref "P6") (pin "P$490") (pinfunction "P$1_P$490") (pintype "power_in"))
      (node (ref "P6") (pin "P$491") (pinfunction "P$1_P$491") (pintype "power_in"))
      (node (ref "P6") (pin "P$492") (pinfunction "P$1_P$492") (pintype "power_in"))
      (node (ref "P6") (pin "P$493") (pinfunction "P$1_P$493") (pintype "power_in"))
      (node (ref "P6") (pin "P$494") (pinfunction "P$1_P$494") (pintype "power_in"))
      (node (ref "P6") (pin "P$495") (pinfunction "P$1_P$495") (pintype "power_in"))
      (node (ref "P6") (pin "P$496") (pinfunction "P$1_P$496") (pintype "power_in"))
      (node (ref "P6") (pin "P$497") (pinfunction "P$1_P$497") (pintype "power_in"))
      (node (ref "P6") (pin "P$498") (pinfunction "P$1_P$498") (pintype "power_in"))
      (node (ref "P6") (pin "P$499") (pinfunction "P$1_P$499") (pintype "power_in"))
      (node (ref "P6") (pin "P$5") (pinfunction "P$1_P$5") (pintype "power_in"))
      (node (ref "P6") (pin "P$50") (pinfunction "P$1_P$50") (pintype "power_in"))
      (node (ref "P6") (pin "P$500") (pinfunction "P$1_P$500") (pintype "power_in"))
      (node (ref "P6") (pin "P$501") (pinfunction "P$1_P$501") (pintype "power_in"))
      (node (ref "P6") (pin "P$502") (pinfunction "P$1_P$502") (pintype "power_in"))
      (node (ref "P6") (pin "P$503") (pinfunction "P$1_P$503") (pintype "power_in"))
      (node (ref "P6") (pin "P$504") (pinfunction "P$1_P$504") (pintype "power_in"))
      (node (ref "P6") (pin "P$505") (pinfunction "P$1_P$505") (pintype "power_in"))
      (node (ref "P6") (pin "P$506") (pinfunction "P$1_P$506") (pintype "power_in"))
      (node (ref "P6") (pin "P$507") (pinfunction "P$1_P$507") (pintype "power_in"))
      (node (ref "P6") (pin "P$508") (pinfunction "P$1_P$508") (pintype "power_in"))
      (node (ref "P6") (pin "P$509") (pinfunction "P$1_P$509") (pintype "power_in"))
      (node (ref "P6") (pin "P$51") (pinfunction "P$1_P$51") (pintype "power_in"))
      (node (ref "P6") (pin "P$510") (pinfunction "P$1_P$510") (pintype "power_in"))
      (node (ref "P6") (pin "P$511") (pinfunction "P$1_P$511") (pintype "power_in"))
      (node (ref "P6") (pin "P$512") (pinfunction "P$1_P$512") (pintype "power_in"))
      (node (ref "P6") (pin "P$513") (pinfunction "P$1_P$513") (pintype "power_in"))
      (node (ref "P6") (pin "P$514") (pinfunction "P$1_P$514") (pintype "power_in"))
      (node (ref "P6") (pin "P$515") (pinfunction "P$1_P$515") (pintype "power_in"))
      (node (ref "P6") (pin "P$516") (pinfunction "P$1_P$516") (pintype "power_in"))
      (node (ref "P6") (pin "P$517") (pinfunction "P$1_P$517") (pintype "power_in"))
      (node (ref "P6") (pin "P$518") (pinfunction "P$1_P$518") (pintype "power_in"))
      (node (ref "P6") (pin "P$519") (pinfunction "P$1_P$519") (pintype "power_in"))
      (node (ref "P6") (pin "P$52") (pinfunction "P$1_P$52") (pintype "power_in"))
      (node (ref "P6") (pin "P$520") (pinfunction "P$1_P$520") (pintype "power_in"))
      (node (ref "P6") (pin "P$521") (pinfunction "P$1_P$521") (pintype "power_in"))
      (node (ref "P6") (pin "P$522") (pinfunction "P$1_P$522") (pintype "power_in"))
      (node (ref "P6") (pin "P$523") (pinfunction "P$1_P$523") (pintype "power_in"))
      (node (ref "P6") (pin "P$524") (pinfunction "P$1_P$524") (pintype "power_in"))
      (node (ref "P6") (pin "P$525") (pinfunction "P$1_P$525") (pintype "power_in"))
      (node (ref "P6") (pin "P$526") (pinfunction "P$1_P$526") (pintype "power_in"))
      (node (ref "P6") (pin "P$527") (pinfunction "P$1_P$527") (pintype "power_in"))
      (node (ref "P6") (pin "P$528") (pinfunction "P$1_P$528") (pintype "power_in"))
      (node (ref "P6") (pin "P$529") (pinfunction "P$1_P$529") (pintype "power_in"))
      (node (ref "P6") (pin "P$53") (pinfunction "P$1_P$53") (pintype "power_in"))
      (node (ref "P6") (pin "P$530") (pinfunction "P$1_P$530") (pintype "power_in"))
      (node (ref "P6") (pin "P$531") (pinfunction "P$1_P$531") (pintype "power_in"))
      (node (ref "P6") (pin "P$532") (pinfunction "P$1_P$532") (pintype "power_in"))
      (node (ref "P6") (pin "P$533") (pinfunction "P$1_P$533") (pintype "power_in"))
      (node (ref "P6") (pin "P$534") (pinfunction "P$1_P$534") (pintype "power_in"))
      (node (ref "P6") (pin "P$535") (pinfunction "P$1_P$535") (pintype "power_in"))
      (node (ref "P6") (pin "P$536") (pinfunction "P$1_P$536") (pintype "power_in"))
      (node (ref "P6") (pin "P$537") (pinfunction "P$1_P$537") (pintype "power_in"))
      (node (ref "P6") (pin "P$538") (pinfunction "P$1_P$538") (pintype "power_in"))
      (node (ref "P6") (pin "P$539") (pinfunction "P$1_P$539") (pintype "power_in"))
      (node (ref "P6") (pin "P$54") (pinfunction "P$1_P$54") (pintype "power_in"))
      (node (ref "P6") (pin "P$540") (pinfunction "P$1_P$540") (pintype "power_in"))
      (node (ref "P6") (pin "P$541") (pinfunction "P$1_P$541") (pintype "power_in"))
      (node (ref "P6") (pin "P$542") (pinfunction "P$1_P$542") (pintype "power_in"))
      (node (ref "P6") (pin "P$543") (pinfunction "P$1_P$543") (pintype "power_in"))
      (node (ref "P6") (pin "P$544") (pinfunction "P$1_P$544") (pintype "power_in"))
      (node (ref "P6") (pin "P$545") (pinfunction "P$1_P$545") (pintype "power_in"))
      (node (ref "P6") (pin "P$546") (pinfunction "P$1_P$546") (pintype "power_in"))
      (node (ref "P6") (pin "P$547") (pinfunction "P$1_P$547") (pintype "power_in"))
      (node (ref "P6") (pin "P$548") (pinfunction "P$1_P$548") (pintype "power_in"))
      (node (ref "P6") (pin "P$549") (pinfunction "P$1_P$549") (pintype "power_in"))
      (node (ref "P6") (pin "P$55") (pinfunction "P$1_P$55") (pintype "power_in"))
      (node (ref "P6") (pin "P$550") (pinfunction "P$1_P$550") (pintype "power_in"))
      (node (ref "P6") (pin "P$551") (pinfunction "P$1_P$551") (pintype "power_in"))
      (node (ref "P6") (pin "P$552") (pinfunction "P$1_P$552") (pintype "power_in"))
      (node (ref "P6") (pin "P$553") (pinfunction "P$1_P$553") (pintype "power_in"))
      (node (ref "P6") (pin "P$554") (pinfunction "P$1_P$554") (pintype "power_in"))
      (node (ref "P6") (pin "P$555") (pinfunction "P$1_P$555") (pintype "power_in"))
      (node (ref "P6") (pin "P$556") (pinfunction "P$1_P$556") (pintype "power_in"))
      (node (ref "P6") (pin "P$557") (pinfunction "P$1_P$557") (pintype "power_in"))
      (node (ref "P6") (pin "P$558") (pinfunction "P$1_P$558") (pintype "power_in"))
      (node (ref "P6") (pin "P$559") (pinfunction "P$1_P$559") (pintype "power_in"))
      (node (ref "P6") (pin "P$56") (pinfunction "P$1_P$56") (pintype "power_in"))
      (node (ref "P6") (pin "P$560") (pinfunction "P$1_P$560") (pintype "power_in"))
      (node (ref "P6") (pin "P$561") (pinfunction "P$1_P$561") (pintype "power_in"))
      (node (ref "P6") (pin "P$562") (pinfunction "P$1_P$562") (pintype "power_in"))
      (node (ref "P6") (pin "P$563") (pinfunction "P$1_P$563") (pintype "power_in"))
      (node (ref "P6") (pin "P$564") (pinfunction "P$1_P$564") (pintype "power_in"))
      (node (ref "P6") (pin "P$565") (pinfunction "P$1_P$565") (pintype "power_in"))
      (node (ref "P6") (pin "P$566") (pinfunction "P$1_P$566") (pintype "power_in"))
      (node (ref "P6") (pin "P$567") (pinfunction "P$1_P$567") (pintype "power_in"))
      (node (ref "P6") (pin "P$568") (pinfunction "P$1_P$568") (pintype "power_in"))
      (node (ref "P6") (pin "P$569") (pinfunction "P$1_P$569") (pintype "power_in"))
      (node (ref "P6") (pin "P$57") (pinfunction "P$1_P$57") (pintype "power_in"))
      (node (ref "P6") (pin "P$570") (pinfunction "P$1_P$570") (pintype "power_in"))
      (node (ref "P6") (pin "P$571") (pinfunction "P$1_P$571") (pintype "power_in"))
      (node (ref "P6") (pin "P$572") (pinfunction "P$1_P$572") (pintype "power_in"))
      (node (ref "P6") (pin "P$573") (pinfunction "P$1_P$573") (pintype "power_in"))
      (node (ref "P6") (pin "P$574") (pinfunction "P$1_P$574") (pintype "power_in"))
      (node (ref "P6") (pin "P$575") (pinfunction "P$1_P$575") (pintype "power_in"))
      (node (ref "P6") (pin "P$576") (pinfunction "P$1_P$576") (pintype "power_in"))
      (node (ref "P6") (pin "P$577") (pinfunction "P$1_P$577") (pintype "power_in"))
      (node (ref "P6") (pin "P$578") (pinfunction "P$1_P$578") (pintype "power_in"))
      (node (ref "P6") (pin "P$579") (pinfunction "P$1_P$579") (pintype "power_in"))
      (node (ref "P6") (pin "P$58") (pinfunction "P$1_P$58") (pintype "power_in"))
      (node (ref "P6") (pin "P$580") (pinfunction "P$1_P$580") (pintype "power_in"))
      (node (ref "P6") (pin "P$581") (pinfunction "P$1_P$581") (pintype "power_in"))
      (node (ref "P6") (pin "P$582") (pinfunction "P$1_P$582") (pintype "power_in"))
      (node (ref "P6") (pin "P$583") (pinfunction "P$1_P$583") (pintype "power_in"))
      (node (ref "P6") (pin "P$584") (pinfunction "P$1_P$584") (pintype "power_in"))
      (node (ref "P6") (pin "P$585") (pinfunction "P$1_P$585") (pintype "power_in"))
      (node (ref "P6") (pin "P$586") (pinfunction "P$1_P$586") (pintype "power_in"))
      (node (ref "P6") (pin "P$587") (pinfunction "P$1_P$587") (pintype "power_in"))
      (node (ref "P6") (pin "P$588") (pinfunction "P$1_P$588") (pintype "power_in"))
      (node (ref "P6") (pin "P$589") (pinfunction "P$1_P$589") (pintype "power_in"))
      (node (ref "P6") (pin "P$59") (pinfunction "P$1_P$59") (pintype "power_in"))
      (node (ref "P6") (pin "P$590") (pinfunction "P$1_P$590") (pintype "power_in"))
      (node (ref "P6") (pin "P$591") (pinfunction "P$1_P$591") (pintype "power_in"))
      (node (ref "P6") (pin "P$592") (pinfunction "P$1_P$592") (pintype "power_in"))
      (node (ref "P6") (pin "P$593") (pinfunction "P$1_P$593") (pintype "power_in"))
      (node (ref "P6") (pin "P$594") (pinfunction "P$1_P$594") (pintype "power_in"))
      (node (ref "P6") (pin "P$595") (pinfunction "P$1_P$595") (pintype "power_in"))
      (node (ref "P6") (pin "P$596") (pinfunction "P$1_P$596") (pintype "power_in"))
      (node (ref "P6") (pin "P$597") (pinfunction "P$1_P$597") (pintype "power_in"))
      (node (ref "P6") (pin "P$598") (pinfunction "P$1_P$598") (pintype "power_in"))
      (node (ref "P6") (pin "P$599") (pinfunction "P$1_P$599") (pintype "power_in"))
      (node (ref "P6") (pin "P$6") (pinfunction "P$1_P$6") (pintype "power_in"))
      (node (ref "P6") (pin "P$60") (pinfunction "P$1_P$60") (pintype "power_in"))
      (node (ref "P6") (pin "P$600") (pinfunction "P$1_P$600") (pintype "power_in"))
      (node (ref "P6") (pin "P$601") (pinfunction "P$1_P$601") (pintype "power_in"))
      (node (ref "P6") (pin "P$602") (pinfunction "P$1_P$602") (pintype "power_in"))
      (node (ref "P6") (pin "P$603") (pinfunction "P$1_P$603") (pintype "power_in"))
      (node (ref "P6") (pin "P$604") (pinfunction "P$1_P$604") (pintype "power_in"))
      (node (ref "P6") (pin "P$605") (pinfunction "P$1_P$605") (pintype "power_in"))
      (node (ref "P6") (pin "P$606") (pinfunction "P$1_P$606") (pintype "power_in"))
      (node (ref "P6") (pin "P$607") (pinfunction "P$1_P$607") (pintype "power_in"))
      (node (ref "P6") (pin "P$608") (pinfunction "P$1_P$608") (pintype "power_in"))
      (node (ref "P6") (pin "P$609") (pinfunction "P$1_P$609") (pintype "power_in"))
      (node (ref "P6") (pin "P$61") (pinfunction "P$1_P$61") (pintype "power_in"))
      (node (ref "P6") (pin "P$610") (pinfunction "P$1_P$610") (pintype "power_in"))
      (node (ref "P6") (pin "P$611") (pinfunction "P$1_P$611") (pintype "power_in"))
      (node (ref "P6") (pin "P$612") (pinfunction "P$1_P$612") (pintype "power_in"))
      (node (ref "P6") (pin "P$613") (pinfunction "P$1_P$613") (pintype "power_in"))
      (node (ref "P6") (pin "P$614") (pinfunction "P$1_P$614") (pintype "power_in"))
      (node (ref "P6") (pin "P$615") (pinfunction "P$1_P$615") (pintype "power_in"))
      (node (ref "P6") (pin "P$616") (pinfunction "P$1_P$616") (pintype "power_in"))
      (node (ref "P6") (pin "P$617") (pinfunction "P$1_P$617") (pintype "power_in"))
      (node (ref "P6") (pin "P$618") (pinfunction "P$1_P$618") (pintype "power_in"))
      (node (ref "P6") (pin "P$619") (pinfunction "P$1_P$619") (pintype "power_in"))
      (node (ref "P6") (pin "P$62") (pinfunction "P$1_P$62") (pintype "power_in"))
      (node (ref "P6") (pin "P$620") (pinfunction "P$1_P$620") (pintype "power_in"))
      (node (ref "P6") (pin "P$621") (pinfunction "P$1_P$621") (pintype "power_in"))
      (node (ref "P6") (pin "P$622") (pinfunction "P$1_P$622") (pintype "power_in"))
      (node (ref "P6") (pin "P$623") (pinfunction "P$1_P$623") (pintype "power_in"))
      (node (ref "P6") (pin "P$624") (pinfunction "P$1_P$624") (pintype "power_in"))
      (node (ref "P6") (pin "P$625") (pinfunction "P$1_P$625") (pintype "power_in"))
      (node (ref "P6") (pin "P$626") (pinfunction "P$1_P$626") (pintype "power_in"))
      (node (ref "P6") (pin "P$627") (pinfunction "P$1_P$627") (pintype "power_in"))
      (node (ref "P6") (pin "P$628") (pinfunction "P$1_P$628") (pintype "power_in"))
      (node (ref "P6") (pin "P$629") (pinfunction "P$1_P$629") (pintype "power_in"))
      (node (ref "P6") (pin "P$63") (pinfunction "P$1_P$63") (pintype "power_in"))
      (node (ref "P6") (pin "P$630") (pinfunction "P$1_P$630") (pintype "power_in"))
      (node (ref "P6") (pin "P$631") (pinfunction "P$1_P$631") (pintype "power_in"))
      (node (ref "P6") (pin "P$632") (pinfunction "P$1_P$632") (pintype "power_in"))
      (node (ref "P6") (pin "P$633") (pinfunction "P$1_P$633") (pintype "power_in"))
      (node (ref "P6") (pin "P$634") (pinfunction "P$1_P$634") (pintype "power_in"))
      (node (ref "P6") (pin "P$635") (pinfunction "P$1_P$635") (pintype "power_in"))
      (node (ref "P6") (pin "P$636") (pinfunction "P$1_P$636") (pintype "power_in"))
      (node (ref "P6") (pin "P$637") (pinfunction "P$1_P$637") (pintype "power_in"))
      (node (ref "P6") (pin "P$638") (pinfunction "P$1_P$638") (pintype "power_in"))
      (node (ref "P6") (pin "P$639") (pinfunction "P$1_P$639") (pintype "power_in"))
      (node (ref "P6") (pin "P$64") (pinfunction "P$1_P$64") (pintype "power_in"))
      (node (ref "P6") (pin "P$640") (pinfunction "P$1_P$640") (pintype "power_in"))
      (node (ref "P6") (pin "P$641") (pinfunction "P$1_P$641") (pintype "power_in"))
      (node (ref "P6") (pin "P$642") (pinfunction "P$1_P$642") (pintype "power_in"))
      (node (ref "P6") (pin "P$643") (pinfunction "P$1_P$643") (pintype "power_in"))
      (node (ref "P6") (pin "P$644") (pinfunction "P$1_P$644") (pintype "power_in"))
      (node (ref "P6") (pin "P$645") (pinfunction "P$1_P$645") (pintype "power_in"))
      (node (ref "P6") (pin "P$646") (pinfunction "P$1_P$646") (pintype "power_in"))
      (node (ref "P6") (pin "P$647") (pinfunction "P$1_P$647") (pintype "power_in"))
      (node (ref "P6") (pin "P$648") (pinfunction "P$1_P$648") (pintype "power_in"))
      (node (ref "P6") (pin "P$649") (pinfunction "P$1_P$649") (pintype "power_in"))
      (node (ref "P6") (pin "P$65") (pinfunction "P$1_P$65") (pintype "power_in"))
      (node (ref "P6") (pin "P$650") (pinfunction "P$1_P$650") (pintype "power_in"))
      (node (ref "P6") (pin "P$651") (pinfunction "P$1_P$651") (pintype "power_in"))
      (node (ref "P6") (pin "P$652") (pinfunction "P$1_P$652") (pintype "power_in"))
      (node (ref "P6") (pin "P$653") (pinfunction "P$1_P$653") (pintype "power_in"))
      (node (ref "P6") (pin "P$654") (pinfunction "P$1_P$654") (pintype "power_in"))
      (node (ref "P6") (pin "P$655") (pinfunction "P$1_P$655") (pintype "power_in"))
      (node (ref "P6") (pin "P$656") (pinfunction "P$1_P$656") (pintype "power_in"))
      (node (ref "P6") (pin "P$657") (pinfunction "P$1_P$657") (pintype "power_in"))
      (node (ref "P6") (pin "P$658") (pinfunction "P$1_P$658") (pintype "power_in"))
      (node (ref "P6") (pin "P$659") (pinfunction "P$1_P$659") (pintype "power_in"))
      (node (ref "P6") (pin "P$66") (pinfunction "P$1_P$66") (pintype "power_in"))
      (node (ref "P6") (pin "P$660") (pinfunction "P$1_P$660") (pintype "power_in"))
      (node (ref "P6") (pin "P$661") (pinfunction "P$1_P$661") (pintype "power_in"))
      (node (ref "P6") (pin "P$662") (pinfunction "P$1_P$662") (pintype "power_in"))
      (node (ref "P6") (pin "P$663") (pinfunction "P$1_P$663") (pintype "power_in"))
      (node (ref "P6") (pin "P$664") (pinfunction "P$1_P$664") (pintype "power_in"))
      (node (ref "P6") (pin "P$665") (pinfunction "P$1_P$665") (pintype "power_in"))
      (node (ref "P6") (pin "P$666") (pinfunction "P$1_P$666") (pintype "power_in"))
      (node (ref "P6") (pin "P$667") (pinfunction "P$1_P$667") (pintype "power_in"))
      (node (ref "P6") (pin "P$668") (pinfunction "P$1_P$668") (pintype "power_in"))
      (node (ref "P6") (pin "P$669") (pinfunction "P$1_P$669") (pintype "power_in"))
      (node (ref "P6") (pin "P$67") (pinfunction "P$1_P$67") (pintype "power_in"))
      (node (ref "P6") (pin "P$670") (pinfunction "P$1_P$670") (pintype "power_in"))
      (node (ref "P6") (pin "P$671") (pinfunction "P$1_P$671") (pintype "power_in"))
      (node (ref "P6") (pin "P$672") (pinfunction "P$1_P$672") (pintype "power_in"))
      (node (ref "P6") (pin "P$673") (pinfunction "P$1_P$673") (pintype "power_in"))
      (node (ref "P6") (pin "P$674") (pinfunction "P$1_P$674") (pintype "power_in"))
      (node (ref "P6") (pin "P$675") (pinfunction "P$1_P$675") (pintype "power_in"))
      (node (ref "P6") (pin "P$676") (pinfunction "P$1_P$676") (pintype "power_in"))
      (node (ref "P6") (pin "P$677") (pinfunction "P$1_P$677") (pintype "power_in"))
      (node (ref "P6") (pin "P$678") (pinfunction "P$1_P$678") (pintype "power_in"))
      (node (ref "P6") (pin "P$679") (pinfunction "P$1_P$679") (pintype "power_in"))
      (node (ref "P6") (pin "P$68") (pinfunction "P$1_P$68") (pintype "power_in"))
      (node (ref "P6") (pin "P$680") (pinfunction "P$1_P$680") (pintype "power_in"))
      (node (ref "P6") (pin "P$681") (pinfunction "P$1_P$681") (pintype "power_in"))
      (node (ref "P6") (pin "P$682") (pinfunction "P$1_P$682") (pintype "power_in"))
      (node (ref "P6") (pin "P$683") (pinfunction "P$1_P$683") (pintype "power_in"))
      (node (ref "P6") (pin "P$684") (pinfunction "P$1_P$684") (pintype "power_in"))
      (node (ref "P6") (pin "P$685") (pinfunction "P$1_P$685") (pintype "power_in"))
      (node (ref "P6") (pin "P$686") (pinfunction "P$1_P$686") (pintype "power_in"))
      (node (ref "P6") (pin "P$687") (pinfunction "P$1_P$687") (pintype "power_in"))
      (node (ref "P6") (pin "P$688") (pinfunction "P$1_P$688") (pintype "power_in"))
      (node (ref "P6") (pin "P$689") (pinfunction "P$1_P$689") (pintype "power_in"))
      (node (ref "P6") (pin "P$69") (pinfunction "P$1_P$69") (pintype "power_in"))
      (node (ref "P6") (pin "P$690") (pinfunction "P$1_P$690") (pintype "power_in"))
      (node (ref "P6") (pin "P$691") (pinfunction "P$1_P$691") (pintype "power_in"))
      (node (ref "P6") (pin "P$692") (pinfunction "P$1_P$692") (pintype "power_in"))
      (node (ref "P6") (pin "P$693") (pinfunction "P$1_P$693") (pintype "power_in"))
      (node (ref "P6") (pin "P$694") (pinfunction "P$1_P$694") (pintype "power_in"))
      (node (ref "P6") (pin "P$695") (pinfunction "P$1_P$695") (pintype "power_in"))
      (node (ref "P6") (pin "P$696") (pinfunction "P$1_P$696") (pintype "power_in"))
      (node (ref "P6") (pin "P$697") (pinfunction "P$1_P$697") (pintype "power_in"))
      (node (ref "P6") (pin "P$698") (pinfunction "P$1_P$698") (pintype "power_in"))
      (node (ref "P6") (pin "P$699") (pinfunction "P$1_P$699") (pintype "power_in"))
      (node (ref "P6") (pin "P$7") (pinfunction "P$1_P$7") (pintype "power_in"))
      (node (ref "P6") (pin "P$70") (pinfunction "P$1_P$70") (pintype "power_in"))
      (node (ref "P6") (pin "P$700") (pinfunction "P$1_P$700") (pintype "power_in"))
      (node (ref "P6") (pin "P$701") (pinfunction "P$1_P$701") (pintype "power_in"))
      (node (ref "P6") (pin "P$702") (pinfunction "P$1_P$702") (pintype "power_in"))
      (node (ref "P6") (pin "P$703") (pinfunction "P$1_P$703") (pintype "power_in"))
      (node (ref "P6") (pin "P$704") (pinfunction "P$1_P$704") (pintype "power_in"))
      (node (ref "P6") (pin "P$705") (pinfunction "P$1_P$705") (pintype "power_in"))
      (node (ref "P6") (pin "P$706") (pinfunction "P$1_P$706") (pintype "power_in"))
      (node (ref "P6") (pin "P$707") (pinfunction "P$1_P$707") (pintype "power_in"))
      (node (ref "P6") (pin "P$708") (pinfunction "P$1_P$708") (pintype "power_in"))
      (node (ref "P6") (pin "P$709") (pinfunction "P$1_P$709") (pintype "power_in"))
      (node (ref "P6") (pin "P$71") (pinfunction "P$1_P$71") (pintype "power_in"))
      (node (ref "P6") (pin "P$710") (pinfunction "P$1_P$710") (pintype "power_in"))
      (node (ref "P6") (pin "P$711") (pinfunction "P$1_P$711") (pintype "power_in"))
      (node (ref "P6") (pin "P$712") (pinfunction "P$1_P$712") (pintype "power_in"))
      (node (ref "P6") (pin "P$713") (pinfunction "P$1_P$713") (pintype "power_in"))
      (node (ref "P6") (pin "P$714") (pinfunction "P$1_P$714") (pintype "power_in"))
      (node (ref "P6") (pin "P$715") (pinfunction "P$1_P$715") (pintype "power_in"))
      (node (ref "P6") (pin "P$716") (pinfunction "P$1_P$716") (pintype "power_in"))
      (node (ref "P6") (pin "P$717") (pinfunction "P$1_P$717") (pintype "power_in"))
      (node (ref "P6") (pin "P$718") (pinfunction "P$1_P$718") (pintype "power_in"))
      (node (ref "P6") (pin "P$719") (pinfunction "P$1_P$719") (pintype "power_in"))
      (node (ref "P6") (pin "P$72") (pinfunction "P$1_P$72") (pintype "power_in"))
      (node (ref "P6") (pin "P$720") (pinfunction "P$1_P$720") (pintype "power_in"))
      (node (ref "P6") (pin "P$73") (pinfunction "P$1_P$73") (pintype "power_in"))
      (node (ref "P6") (pin "P$74") (pinfunction "P$1_P$74") (pintype "power_in"))
      (node (ref "P6") (pin "P$75") (pinfunction "P$1_P$75") (pintype "power_in"))
      (node (ref "P6") (pin "P$76") (pinfunction "P$1_P$76") (pintype "power_in"))
      (node (ref "P6") (pin "P$77") (pinfunction "P$1_P$77") (pintype "power_in"))
      (node (ref "P6") (pin "P$78") (pinfunction "P$1_P$78") (pintype "power_in"))
      (node (ref "P6") (pin "P$79") (pinfunction "P$1_P$79") (pintype "power_in"))
      (node (ref "P6") (pin "P$8") (pinfunction "P$1_P$8") (pintype "power_in"))
      (node (ref "P6") (pin "P$80") (pinfunction "P$1_P$80") (pintype "power_in"))
      (node (ref "P6") (pin "P$81") (pinfunction "P$1_P$81") (pintype "power_in"))
      (node (ref "P6") (pin "P$82") (pinfunction "P$1_P$82") (pintype "power_in"))
      (node (ref "P6") (pin "P$83") (pinfunction "P$1_P$83") (pintype "power_in"))
      (node (ref "P6") (pin "P$84") (pinfunction "P$1_P$84") (pintype "power_in"))
      (node (ref "P6") (pin "P$85") (pinfunction "P$1_P$85") (pintype "power_in"))
      (node (ref "P6") (pin "P$86") (pinfunction "P$1_P$86") (pintype "power_in"))
      (node (ref "P6") (pin "P$87") (pinfunction "P$1_P$87") (pintype "power_in"))
      (node (ref "P6") (pin "P$88") (pinfunction "P$1_P$88") (pintype "power_in"))
      (node (ref "P6") (pin "P$89") (pinfunction "P$1_P$89") (pintype "power_in"))
      (node (ref "P6") (pin "P$9") (pinfunction "P$1_P$9") (pintype "power_in"))
      (node (ref "P6") (pin "P$90") (pinfunction "P$1_P$90") (pintype "power_in"))
      (node (ref "P6") (pin "P$91") (pinfunction "P$1_P$91") (pintype "power_in"))
      (node (ref "P6") (pin "P$92") (pinfunction "P$1_P$92") (pintype "power_in"))
      (node (ref "P6") (pin "P$93") (pinfunction "P$1_P$93") (pintype "power_in"))
      (node (ref "P6") (pin "P$94") (pinfunction "P$1_P$94") (pintype "power_in"))
      (node (ref "P6") (pin "P$95") (pinfunction "P$1_P$95") (pintype "power_in"))
      (node (ref "P6") (pin "P$96") (pinfunction "P$1_P$96") (pintype "power_in"))
      (node (ref "P6") (pin "P$97") (pinfunction "P$1_P$97") (pintype "power_in"))
      (node (ref "P6") (pin "P$98") (pinfunction "P$1_P$98") (pintype "power_in"))
      (node (ref "P6") (pin "P$99") (pinfunction "P$1_P$99") (pintype "power_in"))
    )
    (net (code "8") (name "/P7") (class "Default")
      (node (ref "JP1") (pin "P$8") (pinfunction "7_P$8") (pintype "bidirectional"))
      (node (ref "P7") (pin "P$1") (pinfunction "P$1_P$1") (pintype "power_in"))
      (node (ref "P7") (pin "P$10") (pinfunction "P$1_P$10") (pintype "power_in"))
      (node (ref "P7") (pin "P$100") (pinfunction "P$1_P$100") (pintype "power_in"))
      (node (ref "P7") (pin "P$101") (pinfunction "P$1_P$101") (pintype "power_in"))
      (node (ref "P7") (pin "P$102") (pinfunction "P$1_P$102") (pintype "power_in"))
      (node (ref "P7") (pin "P$103") (pinfunction "P$1_P$103") (pintype "power_in"))
      (node (ref "P7") (pin "P$104") (pinfunction "P$1_P$104") (pintype "power_in"))
      (node (ref "P7") (pin "P$105") (pinfunction "P$1_P$105") (pintype "power_in"))
      (node (ref "P7") (pin "P$106") (pinfunction "P$1_P$106") (pintype "power_in"))
      (node (ref "P7") (pin "P$107") (pinfunction "P$1_P$107") (pintype "power_in"))
      (node (ref "P7") (pin "P$108") (pinfunction "P$1_P$108") (pintype "power_in"))
      (node (ref "P7") (pin "P$109") (pinfunction "P$1_P$109") (pintype "power_in"))
      (node (ref "P7") (pin "P$11") (pinfunction "P$1_P$11") (pintype "power_in"))
      (node (ref "P7") (pin "P$110") (pinfunction "P$1_P$110") (pintype "power_in"))
      (node (ref "P7") (pin "P$111") (pinfunction "P$1_P$111") (pintype "power_in"))
      (node (ref "P7") (pin "P$112") (pinfunction "P$1_P$112") (pintype "power_in"))
      (node (ref "P7") (pin "P$113") (pinfunction "P$1_P$113") (pintype "power_in"))
      (node (ref "P7") (pin "P$114") (pinfunction "P$1_P$114") (pintype "power_in"))
      (node (ref "P7") (pin "P$115") (pinfunction "P$1_P$115") (pintype "power_in"))
      (node (ref "P7") (pin "P$116") (pinfunction "P$1_P$116") (pintype "power_in"))
      (node (ref "P7") (pin "P$117") (pinfunction "P$1_P$117") (pintype "power_in"))
      (node (ref "P7") (pin "P$118") (pinfunction "P$1_P$118") (pintype "power_in"))
      (node (ref "P7") (pin "P$119") (pinfunction "P$1_P$119") (pintype "power_in"))
      (node (ref "P7") (pin "P$12") (pinfunction "P$1_P$12") (pintype "power_in"))
      (node (ref "P7") (pin "P$120") (pinfunction "P$1_P$120") (pintype "power_in"))
      (node (ref "P7") (pin "P$121") (pinfunction "P$1_P$121") (pintype "power_in"))
      (node (ref "P7") (pin "P$122") (pinfunction "P$1_P$122") (pintype "power_in"))
      (node (ref "P7") (pin "P$123") (pinfunction "P$1_P$123") (pintype "power_in"))
      (node (ref "P7") (pin "P$124") (pinfunction "P$1_P$124") (pintype "power_in"))
      (node (ref "P7") (pin "P$125") (pinfunction "P$1_P$125") (pintype "power_in"))
      (node (ref "P7") (pin "P$126") (pinfunction "P$1_P$126") (pintype "power_in"))
      (node (ref "P7") (pin "P$127") (pinfunction "P$1_P$127") (pintype "power_in"))
      (node (ref "P7") (pin "P$128") (pinfunction "P$1_P$128") (pintype "power_in"))
      (node (ref "P7") (pin "P$129") (pinfunction "P$1_P$129") (pintype "power_in"))
      (node (ref "P7") (pin "P$13") (pinfunction "P$1_P$13") (pintype "power_in"))
      (node (ref "P7") (pin "P$130") (pinfunction "P$1_P$130") (pintype "power_in"))
      (node (ref "P7") (pin "P$131") (pinfunction "P$1_P$131") (pintype "power_in"))
      (node (ref "P7") (pin "P$132") (pinfunction "P$1_P$132") (pintype "power_in"))
      (node (ref "P7") (pin "P$133") (pinfunction "P$1_P$133") (pintype "power_in"))
      (node (ref "P7") (pin "P$134") (pinfunction "P$1_P$134") (pintype "power_in"))
      (node (ref "P7") (pin "P$135") (pinfunction "P$1_P$135") (pintype "power_in"))
      (node (ref "P7") (pin "P$136") (pinfunction "P$1_P$136") (pintype "power_in"))
      (node (ref "P7") (pin "P$137") (pinfunction "P$1_P$137") (pintype "power_in"))
      (node (ref "P7") (pin "P$138") (pinfunction "P$1_P$138") (pintype "power_in"))
      (node (ref "P7") (pin "P$139") (pinfunction "P$1_P$139") (pintype "power_in"))
      (node (ref "P7") (pin "P$14") (pinfunction "P$1_P$14") (pintype "power_in"))
      (node (ref "P7") (pin "P$140") (pinfunction "P$1_P$140") (pintype "power_in"))
      (node (ref "P7") (pin "P$141") (pinfunction "P$1_P$141") (pintype "power_in"))
      (node (ref "P7") (pin "P$142") (pinfunction "P$1_P$142") (pintype "power_in"))
      (node (ref "P7") (pin "P$143") (pinfunction "P$1_P$143") (pintype "power_in"))
      (node (ref "P7") (pin "P$144") (pinfunction "P$1_P$144") (pintype "power_in"))
      (node (ref "P7") (pin "P$145") (pinfunction "P$1_P$145") (pintype "power_in"))
      (node (ref "P7") (pin "P$146") (pinfunction "P$1_P$146") (pintype "power_in"))
      (node (ref "P7") (pin "P$147") (pinfunction "P$1_P$147") (pintype "power_in"))
      (node (ref "P7") (pin "P$148") (pinfunction "P$1_P$148") (pintype "power_in"))
      (node (ref "P7") (pin "P$149") (pinfunction "P$1_P$149") (pintype "power_in"))
      (node (ref "P7") (pin "P$15") (pinfunction "P$1_P$15") (pintype "power_in"))
      (node (ref "P7") (pin "P$150") (pinfunction "P$1_P$150") (pintype "power_in"))
      (node (ref "P7") (pin "P$151") (pinfunction "P$1_P$151") (pintype "power_in"))
      (node (ref "P7") (pin "P$152") (pinfunction "P$1_P$152") (pintype "power_in"))
      (node (ref "P7") (pin "P$153") (pinfunction "P$1_P$153") (pintype "power_in"))
      (node (ref "P7") (pin "P$154") (pinfunction "P$1_P$154") (pintype "power_in"))
      (node (ref "P7") (pin "P$155") (pinfunction "P$1_P$155") (pintype "power_in"))
      (node (ref "P7") (pin "P$156") (pinfunction "P$1_P$156") (pintype "power_in"))
      (node (ref "P7") (pin "P$157") (pinfunction "P$1_P$157") (pintype "power_in"))
      (node (ref "P7") (pin "P$158") (pinfunction "P$1_P$158") (pintype "power_in"))
      (node (ref "P7") (pin "P$159") (pinfunction "P$1_P$159") (pintype "power_in"))
      (node (ref "P7") (pin "P$16") (pinfunction "P$1_P$16") (pintype "power_in"))
      (node (ref "P7") (pin "P$160") (pinfunction "P$1_P$160") (pintype "power_in"))
      (node (ref "P7") (pin "P$161") (pinfunction "P$1_P$161") (pintype "power_in"))
      (node (ref "P7") (pin "P$162") (pinfunction "P$1_P$162") (pintype "power_in"))
      (node (ref "P7") (pin "P$163") (pinfunction "P$1_P$163") (pintype "power_in"))
      (node (ref "P7") (pin "P$164") (pinfunction "P$1_P$164") (pintype "power_in"))
      (node (ref "P7") (pin "P$165") (pinfunction "P$1_P$165") (pintype "power_in"))
      (node (ref "P7") (pin "P$166") (pinfunction "P$1_P$166") (pintype "power_in"))
      (node (ref "P7") (pin "P$167") (pinfunction "P$1_P$167") (pintype "power_in"))
      (node (ref "P7") (pin "P$168") (pinfunction "P$1_P$168") (pintype "power_in"))
      (node (ref "P7") (pin "P$169") (pinfunction "P$1_P$169") (pintype "power_in"))
      (node (ref "P7") (pin "P$17") (pinfunction "P$1_P$17") (pintype "power_in"))
      (node (ref "P7") (pin "P$170") (pinfunction "P$1_P$170") (pintype "power_in"))
      (node (ref "P7") (pin "P$171") (pinfunction "P$1_P$171") (pintype "power_in"))
      (node (ref "P7") (pin "P$172") (pinfunction "P$1_P$172") (pintype "power_in"))
      (node (ref "P7") (pin "P$173") (pinfunction "P$1_P$173") (pintype "power_in"))
      (node (ref "P7") (pin "P$174") (pinfunction "P$1_P$174") (pintype "power_in"))
      (node (ref "P7") (pin "P$175") (pinfunction "P$1_P$175") (pintype "power_in"))
      (node (ref "P7") (pin "P$176") (pinfunction "P$1_P$176") (pintype "power_in"))
      (node (ref "P7") (pin "P$177") (pinfunction "P$1_P$177") (pintype "power_in"))
      (node (ref "P7") (pin "P$178") (pinfunction "P$1_P$178") (pintype "power_in"))
      (node (ref "P7") (pin "P$179") (pinfunction "P$1_P$179") (pintype "power_in"))
      (node (ref "P7") (pin "P$18") (pinfunction "P$1_P$18") (pintype "power_in"))
      (node (ref "P7") (pin "P$180") (pinfunction "P$1_P$180") (pintype "power_in"))
      (node (ref "P7") (pin "P$181") (pinfunction "P$1_P$181") (pintype "power_in"))
      (node (ref "P7") (pin "P$182") (pinfunction "P$1_P$182") (pintype "power_in"))
      (node (ref "P7") (pin "P$183") (pinfunction "P$1_P$183") (pintype "power_in"))
      (node (ref "P7") (pin "P$184") (pinfunction "P$1_P$184") (pintype "power_in"))
      (node (ref "P7") (pin "P$185") (pinfunction "P$1_P$185") (pintype "power_in"))
      (node (ref "P7") (pin "P$186") (pinfunction "P$1_P$186") (pintype "power_in"))
      (node (ref "P7") (pin "P$187") (pinfunction "P$1_P$187") (pintype "power_in"))
      (node (ref "P7") (pin "P$188") (pinfunction "P$1_P$188") (pintype "power_in"))
      (node (ref "P7") (pin "P$189") (pinfunction "P$1_P$189") (pintype "power_in"))
      (node (ref "P7") (pin "P$19") (pinfunction "P$1_P$19") (pintype "power_in"))
      (node (ref "P7") (pin "P$190") (pinfunction "P$1_P$190") (pintype "power_in"))
      (node (ref "P7") (pin "P$191") (pinfunction "P$1_P$191") (pintype "power_in"))
      (node (ref "P7") (pin "P$192") (pinfunction "P$1_P$192") (pintype "power_in"))
      (node (ref "P7") (pin "P$193") (pinfunction "P$1_P$193") (pintype "power_in"))
      (node (ref "P7") (pin "P$194") (pinfunction "P$1_P$194") (pintype "power_in"))
      (node (ref "P7") (pin "P$195") (pinfunction "P$1_P$195") (pintype "power_in"))
      (node (ref "P7") (pin "P$196") (pinfunction "P$1_P$196") (pintype "power_in"))
      (node (ref "P7") (pin "P$197") (pinfunction "P$1_P$197") (pintype "power_in"))
      (node (ref "P7") (pin "P$198") (pinfunction "P$1_P$198") (pintype "power_in"))
      (node (ref "P7") (pin "P$199") (pinfunction "P$1_P$199") (pintype "power_in"))
      (node (ref "P7") (pin "P$2") (pinfunction "P$1_P$2") (pintype "power_in"))
      (node (ref "P7") (pin "P$20") (pinfunction "P$1_P$20") (pintype "power_in"))
      (node (ref "P7") (pin "P$200") (pinfunction "P$1_P$200") (pintype "power_in"))
      (node (ref "P7") (pin "P$201") (pinfunction "P$1_P$201") (pintype "power_in"))
      (node (ref "P7") (pin "P$202") (pinfunction "P$1_P$202") (pintype "power_in"))
      (node (ref "P7") (pin "P$203") (pinfunction "P$1_P$203") (pintype "power_in"))
      (node (ref "P7") (pin "P$204") (pinfunction "P$1_P$204") (pintype "power_in"))
      (node (ref "P7") (pin "P$205") (pinfunction "P$1_P$205") (pintype "power_in"))
      (node (ref "P7") (pin "P$206") (pinfunction "P$1_P$206") (pintype "power_in"))
      (node (ref "P7") (pin "P$207") (pinfunction "P$1_P$207") (pintype "power_in"))
      (node (ref "P7") (pin "P$208") (pinfunction "P$1_P$208") (pintype "power_in"))
      (node (ref "P7") (pin "P$209") (pinfunction "P$1_P$209") (pintype "power_in"))
      (node (ref "P7") (pin "P$21") (pinfunction "P$1_P$21") (pintype "power_in"))
      (node (ref "P7") (pin "P$210") (pinfunction "P$1_P$210") (pintype "power_in"))
      (node (ref "P7") (pin "P$211") (pinfunction "P$1_P$211") (pintype "power_in"))
      (node (ref "P7") (pin "P$212") (pinfunction "P$1_P$212") (pintype "power_in"))
      (node (ref "P7") (pin "P$213") (pinfunction "P$1_P$213") (pintype "power_in"))
      (node (ref "P7") (pin "P$214") (pinfunction "P$1_P$214") (pintype "power_in"))
      (node (ref "P7") (pin "P$215") (pinfunction "P$1_P$215") (pintype "power_in"))
      (node (ref "P7") (pin "P$216") (pinfunction "P$1_P$216") (pintype "power_in"))
      (node (ref "P7") (pin "P$217") (pinfunction "P$1_P$217") (pintype "power_in"))
      (node (ref "P7") (pin "P$218") (pinfunction "P$1_P$218") (pintype "power_in"))
      (node (ref "P7") (pin "P$219") (pinfunction "P$1_P$219") (pintype "power_in"))
      (node (ref "P7") (pin "P$22") (pinfunction "P$1_P$22") (pintype "power_in"))
      (node (ref "P7") (pin "P$220") (pinfunction "P$1_P$220") (pintype "power_in"))
      (node (ref "P7") (pin "P$221") (pinfunction "P$1_P$221") (pintype "power_in"))
      (node (ref "P7") (pin "P$222") (pinfunction "P$1_P$222") (pintype "power_in"))
      (node (ref "P7") (pin "P$223") (pinfunction "P$1_P$223") (pintype "power_in"))
      (node (ref "P7") (pin "P$224") (pinfunction "P$1_P$224") (pintype "power_in"))
      (node (ref "P7") (pin "P$225") (pinfunction "P$1_P$225") (pintype "power_in"))
      (node (ref "P7") (pin "P$226") (pinfunction "P$1_P$226") (pintype "power_in"))
      (node (ref "P7") (pin "P$227") (pinfunction "P$1_P$227") (pintype "power_in"))
      (node (ref "P7") (pin "P$228") (pinfunction "P$1_P$228") (pintype "power_in"))
      (node (ref "P7") (pin "P$229") (pinfunction "P$1_P$229") (pintype "power_in"))
      (node (ref "P7") (pin "P$23") (pinfunction "P$1_P$23") (pintype "power_in"))
      (node (ref "P7") (pin "P$230") (pinfunction "P$1_P$230") (pintype "power_in"))
      (node (ref "P7") (pin "P$231") (pinfunction "P$1_P$231") (pintype "power_in"))
      (node (ref "P7") (pin "P$232") (pinfunction "P$1_P$232") (pintype "power_in"))
      (node (ref "P7") (pin "P$233") (pinfunction "P$1_P$233") (pintype "power_in"))
      (node (ref "P7") (pin "P$234") (pinfunction "P$1_P$234") (pintype "power_in"))
      (node (ref "P7") (pin "P$235") (pinfunction "P$1_P$235") (pintype "power_in"))
      (node (ref "P7") (pin "P$236") (pinfunction "P$1_P$236") (pintype "power_in"))
      (node (ref "P7") (pin "P$237") (pinfunction "P$1_P$237") (pintype "power_in"))
      (node (ref "P7") (pin "P$238") (pinfunction "P$1_P$238") (pintype "power_in"))
      (node (ref "P7") (pin "P$239") (pinfunction "P$1_P$239") (pintype "power_in"))
      (node (ref "P7") (pin "P$24") (pinfunction "P$1_P$24") (pintype "power_in"))
      (node (ref "P7") (pin "P$240") (pinfunction "P$1_P$240") (pintype "power_in"))
      (node (ref "P7") (pin "P$241") (pinfunction "P$1_P$241") (pintype "power_in"))
      (node (ref "P7") (pin "P$242") (pinfunction "P$1_P$242") (pintype "power_in"))
      (node (ref "P7") (pin "P$243") (pinfunction "P$1_P$243") (pintype "power_in"))
      (node (ref "P7") (pin "P$244") (pinfunction "P$1_P$244") (pintype "power_in"))
      (node (ref "P7") (pin "P$245") (pinfunction "P$1_P$245") (pintype "power_in"))
      (node (ref "P7") (pin "P$246") (pinfunction "P$1_P$246") (pintype "power_in"))
      (node (ref "P7") (pin "P$247") (pinfunction "P$1_P$247") (pintype "power_in"))
      (node (ref "P7") (pin "P$248") (pinfunction "P$1_P$248") (pintype "power_in"))
      (node (ref "P7") (pin "P$249") (pinfunction "P$1_P$249") (pintype "power_in"))
      (node (ref "P7") (pin "P$25") (pinfunction "P$1_P$25") (pintype "power_in"))
      (node (ref "P7") (pin "P$250") (pinfunction "P$1_P$250") (pintype "power_in"))
      (node (ref "P7") (pin "P$251") (pinfunction "P$1_P$251") (pintype "power_in"))
      (node (ref "P7") (pin "P$252") (pinfunction "P$1_P$252") (pintype "power_in"))
      (node (ref "P7") (pin "P$253") (pinfunction "P$1_P$253") (pintype "power_in"))
      (node (ref "P7") (pin "P$254") (pinfunction "P$1_P$254") (pintype "power_in"))
      (node (ref "P7") (pin "P$255") (pinfunction "P$1_P$255") (pintype "power_in"))
      (node (ref "P7") (pin "P$256") (pinfunction "P$1_P$256") (pintype "power_in"))
      (node (ref "P7") (pin "P$257") (pinfunction "P$1_P$257") (pintype "power_in"))
      (node (ref "P7") (pin "P$258") (pinfunction "P$1_P$258") (pintype "power_in"))
      (node (ref "P7") (pin "P$259") (pinfunction "P$1_P$259") (pintype "power_in"))
      (node (ref "P7") (pin "P$26") (pinfunction "P$1_P$26") (pintype "power_in"))
      (node (ref "P7") (pin "P$260") (pinfunction "P$1_P$260") (pintype "power_in"))
      (node (ref "P7") (pin "P$261") (pinfunction "P$1_P$261") (pintype "power_in"))
      (node (ref "P7") (pin "P$262") (pinfunction "P$1_P$262") (pintype "power_in"))
      (node (ref "P7") (pin "P$263") (pinfunction "P$1_P$263") (pintype "power_in"))
      (node (ref "P7") (pin "P$264") (pinfunction "P$1_P$264") (pintype "power_in"))
      (node (ref "P7") (pin "P$265") (pinfunction "P$1_P$265") (pintype "power_in"))
      (node (ref "P7") (pin "P$266") (pinfunction "P$1_P$266") (pintype "power_in"))
      (node (ref "P7") (pin "P$267") (pinfunction "P$1_P$267") (pintype "power_in"))
      (node (ref "P7") (pin "P$268") (pinfunction "P$1_P$268") (pintype "power_in"))
      (node (ref "P7") (pin "P$269") (pinfunction "P$1_P$269") (pintype "power_in"))
      (node (ref "P7") (pin "P$27") (pinfunction "P$1_P$27") (pintype "power_in"))
      (node (ref "P7") (pin "P$270") (pinfunction "P$1_P$270") (pintype "power_in"))
      (node (ref "P7") (pin "P$271") (pinfunction "P$1_P$271") (pintype "power_in"))
      (node (ref "P7") (pin "P$272") (pinfunction "P$1_P$272") (pintype "power_in"))
      (node (ref "P7") (pin "P$273") (pinfunction "P$1_P$273") (pintype "power_in"))
      (node (ref "P7") (pin "P$274") (pinfunction "P$1_P$274") (pintype "power_in"))
      (node (ref "P7") (pin "P$275") (pinfunction "P$1_P$275") (pintype "power_in"))
      (node (ref "P7") (pin "P$276") (pinfunction "P$1_P$276") (pintype "power_in"))
      (node (ref "P7") (pin "P$277") (pinfunction "P$1_P$277") (pintype "power_in"))
      (node (ref "P7") (pin "P$278") (pinfunction "P$1_P$278") (pintype "power_in"))
      (node (ref "P7") (pin "P$279") (pinfunction "P$1_P$279") (pintype "power_in"))
      (node (ref "P7") (pin "P$28") (pinfunction "P$1_P$28") (pintype "power_in"))
      (node (ref "P7") (pin "P$280") (pinfunction "P$1_P$280") (pintype "power_in"))
      (node (ref "P7") (pin "P$281") (pinfunction "P$1_P$281") (pintype "power_in"))
      (node (ref "P7") (pin "P$282") (pinfunction "P$1_P$282") (pintype "power_in"))
      (node (ref "P7") (pin "P$283") (pinfunction "P$1_P$283") (pintype "power_in"))
      (node (ref "P7") (pin "P$284") (pinfunction "P$1_P$284") (pintype "power_in"))
      (node (ref "P7") (pin "P$285") (pinfunction "P$1_P$285") (pintype "power_in"))
      (node (ref "P7") (pin "P$286") (pinfunction "P$1_P$286") (pintype "power_in"))
      (node (ref "P7") (pin "P$287") (pinfunction "P$1_P$287") (pintype "power_in"))
      (node (ref "P7") (pin "P$288") (pinfunction "P$1_P$288") (pintype "power_in"))
      (node (ref "P7") (pin "P$29") (pinfunction "P$1_P$29") (pintype "power_in"))
      (node (ref "P7") (pin "P$3") (pinfunction "P$1_P$3") (pintype "power_in"))
      (node (ref "P7") (pin "P$30") (pinfunction "P$1_P$30") (pintype "power_in"))
      (node (ref "P7") (pin "P$31") (pinfunction "P$1_P$31") (pintype "power_in"))
      (node (ref "P7") (pin "P$32") (pinfunction "P$1_P$32") (pintype "power_in"))
      (node (ref "P7") (pin "P$33") (pinfunction "P$1_P$33") (pintype "power_in"))
      (node (ref "P7") (pin "P$34") (pinfunction "P$1_P$34") (pintype "power_in"))
      (node (ref "P7") (pin "P$35") (pinfunction "P$1_P$35") (pintype "power_in"))
      (node (ref "P7") (pin "P$36") (pinfunction "P$1_P$36") (pintype "power_in"))
      (node (ref "P7") (pin "P$37") (pinfunction "P$1_P$37") (pintype "power_in"))
      (node (ref "P7") (pin "P$38") (pinfunction "P$1_P$38") (pintype "power_in"))
      (node (ref "P7") (pin "P$39") (pinfunction "P$1_P$39") (pintype "power_in"))
      (node (ref "P7") (pin "P$4") (pinfunction "P$1_P$4") (pintype "power_in"))
      (node (ref "P7") (pin "P$40") (pinfunction "P$1_P$40") (pintype "power_in"))
      (node (ref "P7") (pin "P$41") (pinfunction "P$1_P$41") (pintype "power_in"))
      (node (ref "P7") (pin "P$42") (pinfunction "P$1_P$42") (pintype "power_in"))
      (node (ref "P7") (pin "P$43") (pinfunction "P$1_P$43") (pintype "power_in"))
      (node (ref "P7") (pin "P$44") (pinfunction "P$1_P$44") (pintype "power_in"))
      (node (ref "P7") (pin "P$45") (pinfunction "P$1_P$45") (pintype "power_in"))
      (node (ref "P7") (pin "P$46") (pinfunction "P$1_P$46") (pintype "power_in"))
      (node (ref "P7") (pin "P$47") (pinfunction "P$1_P$47") (pintype "power_in"))
      (node (ref "P7") (pin "P$48") (pinfunction "P$1_P$48") (pintype "power_in"))
      (node (ref "P7") (pin "P$49") (pinfunction "P$1_P$49") (pintype "power_in"))
      (node (ref "P7") (pin "P$5") (pinfunction "P$1_P$5") (pintype "power_in"))
      (node (ref "P7") (pin "P$50") (pinfunction "P$1_P$50") (pintype "power_in"))
      (node (ref "P7") (pin "P$51") (pinfunction "P$1_P$51") (pintype "power_in"))
      (node (ref "P7") (pin "P$52") (pinfunction "P$1_P$52") (pintype "power_in"))
      (node (ref "P7") (pin "P$53") (pinfunction "P$1_P$53") (pintype "power_in"))
      (node (ref "P7") (pin "P$54") (pinfunction "P$1_P$54") (pintype "power_in"))
      (node (ref "P7") (pin "P$55") (pinfunction "P$1_P$55") (pintype "power_in"))
      (node (ref "P7") (pin "P$56") (pinfunction "P$1_P$56") (pintype "power_in"))
      (node (ref "P7") (pin "P$57") (pinfunction "P$1_P$57") (pintype "power_in"))
      (node (ref "P7") (pin "P$58") (pinfunction "P$1_P$58") (pintype "power_in"))
      (node (ref "P7") (pin "P$59") (pinfunction "P$1_P$59") (pintype "power_in"))
      (node (ref "P7") (pin "P$6") (pinfunction "P$1_P$6") (pintype "power_in"))
      (node (ref "P7") (pin "P$60") (pinfunction "P$1_P$60") (pintype "power_in"))
      (node (ref "P7") (pin "P$61") (pinfunction "P$1_P$61") (pintype "power_in"))
      (node (ref "P7") (pin "P$62") (pinfunction "P$1_P$62") (pintype "power_in"))
      (node (ref "P7") (pin "P$63") (pinfunction "P$1_P$63") (pintype "power_in"))
      (node (ref "P7") (pin "P$64") (pinfunction "P$1_P$64") (pintype "power_in"))
      (node (ref "P7") (pin "P$65") (pinfunction "P$1_P$65") (pintype "power_in"))
      (node (ref "P7") (pin "P$66") (pinfunction "P$1_P$66") (pintype "power_in"))
      (node (ref "P7") (pin "P$67") (pinfunction "P$1_P$67") (pintype "power_in"))
      (node (ref "P7") (pin "P$68") (pinfunction "P$1_P$68") (pintype "power_in"))
      (node (ref "P7") (pin "P$69") (pinfunction "P$1_P$69") (pintype "power_in"))
      (node (ref "P7") (pin "P$7") (pinfunction "P$1_P$7") (pintype "power_in"))
      (node (ref "P7") (pin "P$70") (pinfunction "P$1_P$70") (pintype "power_in"))
      (node (ref "P7") (pin "P$71") (pinfunction "P$1_P$71") (pintype "power_in"))
      (node (ref "P7") (pin "P$72") (pinfunction "P$1_P$72") (pintype "power_in"))
      (node (ref "P7") (pin "P$73") (pinfunction "P$1_P$73") (pintype "power_in"))
      (node (ref "P7") (pin "P$74") (pinfunction "P$1_P$74") (pintype "power_in"))
      (node (ref "P7") (pin "P$75") (pinfunction "P$1_P$75") (pintype "power_in"))
      (node (ref "P7") (pin "P$76") (pinfunction "P$1_P$76") (pintype "power_in"))
      (node (ref "P7") (pin "P$77") (pinfunction "P$1_P$77") (pintype "power_in"))
      (node (ref "P7") (pin "P$78") (pinfunction "P$1_P$78") (pintype "power_in"))
      (node (ref "P7") (pin "P$79") (pinfunction "P$1_P$79") (pintype "power_in"))
      (node (ref "P7") (pin "P$8") (pinfunction "P$1_P$8") (pintype "power_in"))
      (node (ref "P7") (pin "P$80") (pinfunction "P$1_P$80") (pintype "power_in"))
      (node (ref "P7") (pin "P$81") (pinfunction "P$1_P$81") (pintype "power_in"))
      (node (ref "P7") (pin "P$82") (pinfunction "P$1_P$82") (pintype "power_in"))
      (node (ref "P7") (pin "P$83") (pinfunction "P$1_P$83") (pintype "power_in"))
      (node (ref "P7") (pin "P$84") (pinfunction "P$1_P$84") (pintype "power_in"))
      (node (ref "P7") (pin "P$85") (pinfunction "P$1_P$85") (pintype "power_in"))
      (node (ref "P7") (pin "P$86") (pinfunction "P$1_P$86") (pintype "power_in"))
      (node (ref "P7") (pin "P$87") (pinfunction "P$1_P$87") (pintype "power_in"))
      (node (ref "P7") (pin "P$88") (pinfunction "P$1_P$88") (pintype "power_in"))
      (node (ref "P7") (pin "P$89") (pinfunction "P$1_P$89") (pintype "power_in"))
      (node (ref "P7") (pin "P$9") (pinfunction "P$1_P$9") (pintype "power_in"))
      (node (ref "P7") (pin "P$90") (pinfunction "P$1_P$90") (pintype "power_in"))
      (node (ref "P7") (pin "P$91") (pinfunction "P$1_P$91") (pintype "power_in"))
      (node (ref "P7") (pin "P$92") (pinfunction "P$1_P$92") (pintype "power_in"))
      (node (ref "P7") (pin "P$93") (pinfunction "P$1_P$93") (pintype "power_in"))
      (node (ref "P7") (pin "P$94") (pinfunction "P$1_P$94") (pintype "power_in"))
      (node (ref "P7") (pin "P$95") (pinfunction "P$1_P$95") (pintype "power_in"))
      (node (ref "P7") (pin "P$96") (pinfunction "P$1_P$96") (pintype "power_in"))
      (node (ref "P7") (pin "P$97") (pinfunction "P$1_P$97") (pintype "power_in"))
      (node (ref "P7") (pin "P$98") (pinfunction "P$1_P$98") (pintype "power_in"))
      (node (ref "P7") (pin "P$99") (pinfunction "P$1_P$99") (pintype "power_in"))
    )
    (net (code "9") (name "/P8") (class "Default")
      (node (ref "JP1") (pin "P$9") (pinfunction "8_P$9") (pintype "bidirectional"))
      (node (ref "P8") (pin "P$1") (pinfunction "P$1_P$1") (pintype "power_in"))
      (node (ref "P8") (pin "P$10") (pinfunction "P$1_P$10") (pintype "power_in"))
      (node (ref "P8") (pin "P$100") (pinfunction "P$1_P$100") (pintype "power_in"))
      (node (ref "P8") (pin "P$101") (pinfunction "P$1_P$101") (pintype "power_in"))
      (node (ref "P8") (pin "P$102") (pinfunction "P$1_P$102") (pintype "power_in"))
      (node (ref "P8") (pin "P$103") (pinfunction "P$1_P$103") (pintype "power_in"))
      (node (ref "P8") (pin "P$104") (pinfunction "P$1_P$104") (pintype "power_in"))
      (node (ref "P8") (pin "P$105") (pinfunction "P$1_P$105") (pintype "power_in"))
      (node (ref "P8") (pin "P$106") (pinfunction "P$1_P$106") (pintype "power_in"))
      (node (ref "P8") (pin "P$107") (pinfunction "P$1_P$107") (pintype "power_in"))
      (node (ref "P8") (pin "P$108") (pinfunction "P$1_P$108") (pintype "power_in"))
      (node (ref "P8") (pin "P$109") (pinfunction "P$1_P$109") (pintype "power_in"))
      (node (ref "P8") (pin "P$11") (pinfunction "P$1_P$11") (pintype "power_in"))
      (node (ref "P8") (pin "P$110") (pinfunction "P$1_P$110") (pintype "power_in"))
      (node (ref "P8") (pin "P$111") (pinfunction "P$1_P$111") (pintype "power_in"))
      (node (ref "P8") (pin "P$112") (pinfunction "P$1_P$112") (pintype "power_in"))
      (node (ref "P8") (pin "P$113") (pinfunction "P$1_P$113") (pintype "power_in"))
      (node (ref "P8") (pin "P$114") (pinfunction "P$1_P$114") (pintype "power_in"))
      (node (ref "P8") (pin "P$115") (pinfunction "P$1_P$115") (pintype "power_in"))
      (node (ref "P8") (pin "P$116") (pinfunction "P$1_P$116") (pintype "power_in"))
      (node (ref "P8") (pin "P$117") (pinfunction "P$1_P$117") (pintype "power_in"))
      (node (ref "P8") (pin "P$118") (pinfunction "P$1_P$118") (pintype "power_in"))
      (node (ref "P8") (pin "P$119") (pinfunction "P$1_P$119") (pintype "power_in"))
      (node (ref "P8") (pin "P$12") (pinfunction "P$1_P$12") (pintype "power_in"))
      (node (ref "P8") (pin "P$120") (pinfunction "P$1_P$120") (pintype "power_in"))
      (node (ref "P8") (pin "P$121") (pinfunction "P$1_P$121") (pintype "power_in"))
      (node (ref "P8") (pin "P$122") (pinfunction "P$1_P$122") (pintype "power_in"))
      (node (ref "P8") (pin "P$123") (pinfunction "P$1_P$123") (pintype "power_in"))
      (node (ref "P8") (pin "P$124") (pinfunction "P$1_P$124") (pintype "power_in"))
      (node (ref "P8") (pin "P$125") (pinfunction "P$1_P$125") (pintype "power_in"))
      (node (ref "P8") (pin "P$126") (pinfunction "P$1_P$126") (pintype "power_in"))
      (node (ref "P8") (pin "P$127") (pinfunction "P$1_P$127") (pintype "power_in"))
      (node (ref "P8") (pin "P$128") (pinfunction "P$1_P$128") (pintype "power_in"))
      (node (ref "P8") (pin "P$129") (pinfunction "P$1_P$129") (pintype "power_in"))
      (node (ref "P8") (pin "P$13") (pinfunction "P$1_P$13") (pintype "power_in"))
      (node (ref "P8") (pin "P$130") (pinfunction "P$1_P$130") (pintype "power_in"))
      (node (ref "P8") (pin "P$131") (pinfunction "P$1_P$131") (pintype "power_in"))
      (node (ref "P8") (pin "P$132") (pinfunction "P$1_P$132") (pintype "power_in"))
      (node (ref "P8") (pin "P$133") (pinfunction "P$1_P$133") (pintype "power_in"))
      (node (ref "P8") (pin "P$134") (pinfunction "P$1_P$134") (pintype "power_in"))
      (node (ref "P8") (pin "P$135") (pinfunction "P$1_P$135") (pintype "power_in"))
      (node (ref "P8") (pin "P$136") (pinfunction "P$1_P$136") (pintype "power_in"))
      (node (ref "P8") (pin "P$137") (pinfunction "P$1_P$137") (pintype "power_in"))
      (node (ref "P8") (pin "P$138") (pinfunction "P$1_P$138") (pintype "power_in"))
      (node (ref "P8") (pin "P$139") (pinfunction "P$1_P$139") (pintype "power_in"))
      (node (ref "P8") (pin "P$14") (pinfunction "P$1_P$14") (pintype "power_in"))
      (node (ref "P8") (pin "P$140") (pinfunction "P$1_P$140") (pintype "power_in"))
      (node (ref "P8") (pin "P$141") (pinfunction "P$1_P$141") (pintype "power_in"))
      (node (ref "P8") (pin "P$142") (pinfunction "P$1_P$142") (pintype "power_in"))
      (node (ref "P8") (pin "P$143") (pinfunction "P$1_P$143") (pintype "power_in"))
      (node (ref "P8") (pin "P$144") (pinfunction "P$1_P$144") (pintype "power_in"))
      (node (ref "P8") (pin "P$145") (pinfunction "P$1_P$145") (pintype "power_in"))
      (node (ref "P8") (pin "P$146") (pinfunction "P$1_P$146") (pintype "power_in"))
      (node (ref "P8") (pin "P$147") (pinfunction "P$1_P$147") (pintype "power_in"))
      (node (ref "P8") (pin "P$148") (pinfunction "P$1_P$148") (pintype "power_in"))
      (node (ref "P8") (pin "P$149") (pinfunction "P$1_P$149") (pintype "power_in"))
      (node (ref "P8") (pin "P$15") (pinfunction "P$1_P$15") (pintype "power_in"))
      (node (ref "P8") (pin "P$150") (pinfunction "P$1_P$150") (pintype "power_in"))
      (node (ref "P8") (pin "P$151") (pinfunction "P$1_P$151") (pintype "power_in"))
      (node (ref "P8") (pin "P$152") (pinfunction "P$1_P$152") (pintype "power_in"))
      (node (ref "P8") (pin "P$153") (pinfunction "P$1_P$153") (pintype "power_in"))
      (node (ref "P8") (pin "P$154") (pinfunction "P$1_P$154") (pintype "power_in"))
      (node (ref "P8") (pin "P$155") (pinfunction "P$1_P$155") (pintype "power_in"))
      (node (ref "P8") (pin "P$156") (pinfunction "P$1_P$156") (pintype "power_in"))
      (node (ref "P8") (pin "P$157") (pinfunction "P$1_P$157") (pintype "power_in"))
      (node (ref "P8") (pin "P$158") (pinfunction "P$1_P$158") (pintype "power_in"))
      (node (ref "P8") (pin "P$159") (pinfunction "P$1_P$159") (pintype "power_in"))
      (node (ref "P8") (pin "P$16") (pinfunction "P$1_P$16") (pintype "power_in"))
      (node (ref "P8") (pin "P$160") (pinfunction "P$1_P$160") (pintype "power_in"))
      (node (ref "P8") (pin "P$161") (pinfunction "P$1_P$161") (pintype "power_in"))
      (node (ref "P8") (pin "P$162") (pinfunction "P$1_P$162") (pintype "power_in"))
      (node (ref "P8") (pin "P$163") (pinfunction "P$1_P$163") (pintype "power_in"))
      (node (ref "P8") (pin "P$164") (pinfunction "P$1_P$164") (pintype "power_in"))
      (node (ref "P8") (pin "P$165") (pinfunction "P$1_P$165") (pintype "power_in"))
      (node (ref "P8") (pin "P$166") (pinfunction "P$1_P$166") (pintype "power_in"))
      (node (ref "P8") (pin "P$167") (pinfunction "P$1_P$167") (pintype "power_in"))
      (node (ref "P8") (pin "P$168") (pinfunction "P$1_P$168") (pintype "power_in"))
      (node (ref "P8") (pin "P$169") (pinfunction "P$1_P$169") (pintype "power_in"))
      (node (ref "P8") (pin "P$17") (pinfunction "P$1_P$17") (pintype "power_in"))
      (node (ref "P8") (pin "P$170") (pinfunction "P$1_P$170") (pintype "power_in"))
      (node (ref "P8") (pin "P$171") (pinfunction "P$1_P$171") (pintype "power_in"))
      (node (ref "P8") (pin "P$172") (pinfunction "P$1_P$172") (pintype "power_in"))
      (node (ref "P8") (pin "P$173") (pinfunction "P$1_P$173") (pintype "power_in"))
      (node (ref "P8") (pin "P$174") (pinfunction "P$1_P$174") (pintype "power_in"))
      (node (ref "P8") (pin "P$175") (pinfunction "P$1_P$175") (pintype "power_in"))
      (node (ref "P8") (pin "P$176") (pinfunction "P$1_P$176") (pintype "power_in"))
      (node (ref "P8") (pin "P$177") (pinfunction "P$1_P$177") (pintype "power_in"))
      (node (ref "P8") (pin "P$178") (pinfunction "P$1_P$178") (pintype "power_in"))
      (node (ref "P8") (pin "P$179") (pinfunction "P$1_P$179") (pintype "power_in"))
      (node (ref "P8") (pin "P$18") (pinfunction "P$1_P$18") (pintype "power_in"))
      (node (ref "P8") (pin "P$180") (pinfunction "P$1_P$180") (pintype "power_in"))
      (node (ref "P8") (pin "P$181") (pinfunction "P$1_P$181") (pintype "power_in"))
      (node (ref "P8") (pin "P$182") (pinfunction "P$1_P$182") (pintype "power_in"))
      (node (ref "P8") (pin "P$183") (pinfunction "P$1_P$183") (pintype "power_in"))
      (node (ref "P8") (pin "P$184") (pinfunction "P$1_P$184") (pintype "power_in"))
      (node (ref "P8") (pin "P$185") (pinfunction "P$1_P$185") (pintype "power_in"))
      (node (ref "P8") (pin "P$186") (pinfunction "P$1_P$186") (pintype "power_in"))
      (node (ref "P8") (pin "P$187") (pinfunction "P$1_P$187") (pintype "power_in"))
      (node (ref "P8") (pin "P$188") (pinfunction "P$1_P$188") (pintype "power_in"))
      (node (ref "P8") (pin "P$189") (pinfunction "P$1_P$189") (pintype "power_in"))
      (node (ref "P8") (pin "P$19") (pinfunction "P$1_P$19") (pintype "power_in"))
      (node (ref "P8") (pin "P$190") (pinfunction "P$1_P$190") (pintype "power_in"))
      (node (ref "P8") (pin "P$191") (pinfunction "P$1_P$191") (pintype "power_in"))
      (node (ref "P8") (pin "P$192") (pinfunction "P$1_P$192") (pintype "power_in"))
      (node (ref "P8") (pin "P$193") (pinfunction "P$1_P$193") (pintype "power_in"))
      (node (ref "P8") (pin "P$194") (pinfunction "P$1_P$194") (pintype "power_in"))
      (node (ref "P8") (pin "P$195") (pinfunction "P$1_P$195") (pintype "power_in"))
      (node (ref "P8") (pin "P$196") (pinfunction "P$1_P$196") (pintype "power_in"))
      (node (ref "P8") (pin "P$197") (pinfunction "P$1_P$197") (pintype "power_in"))
      (node (ref "P8") (pin "P$198") (pinfunction "P$1_P$198") (pintype "power_in"))
      (node (ref "P8") (pin "P$199") (pinfunction "P$1_P$199") (pintype "power_in"))
      (node (ref "P8") (pin "P$2") (pinfunction "P$1_P$2") (pintype "power_in"))
      (node (ref "P8") (pin "P$20") (pinfunction "P$1_P$20") (pintype "power_in"))
      (node (ref "P8") (pin "P$200") (pinfunction "P$1_P$200") (pintype "power_in"))
      (node (ref "P8") (pin "P$201") (pinfunction "P$1_P$201") (pintype "power_in"))
      (node (ref "P8") (pin "P$202") (pinfunction "P$1_P$202") (pintype "power_in"))
      (node (ref "P8") (pin "P$203") (pinfunction "P$1_P$203") (pintype "power_in"))
      (node (ref "P8") (pin "P$204") (pinfunction "P$1_P$204") (pintype "power_in"))
      (node (ref "P8") (pin "P$205") (pinfunction "P$1_P$205") (pintype "power_in"))
      (node (ref "P8") (pin "P$206") (pinfunction "P$1_P$206") (pintype "power_in"))
      (node (ref "P8") (pin "P$207") (pinfunction "P$1_P$207") (pintype "power_in"))
      (node (ref "P8") (pin "P$208") (pinfunction "P$1_P$208") (pintype "power_in"))
      (node (ref "P8") (pin "P$209") (pinfunction "P$1_P$209") (pintype "power_in"))
      (node (ref "P8") (pin "P$21") (pinfunction "P$1_P$21") (pintype "power_in"))
      (node (ref "P8") (pin "P$210") (pinfunction "P$1_P$210") (pintype "power_in"))
      (node (ref "P8") (pin "P$211") (pinfunction "P$1_P$211") (pintype "power_in"))
      (node (ref "P8") (pin "P$212") (pinfunction "P$1_P$212") (pintype "power_in"))
      (node (ref "P8") (pin "P$213") (pinfunction "P$1_P$213") (pintype "power_in"))
      (node (ref "P8") (pin "P$214") (pinfunction "P$1_P$214") (pintype "power_in"))
      (node (ref "P8") (pin "P$215") (pinfunction "P$1_P$215") (pintype "power_in"))
      (node (ref "P8") (pin "P$216") (pinfunction "P$1_P$216") (pintype "power_in"))
      (node (ref "P8") (pin "P$217") (pinfunction "P$1_P$217") (pintype "power_in"))
      (node (ref "P8") (pin "P$218") (pinfunction "P$1_P$218") (pintype "power_in"))
      (node (ref "P8") (pin "P$219") (pinfunction "P$1_P$219") (pintype "power_in"))
      (node (ref "P8") (pin "P$22") (pinfunction "P$1_P$22") (pintype "power_in"))
      (node (ref "P8") (pin "P$220") (pinfunction "P$1_P$220") (pintype "power_in"))
      (node (ref "P8") (pin "P$221") (pinfunction "P$1_P$221") (pintype "power_in"))
      (node (ref "P8") (pin "P$222") (pinfunction "P$1_P$222") (pintype "power_in"))
      (node (ref "P8") (pin "P$223") (pinfunction "P$1_P$223") (pintype "power_in"))
      (node (ref "P8") (pin "P$224") (pinfunction "P$1_P$224") (pintype "power_in"))
      (node (ref "P8") (pin "P$225") (pinfunction "P$1_P$225") (pintype "power_in"))
      (node (ref "P8") (pin "P$226") (pinfunction "P$1_P$226") (pintype "power_in"))
      (node (ref "P8") (pin "P$227") (pinfunction "P$1_P$227") (pintype "power_in"))
      (node (ref "P8") (pin "P$228") (pinfunction "P$1_P$228") (pintype "power_in"))
      (node (ref "P8") (pin "P$229") (pinfunction "P$1_P$229") (pintype "power_in"))
      (node (ref "P8") (pin "P$23") (pinfunction "P$1_P$23") (pintype "power_in"))
      (node (ref "P8") (pin "P$230") (pinfunction "P$1_P$230") (pintype "power_in"))
      (node (ref "P8") (pin "P$231") (pinfunction "P$1_P$231") (pintype "power_in"))
      (node (ref "P8") (pin "P$232") (pinfunction "P$1_P$232") (pintype "power_in"))
      (node (ref "P8") (pin "P$233") (pinfunction "P$1_P$233") (pintype "power_in"))
      (node (ref "P8") (pin "P$234") (pinfunction "P$1_P$234") (pintype "power_in"))
      (node (ref "P8") (pin "P$235") (pinfunction "P$1_P$235") (pintype "power_in"))
      (node (ref "P8") (pin "P$236") (pinfunction "P$1_P$236") (pintype "power_in"))
      (node (ref "P8") (pin "P$237") (pinfunction "P$1_P$237") (pintype "power_in"))
      (node (ref "P8") (pin "P$238") (pinfunction "P$1_P$238") (pintype "power_in"))
      (node (ref "P8") (pin "P$239") (pinfunction "P$1_P$239") (pintype "power_in"))
      (node (ref "P8") (pin "P$24") (pinfunction "P$1_P$24") (pintype "power_in"))
      (node (ref "P8") (pin "P$240") (pinfunction "P$1_P$240") (pintype "power_in"))
      (node (ref "P8") (pin "P$241") (pinfunction "P$1_P$241") (pintype "power_in"))
      (node (ref "P8") (pin "P$242") (pinfunction "P$1_P$242") (pintype "power_in"))
      (node (ref "P8") (pin "P$243") (pinfunction "P$1_P$243") (pintype "power_in"))
      (node (ref "P8") (pin "P$244") (pinfunction "P$1_P$244") (pintype "power_in"))
      (node (ref "P8") (pin "P$245") (pinfunction "P$1_P$245") (pintype "power_in"))
      (node (ref "P8") (pin "P$246") (pinfunction "P$1_P$246") (pintype "power_in"))
      (node (ref "P8") (pin "P$247") (pinfunction "P$1_P$247") (pintype "power_in"))
      (node (ref "P8") (pin "P$248") (pinfunction "P$1_P$248") (pintype "power_in"))
      (node (ref "P8") (pin "P$249") (pinfunction "P$1_P$249") (pintype "power_in"))
      (node (ref "P8") (pin "P$25") (pinfunction "P$1_P$25") (pintype "power_in"))
      (node (ref "P8") (pin "P$250") (pinfunction "P$1_P$250") (pintype "power_in"))
      (node (ref "P8") (pin "P$251") (pinfunction "P$1_P$251") (pintype "power_in"))
      (node (ref "P8") (pin "P$252") (pinfunction "P$1_P$252") (pintype "power_in"))
      (node (ref "P8") (pin "P$253") (pinfunction "P$1_P$253") (pintype "power_in"))
      (node (ref "P8") (pin "P$254") (pinfunction "P$1_P$254") (pintype "power_in"))
      (node (ref "P8") (pin "P$255") (pinfunction "P$1_P$255") (pintype "power_in"))
      (node (ref "P8") (pin "P$256") (pinfunction "P$1_P$256") (pintype "power_in"))
      (node (ref "P8") (pin "P$257") (pinfunction "P$1_P$257") (pintype "power_in"))
      (node (ref "P8") (pin "P$258") (pinfunction "P$1_P$258") (pintype "power_in"))
      (node (ref "P8") (pin "P$259") (pinfunction "P$1_P$259") (pintype "power_in"))
      (node (ref "P8") (pin "P$26") (pinfunction "P$1_P$26") (pintype "power_in"))
      (node (ref "P8") (pin "P$260") (pinfunction "P$1_P$260") (pintype "power_in"))
      (node (ref "P8") (pin "P$261") (pinfunction "P$1_P$261") (pintype "power_in"))
      (node (ref "P8") (pin "P$262") (pinfunction "P$1_P$262") (pintype "power_in"))
      (node (ref "P8") (pin "P$263") (pinfunction "P$1_P$263") (pintype "power_in"))
      (node (ref "P8") (pin "P$264") (pinfunction "P$1_P$264") (pintype "power_in"))
      (node (ref "P8") (pin "P$265") (pinfunction "P$1_P$265") (pintype "power_in"))
      (node (ref "P8") (pin "P$266") (pinfunction "P$1_P$266") (pintype "power_in"))
      (node (ref "P8") (pin "P$267") (pinfunction "P$1_P$267") (pintype "power_in"))
      (node (ref "P8") (pin "P$268") (pinfunction "P$1_P$268") (pintype "power_in"))
      (node (ref "P8") (pin "P$269") (pinfunction "P$1_P$269") (pintype "power_in"))
      (node (ref "P8") (pin "P$27") (pinfunction "P$1_P$27") (pintype "power_in"))
      (node (ref "P8") (pin "P$270") (pinfunction "P$1_P$270") (pintype "power_in"))
      (node (ref "P8") (pin "P$271") (pinfunction "P$1_P$271") (pintype "power_in"))
      (node (ref "P8") (pin "P$272") (pinfunction "P$1_P$272") (pintype "power_in"))
      (node (ref "P8") (pin "P$273") (pinfunction "P$1_P$273") (pintype "power_in"))
      (node (ref "P8") (pin "P$274") (pinfunction "P$1_P$274") (pintype "power_in"))
      (node (ref "P8") (pin "P$275") (pinfunction "P$1_P$275") (pintype "power_in"))
      (node (ref "P8") (pin "P$276") (pinfunction "P$1_P$276") (pintype "power_in"))
      (node (ref "P8") (pin "P$277") (pinfunction "P$1_P$277") (pintype "power_in"))
      (node (ref "P8") (pin "P$278") (pinfunction "P$1_P$278") (pintype "power_in"))
      (node (ref "P8") (pin "P$279") (pinfunction "P$1_P$279") (pintype "power_in"))
      (node (ref "P8") (pin "P$28") (pinfunction "P$1_P$28") (pintype "power_in"))
      (node (ref "P8") (pin "P$280") (pinfunction "P$1_P$280") (pintype "power_in"))
      (node (ref "P8") (pin "P$281") (pinfunction "P$1_P$281") (pintype "power_in"))
      (node (ref "P8") (pin "P$282") (pinfunction "P$1_P$282") (pintype "power_in"))
      (node (ref "P8") (pin "P$283") (pinfunction "P$1_P$283") (pintype "power_in"))
      (node (ref "P8") (pin "P$284") (pinfunction "P$1_P$284") (pintype "power_in"))
      (node (ref "P8") (pin "P$285") (pinfunction "P$1_P$285") (pintype "power_in"))
      (node (ref "P8") (pin "P$286") (pinfunction "P$1_P$286") (pintype "power_in"))
      (node (ref "P8") (pin "P$287") (pinfunction "P$1_P$287") (pintype "power_in"))
      (node (ref "P8") (pin "P$288") (pinfunction "P$1_P$288") (pintype "power_in"))
      (node (ref "P8") (pin "P$289") (pinfunction "P$1_P$289") (pintype "power_in"))
      (node (ref "P8") (pin "P$29") (pinfunction "P$1_P$29") (pintype "power_in"))
      (node (ref "P8") (pin "P$290") (pinfunction "P$1_P$290") (pintype "power_in"))
      (node (ref "P8") (pin "P$291") (pinfunction "P$1_P$291") (pintype "power_in"))
      (node (ref "P8") (pin "P$292") (pinfunction "P$1_P$292") (pintype "power_in"))
      (node (ref "P8") (pin "P$293") (pinfunction "P$1_P$293") (pintype "power_in"))
      (node (ref "P8") (pin "P$294") (pinfunction "P$1_P$294") (pintype "power_in"))
      (node (ref "P8") (pin "P$295") (pinfunction "P$1_P$295") (pintype "power_in"))
      (node (ref "P8") (pin "P$296") (pinfunction "P$1_P$296") (pintype "power_in"))
      (node (ref "P8") (pin "P$297") (pinfunction "P$1_P$297") (pintype "power_in"))
      (node (ref "P8") (pin "P$298") (pinfunction "P$1_P$298") (pintype "power_in"))
      (node (ref "P8") (pin "P$299") (pinfunction "P$1_P$299") (pintype "power_in"))
      (node (ref "P8") (pin "P$3") (pinfunction "P$1_P$3") (pintype "power_in"))
      (node (ref "P8") (pin "P$30") (pinfunction "P$1_P$30") (pintype "power_in"))
      (node (ref "P8") (pin "P$300") (pinfunction "P$1_P$300") (pintype "power_in"))
      (node (ref "P8") (pin "P$301") (pinfunction "P$1_P$301") (pintype "power_in"))
      (node (ref "P8") (pin "P$302") (pinfunction "P$1_P$302") (pintype "power_in"))
      (node (ref "P8") (pin "P$303") (pinfunction "P$1_P$303") (pintype "power_in"))
      (node (ref "P8") (pin "P$304") (pinfunction "P$1_P$304") (pintype "power_in"))
      (node (ref "P8") (pin "P$305") (pinfunction "P$1_P$305") (pintype "power_in"))
      (node (ref "P8") (pin "P$306") (pinfunction "P$1_P$306") (pintype "power_in"))
      (node (ref "P8") (pin "P$307") (pinfunction "P$1_P$307") (pintype "power_in"))
      (node (ref "P8") (pin "P$308") (pinfunction "P$1_P$308") (pintype "power_in"))
      (node (ref "P8") (pin "P$309") (pinfunction "P$1_P$309") (pintype "power_in"))
      (node (ref "P8") (pin "P$31") (pinfunction "P$1_P$31") (pintype "power_in"))
      (node (ref "P8") (pin "P$310") (pinfunction "P$1_P$310") (pintype "power_in"))
      (node (ref "P8") (pin "P$311") (pinfunction "P$1_P$311") (pintype "power_in"))
      (node (ref "P8") (pin "P$312") (pinfunction "P$1_P$312") (pintype "power_in"))
      (node (ref "P8") (pin "P$313") (pinfunction "P$1_P$313") (pintype "power_in"))
      (node (ref "P8") (pin "P$314") (pinfunction "P$1_P$314") (pintype "power_in"))
      (node (ref "P8") (pin "P$315") (pinfunction "P$1_P$315") (pintype "power_in"))
      (node (ref "P8") (pin "P$316") (pinfunction "P$1_P$316") (pintype "power_in"))
      (node (ref "P8") (pin "P$317") (pinfunction "P$1_P$317") (pintype "power_in"))
      (node (ref "P8") (pin "P$318") (pinfunction "P$1_P$318") (pintype "power_in"))
      (node (ref "P8") (pin "P$319") (pinfunction "P$1_P$319") (pintype "power_in"))
      (node (ref "P8") (pin "P$32") (pinfunction "P$1_P$32") (pintype "power_in"))
      (node (ref "P8") (pin "P$320") (pinfunction "P$1_P$320") (pintype "power_in"))
      (node (ref "P8") (pin "P$321") (pinfunction "P$1_P$321") (pintype "power_in"))
      (node (ref "P8") (pin "P$322") (pinfunction "P$1_P$322") (pintype "power_in"))
      (node (ref "P8") (pin "P$323") (pinfunction "P$1_P$323") (pintype "power_in"))
      (node (ref "P8") (pin "P$324") (pinfunction "P$1_P$324") (pintype "power_in"))
      (node (ref "P8") (pin "P$325") (pinfunction "P$1_P$325") (pintype "power_in"))
      (node (ref "P8") (pin "P$326") (pinfunction "P$1_P$326") (pintype "power_in"))
      (node (ref "P8") (pin "P$327") (pinfunction "P$1_P$327") (pintype "power_in"))
      (node (ref "P8") (pin "P$328") (pinfunction "P$1_P$328") (pintype "power_in"))
      (node (ref "P8") (pin "P$329") (pinfunction "P$1_P$329") (pintype "power_in"))
      (node (ref "P8") (pin "P$33") (pinfunction "P$1_P$33") (pintype "power_in"))
      (node (ref "P8") (pin "P$330") (pinfunction "P$1_P$330") (pintype "power_in"))
      (node (ref "P8") (pin "P$331") (pinfunction "P$1_P$331") (pintype "power_in"))
      (node (ref "P8") (pin "P$332") (pinfunction "P$1_P$332") (pintype "power_in"))
      (node (ref "P8") (pin "P$333") (pinfunction "P$1_P$333") (pintype "power_in"))
      (node (ref "P8") (pin "P$334") (pinfunction "P$1_P$334") (pintype "power_in"))
      (node (ref "P8") (pin "P$335") (pinfunction "P$1_P$335") (pintype "power_in"))
      (node (ref "P8") (pin "P$336") (pinfunction "P$1_P$336") (pintype "power_in"))
      (node (ref "P8") (pin "P$337") (pinfunction "P$1_P$337") (pintype "power_in"))
      (node (ref "P8") (pin "P$338") (pinfunction "P$1_P$338") (pintype "power_in"))
      (node (ref "P8") (pin "P$339") (pinfunction "P$1_P$339") (pintype "power_in"))
      (node (ref "P8") (pin "P$34") (pinfunction "P$1_P$34") (pintype "power_in"))
      (node (ref "P8") (pin "P$340") (pinfunction "P$1_P$340") (pintype "power_in"))
      (node (ref "P8") (pin "P$341") (pinfunction "P$1_P$341") (pintype "power_in"))
      (node (ref "P8") (pin "P$342") (pinfunction "P$1_P$342") (pintype "power_in"))
      (node (ref "P8") (pin "P$343") (pinfunction "P$1_P$343") (pintype "power_in"))
      (node (ref "P8") (pin "P$344") (pinfunction "P$1_P$344") (pintype "power_in"))
      (node (ref "P8") (pin "P$345") (pinfunction "P$1_P$345") (pintype "power_in"))
      (node (ref "P8") (pin "P$346") (pinfunction "P$1_P$346") (pintype "power_in"))
      (node (ref "P8") (pin "P$347") (pinfunction "P$1_P$347") (pintype "power_in"))
      (node (ref "P8") (pin "P$348") (pinfunction "P$1_P$348") (pintype "power_in"))
      (node (ref "P8") (pin "P$349") (pinfunction "P$1_P$349") (pintype "power_in"))
      (node (ref "P8") (pin "P$35") (pinfunction "P$1_P$35") (pintype "power_in"))
      (node (ref "P8") (pin "P$350") (pinfunction "P$1_P$350") (pintype "power_in"))
      (node (ref "P8") (pin "P$351") (pinfunction "P$1_P$351") (pintype "power_in"))
      (node (ref "P8") (pin "P$352") (pinfunction "P$1_P$352") (pintype "power_in"))
      (node (ref "P8") (pin "P$353") (pinfunction "P$1_P$353") (pintype "power_in"))
      (node (ref "P8") (pin "P$354") (pinfunction "P$1_P$354") (pintype "power_in"))
      (node (ref "P8") (pin "P$355") (pinfunction "P$1_P$355") (pintype "power_in"))
      (node (ref "P8") (pin "P$356") (pinfunction "P$1_P$356") (pintype "power_in"))
      (node (ref "P8") (pin "P$357") (pinfunction "P$1_P$357") (pintype "power_in"))
      (node (ref "P8") (pin "P$358") (pinfunction "P$1_P$358") (pintype "power_in"))
      (node (ref "P8") (pin "P$359") (pinfunction "P$1_P$359") (pintype "power_in"))
      (node (ref "P8") (pin "P$36") (pinfunction "P$1_P$36") (pintype "power_in"))
      (node (ref "P8") (pin "P$360") (pinfunction "P$1_P$360") (pintype "power_in"))
      (node (ref "P8") (pin "P$361") (pinfunction "P$1_P$361") (pintype "power_in"))
      (node (ref "P8") (pin "P$362") (pinfunction "P$1_P$362") (pintype "power_in"))
      (node (ref "P8") (pin "P$363") (pinfunction "P$1_P$363") (pintype "power_in"))
      (node (ref "P8") (pin "P$364") (pinfunction "P$1_P$364") (pintype "power_in"))
      (node (ref "P8") (pin "P$365") (pinfunction "P$1_P$365") (pintype "power_in"))
      (node (ref "P8") (pin "P$366") (pinfunction "P$1_P$366") (pintype "power_in"))
      (node (ref "P8") (pin "P$367") (pinfunction "P$1_P$367") (pintype "power_in"))
      (node (ref "P8") (pin "P$368") (pinfunction "P$1_P$368") (pintype "power_in"))
      (node (ref "P8") (pin "P$369") (pinfunction "P$1_P$369") (pintype "power_in"))
      (node (ref "P8") (pin "P$37") (pinfunction "P$1_P$37") (pintype "power_in"))
      (node (ref "P8") (pin "P$370") (pinfunction "P$1_P$370") (pintype "power_in"))
      (node (ref "P8") (pin "P$371") (pinfunction "P$1_P$371") (pintype "power_in"))
      (node (ref "P8") (pin "P$372") (pinfunction "P$1_P$372") (pintype "power_in"))
      (node (ref "P8") (pin "P$373") (pinfunction "P$1_P$373") (pintype "power_in"))
      (node (ref "P8") (pin "P$374") (pinfunction "P$1_P$374") (pintype "power_in"))
      (node (ref "P8") (pin "P$375") (pinfunction "P$1_P$375") (pintype "power_in"))
      (node (ref "P8") (pin "P$376") (pinfunction "P$1_P$376") (pintype "power_in"))
      (node (ref "P8") (pin "P$377") (pinfunction "P$1_P$377") (pintype "power_in"))
      (node (ref "P8") (pin "P$378") (pinfunction "P$1_P$378") (pintype "power_in"))
      (node (ref "P8") (pin "P$379") (pinfunction "P$1_P$379") (pintype "power_in"))
      (node (ref "P8") (pin "P$38") (pinfunction "P$1_P$38") (pintype "power_in"))
      (node (ref "P8") (pin "P$380") (pinfunction "P$1_P$380") (pintype "power_in"))
      (node (ref "P8") (pin "P$381") (pinfunction "P$1_P$381") (pintype "power_in"))
      (node (ref "P8") (pin "P$382") (pinfunction "P$1_P$382") (pintype "power_in"))
      (node (ref "P8") (pin "P$383") (pinfunction "P$1_P$383") (pintype "power_in"))
      (node (ref "P8") (pin "P$384") (pinfunction "P$1_P$384") (pintype "power_in"))
      (node (ref "P8") (pin "P$385") (pinfunction "P$1_P$385") (pintype "power_in"))
      (node (ref "P8") (pin "P$386") (pinfunction "P$1_P$386") (pintype "power_in"))
      (node (ref "P8") (pin "P$387") (pinfunction "P$1_P$387") (pintype "power_in"))
      (node (ref "P8") (pin "P$388") (pinfunction "P$1_P$388") (pintype "power_in"))
      (node (ref "P8") (pin "P$389") (pinfunction "P$1_P$389") (pintype "power_in"))
      (node (ref "P8") (pin "P$39") (pinfunction "P$1_P$39") (pintype "power_in"))
      (node (ref "P8") (pin "P$390") (pinfunction "P$1_P$390") (pintype "power_in"))
      (node (ref "P8") (pin "P$391") (pinfunction "P$1_P$391") (pintype "power_in"))
      (node (ref "P8") (pin "P$392") (pinfunction "P$1_P$392") (pintype "power_in"))
      (node (ref "P8") (pin "P$393") (pinfunction "P$1_P$393") (pintype "power_in"))
      (node (ref "P8") (pin "P$394") (pinfunction "P$1_P$394") (pintype "power_in"))
      (node (ref "P8") (pin "P$395") (pinfunction "P$1_P$395") (pintype "power_in"))
      (node (ref "P8") (pin "P$396") (pinfunction "P$1_P$396") (pintype "power_in"))
      (node (ref "P8") (pin "P$397") (pinfunction "P$1_P$397") (pintype "power_in"))
      (node (ref "P8") (pin "P$398") (pinfunction "P$1_P$398") (pintype "power_in"))
      (node (ref "P8") (pin "P$399") (pinfunction "P$1_P$399") (pintype "power_in"))
      (node (ref "P8") (pin "P$4") (pinfunction "P$1_P$4") (pintype "power_in"))
      (node (ref "P8") (pin "P$40") (pinfunction "P$1_P$40") (pintype "power_in"))
      (node (ref "P8") (pin "P$400") (pinfunction "P$1_P$400") (pintype "power_in"))
      (node (ref "P8") (pin "P$401") (pinfunction "P$1_P$401") (pintype "power_in"))
      (node (ref "P8") (pin "P$402") (pinfunction "P$1_P$402") (pintype "power_in"))
      (node (ref "P8") (pin "P$403") (pinfunction "P$1_P$403") (pintype "power_in"))
      (node (ref "P8") (pin "P$404") (pinfunction "P$1_P$404") (pintype "power_in"))
      (node (ref "P8") (pin "P$405") (pinfunction "P$1_P$405") (pintype "power_in"))
      (node (ref "P8") (pin "P$406") (pinfunction "P$1_P$406") (pintype "power_in"))
      (node (ref "P8") (pin "P$407") (pinfunction "P$1_P$407") (pintype "power_in"))
      (node (ref "P8") (pin "P$408") (pinfunction "P$1_P$408") (pintype "power_in"))
      (node (ref "P8") (pin "P$409") (pinfunction "P$1_P$409") (pintype "power_in"))
      (node (ref "P8") (pin "P$41") (pinfunction "P$1_P$41") (pintype "power_in"))
      (node (ref "P8") (pin "P$410") (pinfunction "P$1_P$410") (pintype "power_in"))
      (node (ref "P8") (pin "P$411") (pinfunction "P$1_P$411") (pintype "power_in"))
      (node (ref "P8") (pin "P$412") (pinfunction "P$1_P$412") (pintype "power_in"))
      (node (ref "P8") (pin "P$413") (pinfunction "P$1_P$413") (pintype "power_in"))
      (node (ref "P8") (pin "P$414") (pinfunction "P$1_P$414") (pintype "power_in"))
      (node (ref "P8") (pin "P$415") (pinfunction "P$1_P$415") (pintype "power_in"))
      (node (ref "P8") (pin "P$416") (pinfunction "P$1_P$416") (pintype "power_in"))
      (node (ref "P8") (pin "P$417") (pinfunction "P$1_P$417") (pintype "power_in"))
      (node (ref "P8") (pin "P$418") (pinfunction "P$1_P$418") (pintype "power_in"))
      (node (ref "P8") (pin "P$419") (pinfunction "P$1_P$419") (pintype "power_in"))
      (node (ref "P8") (pin "P$42") (pinfunction "P$1_P$42") (pintype "power_in"))
      (node (ref "P8") (pin "P$420") (pinfunction "P$1_P$420") (pintype "power_in"))
      (node (ref "P8") (pin "P$421") (pinfunction "P$1_P$421") (pintype "power_in"))
      (node (ref "P8") (pin "P$422") (pinfunction "P$1_P$422") (pintype "power_in"))
      (node (ref "P8") (pin "P$423") (pinfunction "P$1_P$423") (pintype "power_in"))
      (node (ref "P8") (pin "P$424") (pinfunction "P$1_P$424") (pintype "power_in"))
      (node (ref "P8") (pin "P$425") (pinfunction "P$1_P$425") (pintype "power_in"))
      (node (ref "P8") (pin "P$426") (pinfunction "P$1_P$426") (pintype "power_in"))
      (node (ref "P8") (pin "P$427") (pinfunction "P$1_P$427") (pintype "power_in"))
      (node (ref "P8") (pin "P$428") (pinfunction "P$1_P$428") (pintype "power_in"))
      (node (ref "P8") (pin "P$429") (pinfunction "P$1_P$429") (pintype "power_in"))
      (node (ref "P8") (pin "P$43") (pinfunction "P$1_P$43") (pintype "power_in"))
      (node (ref "P8") (pin "P$430") (pinfunction "P$1_P$430") (pintype "power_in"))
      (node (ref "P8") (pin "P$431") (pinfunction "P$1_P$431") (pintype "power_in"))
      (node (ref "P8") (pin "P$432") (pinfunction "P$1_P$432") (pintype "power_in"))
      (node (ref "P8") (pin "P$433") (pinfunction "P$1_P$433") (pintype "power_in"))
      (node (ref "P8") (pin "P$434") (pinfunction "P$1_P$434") (pintype "power_in"))
      (node (ref "P8") (pin "P$435") (pinfunction "P$1_P$435") (pintype "power_in"))
      (node (ref "P8") (pin "P$436") (pinfunction "P$1_P$436") (pintype "power_in"))
      (node (ref "P8") (pin "P$437") (pinfunction "P$1_P$437") (pintype "power_in"))
      (node (ref "P8") (pin "P$438") (pinfunction "P$1_P$438") (pintype "power_in"))
      (node (ref "P8") (pin "P$439") (pinfunction "P$1_P$439") (pintype "power_in"))
      (node (ref "P8") (pin "P$44") (pinfunction "P$1_P$44") (pintype "power_in"))
      (node (ref "P8") (pin "P$440") (pinfunction "P$1_P$440") (pintype "power_in"))
      (node (ref "P8") (pin "P$441") (pinfunction "P$1_P$441") (pintype "power_in"))
      (node (ref "P8") (pin "P$442") (pinfunction "P$1_P$442") (pintype "power_in"))
      (node (ref "P8") (pin "P$443") (pinfunction "P$1_P$443") (pintype "power_in"))
      (node (ref "P8") (pin "P$444") (pinfunction "P$1_P$444") (pintype "power_in"))
      (node (ref "P8") (pin "P$445") (pinfunction "P$1_P$445") (pintype "power_in"))
      (node (ref "P8") (pin "P$446") (pinfunction "P$1_P$446") (pintype "power_in"))
      (node (ref "P8") (pin "P$447") (pinfunction "P$1_P$447") (pintype "power_in"))
      (node (ref "P8") (pin "P$448") (pinfunction "P$1_P$448") (pintype "power_in"))
      (node (ref "P8") (pin "P$449") (pinfunction "P$1_P$449") (pintype "power_in"))
      (node (ref "P8") (pin "P$45") (pinfunction "P$1_P$45") (pintype "power_in"))
      (node (ref "P8") (pin "P$450") (pinfunction "P$1_P$450") (pintype "power_in"))
      (node (ref "P8") (pin "P$451") (pinfunction "P$1_P$451") (pintype "power_in"))
      (node (ref "P8") (pin "P$452") (pinfunction "P$1_P$452") (pintype "power_in"))
      (node (ref "P8") (pin "P$453") (pinfunction "P$1_P$453") (pintype "power_in"))
      (node (ref "P8") (pin "P$454") (pinfunction "P$1_P$454") (pintype "power_in"))
      (node (ref "P8") (pin "P$455") (pinfunction "P$1_P$455") (pintype "power_in"))
      (node (ref "P8") (pin "P$456") (pinfunction "P$1_P$456") (pintype "power_in"))
      (node (ref "P8") (pin "P$457") (pinfunction "P$1_P$457") (pintype "power_in"))
      (node (ref "P8") (pin "P$458") (pinfunction "P$1_P$458") (pintype "power_in"))
      (node (ref "P8") (pin "P$459") (pinfunction "P$1_P$459") (pintype "power_in"))
      (node (ref "P8") (pin "P$46") (pinfunction "P$1_P$46") (pintype "power_in"))
      (node (ref "P8") (pin "P$460") (pinfunction "P$1_P$460") (pintype "power_in"))
      (node (ref "P8") (pin "P$461") (pinfunction "P$1_P$461") (pintype "power_in"))
      (node (ref "P8") (pin "P$462") (pinfunction "P$1_P$462") (pintype "power_in"))
      (node (ref "P8") (pin "P$463") (pinfunction "P$1_P$463") (pintype "power_in"))
      (node (ref "P8") (pin "P$464") (pinfunction "P$1_P$464") (pintype "power_in"))
      (node (ref "P8") (pin "P$465") (pinfunction "P$1_P$465") (pintype "power_in"))
      (node (ref "P8") (pin "P$466") (pinfunction "P$1_P$466") (pintype "power_in"))
      (node (ref "P8") (pin "P$467") (pinfunction "P$1_P$467") (pintype "power_in"))
      (node (ref "P8") (pin "P$468") (pinfunction "P$1_P$468") (pintype "power_in"))
      (node (ref "P8") (pin "P$469") (pinfunction "P$1_P$469") (pintype "power_in"))
      (node (ref "P8") (pin "P$47") (pinfunction "P$1_P$47") (pintype "power_in"))
      (node (ref "P8") (pin "P$470") (pinfunction "P$1_P$470") (pintype "power_in"))
      (node (ref "P8") (pin "P$471") (pinfunction "P$1_P$471") (pintype "power_in"))
      (node (ref "P8") (pin "P$472") (pinfunction "P$1_P$472") (pintype "power_in"))
      (node (ref "P8") (pin "P$473") (pinfunction "P$1_P$473") (pintype "power_in"))
      (node (ref "P8") (pin "P$474") (pinfunction "P$1_P$474") (pintype "power_in"))
      (node (ref "P8") (pin "P$475") (pinfunction "P$1_P$475") (pintype "power_in"))
      (node (ref "P8") (pin "P$476") (pinfunction "P$1_P$476") (pintype "power_in"))
      (node (ref "P8") (pin "P$477") (pinfunction "P$1_P$477") (pintype "power_in"))
      (node (ref "P8") (pin "P$478") (pinfunction "P$1_P$478") (pintype "power_in"))
      (node (ref "P8") (pin "P$479") (pinfunction "P$1_P$479") (pintype "power_in"))
      (node (ref "P8") (pin "P$48") (pinfunction "P$1_P$48") (pintype "power_in"))
      (node (ref "P8") (pin "P$480") (pinfunction "P$1_P$480") (pintype "power_in"))
      (node (ref "P8") (pin "P$481") (pinfunction "P$1_P$481") (pintype "power_in"))
      (node (ref "P8") (pin "P$482") (pinfunction "P$1_P$482") (pintype "power_in"))
      (node (ref "P8") (pin "P$483") (pinfunction "P$1_P$483") (pintype "power_in"))
      (node (ref "P8") (pin "P$484") (pinfunction "P$1_P$484") (pintype "power_in"))
      (node (ref "P8") (pin "P$485") (pinfunction "P$1_P$485") (pintype "power_in"))
      (node (ref "P8") (pin "P$486") (pinfunction "P$1_P$486") (pintype "power_in"))
      (node (ref "P8") (pin "P$487") (pinfunction "P$1_P$487") (pintype "power_in"))
      (node (ref "P8") (pin "P$488") (pinfunction "P$1_P$488") (pintype "power_in"))
      (node (ref "P8") (pin "P$489") (pinfunction "P$1_P$489") (pintype "power_in"))
      (node (ref "P8") (pin "P$49") (pinfunction "P$1_P$49") (pintype "power_in"))
      (node (ref "P8") (pin "P$490") (pinfunction "P$1_P$490") (pintype "power_in"))
      (node (ref "P8") (pin "P$491") (pinfunction "P$1_P$491") (pintype "power_in"))
      (node (ref "P8") (pin "P$492") (pinfunction "P$1_P$492") (pintype "power_in"))
      (node (ref "P8") (pin "P$493") (pinfunction "P$1_P$493") (pintype "power_in"))
      (node (ref "P8") (pin "P$494") (pinfunction "P$1_P$494") (pintype "power_in"))
      (node (ref "P8") (pin "P$495") (pinfunction "P$1_P$495") (pintype "power_in"))
      (node (ref "P8") (pin "P$496") (pinfunction "P$1_P$496") (pintype "power_in"))
      (node (ref "P8") (pin "P$497") (pinfunction "P$1_P$497") (pintype "power_in"))
      (node (ref "P8") (pin "P$498") (pinfunction "P$1_P$498") (pintype "power_in"))
      (node (ref "P8") (pin "P$499") (pinfunction "P$1_P$499") (pintype "power_in"))
      (node (ref "P8") (pin "P$5") (pinfunction "P$1_P$5") (pintype "power_in"))
      (node (ref "P8") (pin "P$50") (pinfunction "P$1_P$50") (pintype "power_in"))
      (node (ref "P8") (pin "P$500") (pinfunction "P$1_P$500") (pintype "power_in"))
      (node (ref "P8") (pin "P$501") (pinfunction "P$1_P$501") (pintype "power_in"))
      (node (ref "P8") (pin "P$502") (pinfunction "P$1_P$502") (pintype "power_in"))
      (node (ref "P8") (pin "P$503") (pinfunction "P$1_P$503") (pintype "power_in"))
      (node (ref "P8") (pin "P$504") (pinfunction "P$1_P$504") (pintype "power_in"))
      (node (ref "P8") (pin "P$505") (pinfunction "P$1_P$505") (pintype "power_in"))
      (node (ref "P8") (pin "P$506") (pinfunction "P$1_P$506") (pintype "power_in"))
      (node (ref "P8") (pin "P$507") (pinfunction "P$1_P$507") (pintype "power_in"))
      (node (ref "P8") (pin "P$508") (pinfunction "P$1_P$508") (pintype "power_in"))
      (node (ref "P8") (pin "P$509") (pinfunction "P$1_P$509") (pintype "power_in"))
      (node (ref "P8") (pin "P$51") (pinfunction "P$1_P$51") (pintype "power_in"))
      (node (ref "P8") (pin "P$510") (pinfunction "P$1_P$510") (pintype "power_in"))
      (node (ref "P8") (pin "P$511") (pinfunction "P$1_P$511") (pintype "power_in"))
      (node (ref "P8") (pin "P$512") (pinfunction "P$1_P$512") (pintype "power_in"))
      (node (ref "P8") (pin "P$513") (pinfunction "P$1_P$513") (pintype "power_in"))
      (node (ref "P8") (pin "P$514") (pinfunction "P$1_P$514") (pintype "power_in"))
      (node (ref "P8") (pin "P$515") (pinfunction "P$1_P$515") (pintype "power_in"))
      (node (ref "P8") (pin "P$516") (pinfunction "P$1_P$516") (pintype "power_in"))
      (node (ref "P8") (pin "P$517") (pinfunction "P$1_P$517") (pintype "power_in"))
      (node (ref "P8") (pin "P$518") (pinfunction "P$1_P$518") (pintype "power_in"))
      (node (ref "P8") (pin "P$519") (pinfunction "P$1_P$519") (pintype "power_in"))
      (node (ref "P8") (pin "P$52") (pinfunction "P$1_P$52") (pintype "power_in"))
      (node (ref "P8") (pin "P$520") (pinfunction "P$1_P$520") (pintype "power_in"))
      (node (ref "P8") (pin "P$521") (pinfunction "P$1_P$521") (pintype "power_in"))
      (node (ref "P8") (pin "P$522") (pinfunction "P$1_P$522") (pintype "power_in"))
      (node (ref "P8") (pin "P$523") (pinfunction "P$1_P$523") (pintype "power_in"))
      (node (ref "P8") (pin "P$524") (pinfunction "P$1_P$524") (pintype "power_in"))
      (node (ref "P8") (pin "P$525") (pinfunction "P$1_P$525") (pintype "power_in"))
      (node (ref "P8") (pin "P$526") (pinfunction "P$1_P$526") (pintype "power_in"))
      (node (ref "P8") (pin "P$527") (pinfunction "P$1_P$527") (pintype "power_in"))
      (node (ref "P8") (pin "P$528") (pinfunction "P$1_P$528") (pintype "power_in"))
      (node (ref "P8") (pin "P$529") (pinfunction "P$1_P$529") (pintype "power_in"))
      (node (ref "P8") (pin "P$53") (pinfunction "P$1_P$53") (pintype "power_in"))
      (node (ref "P8") (pin "P$530") (pinfunction "P$1_P$530") (pintype "power_in"))
      (node (ref "P8") (pin "P$531") (pinfunction "P$1_P$531") (pintype "power_in"))
      (node (ref "P8") (pin "P$532") (pinfunction "P$1_P$532") (pintype "power_in"))
      (node (ref "P8") (pin "P$533") (pinfunction "P$1_P$533") (pintype "power_in"))
      (node (ref "P8") (pin "P$534") (pinfunction "P$1_P$534") (pintype "power_in"))
      (node (ref "P8") (pin "P$535") (pinfunction "P$1_P$535") (pintype "power_in"))
      (node (ref "P8") (pin "P$536") (pinfunction "P$1_P$536") (pintype "power_in"))
      (node (ref "P8") (pin "P$537") (pinfunction "P$1_P$537") (pintype "power_in"))
      (node (ref "P8") (pin "P$538") (pinfunction "P$1_P$538") (pintype "power_in"))
      (node (ref "P8") (pin "P$539") (pinfunction "P$1_P$539") (pintype "power_in"))
      (node (ref "P8") (pin "P$54") (pinfunction "P$1_P$54") (pintype "power_in"))
      (node (ref "P8") (pin "P$540") (pinfunction "P$1_P$540") (pintype "power_in"))
      (node (ref "P8") (pin "P$55") (pinfunction "P$1_P$55") (pintype "power_in"))
      (node (ref "P8") (pin "P$56") (pinfunction "P$1_P$56") (pintype "power_in"))
      (node (ref "P8") (pin "P$57") (pinfunction "P$1_P$57") (pintype "power_in"))
      (node (ref "P8") (pin "P$58") (pinfunction "P$1_P$58") (pintype "power_in"))
      (node (ref "P8") (pin "P$59") (pinfunction "P$1_P$59") (pintype "power_in"))
      (node (ref "P8") (pin "P$6") (pinfunction "P$1_P$6") (pintype "power_in"))
      (node (ref "P8") (pin "P$60") (pinfunction "P$1_P$60") (pintype "power_in"))
      (node (ref "P8") (pin "P$61") (pinfunction "P$1_P$61") (pintype "power_in"))
      (node (ref "P8") (pin "P$62") (pinfunction "P$1_P$62") (pintype "power_in"))
      (node (ref "P8") (pin "P$63") (pinfunction "P$1_P$63") (pintype "power_in"))
      (node (ref "P8") (pin "P$64") (pinfunction "P$1_P$64") (pintype "power_in"))
      (node (ref "P8") (pin "P$65") (pinfunction "P$1_P$65") (pintype "power_in"))
      (node (ref "P8") (pin "P$66") (pinfunction "P$1_P$66") (pintype "power_in"))
      (node (ref "P8") (pin "P$67") (pinfunction "P$1_P$67") (pintype "power_in"))
      (node (ref "P8") (pin "P$68") (pinfunction "P$1_P$68") (pintype "power_in"))
      (node (ref "P8") (pin "P$69") (pinfunction "P$1_P$69") (pintype "power_in"))
      (node (ref "P8") (pin "P$7") (pinfunction "P$1_P$7") (pintype "power_in"))
      (node (ref "P8") (pin "P$70") (pinfunction "P$1_P$70") (pintype "power_in"))
      (node (ref "P8") (pin "P$71") (pinfunction "P$1_P$71") (pintype "power_in"))
      (node (ref "P8") (pin "P$72") (pinfunction "P$1_P$72") (pintype "power_in"))
      (node (ref "P8") (pin "P$73") (pinfunction "P$1_P$73") (pintype "power_in"))
      (node (ref "P8") (pin "P$74") (pinfunction "P$1_P$74") (pintype "power_in"))
      (node (ref "P8") (pin "P$75") (pinfunction "P$1_P$75") (pintype "power_in"))
      (node (ref "P8") (pin "P$76") (pinfunction "P$1_P$76") (pintype "power_in"))
      (node (ref "P8") (pin "P$77") (pinfunction "P$1_P$77") (pintype "power_in"))
      (node (ref "P8") (pin "P$78") (pinfunction "P$1_P$78") (pintype "power_in"))
      (node (ref "P8") (pin "P$79") (pinfunction "P$1_P$79") (pintype "power_in"))
      (node (ref "P8") (pin "P$8") (pinfunction "P$1_P$8") (pintype "power_in"))
      (node (ref "P8") (pin "P$80") (pinfunction "P$1_P$80") (pintype "power_in"))
      (node (ref "P8") (pin "P$81") (pinfunction "P$1_P$81") (pintype "power_in"))
      (node (ref "P8") (pin "P$82") (pinfunction "P$1_P$82") (pintype "power_in"))
      (node (ref "P8") (pin "P$83") (pinfunction "P$1_P$83") (pintype "power_in"))
      (node (ref "P8") (pin "P$84") (pinfunction "P$1_P$84") (pintype "power_in"))
      (node (ref "P8") (pin "P$85") (pinfunction "P$1_P$85") (pintype "power_in"))
      (node (ref "P8") (pin "P$86") (pinfunction "P$1_P$86") (pintype "power_in"))
      (node (ref "P8") (pin "P$87") (pinfunction "P$1_P$87") (pintype "power_in"))
      (node (ref "P8") (pin "P$88") (pinfunction "P$1_P$88") (pintype "power_in"))
      (node (ref "P8") (pin "P$89") (pinfunction "P$1_P$89") (pintype "power_in"))
      (node (ref "P8") (pin "P$9") (pinfunction "P$1_P$9") (pintype "power_in"))
      (node (ref "P8") (pin "P$90") (pinfunction "P$1_P$90") (pintype "power_in"))
      (node (ref "P8") (pin "P$91") (pinfunction "P$1_P$91") (pintype "power_in"))
      (node (ref "P8") (pin "P$92") (pinfunction "P$1_P$92") (pintype "power_in"))
      (node (ref "P8") (pin "P$93") (pinfunction "P$1_P$93") (pintype "power_in"))
      (node (ref "P8") (pin "P$94") (pinfunction "P$1_P$94") (pintype "power_in"))
      (node (ref "P8") (pin "P$95") (pinfunction "P$1_P$95") (pintype "power_in"))
      (node (ref "P8") (pin "P$96") (pinfunction "P$1_P$96") (pintype "power_in"))
      (node (ref "P8") (pin "P$97") (pinfunction "P$1_P$97") (pintype "power_in"))
      (node (ref "P8") (pin "P$98") (pinfunction "P$1_P$98") (pintype "power_in"))
      (node (ref "P8") (pin "P$99") (pinfunction "P$1_P$99") (pintype "power_in"))
    )
    (net (code "10") (name "/P9") (class "Default")
      (node (ref "JP1") (pin "P$10") (pinfunction "9_P$10") (pintype "bidirectional"))
      (node (ref "P9") (pin "P$1") (pinfunction "P$1_P$1") (pintype "power_in"))
      (node (ref "P9") (pin "P$10") (pinfunction "P$1_P$10") (pintype "power_in"))
      (node (ref "P9") (pin "P$100") (pinfunction "P$1_P$100") (pintype "power_in"))
      (node (ref "P9") (pin "P$101") (pinfunction "P$1_P$101") (pintype "power_in"))
      (node (ref "P9") (pin "P$102") (pinfunction "P$1_P$102") (pintype "power_in"))
      (node (ref "P9") (pin "P$103") (pinfunction "P$1_P$103") (pintype "power_in"))
      (node (ref "P9") (pin "P$104") (pinfunction "P$1_P$104") (pintype "power_in"))
      (node (ref "P9") (pin "P$105") (pinfunction "P$1_P$105") (pintype "power_in"))
      (node (ref "P9") (pin "P$106") (pinfunction "P$1_P$106") (pintype "power_in"))
      (node (ref "P9") (pin "P$107") (pinfunction "P$1_P$107") (pintype "power_in"))
      (node (ref "P9") (pin "P$108") (pinfunction "P$1_P$108") (pintype "power_in"))
      (node (ref "P9") (pin "P$109") (pinfunction "P$1_P$109") (pintype "power_in"))
      (node (ref "P9") (pin "P$11") (pinfunction "P$1_P$11") (pintype "power_in"))
      (node (ref "P9") (pin "P$110") (pinfunction "P$1_P$110") (pintype "power_in"))
      (node (ref "P9") (pin "P$111") (pinfunction "P$1_P$111") (pintype "power_in"))
      (node (ref "P9") (pin "P$112") (pinfunction "P$1_P$112") (pintype "power_in"))
      (node (ref "P9") (pin "P$113") (pinfunction "P$1_P$113") (pintype "power_in"))
      (node (ref "P9") (pin "P$114") (pinfunction "P$1_P$114") (pintype "power_in"))
      (node (ref "P9") (pin "P$115") (pinfunction "P$1_P$115") (pintype "power_in"))
      (node (ref "P9") (pin "P$116") (pinfunction "P$1_P$116") (pintype "power_in"))
      (node (ref "P9") (pin "P$117") (pinfunction "P$1_P$117") (pintype "power_in"))
      (node (ref "P9") (pin "P$118") (pinfunction "P$1_P$118") (pintype "power_in"))
      (node (ref "P9") (pin "P$119") (pinfunction "P$1_P$119") (pintype "power_in"))
      (node (ref "P9") (pin "P$12") (pinfunction "P$1_P$12") (pintype "power_in"))
      (node (ref "P9") (pin "P$120") (pinfunction "P$1_P$120") (pintype "power_in"))
      (node (ref "P9") (pin "P$121") (pinfunction "P$1_P$121") (pintype "power_in"))
      (node (ref "P9") (pin "P$122") (pinfunction "P$1_P$122") (pintype "power_in"))
      (node (ref "P9") (pin "P$123") (pinfunction "P$1_P$123") (pintype "power_in"))
      (node (ref "P9") (pin "P$124") (pinfunction "P$1_P$124") (pintype "power_in"))
      (node (ref "P9") (pin "P$125") (pinfunction "P$1_P$125") (pintype "power_in"))
      (node (ref "P9") (pin "P$126") (pinfunction "P$1_P$126") (pintype "power_in"))
      (node (ref "P9") (pin "P$127") (pinfunction "P$1_P$127") (pintype "power_in"))
      (node (ref "P9") (pin "P$128") (pinfunction "P$1_P$128") (pintype "power_in"))
      (node (ref "P9") (pin "P$129") (pinfunction "P$1_P$129") (pintype "power_in"))
      (node (ref "P9") (pin "P$13") (pinfunction "P$1_P$13") (pintype "power_in"))
      (node (ref "P9") (pin "P$130") (pinfunction "P$1_P$130") (pintype "power_in"))
      (node (ref "P9") (pin "P$131") (pinfunction "P$1_P$131") (pintype "power_in"))
      (node (ref "P9") (pin "P$132") (pinfunction "P$1_P$132") (pintype "power_in"))
      (node (ref "P9") (pin "P$133") (pinfunction "P$1_P$133") (pintype "power_in"))
      (node (ref "P9") (pin "P$134") (pinfunction "P$1_P$134") (pintype "power_in"))
      (node (ref "P9") (pin "P$135") (pinfunction "P$1_P$135") (pintype "power_in"))
      (node (ref "P9") (pin "P$136") (pinfunction "P$1_P$136") (pintype "power_in"))
      (node (ref "P9") (pin "P$137") (pinfunction "P$1_P$137") (pintype "power_in"))
      (node (ref "P9") (pin "P$138") (pinfunction "P$1_P$138") (pintype "power_in"))
      (node (ref "P9") (pin "P$139") (pinfunction "P$1_P$139") (pintype "power_in"))
      (node (ref "P9") (pin "P$14") (pinfunction "P$1_P$14") (pintype "power_in"))
      (node (ref "P9") (pin "P$140") (pinfunction "P$1_P$140") (pintype "power_in"))
      (node (ref "P9") (pin "P$141") (pinfunction "P$1_P$141") (pintype "power_in"))
      (node (ref "P9") (pin "P$142") (pinfunction "P$1_P$142") (pintype "power_in"))
      (node (ref "P9") (pin "P$143") (pinfunction "P$1_P$143") (pintype "power_in"))
      (node (ref "P9") (pin "P$144") (pinfunction "P$1_P$144") (pintype "power_in"))
      (node (ref "P9") (pin "P$145") (pinfunction "P$1_P$145") (pintype "power_in"))
      (node (ref "P9") (pin "P$146") (pinfunction "P$1_P$146") (pintype "power_in"))
      (node (ref "P9") (pin "P$147") (pinfunction "P$1_P$147") (pintype "power_in"))
      (node (ref "P9") (pin "P$148") (pinfunction "P$1_P$148") (pintype "power_in"))
      (node (ref "P9") (pin "P$149") (pinfunction "P$1_P$149") (pintype "power_in"))
      (node (ref "P9") (pin "P$15") (pinfunction "P$1_P$15") (pintype "power_in"))
      (node (ref "P9") (pin "P$150") (pinfunction "P$1_P$150") (pintype "power_in"))
      (node (ref "P9") (pin "P$151") (pinfunction "P$1_P$151") (pintype "power_in"))
      (node (ref "P9") (pin "P$152") (pinfunction "P$1_P$152") (pintype "power_in"))
      (node (ref "P9") (pin "P$153") (pinfunction "P$1_P$153") (pintype "power_in"))
      (node (ref "P9") (pin "P$154") (pinfunction "P$1_P$154") (pintype "power_in"))
      (node (ref "P9") (pin "P$155") (pinfunction "P$1_P$155") (pintype "power_in"))
      (node (ref "P9") (pin "P$156") (pinfunction "P$1_P$156") (pintype "power_in"))
      (node (ref "P9") (pin "P$157") (pinfunction "P$1_P$157") (pintype "power_in"))
      (node (ref "P9") (pin "P$158") (pinfunction "P$1_P$158") (pintype "power_in"))
      (node (ref "P9") (pin "P$159") (pinfunction "P$1_P$159") (pintype "power_in"))
      (node (ref "P9") (pin "P$16") (pinfunction "P$1_P$16") (pintype "power_in"))
      (node (ref "P9") (pin "P$160") (pinfunction "P$1_P$160") (pintype "power_in"))
      (node (ref "P9") (pin "P$161") (pinfunction "P$1_P$161") (pintype "power_in"))
      (node (ref "P9") (pin "P$162") (pinfunction "P$1_P$162") (pintype "power_in"))
      (node (ref "P9") (pin "P$163") (pinfunction "P$1_P$163") (pintype "power_in"))
      (node (ref "P9") (pin "P$164") (pinfunction "P$1_P$164") (pintype "power_in"))
      (node (ref "P9") (pin "P$165") (pinfunction "P$1_P$165") (pintype "power_in"))
      (node (ref "P9") (pin "P$166") (pinfunction "P$1_P$166") (pintype "power_in"))
      (node (ref "P9") (pin "P$167") (pinfunction "P$1_P$167") (pintype "power_in"))
      (node (ref "P9") (pin "P$168") (pinfunction "P$1_P$168") (pintype "power_in"))
      (node (ref "P9") (pin "P$169") (pinfunction "P$1_P$169") (pintype "power_in"))
      (node (ref "P9") (pin "P$17") (pinfunction "P$1_P$17") (pintype "power_in"))
      (node (ref "P9") (pin "P$170") (pinfunction "P$1_P$170") (pintype "power_in"))
      (node (ref "P9") (pin "P$171") (pinfunction "P$1_P$171") (pintype "power_in"))
      (node (ref "P9") (pin "P$172") (pinfunction "P$1_P$172") (pintype "power_in"))
      (node (ref "P9") (pin "P$173") (pinfunction "P$1_P$173") (pintype "power_in"))
      (node (ref "P9") (pin "P$174") (pinfunction "P$1_P$174") (pintype "power_in"))
      (node (ref "P9") (pin "P$175") (pinfunction "P$1_P$175") (pintype "power_in"))
      (node (ref "P9") (pin "P$176") (pinfunction "P$1_P$176") (pintype "power_in"))
      (node (ref "P9") (pin "P$177") (pinfunction "P$1_P$177") (pintype "power_in"))
      (node (ref "P9") (pin "P$178") (pinfunction "P$1_P$178") (pintype "power_in"))
      (node (ref "P9") (pin "P$179") (pinfunction "P$1_P$179") (pintype "power_in"))
      (node (ref "P9") (pin "P$18") (pinfunction "P$1_P$18") (pintype "power_in"))
      (node (ref "P9") (pin "P$180") (pinfunction "P$1_P$180") (pintype "power_in"))
      (node (ref "P9") (pin "P$181") (pinfunction "P$1_P$181") (pintype "power_in"))
      (node (ref "P9") (pin "P$182") (pinfunction "P$1_P$182") (pintype "power_in"))
      (node (ref "P9") (pin "P$183") (pinfunction "P$1_P$183") (pintype "power_in"))
      (node (ref "P9") (pin "P$184") (pinfunction "P$1_P$184") (pintype "power_in"))
      (node (ref "P9") (pin "P$185") (pinfunction "P$1_P$185") (pintype "power_in"))
      (node (ref "P9") (pin "P$186") (pinfunction "P$1_P$186") (pintype "power_in"))
      (node (ref "P9") (pin "P$187") (pinfunction "P$1_P$187") (pintype "power_in"))
      (node (ref "P9") (pin "P$188") (pinfunction "P$1_P$188") (pintype "power_in"))
      (node (ref "P9") (pin "P$189") (pinfunction "P$1_P$189") (pintype "power_in"))
      (node (ref "P9") (pin "P$19") (pinfunction "P$1_P$19") (pintype "power_in"))
      (node (ref "P9") (pin "P$190") (pinfunction "P$1_P$190") (pintype "power_in"))
      (node (ref "P9") (pin "P$191") (pinfunction "P$1_P$191") (pintype "power_in"))
      (node (ref "P9") (pin "P$192") (pinfunction "P$1_P$192") (pintype "power_in"))
      (node (ref "P9") (pin "P$193") (pinfunction "P$1_P$193") (pintype "power_in"))
      (node (ref "P9") (pin "P$194") (pinfunction "P$1_P$194") (pintype "power_in"))
      (node (ref "P9") (pin "P$195") (pinfunction "P$1_P$195") (pintype "power_in"))
      (node (ref "P9") (pin "P$196") (pinfunction "P$1_P$196") (pintype "power_in"))
      (node (ref "P9") (pin "P$197") (pinfunction "P$1_P$197") (pintype "power_in"))
      (node (ref "P9") (pin "P$198") (pinfunction "P$1_P$198") (pintype "power_in"))
      (node (ref "P9") (pin "P$199") (pinfunction "P$1_P$199") (pintype "power_in"))
      (node (ref "P9") (pin "P$2") (pinfunction "P$1_P$2") (pintype "power_in"))
      (node (ref "P9") (pin "P$20") (pinfunction "P$1_P$20") (pintype "power_in"))
      (node (ref "P9") (pin "P$200") (pinfunction "P$1_P$200") (pintype "power_in"))
      (node (ref "P9") (pin "P$201") (pinfunction "P$1_P$201") (pintype "power_in"))
      (node (ref "P9") (pin "P$202") (pinfunction "P$1_P$202") (pintype "power_in"))
      (node (ref "P9") (pin "P$203") (pinfunction "P$1_P$203") (pintype "power_in"))
      (node (ref "P9") (pin "P$204") (pinfunction "P$1_P$204") (pintype "power_in"))
      (node (ref "P9") (pin "P$205") (pinfunction "P$1_P$205") (pintype "power_in"))
      (node (ref "P9") (pin "P$206") (pinfunction "P$1_P$206") (pintype "power_in"))
      (node (ref "P9") (pin "P$207") (pinfunction "P$1_P$207") (pintype "power_in"))
      (node (ref "P9") (pin "P$208") (pinfunction "P$1_P$208") (pintype "power_in"))
      (node (ref "P9") (pin "P$209") (pinfunction "P$1_P$209") (pintype "power_in"))
      (node (ref "P9") (pin "P$21") (pinfunction "P$1_P$21") (pintype "power_in"))
      (node (ref "P9") (pin "P$210") (pinfunction "P$1_P$210") (pintype "power_in"))
      (node (ref "P9") (pin "P$211") (pinfunction "P$1_P$211") (pintype "power_in"))
      (node (ref "P9") (pin "P$212") (pinfunction "P$1_P$212") (pintype "power_in"))
      (node (ref "P9") (pin "P$213") (pinfunction "P$1_P$213") (pintype "power_in"))
      (node (ref "P9") (pin "P$214") (pinfunction "P$1_P$214") (pintype "power_in"))
      (node (ref "P9") (pin "P$215") (pinfunction "P$1_P$215") (pintype "power_in"))
      (node (ref "P9") (pin "P$216") (pinfunction "P$1_P$216") (pintype "power_in"))
      (node (ref "P9") (pin "P$217") (pinfunction "P$1_P$217") (pintype "power_in"))
      (node (ref "P9") (pin "P$218") (pinfunction "P$1_P$218") (pintype "power_in"))
      (node (ref "P9") (pin "P$219") (pinfunction "P$1_P$219") (pintype "power_in"))
      (node (ref "P9") (pin "P$22") (pinfunction "P$1_P$22") (pintype "power_in"))
      (node (ref "P9") (pin "P$220") (pinfunction "P$1_P$220") (pintype "power_in"))
      (node (ref "P9") (pin "P$221") (pinfunction "P$1_P$221") (pintype "power_in"))
      (node (ref "P9") (pin "P$222") (pinfunction "P$1_P$222") (pintype "power_in"))
      (node (ref "P9") (pin "P$223") (pinfunction "P$1_P$223") (pintype "power_in"))
      (node (ref "P9") (pin "P$224") (pinfunction "P$1_P$224") (pintype "power_in"))
      (node (ref "P9") (pin "P$225") (pinfunction "P$1_P$225") (pintype "power_in"))
      (node (ref "P9") (pin "P$226") (pinfunction "P$1_P$226") (pintype "power_in"))
      (node (ref "P9") (pin "P$227") (pinfunction "P$1_P$227") (pintype "power_in"))
      (node (ref "P9") (pin "P$228") (pinfunction "P$1_P$228") (pintype "power_in"))
      (node (ref "P9") (pin "P$229") (pinfunction "P$1_P$229") (pintype "power_in"))
      (node (ref "P9") (pin "P$23") (pinfunction "P$1_P$23") (pintype "power_in"))
      (node (ref "P9") (pin "P$230") (pinfunction "P$1_P$230") (pintype "power_in"))
      (node (ref "P9") (pin "P$231") (pinfunction "P$1_P$231") (pintype "power_in"))
      (node (ref "P9") (pin "P$232") (pinfunction "P$1_P$232") (pintype "power_in"))
      (node (ref "P9") (pin "P$233") (pinfunction "P$1_P$233") (pintype "power_in"))
      (node (ref "P9") (pin "P$234") (pinfunction "P$1_P$234") (pintype "power_in"))
      (node (ref "P9") (pin "P$235") (pinfunction "P$1_P$235") (pintype "power_in"))
      (node (ref "P9") (pin "P$236") (pinfunction "P$1_P$236") (pintype "power_in"))
      (node (ref "P9") (pin "P$237") (pinfunction "P$1_P$237") (pintype "power_in"))
      (node (ref "P9") (pin "P$238") (pinfunction "P$1_P$238") (pintype "power_in"))
      (node (ref "P9") (pin "P$239") (pinfunction "P$1_P$239") (pintype "power_in"))
      (node (ref "P9") (pin "P$24") (pinfunction "P$1_P$24") (pintype "power_in"))
      (node (ref "P9") (pin "P$240") (pinfunction "P$1_P$240") (pintype "power_in"))
      (node (ref "P9") (pin "P$241") (pinfunction "P$1_P$241") (pintype "power_in"))
      (node (ref "P9") (pin "P$242") (pinfunction "P$1_P$242") (pintype "power_in"))
      (node (ref "P9") (pin "P$243") (pinfunction "P$1_P$243") (pintype "power_in"))
      (node (ref "P9") (pin "P$244") (pinfunction "P$1_P$244") (pintype "power_in"))
      (node (ref "P9") (pin "P$245") (pinfunction "P$1_P$245") (pintype "power_in"))
      (node (ref "P9") (pin "P$246") (pinfunction "P$1_P$246") (pintype "power_in"))
      (node (ref "P9") (pin "P$247") (pinfunction "P$1_P$247") (pintype "power_in"))
      (node (ref "P9") (pin "P$248") (pinfunction "P$1_P$248") (pintype "power_in"))
      (node (ref "P9") (pin "P$249") (pinfunction "P$1_P$249") (pintype "power_in"))
      (node (ref "P9") (pin "P$25") (pinfunction "P$1_P$25") (pintype "power_in"))
      (node (ref "P9") (pin "P$250") (pinfunction "P$1_P$250") (pintype "power_in"))
      (node (ref "P9") (pin "P$251") (pinfunction "P$1_P$251") (pintype "power_in"))
      (node (ref "P9") (pin "P$252") (pinfunction "P$1_P$252") (pintype "power_in"))
      (node (ref "P9") (pin "P$253") (pinfunction "P$1_P$253") (pintype "power_in"))
      (node (ref "P9") (pin "P$254") (pinfunction "P$1_P$254") (pintype "power_in"))
      (node (ref "P9") (pin "P$255") (pinfunction "P$1_P$255") (pintype "power_in"))
      (node (ref "P9") (pin "P$256") (pinfunction "P$1_P$256") (pintype "power_in"))
      (node (ref "P9") (pin "P$257") (pinfunction "P$1_P$257") (pintype "power_in"))
      (node (ref "P9") (pin "P$258") (pinfunction "P$1_P$258") (pintype "power_in"))
      (node (ref "P9") (pin "P$259") (pinfunction "P$1_P$259") (pintype "power_in"))
      (node (ref "P9") (pin "P$26") (pinfunction "P$1_P$26") (pintype "power_in"))
      (node (ref "P9") (pin "P$260") (pinfunction "P$1_P$260") (pintype "power_in"))
      (node (ref "P9") (pin "P$261") (pinfunction "P$1_P$261") (pintype "power_in"))
      (node (ref "P9") (pin "P$262") (pinfunction "P$1_P$262") (pintype "power_in"))
      (node (ref "P9") (pin "P$263") (pinfunction "P$1_P$263") (pintype "power_in"))
      (node (ref "P9") (pin "P$264") (pinfunction "P$1_P$264") (pintype "power_in"))
      (node (ref "P9") (pin "P$265") (pinfunction "P$1_P$265") (pintype "power_in"))
      (node (ref "P9") (pin "P$266") (pinfunction "P$1_P$266") (pintype "power_in"))
      (node (ref "P9") (pin "P$267") (pinfunction "P$1_P$267") (pintype "power_in"))
      (node (ref "P9") (pin "P$268") (pinfunction "P$1_P$268") (pintype "power_in"))
      (node (ref "P9") (pin "P$269") (pinfunction "P$1_P$269") (pintype "power_in"))
      (node (ref "P9") (pin "P$27") (pinfunction "P$1_P$27") (pintype "power_in"))
      (node (ref "P9") (pin "P$270") (pinfunction "P$1_P$270") (pintype "power_in"))
      (node (ref "P9") (pin "P$271") (pinfunction "P$1_P$271") (pintype "power_in"))
      (node (ref "P9") (pin "P$272") (pinfunction "P$1_P$272") (pintype "power_in"))
      (node (ref "P9") (pin "P$273") (pinfunction "P$1_P$273") (pintype "power_in"))
      (node (ref "P9") (pin "P$274") (pinfunction "P$1_P$274") (pintype "power_in"))
      (node (ref "P9") (pin "P$275") (pinfunction "P$1_P$275") (pintype "power_in"))
      (node (ref "P9") (pin "P$276") (pinfunction "P$1_P$276") (pintype "power_in"))
      (node (ref "P9") (pin "P$277") (pinfunction "P$1_P$277") (pintype "power_in"))
      (node (ref "P9") (pin "P$278") (pinfunction "P$1_P$278") (pintype "power_in"))
      (node (ref "P9") (pin "P$279") (pinfunction "P$1_P$279") (pintype "power_in"))
      (node (ref "P9") (pin "P$28") (pinfunction "P$1_P$28") (pintype "power_in"))
      (node (ref "P9") (pin "P$280") (pinfunction "P$1_P$280") (pintype "power_in"))
      (node (ref "P9") (pin "P$281") (pinfunction "P$1_P$281") (pintype "power_in"))
      (node (ref "P9") (pin "P$282") (pinfunction "P$1_P$282") (pintype "power_in"))
      (node (ref "P9") (pin "P$283") (pinfunction "P$1_P$283") (pintype "power_in"))
      (node (ref "P9") (pin "P$284") (pinfunction "P$1_P$284") (pintype "power_in"))
      (node (ref "P9") (pin "P$285") (pinfunction "P$1_P$285") (pintype "power_in"))
      (node (ref "P9") (pin "P$286") (pinfunction "P$1_P$286") (pintype "power_in"))
      (node (ref "P9") (pin "P$287") (pinfunction "P$1_P$287") (pintype "power_in"))
      (node (ref "P9") (pin "P$288") (pinfunction "P$1_P$288") (pintype "power_in"))
      (node (ref "P9") (pin "P$29") (pinfunction "P$1_P$29") (pintype "power_in"))
      (node (ref "P9") (pin "P$3") (pinfunction "P$1_P$3") (pintype "power_in"))
      (node (ref "P9") (pin "P$30") (pinfunction "P$1_P$30") (pintype "power_in"))
      (node (ref "P9") (pin "P$31") (pinfunction "P$1_P$31") (pintype "power_in"))
      (node (ref "P9") (pin "P$32") (pinfunction "P$1_P$32") (pintype "power_in"))
      (node (ref "P9") (pin "P$33") (pinfunction "P$1_P$33") (pintype "power_in"))
      (node (ref "P9") (pin "P$34") (pinfunction "P$1_P$34") (pintype "power_in"))
      (node (ref "P9") (pin "P$35") (pinfunction "P$1_P$35") (pintype "power_in"))
      (node (ref "P9") (pin "P$36") (pinfunction "P$1_P$36") (pintype "power_in"))
      (node (ref "P9") (pin "P$37") (pinfunction "P$1_P$37") (pintype "power_in"))
      (node (ref "P9") (pin "P$38") (pinfunction "P$1_P$38") (pintype "power_in"))
      (node (ref "P9") (pin "P$39") (pinfunction "P$1_P$39") (pintype "power_in"))
      (node (ref "P9") (pin "P$4") (pinfunction "P$1_P$4") (pintype "power_in"))
      (node (ref "P9") (pin "P$40") (pinfunction "P$1_P$40") (pintype "power_in"))
      (node (ref "P9") (pin "P$41") (pinfunction "P$1_P$41") (pintype "power_in"))
      (node (ref "P9") (pin "P$42") (pinfunction "P$1_P$42") (pintype "power_in"))
      (node (ref "P9") (pin "P$43") (pinfunction "P$1_P$43") (pintype "power_in"))
      (node (ref "P9") (pin "P$44") (pinfunction "P$1_P$44") (pintype "power_in"))
      (node (ref "P9") (pin "P$45") (pinfunction "P$1_P$45") (pintype "power_in"))
      (node (ref "P9") (pin "P$46") (pinfunction "P$1_P$46") (pintype "power_in"))
      (node (ref "P9") (pin "P$47") (pinfunction "P$1_P$47") (pintype "power_in"))
      (node (ref "P9") (pin "P$48") (pinfunction "P$1_P$48") (pintype "power_in"))
      (node (ref "P9") (pin "P$49") (pinfunction "P$1_P$49") (pintype "power_in"))
      (node (ref "P9") (pin "P$5") (pinfunction "P$1_P$5") (pintype "power_in"))
      (node (ref "P9") (pin "P$50") (pinfunction "P$1_P$50") (pintype "power_in"))
      (node (ref "P9") (pin "P$51") (pinfunction "P$1_P$51") (pintype "power_in"))
      (node (ref "P9") (pin "P$52") (pinfunction "P$1_P$52") (pintype "power_in"))
      (node (ref "P9") (pin "P$53") (pinfunction "P$1_P$53") (pintype "power_in"))
      (node (ref "P9") (pin "P$54") (pinfunction "P$1_P$54") (pintype "power_in"))
      (node (ref "P9") (pin "P$55") (pinfunction "P$1_P$55") (pintype "power_in"))
      (node (ref "P9") (pin "P$56") (pinfunction "P$1_P$56") (pintype "power_in"))
      (node (ref "P9") (pin "P$57") (pinfunction "P$1_P$57") (pintype "power_in"))
      (node (ref "P9") (pin "P$58") (pinfunction "P$1_P$58") (pintype "power_in"))
      (node (ref "P9") (pin "P$59") (pinfunction "P$1_P$59") (pintype "power_in"))
      (node (ref "P9") (pin "P$6") (pinfunction "P$1_P$6") (pintype "power_in"))
      (node (ref "P9") (pin "P$60") (pinfunction "P$1_P$60") (pintype "power_in"))
      (node (ref "P9") (pin "P$61") (pinfunction "P$1_P$61") (pintype "power_in"))
      (node (ref "P9") (pin "P$62") (pinfunction "P$1_P$62") (pintype "power_in"))
      (node (ref "P9") (pin "P$63") (pinfunction "P$1_P$63") (pintype "power_in"))
      (node (ref "P9") (pin "P$64") (pinfunction "P$1_P$64") (pintype "power_in"))
      (node (ref "P9") (pin "P$65") (pinfunction "P$1_P$65") (pintype "power_in"))
      (node (ref "P9") (pin "P$66") (pinfunction "P$1_P$66") (pintype "power_in"))
      (node (ref "P9") (pin "P$67") (pinfunction "P$1_P$67") (pintype "power_in"))
      (node (ref "P9") (pin "P$68") (pinfunction "P$1_P$68") (pintype "power_in"))
      (node (ref "P9") (pin "P$69") (pinfunction "P$1_P$69") (pintype "power_in"))
      (node (ref "P9") (pin "P$7") (pinfunction "P$1_P$7") (pintype "power_in"))
      (node (ref "P9") (pin "P$70") (pinfunction "P$1_P$70") (pintype "power_in"))
      (node (ref "P9") (pin "P$71") (pinfunction "P$1_P$71") (pintype "power_in"))
      (node (ref "P9") (pin "P$72") (pinfunction "P$1_P$72") (pintype "power_in"))
      (node (ref "P9") (pin "P$73") (pinfunction "P$1_P$73") (pintype "power_in"))
      (node (ref "P9") (pin "P$74") (pinfunction "P$1_P$74") (pintype "power_in"))
      (node (ref "P9") (pin "P$75") (pinfunction "P$1_P$75") (pintype "power_in"))
      (node (ref "P9") (pin "P$76") (pinfunction "P$1_P$76") (pintype "power_in"))
      (node (ref "P9") (pin "P$77") (pinfunction "P$1_P$77") (pintype "power_in"))
      (node (ref "P9") (pin "P$78") (pinfunction "P$1_P$78") (pintype "power_in"))
      (node (ref "P9") (pin "P$79") (pinfunction "P$1_P$79") (pintype "power_in"))
      (node (ref "P9") (pin "P$8") (pinfunction "P$1_P$8") (pintype "power_in"))
      (node (ref "P9") (pin "P$80") (pinfunction "P$1_P$80") (pintype "power_in"))
      (node (ref "P9") (pin "P$81") (pinfunction "P$1_P$81") (pintype "power_in"))
      (node (ref "P9") (pin "P$82") (pinfunction "P$1_P$82") (pintype "power_in"))
      (node (ref "P9") (pin "P$83") (pinfunction "P$1_P$83") (pintype "power_in"))
      (node (ref "P9") (pin "P$84") (pinfunction "P$1_P$84") (pintype "power_in"))
      (node (ref "P9") (pin "P$85") (pinfunction "P$1_P$85") (pintype "power_in"))
      (node (ref "P9") (pin "P$86") (pinfunction "P$1_P$86") (pintype "power_in"))
      (node (ref "P9") (pin "P$87") (pinfunction "P$1_P$87") (pintype "power_in"))
      (node (ref "P9") (pin "P$88") (pinfunction "P$1_P$88") (pintype "power_in"))
      (node (ref "P9") (pin "P$89") (pinfunction "P$1_P$89") (pintype "power_in"))
      (node (ref "P9") (pin "P$9") (pinfunction "P$1_P$9") (pintype "power_in"))
      (node (ref "P9") (pin "P$90") (pinfunction "P$1_P$90") (pintype "power_in"))
      (node (ref "P9") (pin "P$91") (pinfunction "P$1_P$91") (pintype "power_in"))
      (node (ref "P9") (pin "P$92") (pinfunction "P$1_P$92") (pintype "power_in"))
      (node (ref "P9") (pin "P$93") (pinfunction "P$1_P$93") (pintype "power_in"))
      (node (ref "P9") (pin "P$94") (pinfunction "P$1_P$94") (pintype "power_in"))
      (node (ref "P9") (pin "P$95") (pinfunction "P$1_P$95") (pintype "power_in"))
      (node (ref "P9") (pin "P$96") (pinfunction "P$1_P$96") (pintype "power_in"))
      (node (ref "P9") (pin "P$97") (pinfunction "P$1_P$97") (pintype "power_in"))
      (node (ref "P9") (pin "P$98") (pinfunction "P$1_P$98") (pintype "power_in"))
      (node (ref "P9") (pin "P$99") (pinfunction "P$1_P$99") (pintype "power_in"))
    )
    (net (code "11") (name "/P10") (class "Default")
      (node (ref "JP1") (pin "P$11") (pinfunction "10_P$11") (pintype "bidirectional"))
      (node (ref "P10") (pin "P$1") (pinfunction "P$1_P$1") (pintype "power_in"))
      (node (ref "P10") (pin "P$10") (pinfunction "P$1_P$10") (pintype "power_in"))
      (node (ref "P10") (pin "P$100") (pinfunction "P$1_P$100") (pintype "power_in"))
      (node (ref "P10") (pin "P$101") (pinfunction "P$1_P$101") (pintype "power_in"))
      (node (ref "P10") (pin "P$102") (pinfunction "P$1_P$102") (pintype "power_in"))
      (node (ref "P10") (pin "P$103") (pinfunction "P$1_P$103") (pintype "power_in"))
      (node (ref "P10") (pin "P$104") (pinfunction "P$1_P$104") (pintype "power_in"))
      (node (ref "P10") (pin "P$105") (pinfunction "P$1_P$105") (pintype "power_in"))
      (node (ref "P10") (pin "P$106") (pinfunction "P$1_P$106") (pintype "power_in"))
      (node (ref "P10") (pin "P$107") (pinfunction "P$1_P$107") (pintype "power_in"))
      (node (ref "P10") (pin "P$108") (pinfunction "P$1_P$108") (pintype "power_in"))
      (node (ref "P10") (pin "P$109") (pinfunction "P$1_P$109") (pintype "power_in"))
      (node (ref "P10") (pin "P$11") (pinfunction "P$1_P$11") (pintype "power_in"))
      (node (ref "P10") (pin "P$110") (pinfunction "P$1_P$110") (pintype "power_in"))
      (node (ref "P10") (pin "P$111") (pinfunction "P$1_P$111") (pintype "power_in"))
      (node (ref "P10") (pin "P$112") (pinfunction "P$1_P$112") (pintype "power_in"))
      (node (ref "P10") (pin "P$113") (pinfunction "P$1_P$113") (pintype "power_in"))
      (node (ref "P10") (pin "P$114") (pinfunction "P$1_P$114") (pintype "power_in"))
      (node (ref "P10") (pin "P$115") (pinfunction "P$1_P$115") (pintype "power_in"))
      (node (ref "P10") (pin "P$116") (pinfunction "P$1_P$116") (pintype "power_in"))
      (node (ref "P10") (pin "P$117") (pinfunction "P$1_P$117") (pintype "power_in"))
      (node (ref "P10") (pin "P$118") (pinfunction "P$1_P$118") (pintype "power_in"))
      (node (ref "P10") (pin "P$119") (pinfunction "P$1_P$119") (pintype "power_in"))
      (node (ref "P10") (pin "P$12") (pinfunction "P$1_P$12") (pintype "power_in"))
      (node (ref "P10") (pin "P$120") (pinfunction "P$1_P$120") (pintype "power_in"))
      (node (ref "P10") (pin "P$121") (pinfunction "P$1_P$121") (pintype "power_in"))
      (node (ref "P10") (pin "P$122") (pinfunction "P$1_P$122") (pintype "power_in"))
      (node (ref "P10") (pin "P$123") (pinfunction "P$1_P$123") (pintype "power_in"))
      (node (ref "P10") (pin "P$124") (pinfunction "P$1_P$124") (pintype "power_in"))
      (node (ref "P10") (pin "P$125") (pinfunction "P$1_P$125") (pintype "power_in"))
      (node (ref "P10") (pin "P$126") (pinfunction "P$1_P$126") (pintype "power_in"))
      (node (ref "P10") (pin "P$127") (pinfunction "P$1_P$127") (pintype "power_in"))
      (node (ref "P10") (pin "P$128") (pinfunction "P$1_P$128") (pintype "power_in"))
      (node (ref "P10") (pin "P$129") (pinfunction "P$1_P$129") (pintype "power_in"))
      (node (ref "P10") (pin "P$13") (pinfunction "P$1_P$13") (pintype "power_in"))
      (node (ref "P10") (pin "P$130") (pinfunction "P$1_P$130") (pintype "power_in"))
      (node (ref "P10") (pin "P$131") (pinfunction "P$1_P$131") (pintype "power_in"))
      (node (ref "P10") (pin "P$132") (pinfunction "P$1_P$132") (pintype "power_in"))
      (node (ref "P10") (pin "P$133") (pinfunction "P$1_P$133") (pintype "power_in"))
      (node (ref "P10") (pin "P$134") (pinfunction "P$1_P$134") (pintype "power_in"))
      (node (ref "P10") (pin "P$135") (pinfunction "P$1_P$135") (pintype "power_in"))
      (node (ref "P10") (pin "P$136") (pinfunction "P$1_P$136") (pintype "power_in"))
      (node (ref "P10") (pin "P$137") (pinfunction "P$1_P$137") (pintype "power_in"))
      (node (ref "P10") (pin "P$138") (pinfunction "P$1_P$138") (pintype "power_in"))
      (node (ref "P10") (pin "P$139") (pinfunction "P$1_P$139") (pintype "power_in"))
      (node (ref "P10") (pin "P$14") (pinfunction "P$1_P$14") (pintype "power_in"))
      (node (ref "P10") (pin "P$140") (pinfunction "P$1_P$140") (pintype "power_in"))
      (node (ref "P10") (pin "P$141") (pinfunction "P$1_P$141") (pintype "power_in"))
      (node (ref "P10") (pin "P$142") (pinfunction "P$1_P$142") (pintype "power_in"))
      (node (ref "P10") (pin "P$143") (pinfunction "P$1_P$143") (pintype "power_in"))
      (node (ref "P10") (pin "P$144") (pinfunction "P$1_P$144") (pintype "power_in"))
      (node (ref "P10") (pin "P$145") (pinfunction "P$1_P$145") (pintype "power_in"))
      (node (ref "P10") (pin "P$146") (pinfunction "P$1_P$146") (pintype "power_in"))
      (node (ref "P10") (pin "P$147") (pinfunction "P$1_P$147") (pintype "power_in"))
      (node (ref "P10") (pin "P$148") (pinfunction "P$1_P$148") (pintype "power_in"))
      (node (ref "P10") (pin "P$149") (pinfunction "P$1_P$149") (pintype "power_in"))
      (node (ref "P10") (pin "P$15") (pinfunction "P$1_P$15") (pintype "power_in"))
      (node (ref "P10") (pin "P$150") (pinfunction "P$1_P$150") (pintype "power_in"))
      (node (ref "P10") (pin "P$151") (pinfunction "P$1_P$151") (pintype "power_in"))
      (node (ref "P10") (pin "P$152") (pinfunction "P$1_P$152") (pintype "power_in"))
      (node (ref "P10") (pin "P$153") (pinfunction "P$1_P$153") (pintype "power_in"))
      (node (ref "P10") (pin "P$154") (pinfunction "P$1_P$154") (pintype "power_in"))
      (node (ref "P10") (pin "P$155") (pinfunction "P$1_P$155") (pintype "power_in"))
      (node (ref "P10") (pin "P$156") (pinfunction "P$1_P$156") (pintype "power_in"))
      (node (ref "P10") (pin "P$157") (pinfunction "P$1_P$157") (pintype "power_in"))
      (node (ref "P10") (pin "P$158") (pinfunction "P$1_P$158") (pintype "power_in"))
      (node (ref "P10") (pin "P$159") (pinfunction "P$1_P$159") (pintype "power_in"))
      (node (ref "P10") (pin "P$16") (pinfunction "P$1_P$16") (pintype "power_in"))
      (node (ref "P10") (pin "P$160") (pinfunction "P$1_P$160") (pintype "power_in"))
      (node (ref "P10") (pin "P$161") (pinfunction "P$1_P$161") (pintype "power_in"))
      (node (ref "P10") (pin "P$162") (pinfunction "P$1_P$162") (pintype "power_in"))
      (node (ref "P10") (pin "P$163") (pinfunction "P$1_P$163") (pintype "power_in"))
      (node (ref "P10") (pin "P$164") (pinfunction "P$1_P$164") (pintype "power_in"))
      (node (ref "P10") (pin "P$165") (pinfunction "P$1_P$165") (pintype "power_in"))
      (node (ref "P10") (pin "P$166") (pinfunction "P$1_P$166") (pintype "power_in"))
      (node (ref "P10") (pin "P$167") (pinfunction "P$1_P$167") (pintype "power_in"))
      (node (ref "P10") (pin "P$168") (pinfunction "P$1_P$168") (pintype "power_in"))
      (node (ref "P10") (pin "P$169") (pinfunction "P$1_P$169") (pintype "power_in"))
      (node (ref "P10") (pin "P$17") (pinfunction "P$1_P$17") (pintype "power_in"))
      (node (ref "P10") (pin "P$170") (pinfunction "P$1_P$170") (pintype "power_in"))
      (node (ref "P10") (pin "P$171") (pinfunction "P$1_P$171") (pintype "power_in"))
      (node (ref "P10") (pin "P$172") (pinfunction "P$1_P$172") (pintype "power_in"))
      (node (ref "P10") (pin "P$173") (pinfunction "P$1_P$173") (pintype "power_in"))
      (node (ref "P10") (pin "P$174") (pinfunction "P$1_P$174") (pintype "power_in"))
      (node (ref "P10") (pin "P$175") (pinfunction "P$1_P$175") (pintype "power_in"))
      (node (ref "P10") (pin "P$176") (pinfunction "P$1_P$176") (pintype "power_in"))
      (node (ref "P10") (pin "P$177") (pinfunction "P$1_P$177") (pintype "power_in"))
      (node (ref "P10") (pin "P$178") (pinfunction "P$1_P$178") (pintype "power_in"))
      (node (ref "P10") (pin "P$179") (pinfunction "P$1_P$179") (pintype "power_in"))
      (node (ref "P10") (pin "P$18") (pinfunction "P$1_P$18") (pintype "power_in"))
      (node (ref "P10") (pin "P$180") (pinfunction "P$1_P$180") (pintype "power_in"))
      (node (ref "P10") (pin "P$181") (pinfunction "P$1_P$181") (pintype "power_in"))
      (node (ref "P10") (pin "P$182") (pinfunction "P$1_P$182") (pintype "power_in"))
      (node (ref "P10") (pin "P$183") (pinfunction "P$1_P$183") (pintype "power_in"))
      (node (ref "P10") (pin "P$184") (pinfunction "P$1_P$184") (pintype "power_in"))
      (node (ref "P10") (pin "P$185") (pinfunction "P$1_P$185") (pintype "power_in"))
      (node (ref "P10") (pin "P$186") (pinfunction "P$1_P$186") (pintype "power_in"))
      (node (ref "P10") (pin "P$187") (pinfunction "P$1_P$187") (pintype "power_in"))
      (node (ref "P10") (pin "P$188") (pinfunction "P$1_P$188") (pintype "power_in"))
      (node (ref "P10") (pin "P$189") (pinfunction "P$1_P$189") (pintype "power_in"))
      (node (ref "P10") (pin "P$19") (pinfunction "P$1_P$19") (pintype "power_in"))
      (node (ref "P10") (pin "P$190") (pinfunction "P$1_P$190") (pintype "power_in"))
      (node (ref "P10") (pin "P$191") (pinfunction "P$1_P$191") (pintype "power_in"))
      (node (ref "P10") (pin "P$192") (pinfunction "P$1_P$192") (pintype "power_in"))
      (node (ref "P10") (pin "P$193") (pinfunction "P$1_P$193") (pintype "power_in"))
      (node (ref "P10") (pin "P$194") (pinfunction "P$1_P$194") (pintype "power_in"))
      (node (ref "P10") (pin "P$195") (pinfunction "P$1_P$195") (pintype "power_in"))
      (node (ref "P10") (pin "P$196") (pinfunction "P$1_P$196") (pintype "power_in"))
      (node (ref "P10") (pin "P$197") (pinfunction "P$1_P$197") (pintype "power_in"))
      (node (ref "P10") (pin "P$198") (pinfunction "P$1_P$198") (pintype "power_in"))
      (node (ref "P10") (pin "P$199") (pinfunction "P$1_P$199") (pintype "power_in"))
      (node (ref "P10") (pin "P$2") (pinfunction "P$1_P$2") (pintype "power_in"))
      (node (ref "P10") (pin "P$20") (pinfunction "P$1_P$20") (pintype "power_in"))
      (node (ref "P10") (pin "P$200") (pinfunction "P$1_P$200") (pintype "power_in"))
      (node (ref "P10") (pin "P$201") (pinfunction "P$1_P$201") (pintype "power_in"))
      (node (ref "P10") (pin "P$202") (pinfunction "P$1_P$202") (pintype "power_in"))
      (node (ref "P10") (pin "P$203") (pinfunction "P$1_P$203") (pintype "power_in"))
      (node (ref "P10") (pin "P$204") (pinfunction "P$1_P$204") (pintype "power_in"))
      (node (ref "P10") (pin "P$205") (pinfunction "P$1_P$205") (pintype "power_in"))
      (node (ref "P10") (pin "P$206") (pinfunction "P$1_P$206") (pintype "power_in"))
      (node (ref "P10") (pin "P$207") (pinfunction "P$1_P$207") (pintype "power_in"))
      (node (ref "P10") (pin "P$208") (pinfunction "P$1_P$208") (pintype "power_in"))
      (node (ref "P10") (pin "P$209") (pinfunction "P$1_P$209") (pintype "power_in"))
      (node (ref "P10") (pin "P$21") (pinfunction "P$1_P$21") (pintype "power_in"))
      (node (ref "P10") (pin "P$210") (pinfunction "P$1_P$210") (pintype "power_in"))
      (node (ref "P10") (pin "P$211") (pinfunction "P$1_P$211") (pintype "power_in"))
      (node (ref "P10") (pin "P$212") (pinfunction "P$1_P$212") (pintype "power_in"))
      (node (ref "P10") (pin "P$213") (pinfunction "P$1_P$213") (pintype "power_in"))
      (node (ref "P10") (pin "P$214") (pinfunction "P$1_P$214") (pintype "power_in"))
      (node (ref "P10") (pin "P$215") (pinfunction "P$1_P$215") (pintype "power_in"))
      (node (ref "P10") (pin "P$216") (pinfunction "P$1_P$216") (pintype "power_in"))
      (node (ref "P10") (pin "P$217") (pinfunction "P$1_P$217") (pintype "power_in"))
      (node (ref "P10") (pin "P$218") (pinfunction "P$1_P$218") (pintype "power_in"))
      (node (ref "P10") (pin "P$219") (pinfunction "P$1_P$219") (pintype "power_in"))
      (node (ref "P10") (pin "P$22") (pinfunction "P$1_P$22") (pintype "power_in"))
      (node (ref "P10") (pin "P$220") (pinfunction "P$1_P$220") (pintype "power_in"))
      (node (ref "P10") (pin "P$221") (pinfunction "P$1_P$221") (pintype "power_in"))
      (node (ref "P10") (pin "P$222") (pinfunction "P$1_P$222") (pintype "power_in"))
      (node (ref "P10") (pin "P$223") (pinfunction "P$1_P$223") (pintype "power_in"))
      (node (ref "P10") (pin "P$224") (pinfunction "P$1_P$224") (pintype "power_in"))
      (node (ref "P10") (pin "P$225") (pinfunction "P$1_P$225") (pintype "power_in"))
      (node (ref "P10") (pin "P$226") (pinfunction "P$1_P$226") (pintype "power_in"))
      (node (ref "P10") (pin "P$227") (pinfunction "P$1_P$227") (pintype "power_in"))
      (node (ref "P10") (pin "P$228") (pinfunction "P$1_P$228") (pintype "power_in"))
      (node (ref "P10") (pin "P$229") (pinfunction "P$1_P$229") (pintype "power_in"))
      (node (ref "P10") (pin "P$23") (pinfunction "P$1_P$23") (pintype "power_in"))
      (node (ref "P10") (pin "P$230") (pinfunction "P$1_P$230") (pintype "power_in"))
      (node (ref "P10") (pin "P$231") (pinfunction "P$1_P$231") (pintype "power_in"))
      (node (ref "P10") (pin "P$232") (pinfunction "P$1_P$232") (pintype "power_in"))
      (node (ref "P10") (pin "P$233") (pinfunction "P$1_P$233") (pintype "power_in"))
      (node (ref "P10") (pin "P$234") (pinfunction "P$1_P$234") (pintype "power_in"))
      (node (ref "P10") (pin "P$235") (pinfunction "P$1_P$235") (pintype "power_in"))
      (node (ref "P10") (pin "P$236") (pinfunction "P$1_P$236") (pintype "power_in"))
      (node (ref "P10") (pin "P$237") (pinfunction "P$1_P$237") (pintype "power_in"))
      (node (ref "P10") (pin "P$238") (pinfunction "P$1_P$238") (pintype "power_in"))
      (node (ref "P10") (pin "P$239") (pinfunction "P$1_P$239") (pintype "power_in"))
      (node (ref "P10") (pin "P$24") (pinfunction "P$1_P$24") (pintype "power_in"))
      (node (ref "P10") (pin "P$240") (pinfunction "P$1_P$240") (pintype "power_in"))
      (node (ref "P10") (pin "P$241") (pinfunction "P$1_P$241") (pintype "power_in"))
      (node (ref "P10") (pin "P$242") (pinfunction "P$1_P$242") (pintype "power_in"))
      (node (ref "P10") (pin "P$243") (pinfunction "P$1_P$243") (pintype "power_in"))
      (node (ref "P10") (pin "P$244") (pinfunction "P$1_P$244") (pintype "power_in"))
      (node (ref "P10") (pin "P$245") (pinfunction "P$1_P$245") (pintype "power_in"))
      (node (ref "P10") (pin "P$246") (pinfunction "P$1_P$246") (pintype "power_in"))
      (node (ref "P10") (pin "P$247") (pinfunction "P$1_P$247") (pintype "power_in"))
      (node (ref "P10") (pin "P$248") (pinfunction "P$1_P$248") (pintype "power_in"))
      (node (ref "P10") (pin "P$249") (pinfunction "P$1_P$249") (pintype "power_in"))
      (node (ref "P10") (pin "P$25") (pinfunction "P$1_P$25") (pintype "power_in"))
      (node (ref "P10") (pin "P$250") (pinfunction "P$1_P$250") (pintype "power_in"))
      (node (ref "P10") (pin "P$251") (pinfunction "P$1_P$251") (pintype "power_in"))
      (node (ref "P10") (pin "P$252") (pinfunction "P$1_P$252") (pintype "power_in"))
      (node (ref "P10") (pin "P$253") (pinfunction "P$1_P$253") (pintype "power_in"))
      (node (ref "P10") (pin "P$254") (pinfunction "P$1_P$254") (pintype "power_in"))
      (node (ref "P10") (pin "P$255") (pinfunction "P$1_P$255") (pintype "power_in"))
      (node (ref "P10") (pin "P$256") (pinfunction "P$1_P$256") (pintype "power_in"))
      (node (ref "P10") (pin "P$257") (pinfunction "P$1_P$257") (pintype "power_in"))
      (node (ref "P10") (pin "P$258") (pinfunction "P$1_P$258") (pintype "power_in"))
      (node (ref "P10") (pin "P$259") (pinfunction "P$1_P$259") (pintype "power_in"))
      (node (ref "P10") (pin "P$26") (pinfunction "P$1_P$26") (pintype "power_in"))
      (node (ref "P10") (pin "P$260") (pinfunction "P$1_P$260") (pintype "power_in"))
      (node (ref "P10") (pin "P$261") (pinfunction "P$1_P$261") (pintype "power_in"))
      (node (ref "P10") (pin "P$262") (pinfunction "P$1_P$262") (pintype "power_in"))
      (node (ref "P10") (pin "P$263") (pinfunction "P$1_P$263") (pintype "power_in"))
      (node (ref "P10") (pin "P$264") (pinfunction "P$1_P$264") (pintype "power_in"))
      (node (ref "P10") (pin "P$265") (pinfunction "P$1_P$265") (pintype "power_in"))
      (node (ref "P10") (pin "P$266") (pinfunction "P$1_P$266") (pintype "power_in"))
      (node (ref "P10") (pin "P$267") (pinfunction "P$1_P$267") (pintype "power_in"))
      (node (ref "P10") (pin "P$268") (pinfunction "P$1_P$268") (pintype "power_in"))
      (node (ref "P10") (pin "P$269") (pinfunction "P$1_P$269") (pintype "power_in"))
      (node (ref "P10") (pin "P$27") (pinfunction "P$1_P$27") (pintype "power_in"))
      (node (ref "P10") (pin "P$270") (pinfunction "P$1_P$270") (pintype "power_in"))
      (node (ref "P10") (pin "P$271") (pinfunction "P$1_P$271") (pintype "power_in"))
      (node (ref "P10") (pin "P$272") (pinfunction "P$1_P$272") (pintype "power_in"))
      (node (ref "P10") (pin "P$273") (pinfunction "P$1_P$273") (pintype "power_in"))
      (node (ref "P10") (pin "P$274") (pinfunction "P$1_P$274") (pintype "power_in"))
      (node (ref "P10") (pin "P$275") (pinfunction "P$1_P$275") (pintype "power_in"))
      (node (ref "P10") (pin "P$276") (pinfunction "P$1_P$276") (pintype "power_in"))
      (node (ref "P10") (pin "P$277") (pinfunction "P$1_P$277") (pintype "power_in"))
      (node (ref "P10") (pin "P$278") (pinfunction "P$1_P$278") (pintype "power_in"))
      (node (ref "P10") (pin "P$279") (pinfunction "P$1_P$279") (pintype "power_in"))
      (node (ref "P10") (pin "P$28") (pinfunction "P$1_P$28") (pintype "power_in"))
      (node (ref "P10") (pin "P$280") (pinfunction "P$1_P$280") (pintype "power_in"))
      (node (ref "P10") (pin "P$281") (pinfunction "P$1_P$281") (pintype "power_in"))
      (node (ref "P10") (pin "P$282") (pinfunction "P$1_P$282") (pintype "power_in"))
      (node (ref "P10") (pin "P$283") (pinfunction "P$1_P$283") (pintype "power_in"))
      (node (ref "P10") (pin "P$284") (pinfunction "P$1_P$284") (pintype "power_in"))
      (node (ref "P10") (pin "P$285") (pinfunction "P$1_P$285") (pintype "power_in"))
      (node (ref "P10") (pin "P$286") (pinfunction "P$1_P$286") (pintype "power_in"))
      (node (ref "P10") (pin "P$287") (pinfunction "P$1_P$287") (pintype "power_in"))
      (node (ref "P10") (pin "P$288") (pinfunction "P$1_P$288") (pintype "power_in"))
      (node (ref "P10") (pin "P$289") (pinfunction "P$1_P$289") (pintype "power_in"))
      (node (ref "P10") (pin "P$29") (pinfunction "P$1_P$29") (pintype "power_in"))
      (node (ref "P10") (pin "P$290") (pinfunction "P$1_P$290") (pintype "power_in"))
      (node (ref "P10") (pin "P$291") (pinfunction "P$1_P$291") (pintype "power_in"))
      (node (ref "P10") (pin "P$292") (pinfunction "P$1_P$292") (pintype "power_in"))
      (node (ref "P10") (pin "P$293") (pinfunction "P$1_P$293") (pintype "power_in"))
      (node (ref "P10") (pin "P$294") (pinfunction "P$1_P$294") (pintype "power_in"))
      (node (ref "P10") (pin "P$295") (pinfunction "P$1_P$295") (pintype "power_in"))
      (node (ref "P10") (pin "P$296") (pinfunction "P$1_P$296") (pintype "power_in"))
      (node (ref "P10") (pin "P$297") (pinfunction "P$1_P$297") (pintype "power_in"))
      (node (ref "P10") (pin "P$298") (pinfunction "P$1_P$298") (pintype "power_in"))
      (node (ref "P10") (pin "P$299") (pinfunction "P$1_P$299") (pintype "power_in"))
      (node (ref "P10") (pin "P$3") (pinfunction "P$1_P$3") (pintype "power_in"))
      (node (ref "P10") (pin "P$30") (pinfunction "P$1_P$30") (pintype "power_in"))
      (node (ref "P10") (pin "P$300") (pinfunction "P$1_P$300") (pintype "power_in"))
      (node (ref "P10") (pin "P$301") (pinfunction "P$1_P$301") (pintype "power_in"))
      (node (ref "P10") (pin "P$302") (pinfunction "P$1_P$302") (pintype "power_in"))
      (node (ref "P10") (pin "P$303") (pinfunction "P$1_P$303") (pintype "power_in"))
      (node (ref "P10") (pin "P$304") (pinfunction "P$1_P$304") (pintype "power_in"))
      (node (ref "P10") (pin "P$305") (pinfunction "P$1_P$305") (pintype "power_in"))
      (node (ref "P10") (pin "P$306") (pinfunction "P$1_P$306") (pintype "power_in"))
      (node (ref "P10") (pin "P$307") (pinfunction "P$1_P$307") (pintype "power_in"))
      (node (ref "P10") (pin "P$308") (pinfunction "P$1_P$308") (pintype "power_in"))
      (node (ref "P10") (pin "P$309") (pinfunction "P$1_P$309") (pintype "power_in"))
      (node (ref "P10") (pin "P$31") (pinfunction "P$1_P$31") (pintype "power_in"))
      (node (ref "P10") (pin "P$310") (pinfunction "P$1_P$310") (pintype "power_in"))
      (node (ref "P10") (pin "P$311") (pinfunction "P$1_P$311") (pintype "power_in"))
      (node (ref "P10") (pin "P$312") (pinfunction "P$1_P$312") (pintype "power_in"))
      (node (ref "P10") (pin "P$313") (pinfunction "P$1_P$313") (pintype "power_in"))
      (node (ref "P10") (pin "P$314") (pinfunction "P$1_P$314") (pintype "power_in"))
      (node (ref "P10") (pin "P$315") (pinfunction "P$1_P$315") (pintype "power_in"))
      (node (ref "P10") (pin "P$316") (pinfunction "P$1_P$316") (pintype "power_in"))
      (node (ref "P10") (pin "P$317") (pinfunction "P$1_P$317") (pintype "power_in"))
      (node (ref "P10") (pin "P$318") (pinfunction "P$1_P$318") (pintype "power_in"))
      (node (ref "P10") (pin "P$319") (pinfunction "P$1_P$319") (pintype "power_in"))
      (node (ref "P10") (pin "P$32") (pinfunction "P$1_P$32") (pintype "power_in"))
      (node (ref "P10") (pin "P$320") (pinfunction "P$1_P$320") (pintype "power_in"))
      (node (ref "P10") (pin "P$321") (pinfunction "P$1_P$321") (pintype "power_in"))
      (node (ref "P10") (pin "P$322") (pinfunction "P$1_P$322") (pintype "power_in"))
      (node (ref "P10") (pin "P$323") (pinfunction "P$1_P$323") (pintype "power_in"))
      (node (ref "P10") (pin "P$324") (pinfunction "P$1_P$324") (pintype "power_in"))
      (node (ref "P10") (pin "P$325") (pinfunction "P$1_P$325") (pintype "power_in"))
      (node (ref "P10") (pin "P$326") (pinfunction "P$1_P$326") (pintype "power_in"))
      (node (ref "P10") (pin "P$327") (pinfunction "P$1_P$327") (pintype "power_in"))
      (node (ref "P10") (pin "P$328") (pinfunction "P$1_P$328") (pintype "power_in"))
      (node (ref "P10") (pin "P$329") (pinfunction "P$1_P$329") (pintype "power_in"))
      (node (ref "P10") (pin "P$33") (pinfunction "P$1_P$33") (pintype "power_in"))
      (node (ref "P10") (pin "P$330") (pinfunction "P$1_P$330") (pintype "power_in"))
      (node (ref "P10") (pin "P$331") (pinfunction "P$1_P$331") (pintype "power_in"))
      (node (ref "P10") (pin "P$332") (pinfunction "P$1_P$332") (pintype "power_in"))
      (node (ref "P10") (pin "P$333") (pinfunction "P$1_P$333") (pintype "power_in"))
      (node (ref "P10") (pin "P$334") (pinfunction "P$1_P$334") (pintype "power_in"))
      (node (ref "P10") (pin "P$335") (pinfunction "P$1_P$335") (pintype "power_in"))
      (node (ref "P10") (pin "P$336") (pinfunction "P$1_P$336") (pintype "power_in"))
      (node (ref "P10") (pin "P$337") (pinfunction "P$1_P$337") (pintype "power_in"))
      (node (ref "P10") (pin "P$338") (pinfunction "P$1_P$338") (pintype "power_in"))
      (node (ref "P10") (pin "P$339") (pinfunction "P$1_P$339") (pintype "power_in"))
      (node (ref "P10") (pin "P$34") (pinfunction "P$1_P$34") (pintype "power_in"))
      (node (ref "P10") (pin "P$340") (pinfunction "P$1_P$340") (pintype "power_in"))
      (node (ref "P10") (pin "P$341") (pinfunction "P$1_P$341") (pintype "power_in"))
      (node (ref "P10") (pin "P$342") (pinfunction "P$1_P$342") (pintype "power_in"))
      (node (ref "P10") (pin "P$343") (pinfunction "P$1_P$343") (pintype "power_in"))
      (node (ref "P10") (pin "P$344") (pinfunction "P$1_P$344") (pintype "power_in"))
      (node (ref "P10") (pin "P$345") (pinfunction "P$1_P$345") (pintype "power_in"))
      (node (ref "P10") (pin "P$346") (pinfunction "P$1_P$346") (pintype "power_in"))
      (node (ref "P10") (pin "P$347") (pinfunction "P$1_P$347") (pintype "power_in"))
      (node (ref "P10") (pin "P$348") (pinfunction "P$1_P$348") (pintype "power_in"))
      (node (ref "P10") (pin "P$349") (pinfunction "P$1_P$349") (pintype "power_in"))
      (node (ref "P10") (pin "P$35") (pinfunction "P$1_P$35") (pintype "power_in"))
      (node (ref "P10") (pin "P$350") (pinfunction "P$1_P$350") (pintype "power_in"))
      (node (ref "P10") (pin "P$351") (pinfunction "P$1_P$351") (pintype "power_in"))
      (node (ref "P10") (pin "P$352") (pinfunction "P$1_P$352") (pintype "power_in"))
      (node (ref "P10") (pin "P$353") (pinfunction "P$1_P$353") (pintype "power_in"))
      (node (ref "P10") (pin "P$354") (pinfunction "P$1_P$354") (pintype "power_in"))
      (node (ref "P10") (pin "P$355") (pinfunction "P$1_P$355") (pintype "power_in"))
      (node (ref "P10") (pin "P$356") (pinfunction "P$1_P$356") (pintype "power_in"))
      (node (ref "P10") (pin "P$357") (pinfunction "P$1_P$357") (pintype "power_in"))
      (node (ref "P10") (pin "P$358") (pinfunction "P$1_P$358") (pintype "power_in"))
      (node (ref "P10") (pin "P$359") (pinfunction "P$1_P$359") (pintype "power_in"))
      (node (ref "P10") (pin "P$36") (pinfunction "P$1_P$36") (pintype "power_in"))
      (node (ref "P10") (pin "P$360") (pinfunction "P$1_P$360") (pintype "power_in"))
      (node (ref "P10") (pin "P$361") (pinfunction "P$1_P$361") (pintype "power_in"))
      (node (ref "P10") (pin "P$362") (pinfunction "P$1_P$362") (pintype "power_in"))
      (node (ref "P10") (pin "P$363") (pinfunction "P$1_P$363") (pintype "power_in"))
      (node (ref "P10") (pin "P$364") (pinfunction "P$1_P$364") (pintype "power_in"))
      (node (ref "P10") (pin "P$365") (pinfunction "P$1_P$365") (pintype "power_in"))
      (node (ref "P10") (pin "P$366") (pinfunction "P$1_P$366") (pintype "power_in"))
      (node (ref "P10") (pin "P$367") (pinfunction "P$1_P$367") (pintype "power_in"))
      (node (ref "P10") (pin "P$368") (pinfunction "P$1_P$368") (pintype "power_in"))
      (node (ref "P10") (pin "P$369") (pinfunction "P$1_P$369") (pintype "power_in"))
      (node (ref "P10") (pin "P$37") (pinfunction "P$1_P$37") (pintype "power_in"))
      (node (ref "P10") (pin "P$370") (pinfunction "P$1_P$370") (pintype "power_in"))
      (node (ref "P10") (pin "P$371") (pinfunction "P$1_P$371") (pintype "power_in"))
      (node (ref "P10") (pin "P$372") (pinfunction "P$1_P$372") (pintype "power_in"))
      (node (ref "P10") (pin "P$373") (pinfunction "P$1_P$373") (pintype "power_in"))
      (node (ref "P10") (pin "P$374") (pinfunction "P$1_P$374") (pintype "power_in"))
      (node (ref "P10") (pin "P$375") (pinfunction "P$1_P$375") (pintype "power_in"))
      (node (ref "P10") (pin "P$376") (pinfunction "P$1_P$376") (pintype "power_in"))
      (node (ref "P10") (pin "P$377") (pinfunction "P$1_P$377") (pintype "power_in"))
      (node (ref "P10") (pin "P$378") (pinfunction "P$1_P$378") (pintype "power_in"))
      (node (ref "P10") (pin "P$379") (pinfunction "P$1_P$379") (pintype "power_in"))
      (node (ref "P10") (pin "P$38") (pinfunction "P$1_P$38") (pintype "power_in"))
      (node (ref "P10") (pin "P$380") (pinfunction "P$1_P$380") (pintype "power_in"))
      (node (ref "P10") (pin "P$381") (pinfunction "P$1_P$381") (pintype "power_in"))
      (node (ref "P10") (pin "P$382") (pinfunction "P$1_P$382") (pintype "power_in"))
      (node (ref "P10") (pin "P$383") (pinfunction "P$1_P$383") (pintype "power_in"))
      (node (ref "P10") (pin "P$384") (pinfunction "P$1_P$384") (pintype "power_in"))
      (node (ref "P10") (pin "P$385") (pinfunction "P$1_P$385") (pintype "power_in"))
      (node (ref "P10") (pin "P$386") (pinfunction "P$1_P$386") (pintype "power_in"))
      (node (ref "P10") (pin "P$387") (pinfunction "P$1_P$387") (pintype "power_in"))
      (node (ref "P10") (pin "P$388") (pinfunction "P$1_P$388") (pintype "power_in"))
      (node (ref "P10") (pin "P$389") (pinfunction "P$1_P$389") (pintype "power_in"))
      (node (ref "P10") (pin "P$39") (pinfunction "P$1_P$39") (pintype "power_in"))
      (node (ref "P10") (pin "P$390") (pinfunction "P$1_P$390") (pintype "power_in"))
      (node (ref "P10") (pin "P$391") (pinfunction "P$1_P$391") (pintype "power_in"))
      (node (ref "P10") (pin "P$392") (pinfunction "P$1_P$392") (pintype "power_in"))
      (node (ref "P10") (pin "P$393") (pinfunction "P$1_P$393") (pintype "power_in"))
      (node (ref "P10") (pin "P$394") (pinfunction "P$1_P$394") (pintype "power_in"))
      (node (ref "P10") (pin "P$395") (pinfunction "P$1_P$395") (pintype "power_in"))
      (node (ref "P10") (pin "P$396") (pinfunction "P$1_P$396") (pintype "power_in"))
      (node (ref "P10") (pin "P$397") (pinfunction "P$1_P$397") (pintype "power_in"))
      (node (ref "P10") (pin "P$398") (pinfunction "P$1_P$398") (pintype "power_in"))
      (node (ref "P10") (pin "P$399") (pinfunction "P$1_P$399") (pintype "power_in"))
      (node (ref "P10") (pin "P$4") (pinfunction "P$1_P$4") (pintype "power_in"))
      (node (ref "P10") (pin "P$40") (pinfunction "P$1_P$40") (pintype "power_in"))
      (node (ref "P10") (pin "P$400") (pinfunction "P$1_P$400") (pintype "power_in"))
      (node (ref "P10") (pin "P$401") (pinfunction "P$1_P$401") (pintype "power_in"))
      (node (ref "P10") (pin "P$402") (pinfunction "P$1_P$402") (pintype "power_in"))
      (node (ref "P10") (pin "P$403") (pinfunction "P$1_P$403") (pintype "power_in"))
      (node (ref "P10") (pin "P$404") (pinfunction "P$1_P$404") (pintype "power_in"))
      (node (ref "P10") (pin "P$405") (pinfunction "P$1_P$405") (pintype "power_in"))
      (node (ref "P10") (pin "P$406") (pinfunction "P$1_P$406") (pintype "power_in"))
      (node (ref "P10") (pin "P$407") (pinfunction "P$1_P$407") (pintype "power_in"))
      (node (ref "P10") (pin "P$408") (pinfunction "P$1_P$408") (pintype "power_in"))
      (node (ref "P10") (pin "P$409") (pinfunction "P$1_P$409") (pintype "power_in"))
      (node (ref "P10") (pin "P$41") (pinfunction "P$1_P$41") (pintype "power_in"))
      (node (ref "P10") (pin "P$410") (pinfunction "P$1_P$410") (pintype "power_in"))
      (node (ref "P10") (pin "P$411") (pinfunction "P$1_P$411") (pintype "power_in"))
      (node (ref "P10") (pin "P$412") (pinfunction "P$1_P$412") (pintype "power_in"))
      (node (ref "P10") (pin "P$413") (pinfunction "P$1_P$413") (pintype "power_in"))
      (node (ref "P10") (pin "P$414") (pinfunction "P$1_P$414") (pintype "power_in"))
      (node (ref "P10") (pin "P$415") (pinfunction "P$1_P$415") (pintype "power_in"))
      (node (ref "P10") (pin "P$416") (pinfunction "P$1_P$416") (pintype "power_in"))
      (node (ref "P10") (pin "P$417") (pinfunction "P$1_P$417") (pintype "power_in"))
      (node (ref "P10") (pin "P$418") (pinfunction "P$1_P$418") (pintype "power_in"))
      (node (ref "P10") (pin "P$419") (pinfunction "P$1_P$419") (pintype "power_in"))
      (node (ref "P10") (pin "P$42") (pinfunction "P$1_P$42") (pintype "power_in"))
      (node (ref "P10") (pin "P$420") (pinfunction "P$1_P$420") (pintype "power_in"))
      (node (ref "P10") (pin "P$421") (pinfunction "P$1_P$421") (pintype "power_in"))
      (node (ref "P10") (pin "P$422") (pinfunction "P$1_P$422") (pintype "power_in"))
      (node (ref "P10") (pin "P$423") (pinfunction "P$1_P$423") (pintype "power_in"))
      (node (ref "P10") (pin "P$424") (pinfunction "P$1_P$424") (pintype "power_in"))
      (node (ref "P10") (pin "P$425") (pinfunction "P$1_P$425") (pintype "power_in"))
      (node (ref "P10") (pin "P$426") (pinfunction "P$1_P$426") (pintype "power_in"))
      (node (ref "P10") (pin "P$427") (pinfunction "P$1_P$427") (pintype "power_in"))
      (node (ref "P10") (pin "P$428") (pinfunction "P$1_P$428") (pintype "power_in"))
      (node (ref "P10") (pin "P$429") (pinfunction "P$1_P$429") (pintype "power_in"))
      (node (ref "P10") (pin "P$43") (pinfunction "P$1_P$43") (pintype "power_in"))
      (node (ref "P10") (pin "P$430") (pinfunction "P$1_P$430") (pintype "power_in"))
      (node (ref "P10") (pin "P$431") (pinfunction "P$1_P$431") (pintype "power_in"))
      (node (ref "P10") (pin "P$432") (pinfunction "P$1_P$432") (pintype "power_in"))
      (node (ref "P10") (pin "P$433") (pinfunction "P$1_P$433") (pintype "power_in"))
      (node (ref "P10") (pin "P$434") (pinfunction "P$1_P$434") (pintype "power_in"))
      (node (ref "P10") (pin "P$435") (pinfunction "P$1_P$435") (pintype "power_in"))
      (node (ref "P10") (pin "P$436") (pinfunction "P$1_P$436") (pintype "power_in"))
      (node (ref "P10") (pin "P$437") (pinfunction "P$1_P$437") (pintype "power_in"))
      (node (ref "P10") (pin "P$438") (pinfunction "P$1_P$438") (pintype "power_in"))
      (node (ref "P10") (pin "P$439") (pinfunction "P$1_P$439") (pintype "power_in"))
      (node (ref "P10") (pin "P$44") (pinfunction "P$1_P$44") (pintype "power_in"))
      (node (ref "P10") (pin "P$440") (pinfunction "P$1_P$440") (pintype "power_in"))
      (node (ref "P10") (pin "P$441") (pinfunction "P$1_P$441") (pintype "power_in"))
      (node (ref "P10") (pin "P$442") (pinfunction "P$1_P$442") (pintype "power_in"))
      (node (ref "P10") (pin "P$443") (pinfunction "P$1_P$443") (pintype "power_in"))
      (node (ref "P10") (pin "P$444") (pinfunction "P$1_P$444") (pintype "power_in"))
      (node (ref "P10") (pin "P$445") (pinfunction "P$1_P$445") (pintype "power_in"))
      (node (ref "P10") (pin "P$446") (pinfunction "P$1_P$446") (pintype "power_in"))
      (node (ref "P10") (pin "P$447") (pinfunction "P$1_P$447") (pintype "power_in"))
      (node (ref "P10") (pin "P$448") (pinfunction "P$1_P$448") (pintype "power_in"))
      (node (ref "P10") (pin "P$449") (pinfunction "P$1_P$449") (pintype "power_in"))
      (node (ref "P10") (pin "P$45") (pinfunction "P$1_P$45") (pintype "power_in"))
      (node (ref "P10") (pin "P$450") (pinfunction "P$1_P$450") (pintype "power_in"))
      (node (ref "P10") (pin "P$451") (pinfunction "P$1_P$451") (pintype "power_in"))
      (node (ref "P10") (pin "P$452") (pinfunction "P$1_P$452") (pintype "power_in"))
      (node (ref "P10") (pin "P$453") (pinfunction "P$1_P$453") (pintype "power_in"))
      (node (ref "P10") (pin "P$454") (pinfunction "P$1_P$454") (pintype "power_in"))
      (node (ref "P10") (pin "P$455") (pinfunction "P$1_P$455") (pintype "power_in"))
      (node (ref "P10") (pin "P$456") (pinfunction "P$1_P$456") (pintype "power_in"))
      (node (ref "P10") (pin "P$457") (pinfunction "P$1_P$457") (pintype "power_in"))
      (node (ref "P10") (pin "P$458") (pinfunction "P$1_P$458") (pintype "power_in"))
      (node (ref "P10") (pin "P$459") (pinfunction "P$1_P$459") (pintype "power_in"))
      (node (ref "P10") (pin "P$46") (pinfunction "P$1_P$46") (pintype "power_in"))
      (node (ref "P10") (pin "P$460") (pinfunction "P$1_P$460") (pintype "power_in"))
      (node (ref "P10") (pin "P$461") (pinfunction "P$1_P$461") (pintype "power_in"))
      (node (ref "P10") (pin "P$462") (pinfunction "P$1_P$462") (pintype "power_in"))
      (node (ref "P10") (pin "P$463") (pinfunction "P$1_P$463") (pintype "power_in"))
      (node (ref "P10") (pin "P$464") (pinfunction "P$1_P$464") (pintype "power_in"))
      (node (ref "P10") (pin "P$465") (pinfunction "P$1_P$465") (pintype "power_in"))
      (node (ref "P10") (pin "P$466") (pinfunction "P$1_P$466") (pintype "power_in"))
      (node (ref "P10") (pin "P$467") (pinfunction "P$1_P$467") (pintype "power_in"))
      (node (ref "P10") (pin "P$468") (pinfunction "P$1_P$468") (pintype "power_in"))
      (node (ref "P10") (pin "P$469") (pinfunction "P$1_P$469") (pintype "power_in"))
      (node (ref "P10") (pin "P$47") (pinfunction "P$1_P$47") (pintype "power_in"))
      (node (ref "P10") (pin "P$470") (pinfunction "P$1_P$470") (pintype "power_in"))
      (node (ref "P10") (pin "P$471") (pinfunction "P$1_P$471") (pintype "power_in"))
      (node (ref "P10") (pin "P$472") (pinfunction "P$1_P$472") (pintype "power_in"))
      (node (ref "P10") (pin "P$473") (pinfunction "P$1_P$473") (pintype "power_in"))
      (node (ref "P10") (pin "P$474") (pinfunction "P$1_P$474") (pintype "power_in"))
      (node (ref "P10") (pin "P$475") (pinfunction "P$1_P$475") (pintype "power_in"))
      (node (ref "P10") (pin "P$476") (pinfunction "P$1_P$476") (pintype "power_in"))
      (node (ref "P10") (pin "P$477") (pinfunction "P$1_P$477") (pintype "power_in"))
      (node (ref "P10") (pin "P$478") (pinfunction "P$1_P$478") (pintype "power_in"))
      (node (ref "P10") (pin "P$479") (pinfunction "P$1_P$479") (pintype "power_in"))
      (node (ref "P10") (pin "P$48") (pinfunction "P$1_P$48") (pintype "power_in"))
      (node (ref "P10") (pin "P$480") (pinfunction "P$1_P$480") (pintype "power_in"))
      (node (ref "P10") (pin "P$481") (pinfunction "P$1_P$481") (pintype "power_in"))
      (node (ref "P10") (pin "P$482") (pinfunction "P$1_P$482") (pintype "power_in"))
      (node (ref "P10") (pin "P$483") (pinfunction "P$1_P$483") (pintype "power_in"))
      (node (ref "P10") (pin "P$484") (pinfunction "P$1_P$484") (pintype "power_in"))
      (node (ref "P10") (pin "P$485") (pinfunction "P$1_P$485") (pintype "power_in"))
      (node (ref "P10") (pin "P$486") (pinfunction "P$1_P$486") (pintype "power_in"))
      (node (ref "P10") (pin "P$487") (pinfunction "P$1_P$487") (pintype "power_in"))
      (node (ref "P10") (pin "P$488") (pinfunction "P$1_P$488") (pintype "power_in"))
      (node (ref "P10") (pin "P$489") (pinfunction "P$1_P$489") (pintype "power_in"))
      (node (ref "P10") (pin "P$49") (pinfunction "P$1_P$49") (pintype "power_in"))
      (node (ref "P10") (pin "P$490") (pinfunction "P$1_P$490") (pintype "power_in"))
      (node (ref "P10") (pin "P$491") (pinfunction "P$1_P$491") (pintype "power_in"))
      (node (ref "P10") (pin "P$492") (pinfunction "P$1_P$492") (pintype "power_in"))
      (node (ref "P10") (pin "P$493") (pinfunction "P$1_P$493") (pintype "power_in"))
      (node (ref "P10") (pin "P$494") (pinfunction "P$1_P$494") (pintype "power_in"))
      (node (ref "P10") (pin "P$495") (pinfunction "P$1_P$495") (pintype "power_in"))
      (node (ref "P10") (pin "P$496") (pinfunction "P$1_P$496") (pintype "power_in"))
      (node (ref "P10") (pin "P$497") (pinfunction "P$1_P$497") (pintype "power_in"))
      (node (ref "P10") (pin "P$498") (pinfunction "P$1_P$498") (pintype "power_in"))
      (node (ref "P10") (pin "P$499") (pinfunction "P$1_P$499") (pintype "power_in"))
      (node (ref "P10") (pin "P$5") (pinfunction "P$1_P$5") (pintype "power_in"))
      (node (ref "P10") (pin "P$50") (pinfunction "P$1_P$50") (pintype "power_in"))
      (node (ref "P10") (pin "P$500") (pinfunction "P$1_P$500") (pintype "power_in"))
      (node (ref "P10") (pin "P$501") (pinfunction "P$1_P$501") (pintype "power_in"))
      (node (ref "P10") (pin "P$502") (pinfunction "P$1_P$502") (pintype "power_in"))
      (node (ref "P10") (pin "P$503") (pinfunction "P$1_P$503") (pintype "power_in"))
      (node (ref "P10") (pin "P$504") (pinfunction "P$1_P$504") (pintype "power_in"))
      (node (ref "P10") (pin "P$505") (pinfunction "P$1_P$505") (pintype "power_in"))
      (node (ref "P10") (pin "P$506") (pinfunction "P$1_P$506") (pintype "power_in"))
      (node (ref "P10") (pin "P$507") (pinfunction "P$1_P$507") (pintype "power_in"))
      (node (ref "P10") (pin "P$508") (pinfunction "P$1_P$508") (pintype "power_in"))
      (node (ref "P10") (pin "P$509") (pinfunction "P$1_P$509") (pintype "power_in"))
      (node (ref "P10") (pin "P$51") (pinfunction "P$1_P$51") (pintype "power_in"))
      (node (ref "P10") (pin "P$510") (pinfunction "P$1_P$510") (pintype "power_in"))
      (node (ref "P10") (pin "P$511") (pinfunction "P$1_P$511") (pintype "power_in"))
      (node (ref "P10") (pin "P$512") (pinfunction "P$1_P$512") (pintype "power_in"))
      (node (ref "P10") (pin "P$513") (pinfunction "P$1_P$513") (pintype "power_in"))
      (node (ref "P10") (pin "P$514") (pinfunction "P$1_P$514") (pintype "power_in"))
      (node (ref "P10") (pin "P$515") (pinfunction "P$1_P$515") (pintype "power_in"))
      (node (ref "P10") (pin "P$516") (pinfunction "P$1_P$516") (pintype "power_in"))
      (node (ref "P10") (pin "P$517") (pinfunction "P$1_P$517") (pintype "power_in"))
      (node (ref "P10") (pin "P$518") (pinfunction "P$1_P$518") (pintype "power_in"))
      (node (ref "P10") (pin "P$519") (pinfunction "P$1_P$519") (pintype "power_in"))
      (node (ref "P10") (pin "P$52") (pinfunction "P$1_P$52") (pintype "power_in"))
      (node (ref "P10") (pin "P$520") (pinfunction "P$1_P$520") (pintype "power_in"))
      (node (ref "P10") (pin "P$521") (pinfunction "P$1_P$521") (pintype "power_in"))
      (node (ref "P10") (pin "P$522") (pinfunction "P$1_P$522") (pintype "power_in"))
      (node (ref "P10") (pin "P$523") (pinfunction "P$1_P$523") (pintype "power_in"))
      (node (ref "P10") (pin "P$524") (pinfunction "P$1_P$524") (pintype "power_in"))
      (node (ref "P10") (pin "P$525") (pinfunction "P$1_P$525") (pintype "power_in"))
      (node (ref "P10") (pin "P$526") (pinfunction "P$1_P$526") (pintype "power_in"))
      (node (ref "P10") (pin "P$527") (pinfunction "P$1_P$527") (pintype "power_in"))
      (node (ref "P10") (pin "P$528") (pinfunction "P$1_P$528") (pintype "power_in"))
      (node (ref "P10") (pin "P$529") (pinfunction "P$1_P$529") (pintype "power_in"))
      (node (ref "P10") (pin "P$53") (pinfunction "P$1_P$53") (pintype "power_in"))
      (node (ref "P10") (pin "P$530") (pinfunction "P$1_P$530") (pintype "power_in"))
      (node (ref "P10") (pin "P$531") (pinfunction "P$1_P$531") (pintype "power_in"))
      (node (ref "P10") (pin "P$532") (pinfunction "P$1_P$532") (pintype "power_in"))
      (node (ref "P10") (pin "P$533") (pinfunction "P$1_P$533") (pintype "power_in"))
      (node (ref "P10") (pin "P$534") (pinfunction "P$1_P$534") (pintype "power_in"))
      (node (ref "P10") (pin "P$535") (pinfunction "P$1_P$535") (pintype "power_in"))
      (node (ref "P10") (pin "P$536") (pinfunction "P$1_P$536") (pintype "power_in"))
      (node (ref "P10") (pin "P$537") (pinfunction "P$1_P$537") (pintype "power_in"))
      (node (ref "P10") (pin "P$538") (pinfunction "P$1_P$538") (pintype "power_in"))
      (node (ref "P10") (pin "P$539") (pinfunction "P$1_P$539") (pintype "power_in"))
      (node (ref "P10") (pin "P$54") (pinfunction "P$1_P$54") (pintype "power_in"))
      (node (ref "P10") (pin "P$540") (pinfunction "P$1_P$540") (pintype "power_in"))
      (node (ref "P10") (pin "P$55") (pinfunction "P$1_P$55") (pintype "power_in"))
      (node (ref "P10") (pin "P$56") (pinfunction "P$1_P$56") (pintype "power_in"))
      (node (ref "P10") (pin "P$57") (pinfunction "P$1_P$57") (pintype "power_in"))
      (node (ref "P10") (pin "P$58") (pinfunction "P$1_P$58") (pintype "power_in"))
      (node (ref "P10") (pin "P$59") (pinfunction "P$1_P$59") (pintype "power_in"))
      (node (ref "P10") (pin "P$6") (pinfunction "P$1_P$6") (pintype "power_in"))
      (node (ref "P10") (pin "P$60") (pinfunction "P$1_P$60") (pintype "power_in"))
      (node (ref "P10") (pin "P$61") (pinfunction "P$1_P$61") (pintype "power_in"))
      (node (ref "P10") (pin "P$62") (pinfunction "P$1_P$62") (pintype "power_in"))
      (node (ref "P10") (pin "P$63") (pinfunction "P$1_P$63") (pintype "power_in"))
      (node (ref "P10") (pin "P$64") (pinfunction "P$1_P$64") (pintype "power_in"))
      (node (ref "P10") (pin "P$65") (pinfunction "P$1_P$65") (pintype "power_in"))
      (node (ref "P10") (pin "P$66") (pinfunction "P$1_P$66") (pintype "power_in"))
      (node (ref "P10") (pin "P$67") (pinfunction "P$1_P$67") (pintype "power_in"))
      (node (ref "P10") (pin "P$68") (pinfunction "P$1_P$68") (pintype "power_in"))
      (node (ref "P10") (pin "P$69") (pinfunction "P$1_P$69") (pintype "power_in"))
      (node (ref "P10") (pin "P$7") (pinfunction "P$1_P$7") (pintype "power_in"))
      (node (ref "P10") (pin "P$70") (pinfunction "P$1_P$70") (pintype "power_in"))
      (node (ref "P10") (pin "P$71") (pinfunction "P$1_P$71") (pintype "power_in"))
      (node (ref "P10") (pin "P$72") (pinfunction "P$1_P$72") (pintype "power_in"))
      (node (ref "P10") (pin "P$73") (pinfunction "P$1_P$73") (pintype "power_in"))
      (node (ref "P10") (pin "P$74") (pinfunction "P$1_P$74") (pintype "power_in"))
      (node (ref "P10") (pin "P$75") (pinfunction "P$1_P$75") (pintype "power_in"))
      (node (ref "P10") (pin "P$76") (pinfunction "P$1_P$76") (pintype "power_in"))
      (node (ref "P10") (pin "P$77") (pinfunction "P$1_P$77") (pintype "power_in"))
      (node (ref "P10") (pin "P$78") (pinfunction "P$1_P$78") (pintype "power_in"))
      (node (ref "P10") (pin "P$79") (pinfunction "P$1_P$79") (pintype "power_in"))
      (node (ref "P10") (pin "P$8") (pinfunction "P$1_P$8") (pintype "power_in"))
      (node (ref "P10") (pin "P$80") (pinfunction "P$1_P$80") (pintype "power_in"))
      (node (ref "P10") (pin "P$81") (pinfunction "P$1_P$81") (pintype "power_in"))
      (node (ref "P10") (pin "P$82") (pinfunction "P$1_P$82") (pintype "power_in"))
      (node (ref "P10") (pin "P$83") (pinfunction "P$1_P$83") (pintype "power_in"))
      (node (ref "P10") (pin "P$84") (pinfunction "P$1_P$84") (pintype "power_in"))
      (node (ref "P10") (pin "P$85") (pinfunction "P$1_P$85") (pintype "power_in"))
      (node (ref "P10") (pin "P$86") (pinfunction "P$1_P$86") (pintype "power_in"))
      (node (ref "P10") (pin "P$87") (pinfunction "P$1_P$87") (pintype "power_in"))
      (node (ref "P10") (pin "P$88") (pinfunction "P$1_P$88") (pintype "power_in"))
      (node (ref "P10") (pin "P$89") (pinfunction "P$1_P$89") (pintype "power_in"))
      (node (ref "P10") (pin "P$9") (pinfunction "P$1_P$9") (pintype "power_in"))
      (node (ref "P10") (pin "P$90") (pinfunction "P$1_P$90") (pintype "power_in"))
      (node (ref "P10") (pin "P$91") (pinfunction "P$1_P$91") (pintype "power_in"))
      (node (ref "P10") (pin "P$92") (pinfunction "P$1_P$92") (pintype "power_in"))
      (node (ref "P10") (pin "P$93") (pinfunction "P$1_P$93") (pintype "power_in"))
      (node (ref "P10") (pin "P$94") (pinfunction "P$1_P$94") (pintype "power_in"))
      (node (ref "P10") (pin "P$95") (pinfunction "P$1_P$95") (pintype "power_in"))
      (node (ref "P10") (pin "P$96") (pinfunction "P$1_P$96") (pintype "power_in"))
      (node (ref "P10") (pin "P$97") (pinfunction "P$1_P$97") (pintype "power_in"))
      (node (ref "P10") (pin "P$98") (pinfunction "P$1_P$98") (pintype "power_in"))
      (node (ref "P10") (pin "P$99") (pinfunction "P$1_P$99") (pintype "power_in"))
    )
    (net (code "12") (name "/P11") (class "Default")
      (node (ref "JP1") (pin "P$12") (pinfunction "11_P$12") (pintype "bidirectional"))
      (node (ref "P11") (pin "P$1") (pinfunction "P$1_P$1") (pintype "power_in"))
      (node (ref "P11") (pin "P$10") (pinfunction "P$1_P$10") (pintype "power_in"))
      (node (ref "P11") (pin "P$100") (pinfunction "P$1_P$100") (pintype "power_in"))
      (node (ref "P11") (pin "P$101") (pinfunction "P$1_P$101") (pintype "power_in"))
      (node (ref "P11") (pin "P$102") (pinfunction "P$1_P$102") (pintype "power_in"))
      (node (ref "P11") (pin "P$103") (pinfunction "P$1_P$103") (pintype "power_in"))
      (node (ref "P11") (pin "P$104") (pinfunction "P$1_P$104") (pintype "power_in"))
      (node (ref "P11") (pin "P$105") (pinfunction "P$1_P$105") (pintype "power_in"))
      (node (ref "P11") (pin "P$106") (pinfunction "P$1_P$106") (pintype "power_in"))
      (node (ref "P11") (pin "P$107") (pinfunction "P$1_P$107") (pintype "power_in"))
      (node (ref "P11") (pin "P$108") (pinfunction "P$1_P$108") (pintype "power_in"))
      (node (ref "P11") (pin "P$109") (pinfunction "P$1_P$109") (pintype "power_in"))
      (node (ref "P11") (pin "P$11") (pinfunction "P$1_P$11") (pintype "power_in"))
      (node (ref "P11") (pin "P$110") (pinfunction "P$1_P$110") (pintype "power_in"))
      (node (ref "P11") (pin "P$111") (pinfunction "P$1_P$111") (pintype "power_in"))
      (node (ref "P11") (pin "P$112") (pinfunction "P$1_P$112") (pintype "power_in"))
      (node (ref "P11") (pin "P$113") (pinfunction "P$1_P$113") (pintype "power_in"))
      (node (ref "P11") (pin "P$114") (pinfunction "P$1_P$114") (pintype "power_in"))
      (node (ref "P11") (pin "P$115") (pinfunction "P$1_P$115") (pintype "power_in"))
      (node (ref "P11") (pin "P$116") (pinfunction "P$1_P$116") (pintype "power_in"))
      (node (ref "P11") (pin "P$117") (pinfunction "P$1_P$117") (pintype "power_in"))
      (node (ref "P11") (pin "P$118") (pinfunction "P$1_P$118") (pintype "power_in"))
      (node (ref "P11") (pin "P$119") (pinfunction "P$1_P$119") (pintype "power_in"))
      (node (ref "P11") (pin "P$12") (pinfunction "P$1_P$12") (pintype "power_in"))
      (node (ref "P11") (pin "P$120") (pinfunction "P$1_P$120") (pintype "power_in"))
      (node (ref "P11") (pin "P$121") (pinfunction "P$1_P$121") (pintype "power_in"))
      (node (ref "P11") (pin "P$122") (pinfunction "P$1_P$122") (pintype "power_in"))
      (node (ref "P11") (pin "P$123") (pinfunction "P$1_P$123") (pintype "power_in"))
      (node (ref "P11") (pin "P$124") (pinfunction "P$1_P$124") (pintype "power_in"))
      (node (ref "P11") (pin "P$125") (pinfunction "P$1_P$125") (pintype "power_in"))
      (node (ref "P11") (pin "P$126") (pinfunction "P$1_P$126") (pintype "power_in"))
      (node (ref "P11") (pin "P$127") (pinfunction "P$1_P$127") (pintype "power_in"))
      (node (ref "P11") (pin "P$128") (pinfunction "P$1_P$128") (pintype "power_in"))
      (node (ref "P11") (pin "P$129") (pinfunction "P$1_P$129") (pintype "power_in"))
      (node (ref "P11") (pin "P$13") (pinfunction "P$1_P$13") (pintype "power_in"))
      (node (ref "P11") (pin "P$130") (pinfunction "P$1_P$130") (pintype "power_in"))
      (node (ref "P11") (pin "P$131") (pinfunction "P$1_P$131") (pintype "power_in"))
      (node (ref "P11") (pin "P$132") (pinfunction "P$1_P$132") (pintype "power_in"))
      (node (ref "P11") (pin "P$133") (pinfunction "P$1_P$133") (pintype "power_in"))
      (node (ref "P11") (pin "P$134") (pinfunction "P$1_P$134") (pintype "power_in"))
      (node (ref "P11") (pin "P$135") (pinfunction "P$1_P$135") (pintype "power_in"))
      (node (ref "P11") (pin "P$136") (pinfunction "P$1_P$136") (pintype "power_in"))
      (node (ref "P11") (pin "P$137") (pinfunction "P$1_P$137") (pintype "power_in"))
      (node (ref "P11") (pin "P$138") (pinfunction "P$1_P$138") (pintype "power_in"))
      (node (ref "P11") (pin "P$139") (pinfunction "P$1_P$139") (pintype "power_in"))
      (node (ref "P11") (pin "P$14") (pinfunction "P$1_P$14") (pintype "power_in"))
      (node (ref "P11") (pin "P$140") (pinfunction "P$1_P$140") (pintype "power_in"))
      (node (ref "P11") (pin "P$141") (pinfunction "P$1_P$141") (pintype "power_in"))
      (node (ref "P11") (pin "P$142") (pinfunction "P$1_P$142") (pintype "power_in"))
      (node (ref "P11") (pin "P$143") (pinfunction "P$1_P$143") (pintype "power_in"))
      (node (ref "P11") (pin "P$144") (pinfunction "P$1_P$144") (pintype "power_in"))
      (node (ref "P11") (pin "P$145") (pinfunction "P$1_P$145") (pintype "power_in"))
      (node (ref "P11") (pin "P$146") (pinfunction "P$1_P$146") (pintype "power_in"))
      (node (ref "P11") (pin "P$147") (pinfunction "P$1_P$147") (pintype "power_in"))
      (node (ref "P11") (pin "P$148") (pinfunction "P$1_P$148") (pintype "power_in"))
      (node (ref "P11") (pin "P$149") (pinfunction "P$1_P$149") (pintype "power_in"))
      (node (ref "P11") (pin "P$15") (pinfunction "P$1_P$15") (pintype "power_in"))
      (node (ref "P11") (pin "P$150") (pinfunction "P$1_P$150") (pintype "power_in"))
      (node (ref "P11") (pin "P$151") (pinfunction "P$1_P$151") (pintype "power_in"))
      (node (ref "P11") (pin "P$152") (pinfunction "P$1_P$152") (pintype "power_in"))
      (node (ref "P11") (pin "P$153") (pinfunction "P$1_P$153") (pintype "power_in"))
      (node (ref "P11") (pin "P$154") (pinfunction "P$1_P$154") (pintype "power_in"))
      (node (ref "P11") (pin "P$155") (pinfunction "P$1_P$155") (pintype "power_in"))
      (node (ref "P11") (pin "P$156") (pinfunction "P$1_P$156") (pintype "power_in"))
      (node (ref "P11") (pin "P$157") (pinfunction "P$1_P$157") (pintype "power_in"))
      (node (ref "P11") (pin "P$158") (pinfunction "P$1_P$158") (pintype "power_in"))
      (node (ref "P11") (pin "P$159") (pinfunction "P$1_P$159") (pintype "power_in"))
      (node (ref "P11") (pin "P$16") (pinfunction "P$1_P$16") (pintype "power_in"))
      (node (ref "P11") (pin "P$160") (pinfunction "P$1_P$160") (pintype "power_in"))
      (node (ref "P11") (pin "P$161") (pinfunction "P$1_P$161") (pintype "power_in"))
      (node (ref "P11") (pin "P$162") (pinfunction "P$1_P$162") (pintype "power_in"))
      (node (ref "P11") (pin "P$163") (pinfunction "P$1_P$163") (pintype "power_in"))
      (node (ref "P11") (pin "P$164") (pinfunction "P$1_P$164") (pintype "power_in"))
      (node (ref "P11") (pin "P$165") (pinfunction "P$1_P$165") (pintype "power_in"))
      (node (ref "P11") (pin "P$166") (pinfunction "P$1_P$166") (pintype "power_in"))
      (node (ref "P11") (pin "P$167") (pinfunction "P$1_P$167") (pintype "power_in"))
      (node (ref "P11") (pin "P$168") (pinfunction "P$1_P$168") (pintype "power_in"))
      (node (ref "P11") (pin "P$169") (pinfunction "P$1_P$169") (pintype "power_in"))
      (node (ref "P11") (pin "P$17") (pinfunction "P$1_P$17") (pintype "power_in"))
      (node (ref "P11") (pin "P$170") (pinfunction "P$1_P$170") (pintype "power_in"))
      (node (ref "P11") (pin "P$171") (pinfunction "P$1_P$171") (pintype "power_in"))
      (node (ref "P11") (pin "P$172") (pinfunction "P$1_P$172") (pintype "power_in"))
      (node (ref "P11") (pin "P$173") (pinfunction "P$1_P$173") (pintype "power_in"))
      (node (ref "P11") (pin "P$174") (pinfunction "P$1_P$174") (pintype "power_in"))
      (node (ref "P11") (pin "P$175") (pinfunction "P$1_P$175") (pintype "power_in"))
      (node (ref "P11") (pin "P$176") (pinfunction "P$1_P$176") (pintype "power_in"))
      (node (ref "P11") (pin "P$177") (pinfunction "P$1_P$177") (pintype "power_in"))
      (node (ref "P11") (pin "P$178") (pinfunction "P$1_P$178") (pintype "power_in"))
      (node (ref "P11") (pin "P$179") (pinfunction "P$1_P$179") (pintype "power_in"))
      (node (ref "P11") (pin "P$18") (pinfunction "P$1_P$18") (pintype "power_in"))
      (node (ref "P11") (pin "P$180") (pinfunction "P$1_P$180") (pintype "power_in"))
      (node (ref "P11") (pin "P$181") (pinfunction "P$1_P$181") (pintype "power_in"))
      (node (ref "P11") (pin "P$182") (pinfunction "P$1_P$182") (pintype "power_in"))
      (node (ref "P11") (pin "P$183") (pinfunction "P$1_P$183") (pintype "power_in"))
      (node (ref "P11") (pin "P$184") (pinfunction "P$1_P$184") (pintype "power_in"))
      (node (ref "P11") (pin "P$185") (pinfunction "P$1_P$185") (pintype "power_in"))
      (node (ref "P11") (pin "P$186") (pinfunction "P$1_P$186") (pintype "power_in"))
      (node (ref "P11") (pin "P$187") (pinfunction "P$1_P$187") (pintype "power_in"))
      (node (ref "P11") (pin "P$188") (pinfunction "P$1_P$188") (pintype "power_in"))
      (node (ref "P11") (pin "P$189") (pinfunction "P$1_P$189") (pintype "power_in"))
      (node (ref "P11") (pin "P$19") (pinfunction "P$1_P$19") (pintype "power_in"))
      (node (ref "P11") (pin "P$190") (pinfunction "P$1_P$190") (pintype "power_in"))
      (node (ref "P11") (pin "P$191") (pinfunction "P$1_P$191") (pintype "power_in"))
      (node (ref "P11") (pin "P$192") (pinfunction "P$1_P$192") (pintype "power_in"))
      (node (ref "P11") (pin "P$193") (pinfunction "P$1_P$193") (pintype "power_in"))
      (node (ref "P11") (pin "P$194") (pinfunction "P$1_P$194") (pintype "power_in"))
      (node (ref "P11") (pin "P$195") (pinfunction "P$1_P$195") (pintype "power_in"))
      (node (ref "P11") (pin "P$196") (pinfunction "P$1_P$196") (pintype "power_in"))
      (node (ref "P11") (pin "P$197") (pinfunction "P$1_P$197") (pintype "power_in"))
      (node (ref "P11") (pin "P$198") (pinfunction "P$1_P$198") (pintype "power_in"))
      (node (ref "P11") (pin "P$199") (pinfunction "P$1_P$199") (pintype "power_in"))
      (node (ref "P11") (pin "P$2") (pinfunction "P$1_P$2") (pintype "power_in"))
      (node (ref "P11") (pin "P$20") (pinfunction "P$1_P$20") (pintype "power_in"))
      (node (ref "P11") (pin "P$200") (pinfunction "P$1_P$200") (pintype "power_in"))
      (node (ref "P11") (pin "P$201") (pinfunction "P$1_P$201") (pintype "power_in"))
      (node (ref "P11") (pin "P$202") (pinfunction "P$1_P$202") (pintype "power_in"))
      (node (ref "P11") (pin "P$203") (pinfunction "P$1_P$203") (pintype "power_in"))
      (node (ref "P11") (pin "P$204") (pinfunction "P$1_P$204") (pintype "power_in"))
      (node (ref "P11") (pin "P$205") (pinfunction "P$1_P$205") (pintype "power_in"))
      (node (ref "P11") (pin "P$206") (pinfunction "P$1_P$206") (pintype "power_in"))
      (node (ref "P11") (pin "P$207") (pinfunction "P$1_P$207") (pintype "power_in"))
      (node (ref "P11") (pin "P$208") (pinfunction "P$1_P$208") (pintype "power_in"))
      (node (ref "P11") (pin "P$209") (pinfunction "P$1_P$209") (pintype "power_in"))
      (node (ref "P11") (pin "P$21") (pinfunction "P$1_P$21") (pintype "power_in"))
      (node (ref "P11") (pin "P$210") (pinfunction "P$1_P$210") (pintype "power_in"))
      (node (ref "P11") (pin "P$211") (pinfunction "P$1_P$211") (pintype "power_in"))
      (node (ref "P11") (pin "P$212") (pinfunction "P$1_P$212") (pintype "power_in"))
      (node (ref "P11") (pin "P$213") (pinfunction "P$1_P$213") (pintype "power_in"))
      (node (ref "P11") (pin "P$214") (pinfunction "P$1_P$214") (pintype "power_in"))
      (node (ref "P11") (pin "P$215") (pinfunction "P$1_P$215") (pintype "power_in"))
      (node (ref "P11") (pin "P$216") (pinfunction "P$1_P$216") (pintype "power_in"))
      (node (ref "P11") (pin "P$217") (pinfunction "P$1_P$217") (pintype "power_in"))
      (node (ref "P11") (pin "P$218") (pinfunction "P$1_P$218") (pintype "power_in"))
      (node (ref "P11") (pin "P$219") (pinfunction "P$1_P$219") (pintype "power_in"))
      (node (ref "P11") (pin "P$22") (pinfunction "P$1_P$22") (pintype "power_in"))
      (node (ref "P11") (pin "P$220") (pinfunction "P$1_P$220") (pintype "power_in"))
      (node (ref "P11") (pin "P$221") (pinfunction "P$1_P$221") (pintype "power_in"))
      (node (ref "P11") (pin "P$222") (pinfunction "P$1_P$222") (pintype "power_in"))
      (node (ref "P11") (pin "P$223") (pinfunction "P$1_P$223") (pintype "power_in"))
      (node (ref "P11") (pin "P$224") (pinfunction "P$1_P$224") (pintype "power_in"))
      (node (ref "P11") (pin "P$225") (pinfunction "P$1_P$225") (pintype "power_in"))
      (node (ref "P11") (pin "P$226") (pinfunction "P$1_P$226") (pintype "power_in"))
      (node (ref "P11") (pin "P$227") (pinfunction "P$1_P$227") (pintype "power_in"))
      (node (ref "P11") (pin "P$228") (pinfunction "P$1_P$228") (pintype "power_in"))
      (node (ref "P11") (pin "P$229") (pinfunction "P$1_P$229") (pintype "power_in"))
      (node (ref "P11") (pin "P$23") (pinfunction "P$1_P$23") (pintype "power_in"))
      (node (ref "P11") (pin "P$230") (pinfunction "P$1_P$230") (pintype "power_in"))
      (node (ref "P11") (pin "P$231") (pinfunction "P$1_P$231") (pintype "power_in"))
      (node (ref "P11") (pin "P$232") (pinfunction "P$1_P$232") (pintype "power_in"))
      (node (ref "P11") (pin "P$233") (pinfunction "P$1_P$233") (pintype "power_in"))
      (node (ref "P11") (pin "P$234") (pinfunction "P$1_P$234") (pintype "power_in"))
      (node (ref "P11") (pin "P$235") (pinfunction "P$1_P$235") (pintype "power_in"))
      (node (ref "P11") (pin "P$236") (pinfunction "P$1_P$236") (pintype "power_in"))
      (node (ref "P11") (pin "P$237") (pinfunction "P$1_P$237") (pintype "power_in"))
      (node (ref "P11") (pin "P$238") (pinfunction "P$1_P$238") (pintype "power_in"))
      (node (ref "P11") (pin "P$239") (pinfunction "P$1_P$239") (pintype "power_in"))
      (node (ref "P11") (pin "P$24") (pinfunction "P$1_P$24") (pintype "power_in"))
      (node (ref "P11") (pin "P$240") (pinfunction "P$1_P$240") (pintype "power_in"))
      (node (ref "P11") (pin "P$241") (pinfunction "P$1_P$241") (pintype "power_in"))
      (node (ref "P11") (pin "P$242") (pinfunction "P$1_P$242") (pintype "power_in"))
      (node (ref "P11") (pin "P$243") (pinfunction "P$1_P$243") (pintype "power_in"))
      (node (ref "P11") (pin "P$244") (pinfunction "P$1_P$244") (pintype "power_in"))
      (node (ref "P11") (pin "P$245") (pinfunction "P$1_P$245") (pintype "power_in"))
      (node (ref "P11") (pin "P$246") (pinfunction "P$1_P$246") (pintype "power_in"))
      (node (ref "P11") (pin "P$247") (pinfunction "P$1_P$247") (pintype "power_in"))
      (node (ref "P11") (pin "P$248") (pinfunction "P$1_P$248") (pintype "power_in"))
      (node (ref "P11") (pin "P$249") (pinfunction "P$1_P$249") (pintype "power_in"))
      (node (ref "P11") (pin "P$25") (pinfunction "P$1_P$25") (pintype "power_in"))
      (node (ref "P11") (pin "P$250") (pinfunction "P$1_P$250") (pintype "power_in"))
      (node (ref "P11") (pin "P$251") (pinfunction "P$1_P$251") (pintype "power_in"))
      (node (ref "P11") (pin "P$252") (pinfunction "P$1_P$252") (pintype "power_in"))
      (node (ref "P11") (pin "P$253") (pinfunction "P$1_P$253") (pintype "power_in"))
      (node (ref "P11") (pin "P$254") (pinfunction "P$1_P$254") (pintype "power_in"))
      (node (ref "P11") (pin "P$255") (pinfunction "P$1_P$255") (pintype "power_in"))
      (node (ref "P11") (pin "P$256") (pinfunction "P$1_P$256") (pintype "power_in"))
      (node (ref "P11") (pin "P$257") (pinfunction "P$1_P$257") (pintype "power_in"))
      (node (ref "P11") (pin "P$258") (pinfunction "P$1_P$258") (pintype "power_in"))
      (node (ref "P11") (pin "P$259") (pinfunction "P$1_P$259") (pintype "power_in"))
      (node (ref "P11") (pin "P$26") (pinfunction "P$1_P$26") (pintype "power_in"))
      (node (ref "P11") (pin "P$260") (pinfunction "P$1_P$260") (pintype "power_in"))
      (node (ref "P11") (pin "P$261") (pinfunction "P$1_P$261") (pintype "power_in"))
      (node (ref "P11") (pin "P$262") (pinfunction "P$1_P$262") (pintype "power_in"))
      (node (ref "P11") (pin "P$263") (pinfunction "P$1_P$263") (pintype "power_in"))
      (node (ref "P11") (pin "P$264") (pinfunction "P$1_P$264") (pintype "power_in"))
      (node (ref "P11") (pin "P$265") (pinfunction "P$1_P$265") (pintype "power_in"))
      (node (ref "P11") (pin "P$266") (pinfunction "P$1_P$266") (pintype "power_in"))
      (node (ref "P11") (pin "P$267") (pinfunction "P$1_P$267") (pintype "power_in"))
      (node (ref "P11") (pin "P$268") (pinfunction "P$1_P$268") (pintype "power_in"))
      (node (ref "P11") (pin "P$269") (pinfunction "P$1_P$269") (pintype "power_in"))
      (node (ref "P11") (pin "P$27") (pinfunction "P$1_P$27") (pintype "power_in"))
      (node (ref "P11") (pin "P$270") (pinfunction "P$1_P$270") (pintype "power_in"))
      (node (ref "P11") (pin "P$271") (pinfunction "P$1_P$271") (pintype "power_in"))
      (node (ref "P11") (pin "P$272") (pinfunction "P$1_P$272") (pintype "power_in"))
      (node (ref "P11") (pin "P$273") (pinfunction "P$1_P$273") (pintype "power_in"))
      (node (ref "P11") (pin "P$274") (pinfunction "P$1_P$274") (pintype "power_in"))
      (node (ref "P11") (pin "P$275") (pinfunction "P$1_P$275") (pintype "power_in"))
      (node (ref "P11") (pin "P$276") (pinfunction "P$1_P$276") (pintype "power_in"))
      (node (ref "P11") (pin "P$277") (pinfunction "P$1_P$277") (pintype "power_in"))
      (node (ref "P11") (pin "P$278") (pinfunction "P$1_P$278") (pintype "power_in"))
      (node (ref "P11") (pin "P$279") (pinfunction "P$1_P$279") (pintype "power_in"))
      (node (ref "P11") (pin "P$28") (pinfunction "P$1_P$28") (pintype "power_in"))
      (node (ref "P11") (pin "P$280") (pinfunction "P$1_P$280") (pintype "power_in"))
      (node (ref "P11") (pin "P$281") (pinfunction "P$1_P$281") (pintype "power_in"))
      (node (ref "P11") (pin "P$282") (pinfunction "P$1_P$282") (pintype "power_in"))
      (node (ref "P11") (pin "P$283") (pinfunction "P$1_P$283") (pintype "power_in"))
      (node (ref "P11") (pin "P$284") (pinfunction "P$1_P$284") (pintype "power_in"))
      (node (ref "P11") (pin "P$285") (pinfunction "P$1_P$285") (pintype "power_in"))
      (node (ref "P11") (pin "P$286") (pinfunction "P$1_P$286") (pintype "power_in"))
      (node (ref "P11") (pin "P$287") (pinfunction "P$1_P$287") (pintype "power_in"))
      (node (ref "P11") (pin "P$288") (pinfunction "P$1_P$288") (pintype "power_in"))
      (node (ref "P11") (pin "P$29") (pinfunction "P$1_P$29") (pintype "power_in"))
      (node (ref "P11") (pin "P$3") (pinfunction "P$1_P$3") (pintype "power_in"))
      (node (ref "P11") (pin "P$30") (pinfunction "P$1_P$30") (pintype "power_in"))
      (node (ref "P11") (pin "P$31") (pinfunction "P$1_P$31") (pintype "power_in"))
      (node (ref "P11") (pin "P$32") (pinfunction "P$1_P$32") (pintype "power_in"))
      (node (ref "P11") (pin "P$33") (pinfunction "P$1_P$33") (pintype "power_in"))
      (node (ref "P11") (pin "P$34") (pinfunction "P$1_P$34") (pintype "power_in"))
      (node (ref "P11") (pin "P$35") (pinfunction "P$1_P$35") (pintype "power_in"))
      (node (ref "P11") (pin "P$36") (pinfunction "P$1_P$36") (pintype "power_in"))
      (node (ref "P11") (pin "P$37") (pinfunction "P$1_P$37") (pintype "power_in"))
      (node (ref "P11") (pin "P$38") (pinfunction "P$1_P$38") (pintype "power_in"))
      (node (ref "P11") (pin "P$39") (pinfunction "P$1_P$39") (pintype "power_in"))
      (node (ref "P11") (pin "P$4") (pinfunction "P$1_P$4") (pintype "power_in"))
      (node (ref "P11") (pin "P$40") (pinfunction "P$1_P$40") (pintype "power_in"))
      (node (ref "P11") (pin "P$41") (pinfunction "P$1_P$41") (pintype "power_in"))
      (node (ref "P11") (pin "P$42") (pinfunction "P$1_P$42") (pintype "power_in"))
      (node (ref "P11") (pin "P$43") (pinfunction "P$1_P$43") (pintype "power_in"))
      (node (ref "P11") (pin "P$44") (pinfunction "P$1_P$44") (pintype "power_in"))
      (node (ref "P11") (pin "P$45") (pinfunction "P$1_P$45") (pintype "power_in"))
      (node (ref "P11") (pin "P$46") (pinfunction "P$1_P$46") (pintype "power_in"))
      (node (ref "P11") (pin "P$47") (pinfunction "P$1_P$47") (pintype "power_in"))
      (node (ref "P11") (pin "P$48") (pinfunction "P$1_P$48") (pintype "power_in"))
      (node (ref "P11") (pin "P$49") (pinfunction "P$1_P$49") (pintype "power_in"))
      (node (ref "P11") (pin "P$5") (pinfunction "P$1_P$5") (pintype "power_in"))
      (node (ref "P11") (pin "P$50") (pinfunction "P$1_P$50") (pintype "power_in"))
      (node (ref "P11") (pin "P$51") (pinfunction "P$1_P$51") (pintype "power_in"))
      (node (ref "P11") (pin "P$52") (pinfunction "P$1_P$52") (pintype "power_in"))
      (node (ref "P11") (pin "P$53") (pinfunction "P$1_P$53") (pintype "power_in"))
      (node (ref "P11") (pin "P$54") (pinfunction "P$1_P$54") (pintype "power_in"))
      (node (ref "P11") (pin "P$55") (pinfunction "P$1_P$55") (pintype "power_in"))
      (node (ref "P11") (pin "P$56") (pinfunction "P$1_P$56") (pintype "power_in"))
      (node (ref "P11") (pin "P$57") (pinfunction "P$1_P$57") (pintype "power_in"))
      (node (ref "P11") (pin "P$58") (pinfunction "P$1_P$58") (pintype "power_in"))
      (node (ref "P11") (pin "P$59") (pinfunction "P$1_P$59") (pintype "power_in"))
      (node (ref "P11") (pin "P$6") (pinfunction "P$1_P$6") (pintype "power_in"))
      (node (ref "P11") (pin "P$60") (pinfunction "P$1_P$60") (pintype "power_in"))
      (node (ref "P11") (pin "P$61") (pinfunction "P$1_P$61") (pintype "power_in"))
      (node (ref "P11") (pin "P$62") (pinfunction "P$1_P$62") (pintype "power_in"))
      (node (ref "P11") (pin "P$63") (pinfunction "P$1_P$63") (pintype "power_in"))
      (node (ref "P11") (pin "P$64") (pinfunction "P$1_P$64") (pintype "power_in"))
      (node (ref "P11") (pin "P$65") (pinfunction "P$1_P$65") (pintype "power_in"))
      (node (ref "P11") (pin "P$66") (pinfunction "P$1_P$66") (pintype "power_in"))
      (node (ref "P11") (pin "P$67") (pinfunction "P$1_P$67") (pintype "power_in"))
      (node (ref "P11") (pin "P$68") (pinfunction "P$1_P$68") (pintype "power_in"))
      (node (ref "P11") (pin "P$69") (pinfunction "P$1_P$69") (pintype "power_in"))
      (node (ref "P11") (pin "P$7") (pinfunction "P$1_P$7") (pintype "power_in"))
      (node (ref "P11") (pin "P$70") (pinfunction "P$1_P$70") (pintype "power_in"))
      (node (ref "P11") (pin "P$71") (pinfunction "P$1_P$71") (pintype "power_in"))
      (node (ref "P11") (pin "P$72") (pinfunction "P$1_P$72") (pintype "power_in"))
      (node (ref "P11") (pin "P$73") (pinfunction "P$1_P$73") (pintype "power_in"))
      (node (ref "P11") (pin "P$74") (pinfunction "P$1_P$74") (pintype "power_in"))
      (node (ref "P11") (pin "P$75") (pinfunction "P$1_P$75") (pintype "power_in"))
      (node (ref "P11") (pin "P$76") (pinfunction "P$1_P$76") (pintype "power_in"))
      (node (ref "P11") (pin "P$77") (pinfunction "P$1_P$77") (pintype "power_in"))
      (node (ref "P11") (pin "P$78") (pinfunction "P$1_P$78") (pintype "power_in"))
      (node (ref "P11") (pin "P$79") (pinfunction "P$1_P$79") (pintype "power_in"))
      (node (ref "P11") (pin "P$8") (pinfunction "P$1_P$8") (pintype "power_in"))
      (node (ref "P11") (pin "P$80") (pinfunction "P$1_P$80") (pintype "power_in"))
      (node (ref "P11") (pin "P$81") (pinfunction "P$1_P$81") (pintype "power_in"))
      (node (ref "P11") (pin "P$82") (pinfunction "P$1_P$82") (pintype "power_in"))
      (node (ref "P11") (pin "P$83") (pinfunction "P$1_P$83") (pintype "power_in"))
      (node (ref "P11") (pin "P$84") (pinfunction "P$1_P$84") (pintype "power_in"))
      (node (ref "P11") (pin "P$85") (pinfunction "P$1_P$85") (pintype "power_in"))
      (node (ref "P11") (pin "P$86") (pinfunction "P$1_P$86") (pintype "power_in"))
      (node (ref "P11") (pin "P$87") (pinfunction "P$1_P$87") (pintype "power_in"))
      (node (ref "P11") (pin "P$88") (pinfunction "P$1_P$88") (pintype "power_in"))
      (node (ref "P11") (pin "P$89") (pinfunction "P$1_P$89") (pintype "power_in"))
      (node (ref "P11") (pin "P$9") (pinfunction "P$1_P$9") (pintype "power_in"))
      (node (ref "P11") (pin "P$90") (pinfunction "P$1_P$90") (pintype "power_in"))
      (node (ref "P11") (pin "P$91") (pinfunction "P$1_P$91") (pintype "power_in"))
      (node (ref "P11") (pin "P$92") (pinfunction "P$1_P$92") (pintype "power_in"))
      (node (ref "P11") (pin "P$93") (pinfunction "P$1_P$93") (pintype "power_in"))
      (node (ref "P11") (pin "P$94") (pinfunction "P$1_P$94") (pintype "power_in"))
      (node (ref "P11") (pin "P$95") (pinfunction "P$1_P$95") (pintype "power_in"))
      (node (ref "P11") (pin "P$96") (pinfunction "P$1_P$96") (pintype "power_in"))
      (node (ref "P11") (pin "P$97") (pinfunction "P$1_P$97") (pintype "power_in"))
      (node (ref "P11") (pin "P$98") (pinfunction "P$1_P$98") (pintype "power_in"))
      (node (ref "P11") (pin "P$99") (pinfunction "P$1_P$99") (pintype "power_in"))
    )
    (net (code "13") (name "/P12+") (class "Default")
      (node (ref "J1") (pin "1") (pinfunction "1_1") (pintype "bidirectional"))
      (node (ref "J1") (pin "10") (pinfunction "10_10") (pintype "bidirectional"))
      (node (ref "J1") (pin "11") (pinfunction "11_11") (pintype "bidirectional"))
      (node (ref "J1") (pin "12") (pinfunction "12_12") (pintype "bidirectional"))
      (node (ref "J1") (pin "2") (pinfunction "2_2") (pintype "bidirectional"))
      (node (ref "J1") (pin "3") (pinfunction "3_3") (pintype "bidirectional"))
      (node (ref "J1") (pin "4") (pinfunction "4_4") (pintype "bidirectional"))
      (node (ref "J1") (pin "5") (pinfunction "5_5") (pintype "bidirectional"))
      (node (ref "J1") (pin "6") (pinfunction "6_6") (pintype "bidirectional"))
      (node (ref "J1") (pin "7") (pinfunction "7_7") (pintype "bidirectional"))
      (node (ref "J1") (pin "8") (pinfunction "8_8") (pintype "bidirectional"))
      (node (ref "J1") (pin "9") (pinfunction "9_9") (pintype "bidirectional"))
      (node (ref "JP1") (pin "P$13") (pinfunction "12_P$13") (pintype "bidirectional"))
      (node (ref "P12") (pin "P$10") (pinfunction "P$0_P$10") (pintype "power_in"))
      (node (ref "P12") (pin "P$100") (pinfunction "P$0_P$100") (pintype "power_in"))
      (node (ref "P12") (pin "P$101") (pinfunction "P$0_P$101") (pintype "power_in"))
      (node (ref "P12") (pin "P$102") (pinfunction "P$0_P$102") (pintype "power_in"))
      (node (ref "P12") (pin "P$103") (pinfunction "P$0_P$103") (pintype "power_in"))
      (node (ref "P12") (pin "P$104") (pinfunction "P$0_P$104") (pintype "power_in"))
      (node (ref "P12") (pin "P$105") (pinfunction "P$0_P$105") (pintype "power_in"))
      (node (ref "P12") (pin "P$106") (pinfunction "P$0_P$106") (pintype "power_in"))
      (node (ref "P12") (pin "P$107") (pinfunction "P$0_P$107") (pintype "power_in"))
      (node (ref "P12") (pin "P$108") (pinfunction "P$0_P$108") (pintype "power_in"))
      (node (ref "P12") (pin "P$109") (pinfunction "P$0_P$109") (pintype "power_in"))
      (node (ref "P12") (pin "P$11") (pinfunction "P$0_P$11") (pintype "power_in"))
      (node (ref "P12") (pin "P$110") (pinfunction "P$0_P$110") (pintype "power_in"))
      (node (ref "P12") (pin "P$12") (pinfunction "P$0_P$12") (pintype "power_in"))
      (node (ref "P12") (pin "P$13") (pinfunction "P$0_P$13") (pintype "power_in"))
      (node (ref "P12") (pin "P$14") (pinfunction "P$0_P$14") (pintype "power_in"))
      (node (ref "P12") (pin "P$15") (pinfunction "P$0_P$15") (pintype "power_in"))
      (node (ref "P12") (pin "P$16") (pinfunction "P$0_P$16") (pintype "power_in"))
      (node (ref "P12") (pin "P$17") (pinfunction "P$0_P$17") (pintype "power_in"))
      (node (ref "P12") (pin "P$18") (pinfunction "P$0_P$18") (pintype "power_in"))
      (node (ref "P12") (pin "P$181") (pinfunction "P$0_P$181") (pintype "power_in"))
      (node (ref "P12") (pin "P$182") (pinfunction "P$0_P$182") (pintype "power_in"))
      (node (ref "P12") (pin "P$183") (pinfunction "P$0_P$183") (pintype "power_in"))
      (node (ref "P12") (pin "P$184") (pinfunction "P$0_P$184") (pintype "power_in"))
      (node (ref "P12") (pin "P$185") (pinfunction "P$0_P$185") (pintype "power_in"))
      (node (ref "P12") (pin "P$186") (pinfunction "P$0_P$186") (pintype "power_in"))
      (node (ref "P12") (pin "P$187") (pinfunction "P$0_P$187") (pintype "power_in"))
      (node (ref "P12") (pin "P$188") (pinfunction "P$0_P$188") (pintype "power_in"))
      (node (ref "P12") (pin "P$189") (pinfunction "P$0_P$189") (pintype "power_in"))
      (node (ref "P12") (pin "P$19") (pinfunction "P$0_P$19") (pintype "power_in"))
      (node (ref "P12") (pin "P$190") (pinfunction "P$0_P$190") (pintype "power_in"))
      (node (ref "P12") (pin "P$191") (pinfunction "P$0_P$191") (pintype "power_in"))
      (node (ref "P12") (pin "P$192") (pinfunction "P$0_P$192") (pintype "power_in"))
      (node (ref "P12") (pin "P$193") (pinfunction "P$0_P$193") (pintype "power_in"))
      (node (ref "P12") (pin "P$194") (pinfunction "P$0_P$194") (pintype "power_in"))
      (node (ref "P12") (pin "P$195") (pinfunction "P$0_P$195") (pintype "power_in"))
      (node (ref "P12") (pin "P$196") (pinfunction "P$0_P$196") (pintype "power_in"))
      (node (ref "P12") (pin "P$197") (pinfunction "P$0_P$197") (pintype "power_in"))
      (node (ref "P12") (pin "P$198") (pinfunction "P$0_P$198") (pintype "power_in"))
      (node (ref "P12") (pin "P$199") (pinfunction "P$0_P$199") (pintype "power_in"))
      (node (ref "P12") (pin "P$20") (pinfunction "P$0_P$20") (pintype "power_in"))
      (node (ref "P12") (pin "P$200") (pinfunction "P$0_P$200") (pintype "power_in"))
      (node (ref "P12") (pin "P$201") (pinfunction "P$0_P$201") (pintype "power_in"))
      (node (ref "P12") (pin "P$202") (pinfunction "P$0_P$202") (pintype "power_in"))
      (node (ref "P12") (pin "P$203") (pinfunction "P$0_P$203") (pintype "power_in"))
      (node (ref "P12") (pin "P$204") (pinfunction "P$0_P$204") (pintype "power_in"))
      (node (ref "P12") (pin "P$205") (pinfunction "P$0_P$205") (pintype "power_in"))
      (node (ref "P12") (pin "P$206") (pinfunction "P$0_P$206") (pintype "power_in"))
      (node (ref "P12") (pin "P$207") (pinfunction "P$0_P$207") (pintype "power_in"))
      (node (ref "P12") (pin "P$208") (pinfunction "P$0_P$208") (pintype "power_in"))
      (node (ref "P12") (pin "P$209") (pinfunction "P$0_P$209") (pintype "power_in"))
      (node (ref "P12") (pin "P$21") (pinfunction "P$0_P$21") (pintype "power_in"))
      (node (ref "P12") (pin "P$210") (pinfunction "P$0_P$210") (pintype "power_in"))
      (node (ref "P12") (pin "P$211") (pinfunction "P$0_P$211") (pintype "power_in"))
      (node (ref "P12") (pin "P$212") (pinfunction "P$0_P$212") (pintype "power_in"))
      (node (ref "P12") (pin "P$213") (pinfunction "P$0_P$213") (pintype "power_in"))
      (node (ref "P12") (pin "P$214") (pinfunction "P$0_P$214") (pintype "power_in"))
      (node (ref "P12") (pin "P$215") (pinfunction "P$0_P$215") (pintype "power_in"))
      (node (ref "P12") (pin "P$216") (pinfunction "P$0_P$216") (pintype "power_in"))
      (node (ref "P12") (pin "P$217") (pinfunction "P$0_P$217") (pintype "power_in"))
      (node (ref "P12") (pin "P$218") (pinfunction "P$0_P$218") (pintype "power_in"))
      (node (ref "P12") (pin "P$219") (pinfunction "P$0_P$219") (pintype "power_in"))
      (node (ref "P12") (pin "P$22") (pinfunction "P$0_P$22") (pintype "power_in"))
      (node (ref "P12") (pin "P$220") (pinfunction "P$0_P$220") (pintype "power_in"))
      (node (ref "P12") (pin "P$221") (pinfunction "P$0_P$221") (pintype "power_in"))
      (node (ref "P12") (pin "P$222") (pinfunction "P$0_P$222") (pintype "power_in"))
      (node (ref "P12") (pin "P$223") (pinfunction "P$0_P$223") (pintype "power_in"))
      (node (ref "P12") (pin "P$224") (pinfunction "P$0_P$224") (pintype "power_in"))
      (node (ref "P12") (pin "P$225") (pinfunction "P$0_P$225") (pintype "power_in"))
      (node (ref "P12") (pin "P$226") (pinfunction "P$0_P$226") (pintype "power_in"))
      (node (ref "P12") (pin "P$227") (pinfunction "P$0_P$227") (pintype "power_in"))
      (node (ref "P12") (pin "P$228") (pinfunction "P$0_P$228") (pintype "power_in"))
      (node (ref "P12") (pin "P$229") (pinfunction "P$0_P$229") (pintype "power_in"))
      (node (ref "P12") (pin "P$23") (pinfunction "P$0_P$23") (pintype "power_in"))
      (node (ref "P12") (pin "P$230") (pinfunction "P$0_P$230") (pintype "power_in"))
      (node (ref "P12") (pin "P$231") (pinfunction "P$0_P$231") (pintype "power_in"))
      (node (ref "P12") (pin "P$232") (pinfunction "P$0_P$232") (pintype "power_in"))
      (node (ref "P12") (pin "P$233") (pinfunction "P$0_P$233") (pintype "power_in"))
      (node (ref "P12") (pin "P$234") (pinfunction "P$0_P$234") (pintype "power_in"))
      (node (ref "P12") (pin "P$235") (pinfunction "P$0_P$235") (pintype "power_in"))
      (node (ref "P12") (pin "P$236") (pinfunction "P$0_P$236") (pintype "power_in"))
      (node (ref "P12") (pin "P$237") (pinfunction "P$0_P$237") (pintype "power_in"))
      (node (ref "P12") (pin "P$238") (pinfunction "P$0_P$238") (pintype "power_in"))
      (node (ref "P12") (pin "P$239") (pinfunction "P$0_P$239") (pintype "power_in"))
      (node (ref "P12") (pin "P$24") (pinfunction "P$0_P$24") (pintype "power_in"))
      (node (ref "P12") (pin "P$240") (pinfunction "P$0_P$240") (pintype "power_in"))
      (node (ref "P12") (pin "P$241") (pinfunction "P$0_P$241") (pintype "power_in"))
      (node (ref "P12") (pin "P$242") (pinfunction "P$0_P$242") (pintype "power_in"))
      (node (ref "P12") (pin "P$243") (pinfunction "P$0_P$243") (pintype "power_in"))
      (node (ref "P12") (pin "P$244") (pinfunction "P$0_P$244") (pintype "power_in"))
      (node (ref "P12") (pin "P$245") (pinfunction "P$0_P$245") (pintype "power_in"))
      (node (ref "P12") (pin "P$246") (pinfunction "P$0_P$246") (pintype "power_in"))
      (node (ref "P12") (pin "P$247") (pinfunction "P$0_P$247") (pintype "power_in"))
      (node (ref "P12") (pin "P$248") (pinfunction "P$0_P$248") (pintype "power_in"))
      (node (ref "P12") (pin "P$249") (pinfunction "P$0_P$249") (pintype "power_in"))
      (node (ref "P12") (pin "P$25") (pinfunction "P$0_P$25") (pintype "power_in"))
      (node (ref "P12") (pin "P$250") (pinfunction "P$0_P$250") (pintype "power_in"))
      (node (ref "P12") (pin "P$251") (pinfunction "P$0_P$251") (pintype "power_in"))
      (node (ref "P12") (pin "P$252") (pinfunction "P$0_P$252") (pintype "power_in"))
      (node (ref "P12") (pin "P$253") (pinfunction "P$0_P$253") (pintype "power_in"))
      (node (ref "P12") (pin "P$254") (pinfunction "P$0_P$254") (pintype "power_in"))
      (node (ref "P12") (pin "P$255") (pinfunction "P$0_P$255") (pintype "power_in"))
      (node (ref "P12") (pin "P$256") (pinfunction "P$0_P$256") (pintype "power_in"))
      (node (ref "P12") (pin "P$257") (pinfunction "P$0_P$257") (pintype "power_in"))
      (node (ref "P12") (pin "P$258") (pinfunction "P$0_P$258") (pintype "power_in"))
      (node (ref "P12") (pin "P$259") (pinfunction "P$0_P$259") (pintype "power_in"))
      (node (ref "P12") (pin "P$26") (pinfunction "P$0_P$26") (pintype "power_in"))
      (node (ref "P12") (pin "P$260") (pinfunction "P$0_P$260") (pintype "power_in"))
      (node (ref "P12") (pin "P$261") (pinfunction "P$0_P$261") (pintype "power_in"))
      (node (ref "P12") (pin "P$262") (pinfunction "P$0_P$262") (pintype "power_in"))
      (node (ref "P12") (pin "P$263") (pinfunction "P$0_P$263") (pintype "power_in"))
      (node (ref "P12") (pin "P$264") (pinfunction "P$0_P$264") (pintype "power_in"))
      (node (ref "P12") (pin "P$265") (pinfunction "P$0_P$265") (pintype "power_in"))
      (node (ref "P12") (pin "P$266") (pinfunction "P$0_P$266") (pintype "power_in"))
      (node (ref "P12") (pin "P$267") (pinfunction "P$0_P$267") (pintype "power_in"))
      (node (ref "P12") (pin "P$268") (pinfunction "P$0_P$268") (pintype "power_in"))
      (node (ref "P12") (pin "P$269") (pinfunction "P$0_P$269") (pintype "power_in"))
      (node (ref "P12") (pin "P$27") (pinfunction "P$0_P$27") (pintype "power_in"))
      (node (ref "P12") (pin "P$270") (pinfunction "P$0_P$270") (pintype "power_in"))
      (node (ref "P12") (pin "P$271") (pinfunction "P$0_P$271") (pintype "power_in"))
      (node (ref "P12") (pin "P$272") (pinfunction "P$0_P$272") (pintype "power_in"))
      (node (ref "P12") (pin "P$273") (pinfunction "P$0_P$273") (pintype "power_in"))
      (node (ref "P12") (pin "P$274") (pinfunction "P$0_P$274") (pintype "power_in"))
      (node (ref "P12") (pin "P$275") (pinfunction "P$0_P$275") (pintype "power_in"))
      (node (ref "P12") (pin "P$276") (pinfunction "P$0_P$276") (pintype "power_in"))
      (node (ref "P12") (pin "P$277") (pinfunction "P$0_P$277") (pintype "power_in"))
      (node (ref "P12") (pin "P$278") (pinfunction "P$0_P$278") (pintype "power_in"))
      (node (ref "P12") (pin "P$279") (pinfunction "P$0_P$279") (pintype "power_in"))
      (node (ref "P12") (pin "P$28") (pinfunction "P$0_P$28") (pintype "power_in"))
      (node (ref "P12") (pin "P$280") (pinfunction "P$0_P$280") (pintype "power_in"))
      (node (ref "P12") (pin "P$281") (pinfunction "P$0_P$281") (pintype "power_in"))
      (node (ref "P12") (pin "P$282") (pinfunction "P$0_P$282") (pintype "power_in"))
      (node (ref "P12") (pin "P$283") (pinfunction "P$0_P$283") (pintype "power_in"))
      (node (ref "P12") (pin "P$284") (pinfunction "P$0_P$284") (pintype "power_in"))
      (node (ref "P12") (pin "P$285") (pinfunction "P$0_P$285") (pintype "power_in"))
      (node (ref "P12") (pin "P$286") (pinfunction "P$0_P$286") (pintype "power_in"))
      (node (ref "P12") (pin "P$287") (pinfunction "P$0_P$287") (pintype "power_in"))
      (node (ref "P12") (pin "P$288") (pinfunction "P$0_P$288") (pintype "power_in"))
      (node (ref "P12") (pin "P$289") (pinfunction "P$0_P$289") (pintype "power_in"))
      (node (ref "P12") (pin "P$29") (pinfunction "P$0_P$29") (pintype "power_in"))
      (node (ref "P12") (pin "P$290") (pinfunction "P$0_P$290") (pintype "power_in"))
      (node (ref "P12") (pin "P$291") (pinfunction "P$0_P$291") (pintype "power_in"))
      (node (ref "P12") (pin "P$292") (pinfunction "P$0_P$292") (pintype "power_in"))
      (node (ref "P12") (pin "P$293") (pinfunction "P$0_P$293") (pintype "power_in"))
      (node (ref "P12") (pin "P$294") (pinfunction "P$0_P$294") (pintype "power_in"))
      (node (ref "P12") (pin "P$295") (pinfunction "P$0_P$295") (pintype "power_in"))
      (node (ref "P12") (pin "P$296") (pinfunction "P$0_P$296") (pintype "power_in"))
      (node (ref "P12") (pin "P$297") (pinfunction "P$0_P$297") (pintype "power_in"))
      (node (ref "P12") (pin "P$298") (pinfunction "P$0_P$298") (pintype "power_in"))
      (node (ref "P12") (pin "P$299") (pinfunction "P$0_P$299") (pintype "power_in"))
      (node (ref "P12") (pin "P$3") (pinfunction "P$0_P$3") (pintype "power_in"))
      (node (ref "P12") (pin "P$30") (pinfunction "P$0_P$30") (pintype "power_in"))
      (node (ref "P12") (pin "P$300") (pinfunction "P$0_P$300") (pintype "power_in"))
      (node (ref "P12") (pin "P$301") (pinfunction "P$0_P$301") (pintype "power_in"))
      (node (ref "P12") (pin "P$302") (pinfunction "P$0_P$302") (pintype "power_in"))
      (node (ref "P12") (pin "P$303") (pinfunction "P$0_P$303") (pintype "power_in"))
      (node (ref "P12") (pin "P$304") (pinfunction "P$0_P$304") (pintype "power_in"))
      (node (ref "P12") (pin "P$305") (pinfunction "P$0_P$305") (pintype "power_in"))
      (node (ref "P12") (pin "P$306") (pinfunction "P$0_P$306") (pintype "power_in"))
      (node (ref "P12") (pin "P$307") (pinfunction "P$0_P$307") (pintype "power_in"))
      (node (ref "P12") (pin "P$308") (pinfunction "P$0_P$308") (pintype "power_in"))
      (node (ref "P12") (pin "P$309") (pinfunction "P$0_P$309") (pintype "power_in"))
      (node (ref "P12") (pin "P$31") (pinfunction "P$0_P$31") (pintype "power_in"))
      (node (ref "P12") (pin "P$310") (pinfunction "P$0_P$310") (pintype "power_in"))
      (node (ref "P12") (pin "P$311") (pinfunction "P$0_P$311") (pintype "power_in"))
      (node (ref "P12") (pin "P$312") (pinfunction "P$0_P$312") (pintype "power_in"))
      (node (ref "P12") (pin "P$313") (pinfunction "P$0_P$313") (pintype "power_in"))
      (node (ref "P12") (pin "P$314") (pinfunction "P$0_P$314") (pintype "power_in"))
      (node (ref "P12") (pin "P$315") (pinfunction "P$0_P$315") (pintype "power_in"))
      (node (ref "P12") (pin "P$316") (pinfunction "P$0_P$316") (pintype "power_in"))
      (node (ref "P12") (pin "P$317") (pinfunction "P$0_P$317") (pintype "power_in"))
      (node (ref "P12") (pin "P$318") (pinfunction "P$0_P$318") (pintype "power_in"))
      (node (ref "P12") (pin "P$319") (pinfunction "P$0_P$319") (pintype "power_in"))
      (node (ref "P12") (pin "P$32") (pinfunction "P$0_P$32") (pintype "power_in"))
      (node (ref "P12") (pin "P$320") (pinfunction "P$0_P$320") (pintype "power_in"))
      (node (ref "P12") (pin "P$321") (pinfunction "P$0_P$321") (pintype "power_in"))
      (node (ref "P12") (pin "P$322") (pinfunction "P$0_P$322") (pintype "power_in"))
      (node (ref "P12") (pin "P$323") (pinfunction "P$0_P$323") (pintype "power_in"))
      (node (ref "P12") (pin "P$324") (pinfunction "P$0_P$324") (pintype "power_in"))
      (node (ref "P12") (pin "P$325") (pinfunction "P$0_P$325") (pintype "power_in"))
      (node (ref "P12") (pin "P$326") (pinfunction "P$0_P$326") (pintype "power_in"))
      (node (ref "P12") (pin "P$327") (pinfunction "P$0_P$327") (pintype "power_in"))
      (node (ref "P12") (pin "P$328") (pinfunction "P$0_P$328") (pintype "power_in"))
      (node (ref "P12") (pin "P$329") (pinfunction "P$0_P$329") (pintype "power_in"))
      (node (ref "P12") (pin "P$33") (pinfunction "P$0_P$33") (pintype "power_in"))
      (node (ref "P12") (pin "P$330") (pinfunction "P$0_P$330") (pintype "power_in"))
      (node (ref "P12") (pin "P$331") (pinfunction "P$0_P$331") (pintype "power_in"))
      (node (ref "P12") (pin "P$332") (pinfunction "P$0_P$332") (pintype "power_in"))
      (node (ref "P12") (pin "P$333") (pinfunction "P$0_P$333") (pintype "power_in"))
      (node (ref "P12") (pin "P$334") (pinfunction "P$0_P$334") (pintype "power_in"))
      (node (ref "P12") (pin "P$335") (pinfunction "P$0_P$335") (pintype "power_in"))
      (node (ref "P12") (pin "P$336") (pinfunction "P$0_P$336") (pintype "power_in"))
      (node (ref "P12") (pin "P$337") (pinfunction "P$0_P$337") (pintype "power_in"))
      (node (ref "P12") (pin "P$338") (pinfunction "P$0_P$338") (pintype "power_in"))
      (node (ref "P12") (pin "P$339") (pinfunction "P$0_P$339") (pintype "power_in"))
      (node (ref "P12") (pin "P$34") (pinfunction "P$0_P$34") (pintype "power_in"))
      (node (ref "P12") (pin "P$340") (pinfunction "P$0_P$340") (pintype "power_in"))
      (node (ref "P12") (pin "P$341") (pinfunction "P$0_P$341") (pintype "power_in"))
      (node (ref "P12") (pin "P$342") (pinfunction "P$0_P$342") (pintype "power_in"))
      (node (ref "P12") (pin "P$343") (pinfunction "P$0_P$343") (pintype "power_in"))
      (node (ref "P12") (pin "P$344") (pinfunction "P$0_P$344") (pintype "power_in"))
      (node (ref "P12") (pin "P$345") (pinfunction "P$0_P$345") (pintype "power_in"))
      (node (ref "P12") (pin "P$346") (pinfunction "P$0_P$346") (pintype "power_in"))
      (node (ref "P12") (pin "P$347") (pinfunction "P$0_P$347") (pintype "power_in"))
      (node (ref "P12") (pin "P$348") (pinfunction "P$0_P$348") (pintype "power_in"))
      (node (ref "P12") (pin "P$349") (pinfunction "P$0_P$349") (pintype "power_in"))
      (node (ref "P12") (pin "P$35") (pinfunction "P$0_P$35") (pintype "power_in"))
      (node (ref "P12") (pin "P$350") (pinfunction "P$0_P$350") (pintype "power_in"))
      (node (ref "P12") (pin "P$351") (pinfunction "P$0_P$351") (pintype "power_in"))
      (node (ref "P12") (pin "P$352") (pinfunction "P$0_P$352") (pintype "power_in"))
      (node (ref "P12") (pin "P$353") (pinfunction "P$0_P$353") (pintype "power_in"))
      (node (ref "P12") (pin "P$354") (pinfunction "P$0_P$354") (pintype "power_in"))
      (node (ref "P12") (pin "P$355") (pinfunction "P$0_P$355") (pintype "power_in"))
      (node (ref "P12") (pin "P$356") (pinfunction "P$0_P$356") (pintype "power_in"))
      (node (ref "P12") (pin "P$357") (pinfunction "P$0_P$357") (pintype "power_in"))
      (node (ref "P12") (pin "P$358") (pinfunction "P$0_P$358") (pintype "power_in"))
      (node (ref "P12") (pin "P$359") (pinfunction "P$0_P$359") (pintype "power_in"))
      (node (ref "P12") (pin "P$36") (pinfunction "P$0_P$36") (pintype "power_in"))
      (node (ref "P12") (pin "P$360") (pinfunction "P$0_P$360") (pintype "power_in"))
      (node (ref "P12") (pin "P$37") (pinfunction "P$0_P$37") (pintype "power_in"))
      (node (ref "P12") (pin "P$38") (pinfunction "P$0_P$38") (pintype "power_in"))
      (node (ref "P12") (pin "P$39") (pinfunction "P$0_P$39") (pintype "power_in"))
      (node (ref "P12") (pin "P$4") (pinfunction "P$0_P$4") (pintype "power_in"))
      (node (ref "P12") (pin "P$40") (pinfunction "P$0_P$40") (pintype "power_in"))
      (node (ref "P12") (pin "P$41") (pinfunction "P$0_P$41") (pintype "power_in"))
      (node (ref "P12") (pin "P$42") (pinfunction "P$0_P$42") (pintype "power_in"))
      (node (ref "P12") (pin "P$43") (pinfunction "P$0_P$43") (pintype "power_in"))
      (node (ref "P12") (pin "P$44") (pinfunction "P$0_P$44") (pintype "power_in"))
      (node (ref "P12") (pin "P$45") (pinfunction "P$0_P$45") (pintype "power_in"))
      (node (ref "P12") (pin "P$46") (pinfunction "P$0_P$46") (pintype "power_in"))
      (node (ref "P12") (pin "P$47") (pinfunction "P$0_P$47") (pintype "power_in"))
      (node (ref "P12") (pin "P$48") (pinfunction "P$0_P$48") (pintype "power_in"))
      (node (ref "P12") (pin "P$49") (pinfunction "P$0_P$49") (pintype "power_in"))
      (node (ref "P12") (pin "P$5") (pinfunction "P$0_P$5") (pintype "power_in"))
      (node (ref "P12") (pin "P$50") (pinfunction "P$0_P$50") (pintype "power_in"))
      (node (ref "P12") (pin "P$51") (pinfunction "P$0_P$51") (pintype "power_in"))
      (node (ref "P12") (pin "P$52") (pinfunction "P$0_P$52") (pintype "power_in"))
      (node (ref "P12") (pin "P$53") (pinfunction "P$0_P$53") (pintype "power_in"))
      (node (ref "P12") (pin "P$54") (pinfunction "P$0_P$54") (pintype "power_in"))
      (node (ref "P12") (pin "P$55") (pinfunction "P$0_P$55") (pintype "power_in"))
      (node (ref "P12") (pin "P$56") (pinfunction "P$0_P$56") (pintype "power_in"))
      (node (ref "P12") (pin "P$57") (pinfunction "P$0_P$57") (pintype "power_in"))
      (node (ref "P12") (pin "P$58") (pinfunction "P$0_P$58") (pintype "power_in"))
      (node (ref "P12") (pin "P$59") (pinfunction "P$0_P$59") (pintype "power_in"))
      (node (ref "P12") (pin "P$6") (pinfunction "P$0_P$6") (pintype "power_in"))
      (node (ref "P12") (pin "P$60") (pinfunction "P$0_P$60") (pintype "power_in"))
      (node (ref "P12") (pin "P$61") (pinfunction "P$0_P$61") (pintype "power_in"))
      (node (ref "P12") (pin "P$62") (pinfunction "P$0_P$62") (pintype "power_in"))
      (node (ref "P12") (pin "P$63") (pinfunction "P$0_P$63") (pintype "power_in"))
      (node (ref "P12") (pin "P$64") (pinfunction "P$0_P$64") (pintype "power_in"))
      (node (ref "P12") (pin "P$65") (pinfunction "P$0_P$65") (pintype "power_in"))
      (node (ref "P12") (pin "P$66") (pinfunction "P$0_P$66") (pintype "power_in"))
      (node (ref "P12") (pin "P$67") (pinfunction "P$0_P$67") (pintype "power_in"))
      (node (ref "P12") (pin "P$68") (pinfunction "P$0_P$68") (pintype "power_in"))
      (node (ref "P12") (pin "P$69") (pinfunction "P$0_P$69") (pintype "power_in"))
      (node (ref "P12") (pin "P$7") (pinfunction "P$0_P$7") (pintype "power_in"))
      (node (ref "P12") (pin "P$70") (pinfunction "P$0_P$70") (pintype "power_in"))
      (node (ref "P12") (pin "P$71") (pinfunction "P$0_P$71") (pintype "power_in"))
      (node (ref "P12") (pin "P$72") (pinfunction "P$0_P$72") (pintype "power_in"))
      (node (ref "P12") (pin "P$73") (pinfunction "P$0_P$73") (pintype "power_in"))
      (node (ref "P12") (pin "P$74") (pinfunction "P$0_P$74") (pintype "power_in"))
      (node (ref "P12") (pin "P$75") (pinfunction "P$0_P$75") (pintype "power_in"))
      (node (ref "P12") (pin "P$76") (pinfunction "P$0_P$76") (pintype "power_in"))
      (node (ref "P12") (pin "P$77") (pinfunction "P$0_P$77") (pintype "power_in"))
      (node (ref "P12") (pin "P$78") (pinfunction "P$0_P$78") (pintype "power_in"))
      (node (ref "P12") (pin "P$79") (pinfunction "P$0_P$79") (pintype "power_in"))
      (node (ref "P12") (pin "P$8") (pinfunction "P$0_P$8") (pintype "power_in"))
      (node (ref "P12") (pin "P$80") (pinfunction "P$0_P$80") (pintype "power_in"))
      (node (ref "P12") (pin "P$81") (pinfunction "P$0_P$81") (pintype "power_in"))
      (node (ref "P12") (pin "P$82") (pinfunction "P$0_P$82") (pintype "power_in"))
      (node (ref "P12") (pin "P$83") (pinfunction "P$0_P$83") (pintype "power_in"))
      (node (ref "P12") (pin "P$84") (pinfunction "P$0_P$84") (pintype "power_in"))
      (node (ref "P12") (pin "P$85") (pinfunction "P$0_P$85") (pintype "power_in"))
      (node (ref "P12") (pin "P$86") (pinfunction "P$0_P$86") (pintype "power_in"))
      (node (ref "P12") (pin "P$87") (pinfunction "P$0_P$87") (pintype "power_in"))
      (node (ref "P12") (pin "P$88") (pinfunction "P$0_P$88") (pintype "power_in"))
      (node (ref "P12") (pin "P$89") (pinfunction "P$0_P$89") (pintype "power_in"))
      (node (ref "P12") (pin "P$9") (pinfunction "P$0_P$9") (pintype "power_in"))
      (node (ref "P12") (pin "P$90") (pinfunction "P$0_P$90") (pintype "power_in"))
      (node (ref "P12") (pin "P$91") (pinfunction "P$0_P$91") (pintype "power_in"))
      (node (ref "P12") (pin "P$92") (pinfunction "P$0_P$92") (pintype "power_in"))
      (node (ref "P12") (pin "P$93") (pinfunction "P$0_P$93") (pintype "power_in"))
      (node (ref "P12") (pin "P$94") (pinfunction "P$0_P$94") (pintype "power_in"))
      (node (ref "P12") (pin "P$95") (pinfunction "P$0_P$95") (pintype "power_in"))
      (node (ref "P12") (pin "P$96") (pinfunction "P$0_P$96") (pintype "power_in"))
      (node (ref "P12") (pin "P$97") (pinfunction "P$0_P$97") (pintype "power_in"))
      (node (ref "P12") (pin "P$98") (pinfunction "P$0_P$98") (pintype "power_in"))
      (node (ref "P12") (pin "P$99") (pinfunction "P$0_P$99") (pintype "power_in"))
    )
  )
)
